# Front_Unit_5_4.net
KiCad netlist of a schematic drawn in EAGLE
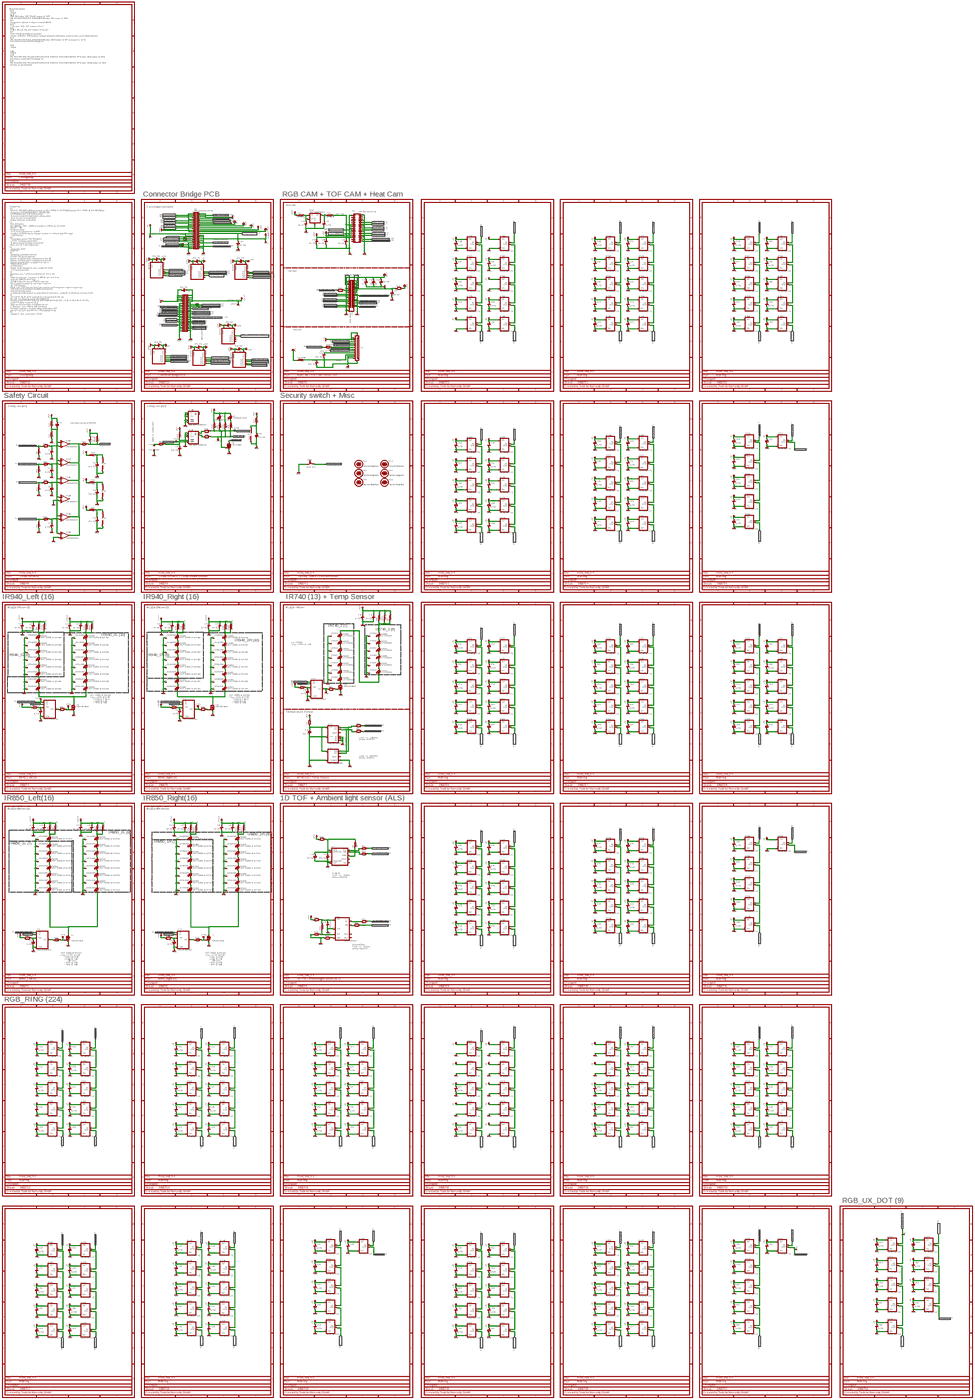
[diagram p0: schematic, sheet 1, overview]
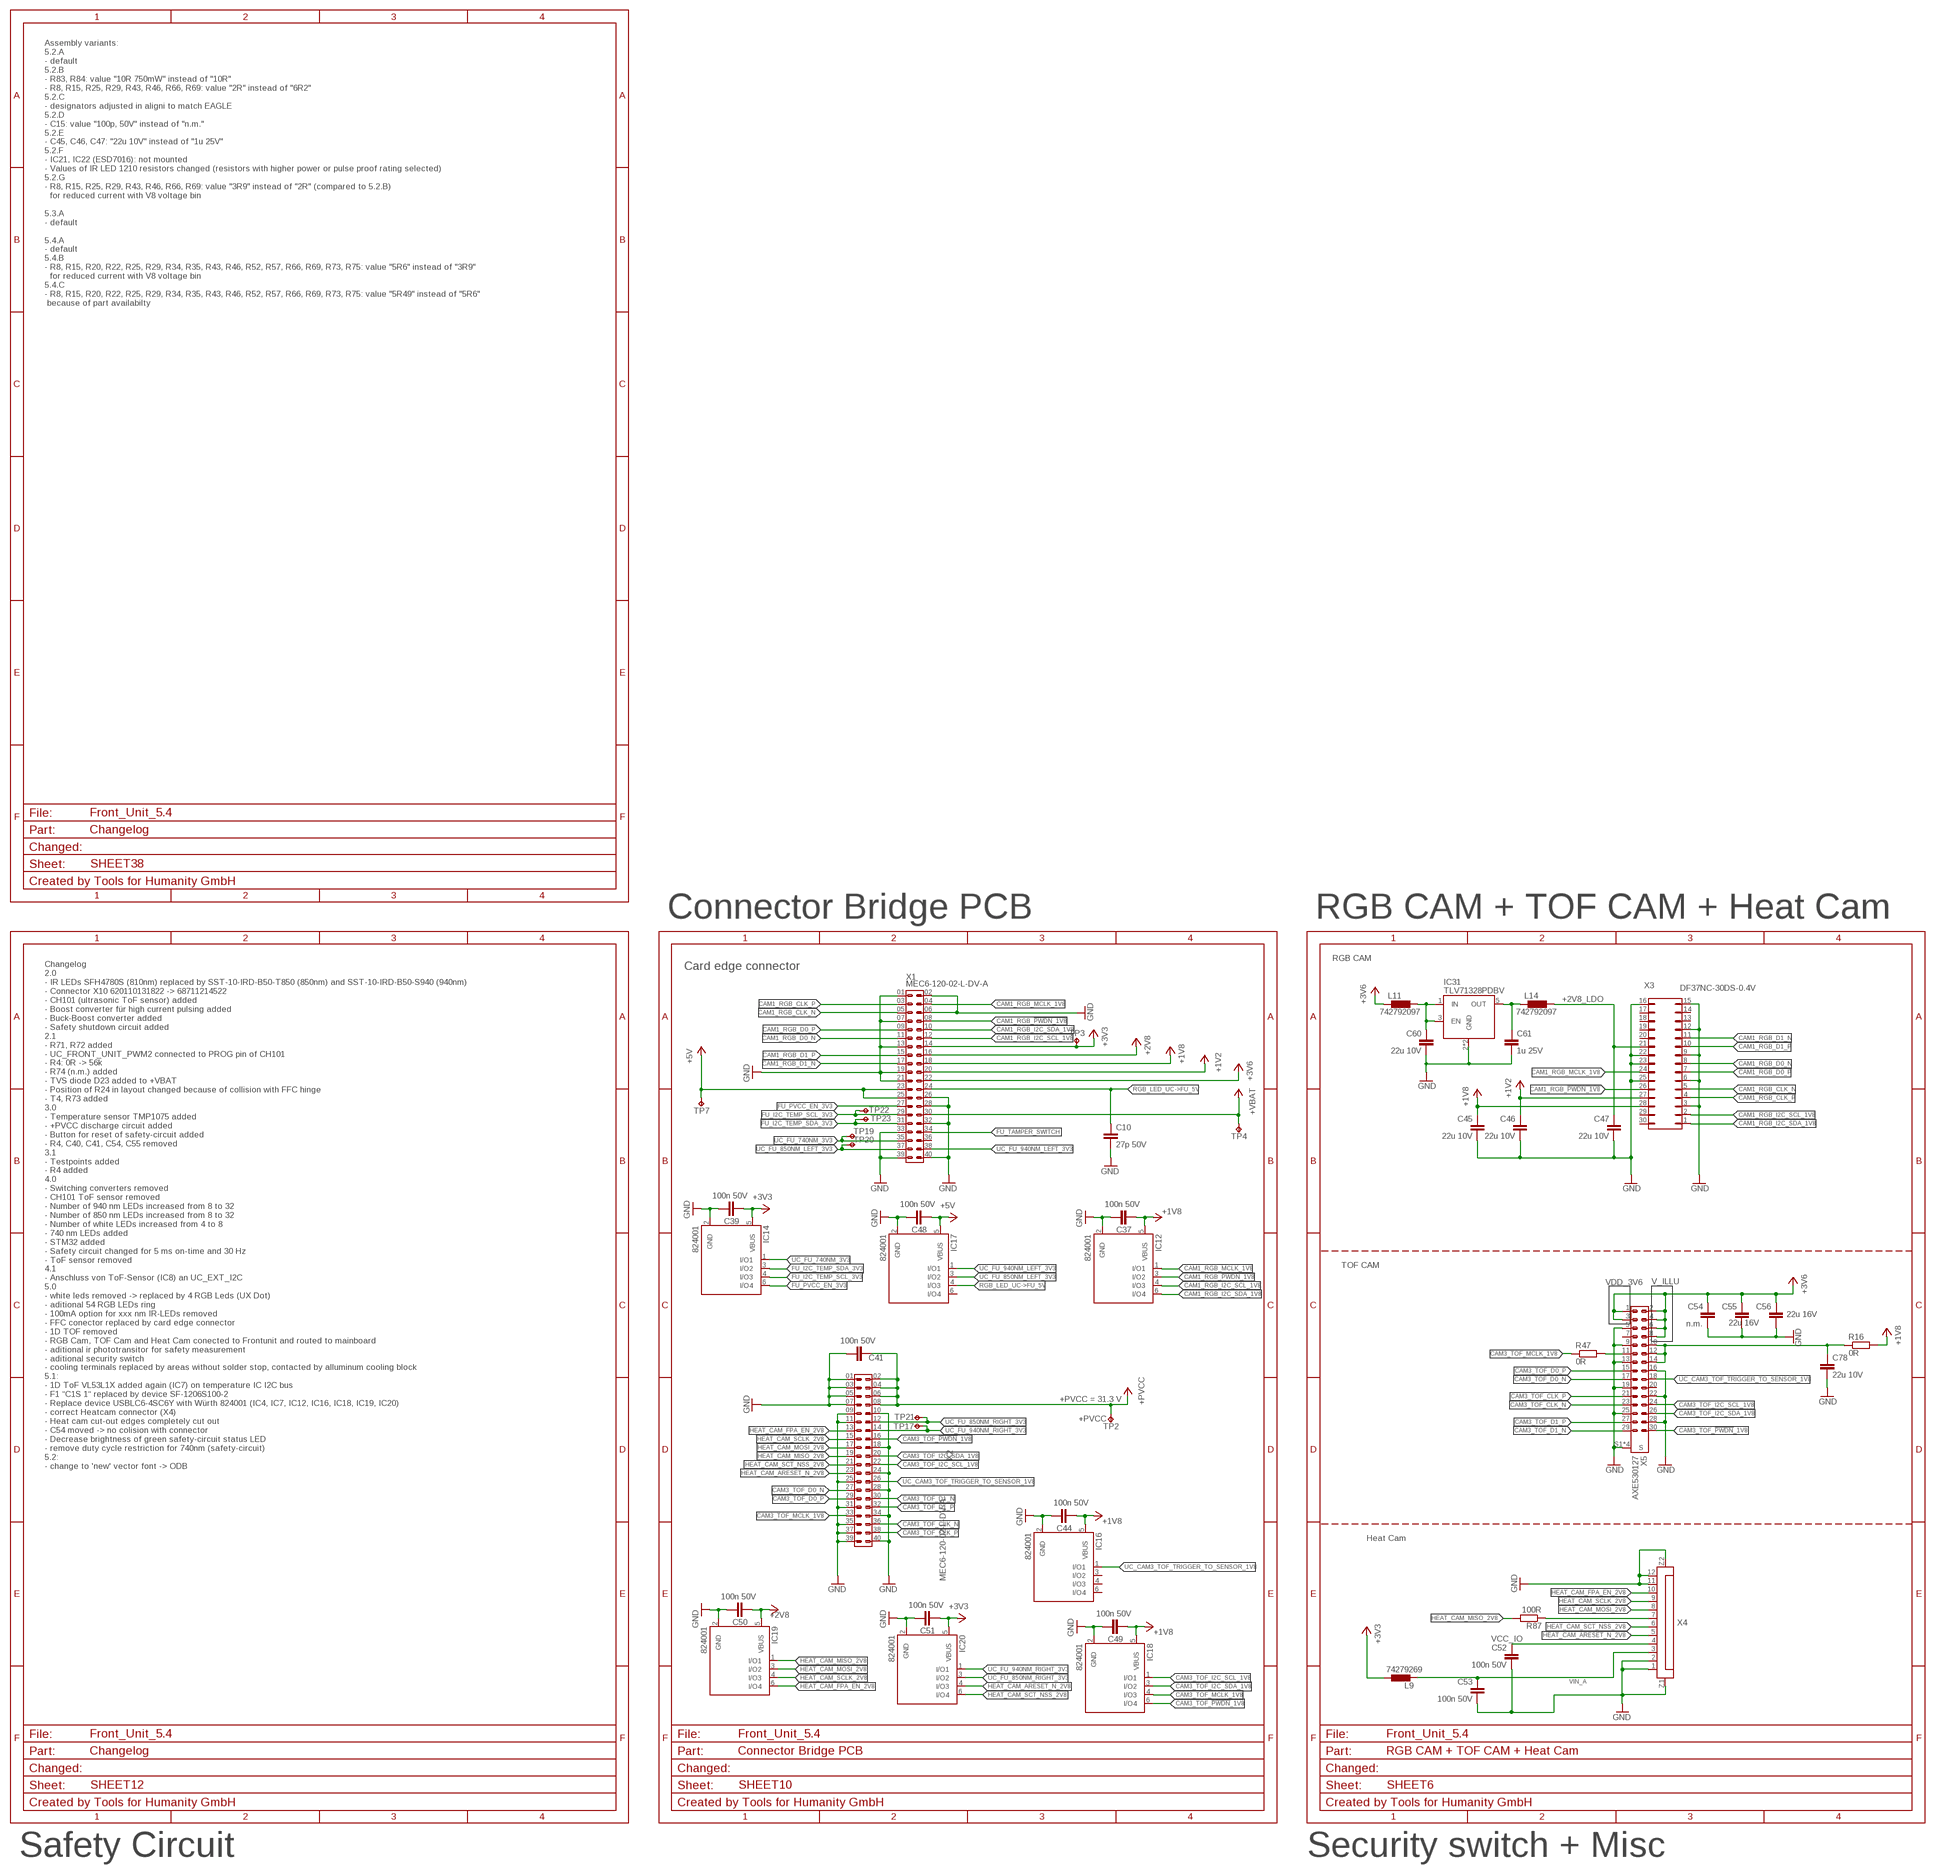
[diagram p1: schematic, sheet 1, part 1 of 8]
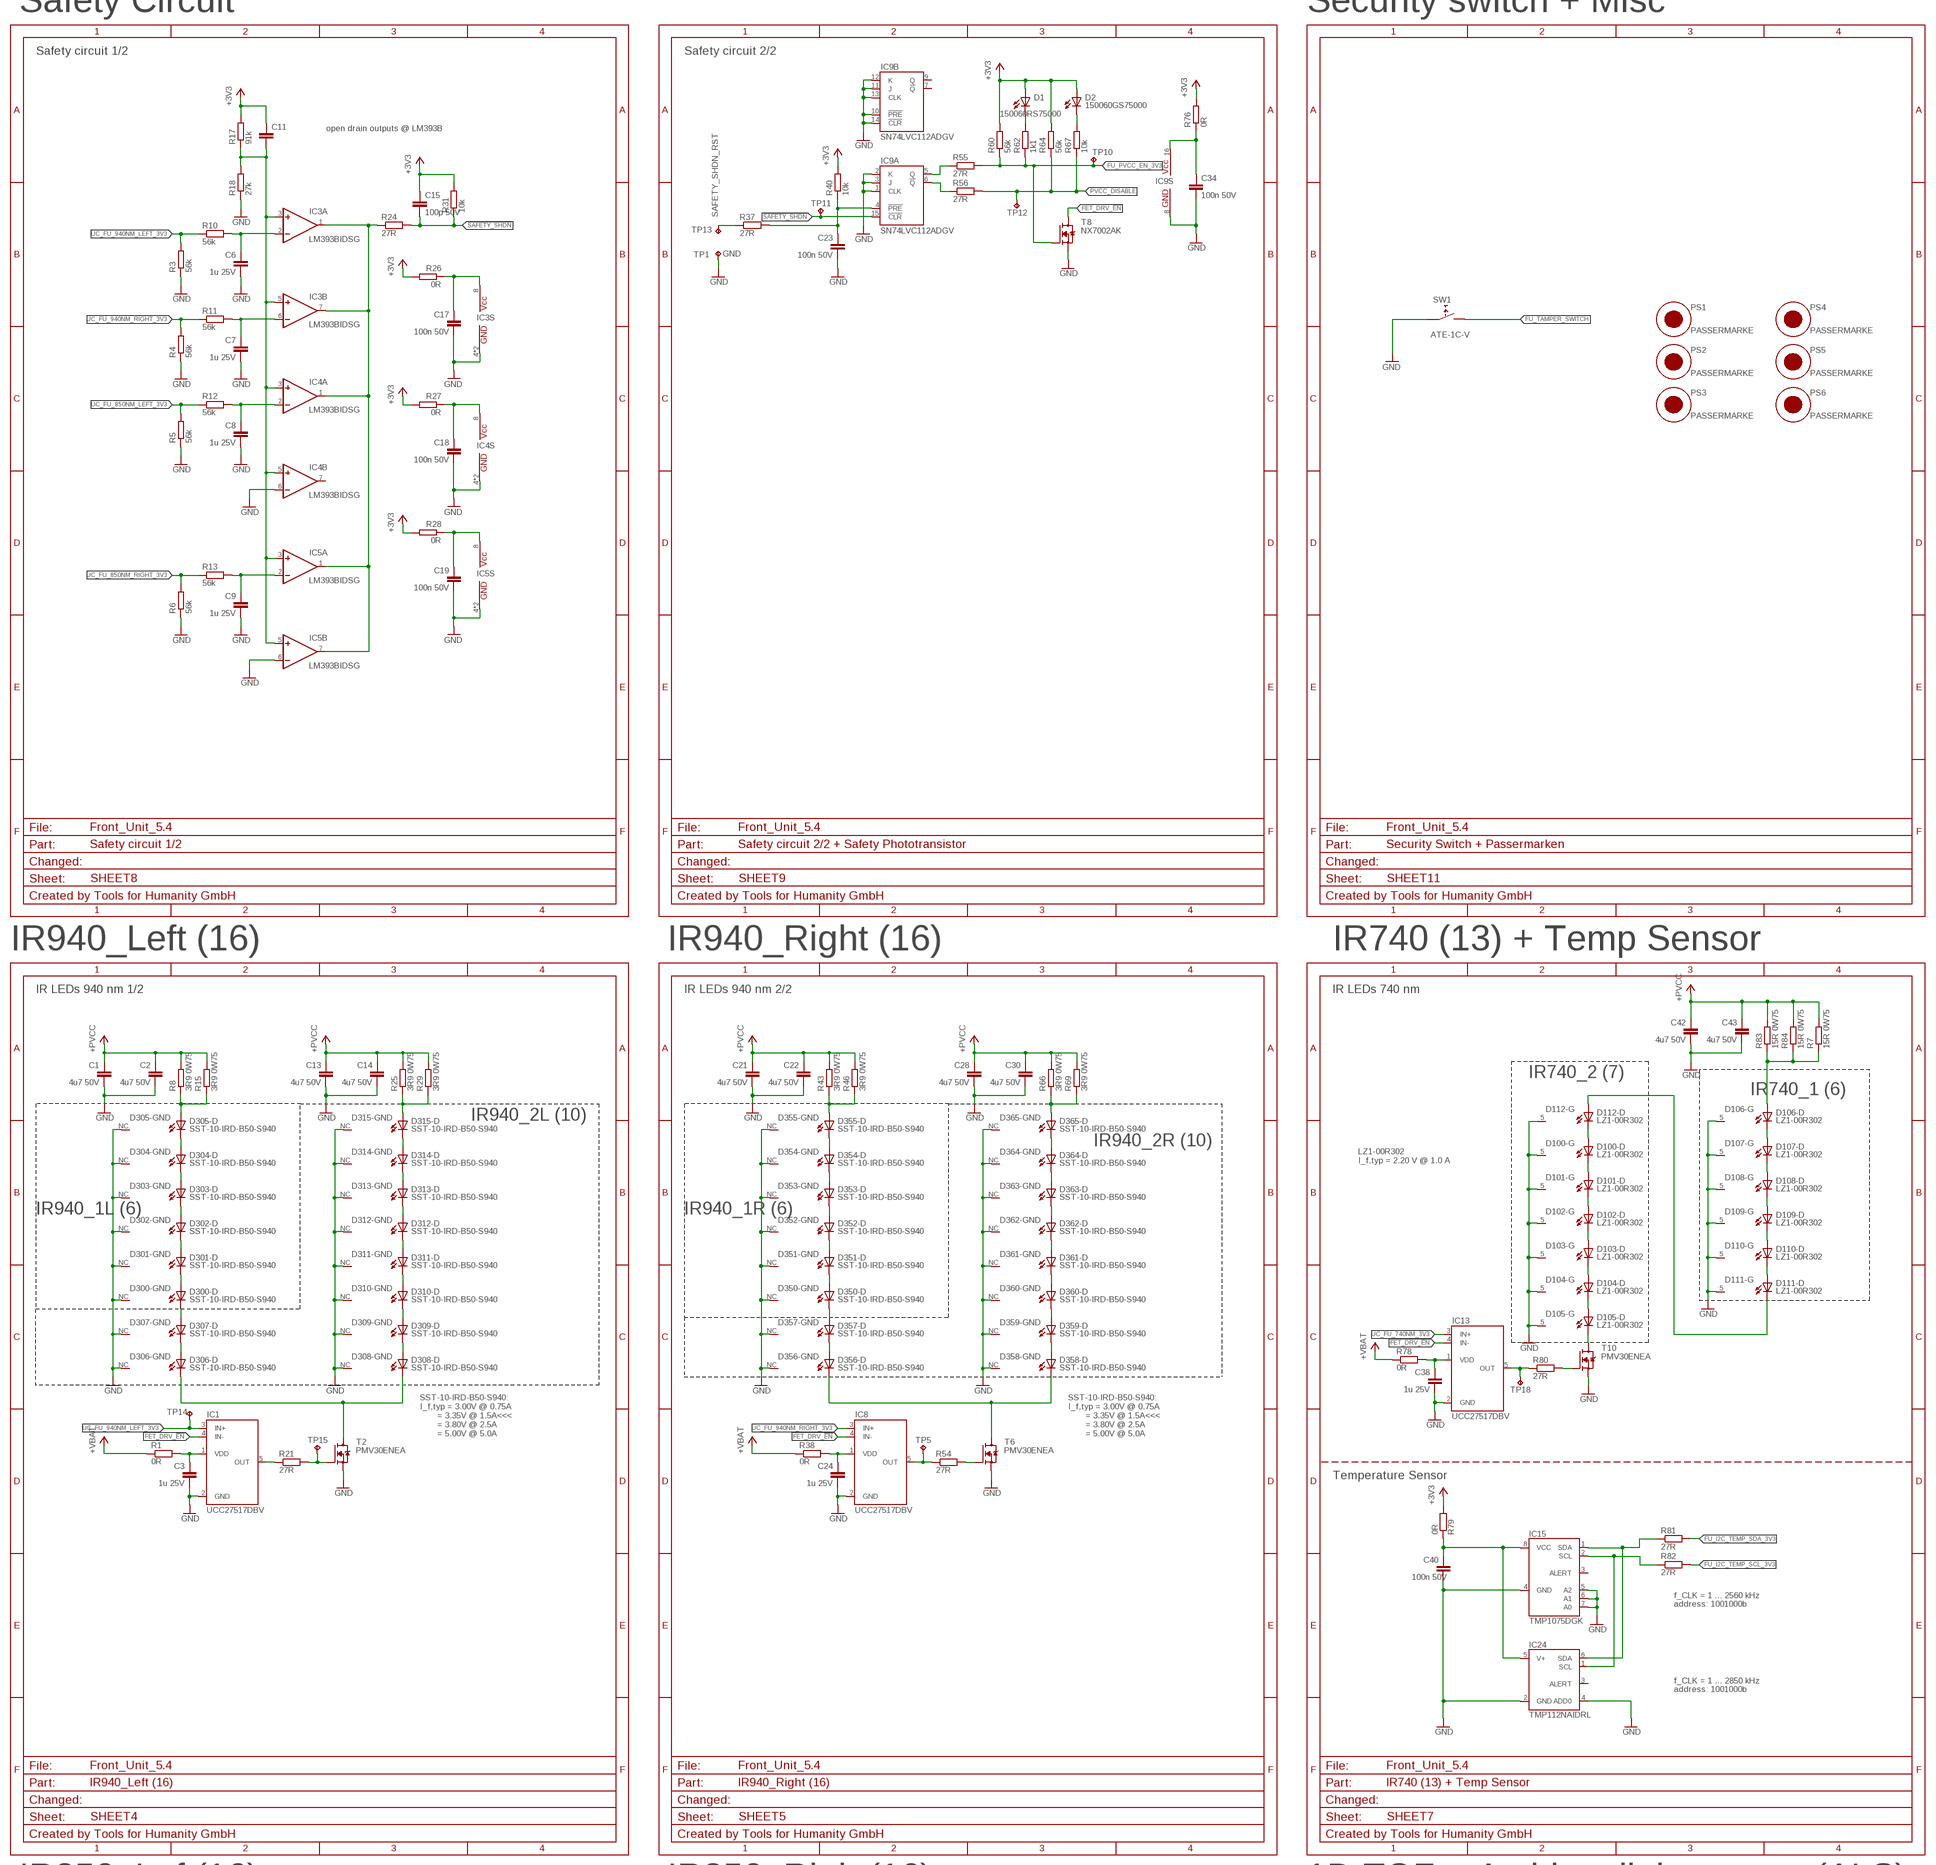
[diagram p2: schematic, sheet 1, part 2 of 8]
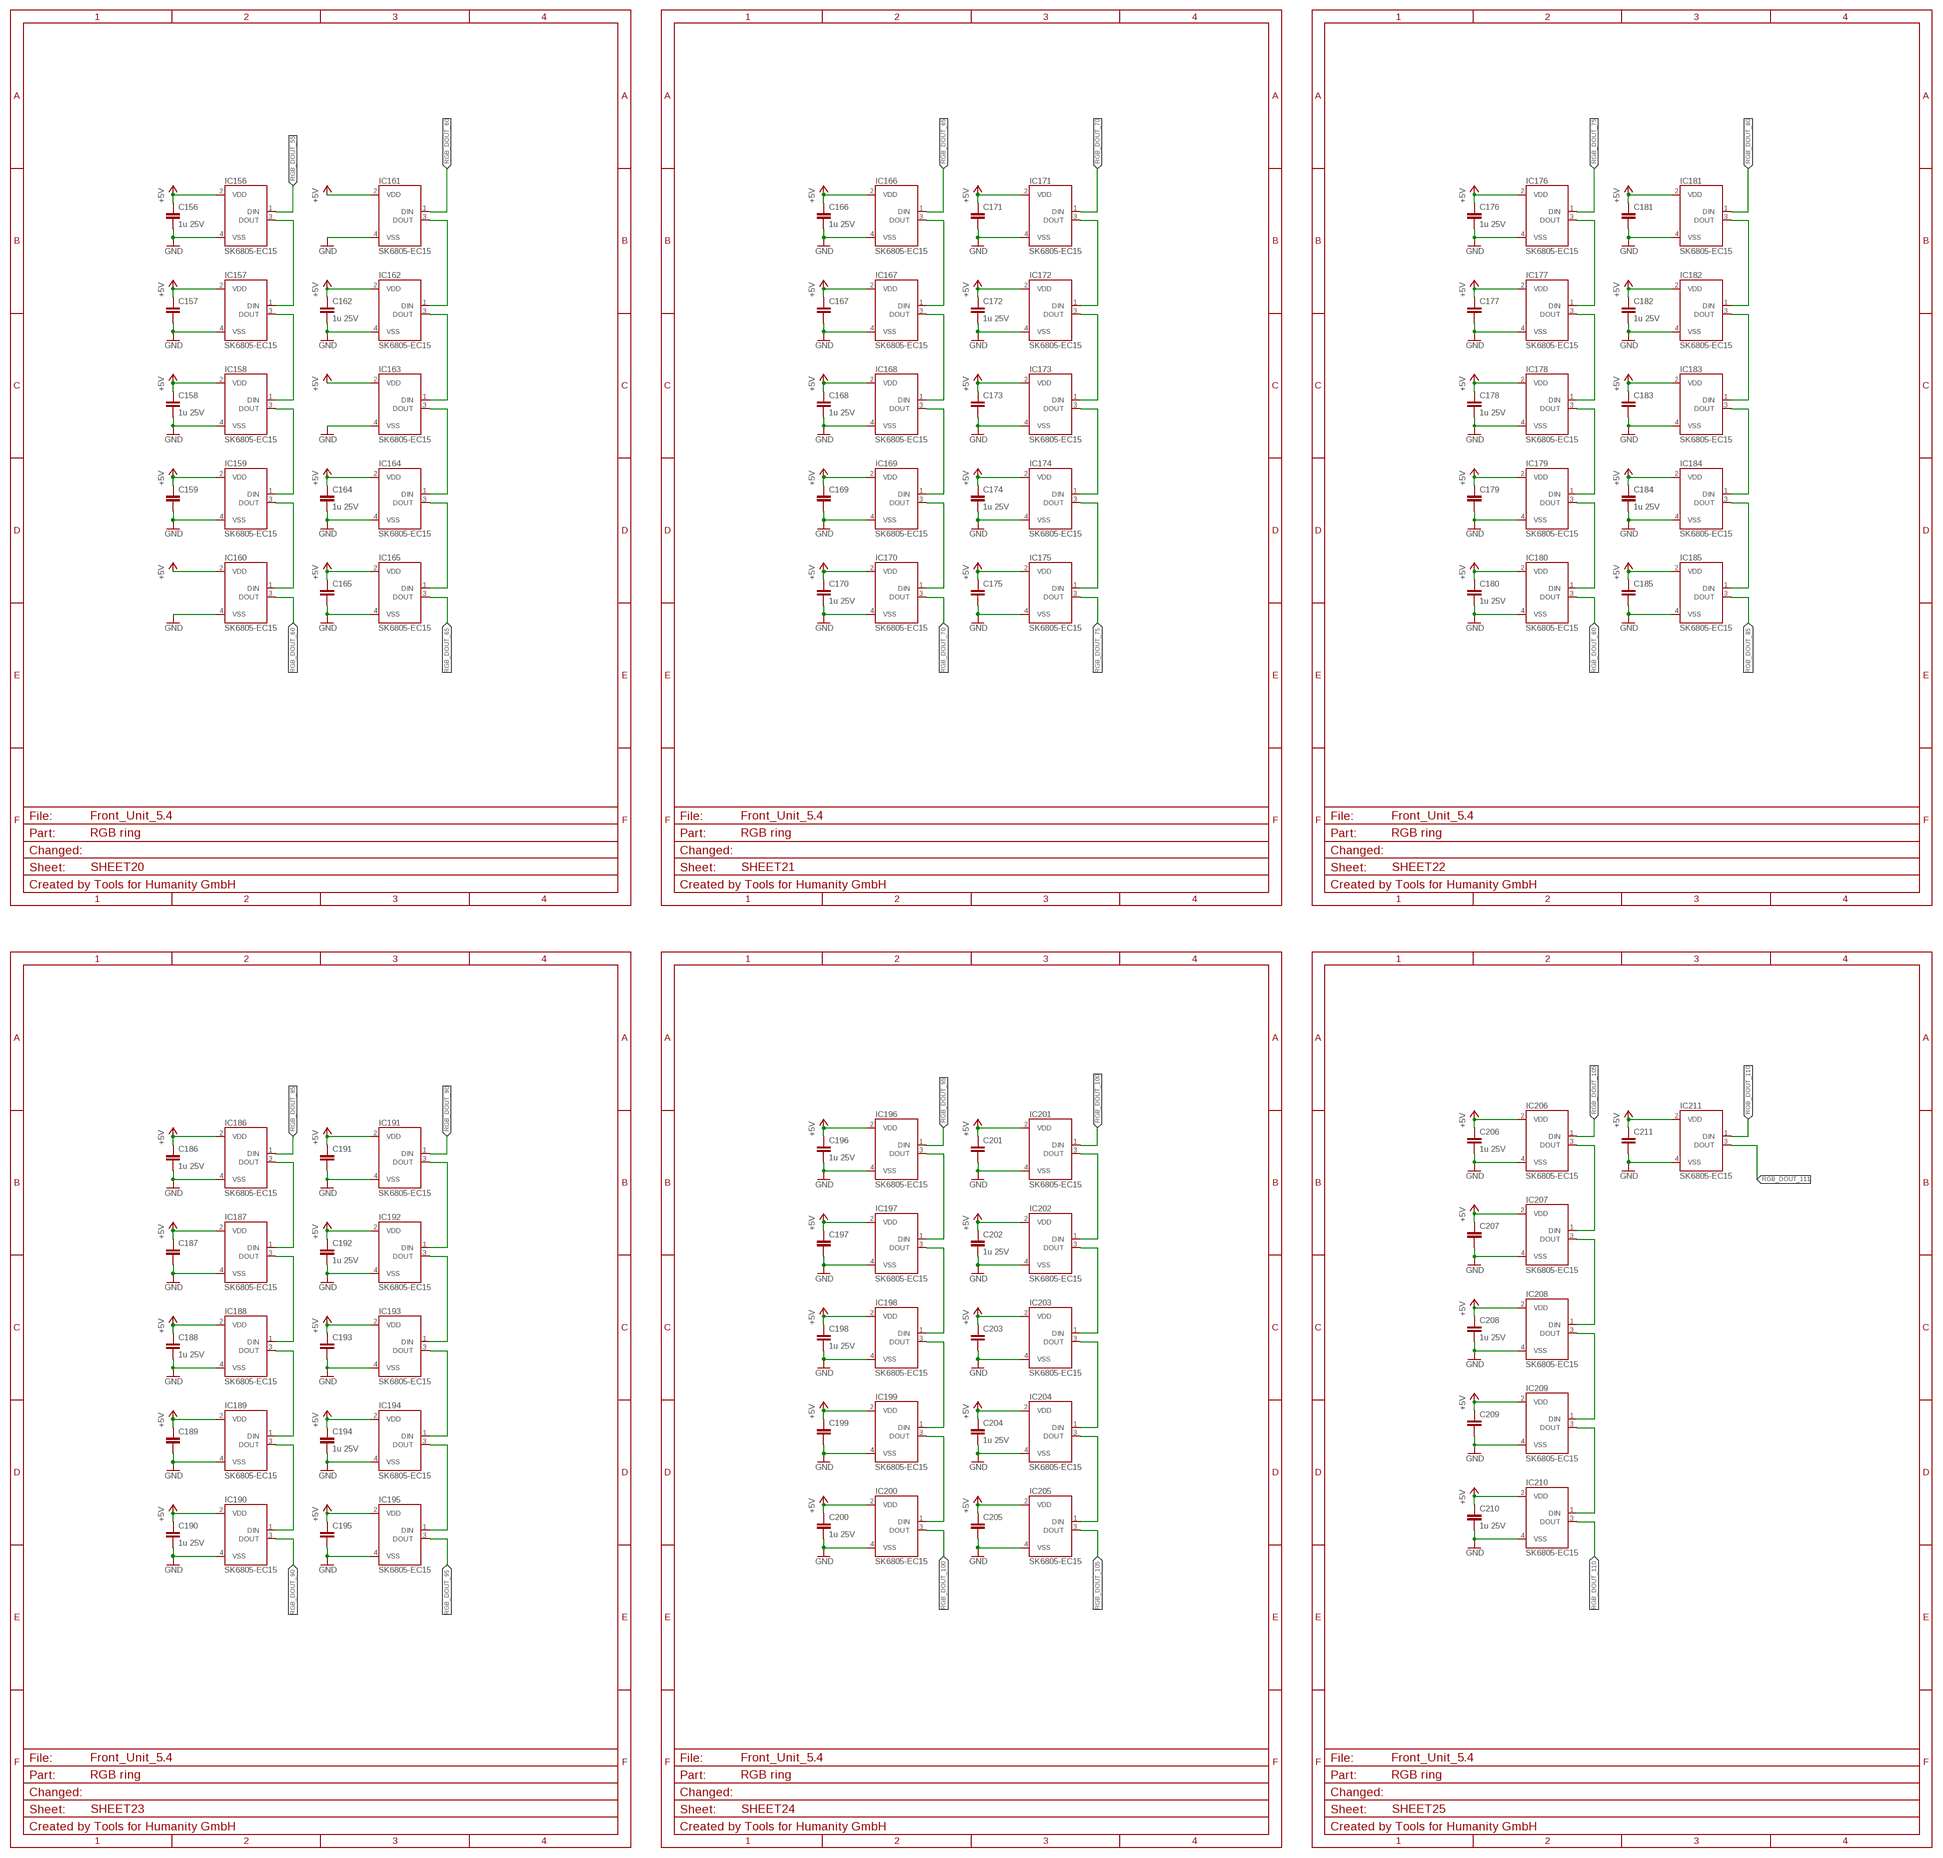
[diagram p3: schematic, sheet 1, part 3 of 8]
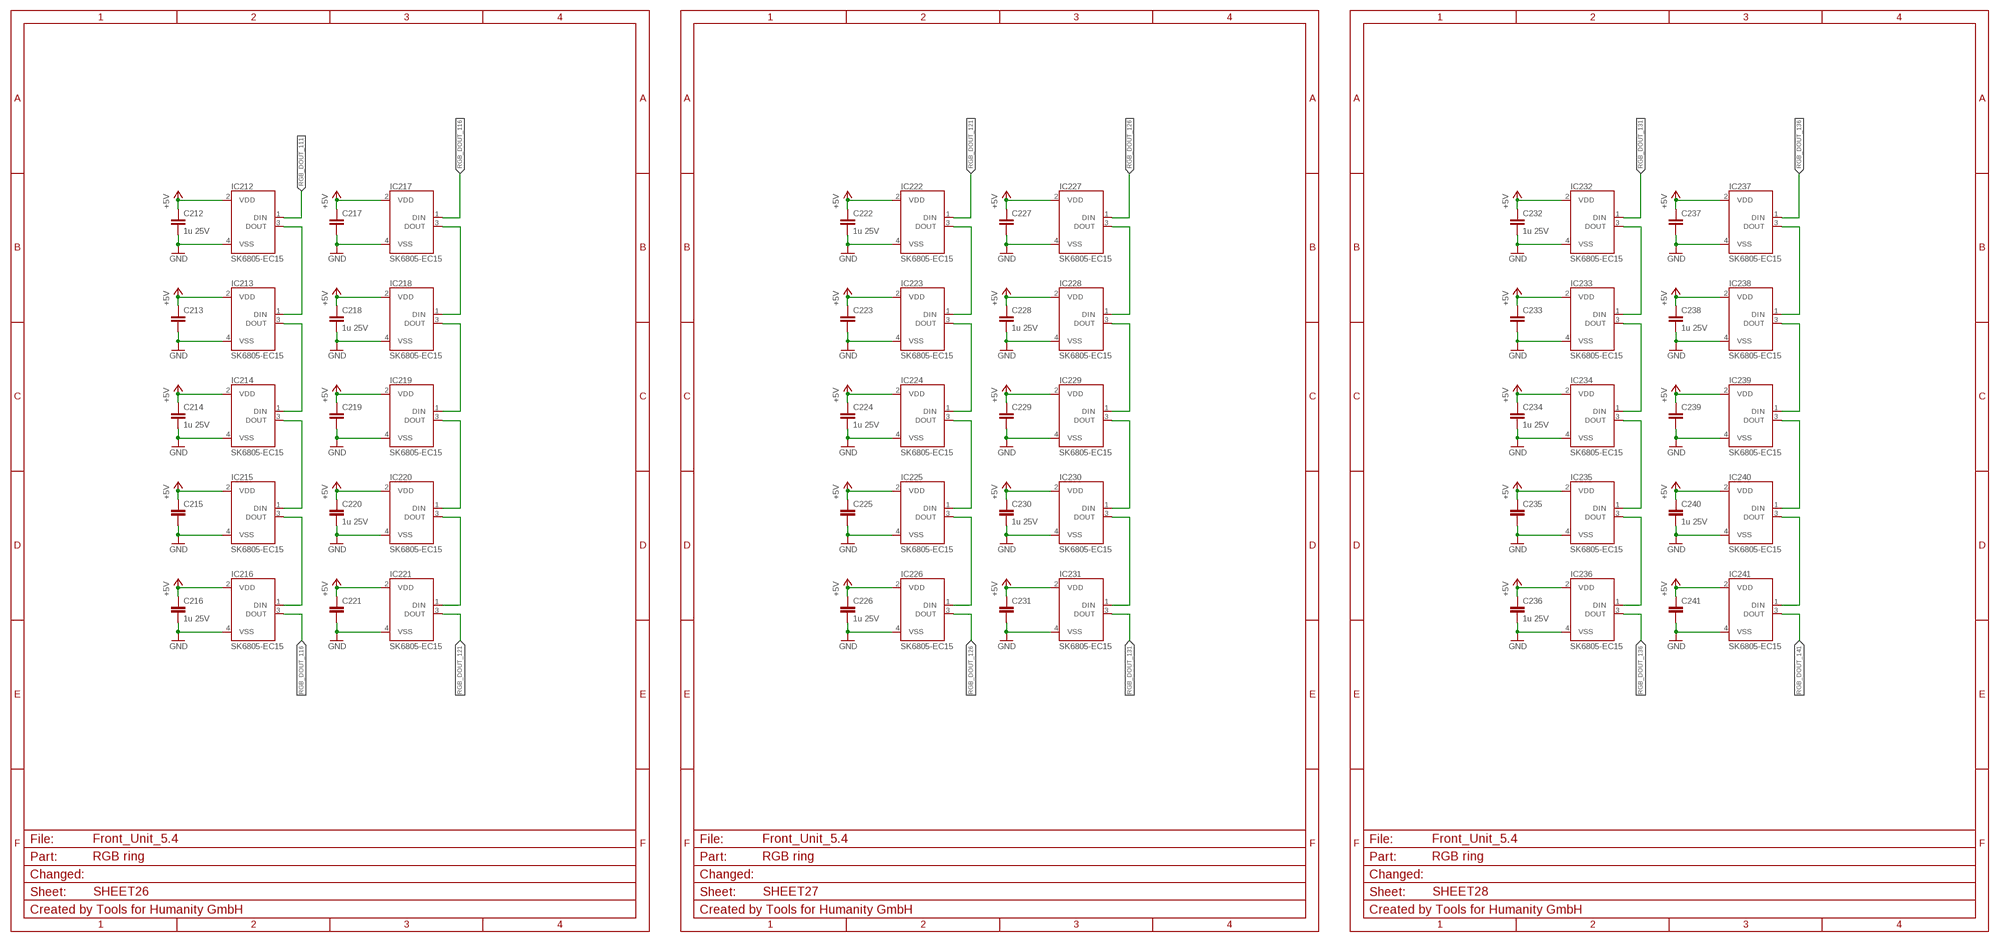
[diagram p4: schematic, sheet 1, part 4 of 8]
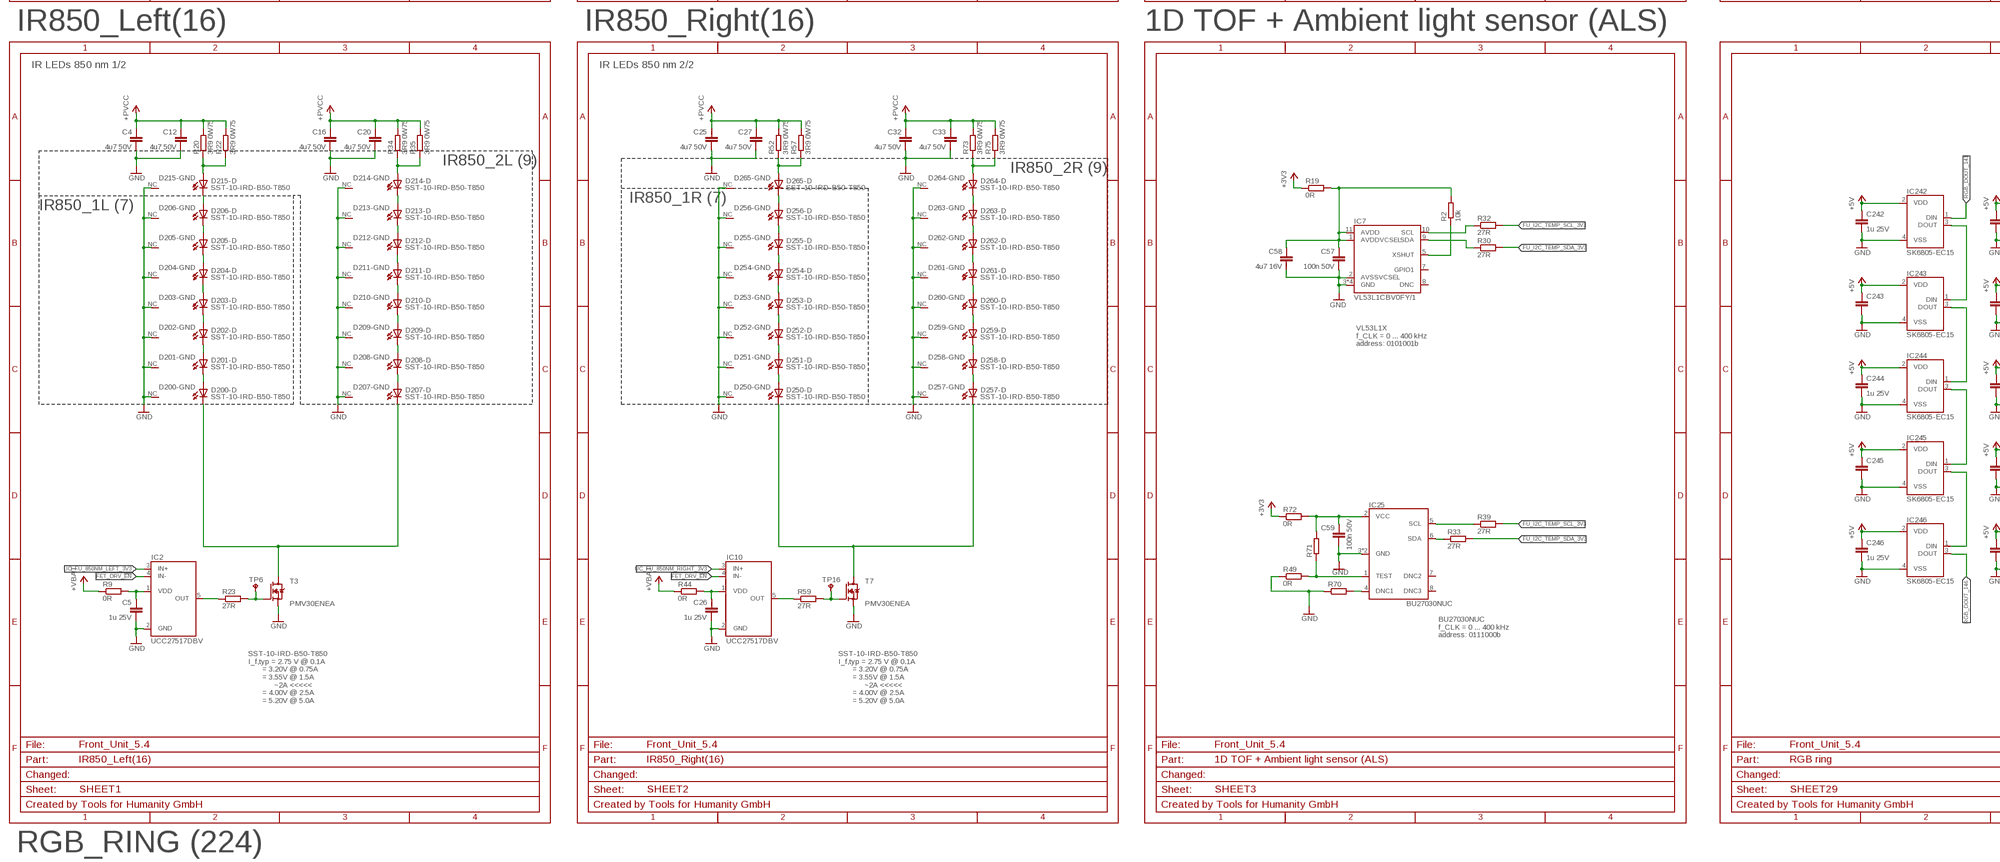
[diagram p5: schematic, sheet 1, part 5 of 8]
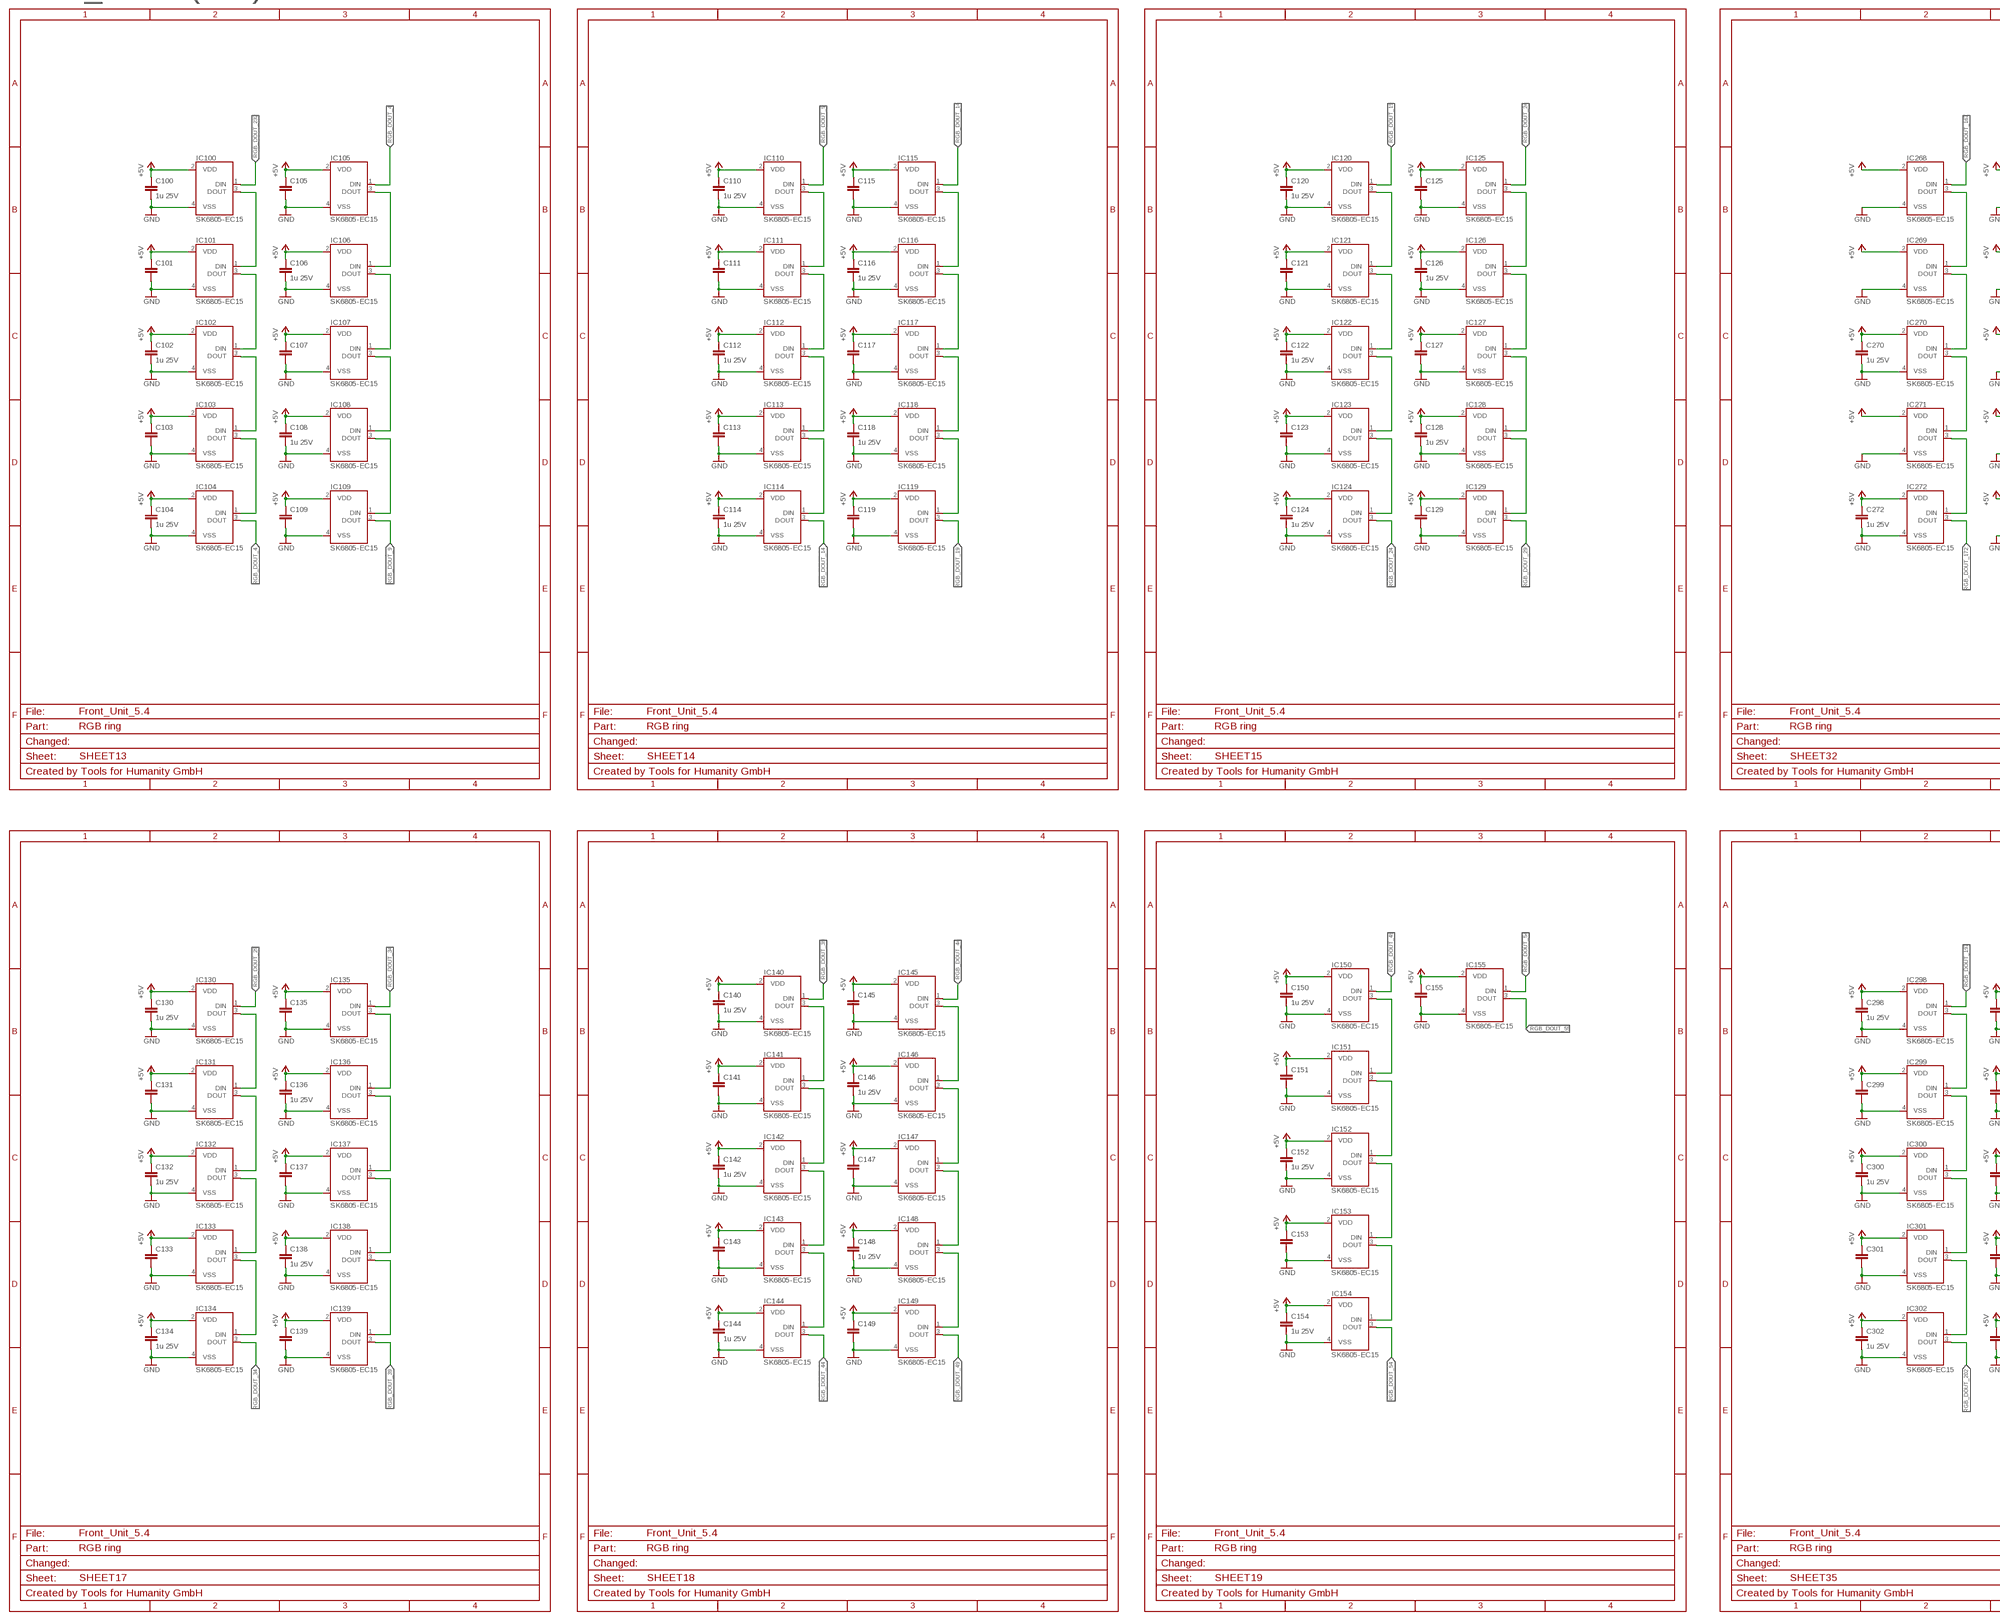
[diagram p6: schematic, sheet 1, part 6 of 8]
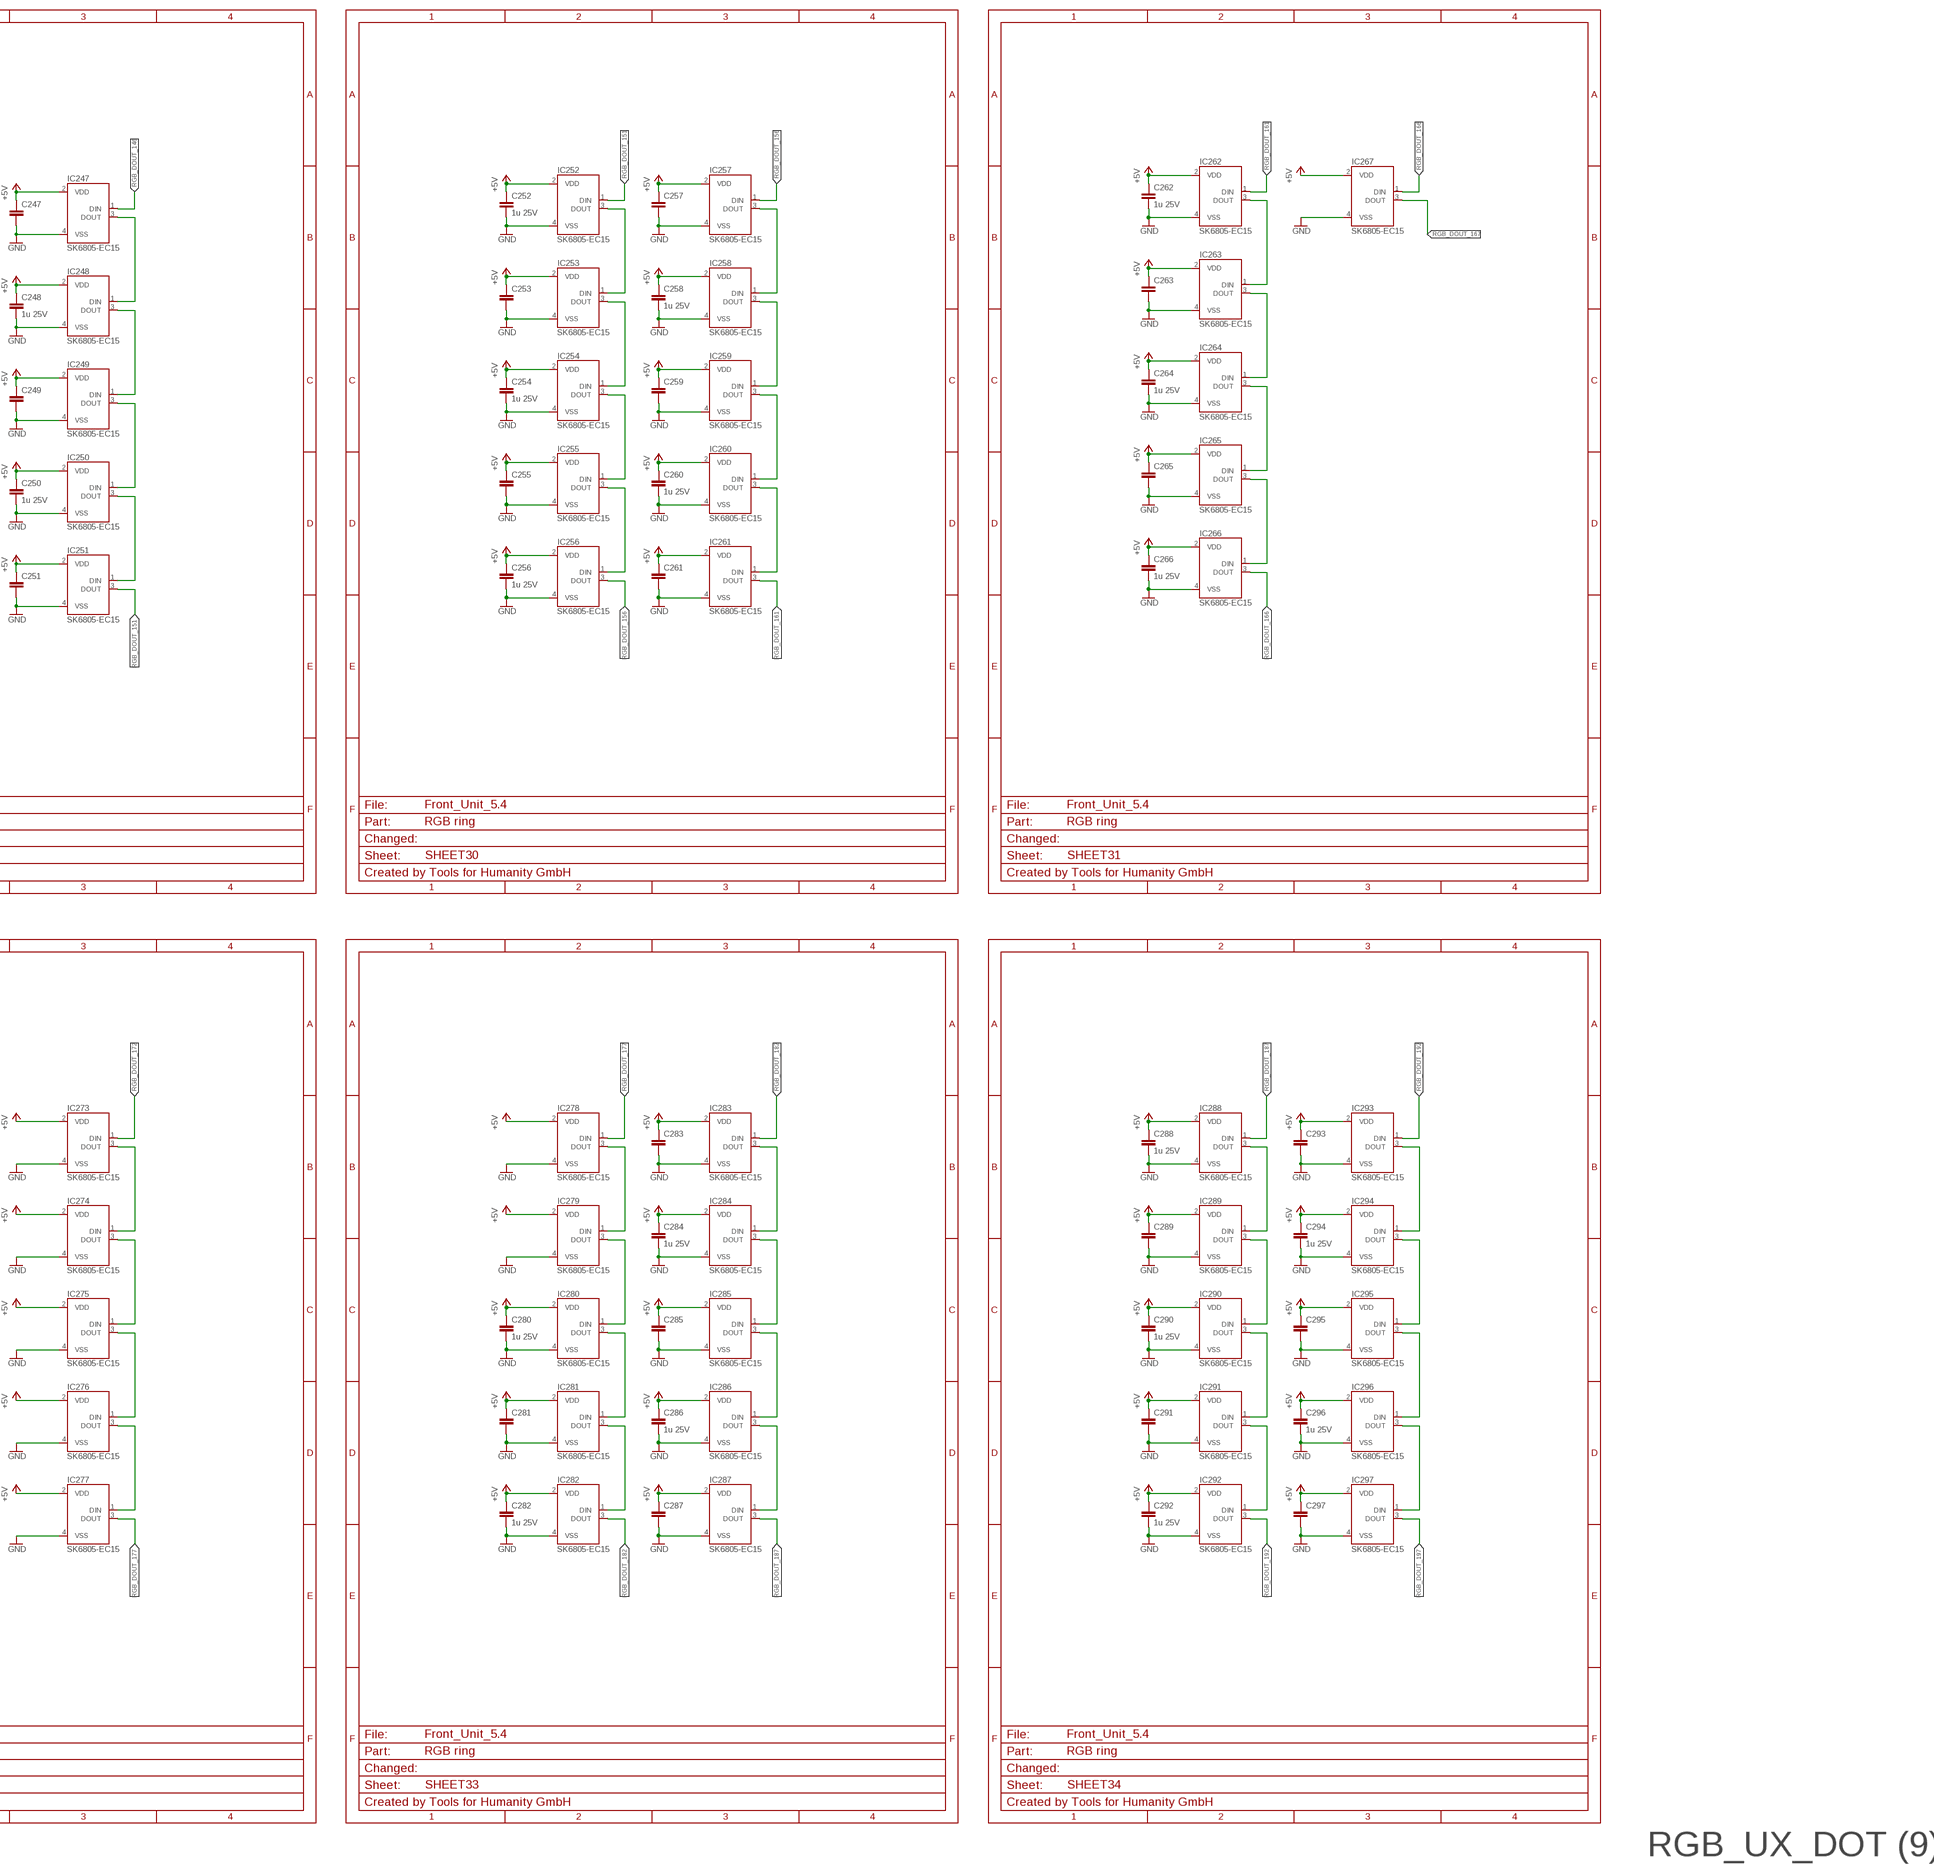
[diagram p7: schematic, sheet 1, part 7 of 8]
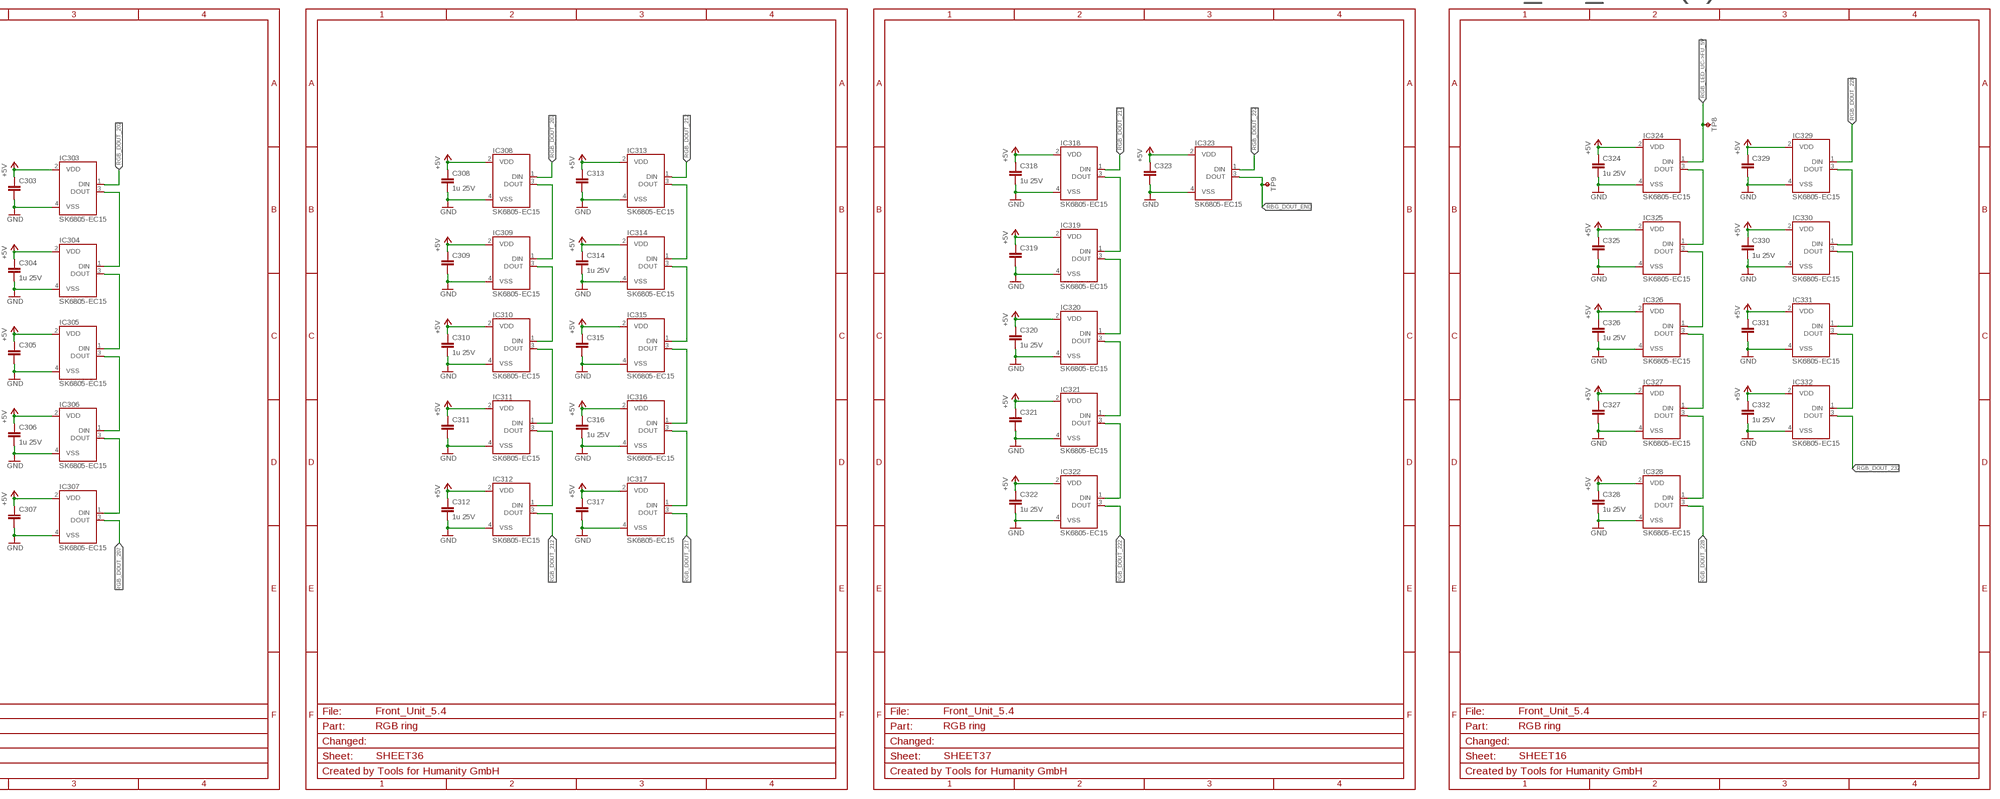
[diagram p8: schematic, sheet 1, part 8 of 8]

(export (version "E")
  (design (tool "Eeschema 10.0.6"))
  (components
    (comp (ref "C1")
      (value "4u7 50V")
      (footprint "eagle-import:C1210")
      (fields
        (field (name "MANUFACTURER") "free choice")
        (field (name "TOLERANCE") "±20 %")
        (field (name "VOLTAGE") "50.0 V")
      )
      (libsource (lib "eagle-import") (part "C-EU-C1210-4U7-50V"))
    )
    (comp (ref "C2")
      (value "4u7 50V")
      (footprint "eagle-import:C1210")
      (fields
        (field (name "MANUFACTURER") "free choice")
        (field (name "TOLERANCE") "±20 %")
        (field (name "VOLTAGE") "50.0 V")
      )
      (libsource (lib "eagle-import") (part "C-EU-C1210-4U7-50V"))
    )
    (comp (ref "C3")
      (value "1u 25V")
      (footprint "eagle-import:C0805")
      (fields
        (field (name "MANUFACTURER") "free choice")
        (field (name "TOLERANCE") "±20 %")
        (field (name "VOLTAGE") "25.0 V")
      )
      (libsource (lib "eagle-import") (part "C-EU-C0805-1U"))
    )
    (comp (ref "C4")
      (value "4u7 50V")
      (footprint "eagle-import:C1210")
      (fields
        (field (name "MANUFACTURER") "free choice")
        (field (name "TOLERANCE") "±20 %")
        (field (name "VOLTAGE") "50.0 V")
      )
      (libsource (lib "eagle-import") (part "C-EU-C1210-4U7-50V"))
    )
    (comp (ref "C5")
      (value "1u 25V")
      (footprint "eagle-import:C0805")
      (fields
        (field (name "MANUFACTURER") "free choice")
        (field (name "TOLERANCE") "±20 %")
        (field (name "VOLTAGE") "25.0 V")
      )
      (libsource (lib "eagle-import") (part "C-EU-C0805-1U"))
    )
    (comp (ref "C6")
      (value "1u 25V")
      (footprint "eagle-import:C0805")
      (fields
        (field (name "MANUFACTURER") "free choice")
        (field (name "TOLERANCE") "±20 %")
        (field (name "VOLTAGE") "25.0 V")
      )
      (libsource (lib "eagle-import") (part "C-EU-C0805-1U"))
    )
    (comp (ref "C7")
      (value "1u 25V")
      (footprint "eagle-import:C0805")
      (fields
        (field (name "MANUFACTURER") "free choice")
        (field (name "TOLERANCE") "±20 %")
        (field (name "VOLTAGE") "25.0 V")
      )
      (libsource (lib "eagle-import") (part "C-EU-C0805-1U"))
    )
    (comp (ref "C8")
      (value "1u 25V")
      (footprint "eagle-import:C0805")
      (fields
        (field (name "MANUFACTURER") "free choice")
        (field (name "TOLERANCE") "±20 %")
        (field (name "VOLTAGE") "25.0 V")
      )
      (libsource (lib "eagle-import") (part "C-EU-C0805-1U"))
    )
    (comp (ref "C9")
      (value "1u 25V")
      (footprint "eagle-import:C0805")
      (fields
        (field (name "MANUFACTURER") "free choice")
        (field (name "TOLERANCE") "±20 %")
        (field (name "VOLTAGE") "25.0 V")
      )
      (libsource (lib "eagle-import") (part "C-EU-C0805-1U"))
    )
    (comp (ref "C10")
      (value "27p 50V")
      (footprint "eagle-import:C0603")
      (fields
        (field (name "MANUFACTURER") "free choice")
        (field (name "TOLERANCE") "±20 %")
        (field (name "VOLTAGE") "50.0 V")
      )
      (libsource (lib "eagle-import") (part "C-EU-C0603-27P"))
    )
    (comp (ref "C11")
      (value "C-EU-C0603")
      (footprint "eagle-import:C0603")
      (fields (field (name "TOLERANCE") "±20 %") (field (name "VOLTAGE") "50.0 V"))
      (libsource (lib "eagle-import") (part "C-EU-C0603"))
    )
    (comp (ref "C12")
      (value "4u7 50V")
      (footprint "eagle-import:C1210")
      (fields
        (field (name "MANUFACTURER") "free choice")
        (field (name "TOLERANCE") "±20 %")
        (field (name "VOLTAGE") "50.0 V")
      )
      (libsource (lib "eagle-import") (part "C-EU-C1210-4U7-50V"))
    )
    (comp (ref "C13")
      (value "4u7 50V")
      (footprint "eagle-import:C1210")
      (fields
        (field (name "MANUFACTURER") "free choice")
        (field (name "TOLERANCE") "±20 %")
        (field (name "VOLTAGE") "50.0 V")
      )
      (libsource (lib "eagle-import") (part "C-EU-C1210-4U7-50V"))
    )
    (comp (ref "C14")
      (value "4u7 50V")
      (footprint "eagle-import:C1210")
      (fields
        (field (name "MANUFACTURER") "free choice")
        (field (name "TOLERANCE") "±20 %")
        (field (name "VOLTAGE") "50.0 V")
      )
      (libsource (lib "eagle-import") (part "C-EU-C1210-4U7-50V"))
    )
    (comp (ref "C15")
      (value "100p 50V")
      (footprint "eagle-import:C0603")
      (fields
        (field (name "MANUFACTURER") "free choice")
        (field (name "TOLERANCE") "±10 %")
        (field (name "VOLTAGE") "50.0 V")
      )
      (libsource (lib "eagle-import") (part "C-EU-C0603-100P"))
    )
    (comp (ref "C16")
      (value "4u7 50V")
      (footprint "eagle-import:C1210")
      (fields
        (field (name "MANUFACTURER") "free choice")
        (field (name "TOLERANCE") "±20 %")
        (field (name "VOLTAGE") "50.0 V")
      )
      (libsource (lib "eagle-import") (part "C-EU-C1210-4U7-50V"))
    )
    (comp (ref "C17")
      (value "100n 50V")
      (footprint "eagle-import:C0603")
      (fields
        (field (name "MANUFACTURER") "free choice")
        (field (name "TOLERANCE") "±20 %")
        (field (name "VOLTAGE") "50.0 V")
      )
      (libsource (lib "eagle-import") (part "C-EU-C0603-100N"))
    )
    (comp (ref "C18")
      (value "100n 50V")
      (footprint "eagle-import:C0603")
      (fields
        (field (name "MANUFACTURER") "free choice")
        (field (name "TOLERANCE") "±20 %")
        (field (name "VOLTAGE") "50.0 V")
      )
      (libsource (lib "eagle-import") (part "C-EU-C0603-100N"))
    )
    (comp (ref "C19")
      (value "100n 50V")
      (footprint "eagle-import:C0603")
      (fields
        (field (name "MANUFACTURER") "free choice")
        (field (name "TOLERANCE") "±20 %")
        (field (name "VOLTAGE") "50.0 V")
      )
      (libsource (lib "eagle-import") (part "C-EU-C0603-100N"))
    )
    (comp (ref "C20")
      (value "4u7 50V")
      (footprint "eagle-import:C1210")
      (fields
        (field (name "MANUFACTURER") "free choice")
        (field (name "TOLERANCE") "±20 %")
        (field (name "VOLTAGE") "50.0 V")
      )
      (libsource (lib "eagle-import") (part "C-EU-C1210-4U7-50V"))
    )
    (comp (ref "C21")
      (value "4u7 50V")
      (footprint "eagle-import:C1210")
      (fields
        (field (name "MANUFACTURER") "free choice")
        (field (name "TOLERANCE") "±20 %")
        (field (name "VOLTAGE") "50.0 V")
      )
      (libsource (lib "eagle-import") (part "C-EU-C1210-4U7-50V"))
    )
    (comp (ref "C22")
      (value "4u7 50V")
      (footprint "eagle-import:C1210")
      (fields
        (field (name "MANUFACTURER") "free choice")
        (field (name "TOLERANCE") "±20 %")
        (field (name "VOLTAGE") "50.0 V")
      )
      (libsource (lib "eagle-import") (part "C-EU-C1210-4U7-50V"))
    )
    (comp (ref "C23")
      (value "100n 50V")
      (footprint "eagle-import:C0603")
      (fields
        (field (name "MANUFACTURER") "free choice")
        (field (name "TOLERANCE") "±20 %")
        (field (name "VOLTAGE") "50.0 V")
      )
      (libsource (lib "eagle-import") (part "C-EU-C0603-100N"))
    )
    (comp (ref "C24")
      (value "1u 25V")
      (footprint "eagle-import:C0805")
      (fields
        (field (name "MANUFACTURER") "free choice")
        (field (name "TOLERANCE") "±20 %")
        (field (name "VOLTAGE") "25.0 V")
      )
      (libsource (lib "eagle-import") (part "C-EU-C0805-1U"))
    )
    (comp (ref "C25")
      (value "4u7 50V")
      (footprint "eagle-import:C1210")
      (fields
        (field (name "MANUFACTURER") "free choice")
        (field (name "TOLERANCE") "±20 %")
        (field (name "VOLTAGE") "50.0 V")
      )
      (libsource (lib "eagle-import") (part "C-EU-C1210-4U7-50V"))
    )
    (comp (ref "C26")
      (value "1u 25V")
      (footprint "eagle-import:C0805")
      (fields
        (field (name "MANUFACTURER") "free choice")
        (field (name "TOLERANCE") "±20 %")
        (field (name "VOLTAGE") "25.0 V")
      )
      (libsource (lib "eagle-import") (part "C-EU-C0805-1U"))
    )
    (comp (ref "C27")
      (value "4u7 50V")
      (footprint "eagle-import:C1210")
      (fields
        (field (name "MANUFACTURER") "free choice")
        (field (name "TOLERANCE") "±20 %")
        (field (name "VOLTAGE") "50.0 V")
      )
      (libsource (lib "eagle-import") (part "C-EU-C1210-4U7-50V"))
    )
    (comp (ref "C28")
      (value "4u7 50V")
      (footprint "eagle-import:C1210")
      (fields
        (field (name "MANUFACTURER") "free choice")
        (field (name "TOLERANCE") "±20 %")
        (field (name "VOLTAGE") "50.0 V")
      )
      (libsource (lib "eagle-import") (part "C-EU-C1210-4U7-50V"))
    )
    (comp (ref "C30")
      (value "4u7 50V")
      (footprint "eagle-import:C1210")
      (fields
        (field (name "MANUFACTURER") "free choice")
        (field (name "TOLERANCE") "±20 %")
        (field (name "VOLTAGE") "50.0 V")
      )
      (libsource (lib "eagle-import") (part "C-EU-C1210-4U7-50V"))
    )
    (comp (ref "C32")
      (value "4u7 50V")
      (footprint "eagle-import:C1210")
      (fields
        (field (name "MANUFACTURER") "free choice")
        (field (name "TOLERANCE") "±20 %")
        (field (name "VOLTAGE") "50.0 V")
      )
      (libsource (lib "eagle-import") (part "C-EU-C1210-4U7-50V"))
    )
    (comp (ref "C33")
      (value "4u7 50V")
      (footprint "eagle-import:C1210")
      (fields
        (field (name "MANUFACTURER") "free choice")
        (field (name "TOLERANCE") "±20 %")
        (field (name "VOLTAGE") "50.0 V")
      )
      (libsource (lib "eagle-import") (part "C-EU-C1210-4U7-50V"))
    )
    (comp (ref "C34")
      (value "100n 50V")
      (footprint "eagle-import:C0603")
      (fields
        (field (name "MANUFACTURER") "free choice")
        (field (name "TOLERANCE") "±20 %")
        (field (name "VOLTAGE") "50.0 V")
      )
      (libsource (lib "eagle-import") (part "C-EU-C0603-100N"))
    )
    (comp (ref "C37")
      (value "100n 50V")
      (footprint "eagle-import:C0603")
      (fields
        (field (name "MANUFACTURER") "free choice")
        (field (name "TOLERANCE") "±20 %")
        (field (name "VOLTAGE") "50.0 V")
      )
      (libsource (lib "eagle-import") (part "C-EU-C0603-100N"))
    )
    (comp (ref "C38")
      (value "1u 25V")
      (footprint "eagle-import:C0805")
      (fields
        (field (name "MANUFACTURER") "free choice")
        (field (name "TOLERANCE") "±20 %")
        (field (name "VOLTAGE") "25.0 V")
      )
      (libsource (lib "eagle-import") (part "C-EU-C0805-1U"))
    )
    (comp (ref "C39")
      (value "100n 50V")
      (footprint "eagle-import:C0603")
      (fields
        (field (name "MANUFACTURER") "free choice")
        (field (name "TOLERANCE") "±20 %")
        (field (name "VOLTAGE") "50.0 V")
      )
      (libsource (lib "eagle-import") (part "C-EU-C0603-100N"))
    )
    (comp (ref "C40")
      (value "100n 50V")
      (footprint "eagle-import:C0603")
      (fields
        (field (name "MANUFACTURER") "free choice")
        (field (name "TOLERANCE") "±20 %")
        (field (name "VOLTAGE") "50.0 V")
      )
      (libsource (lib "eagle-import") (part "C-EU-C0603-100N"))
    )
    (comp (ref "C41")
      (value "100n 50V")
      (footprint "eagle-import:C0603")
      (fields
        (field (name "MANUFACTURER") "free choice")
        (field (name "TOLERANCE") "±20 %")
        (field (name "VOLTAGE") "50.0 V")
      )
      (libsource (lib "eagle-import") (part "C-EU-C0603-100N"))
    )
    (comp (ref "C42")
      (value "4u7 50V")
      (footprint "eagle-import:C1210")
      (fields
        (field (name "MANUFACTURER") "free choice")
        (field (name "TOLERANCE") "±20 %")
        (field (name "VOLTAGE") "50.0 V")
      )
      (libsource (lib "eagle-import") (part "C-EU-C1210-4U7-50V"))
    )
    (comp (ref "C43")
      (value "4u7 50V")
      (footprint "eagle-import:C1210")
      (fields
        (field (name "MANUFACTURER") "free choice")
        (field (name "TOLERANCE") "±20 %")
        (field (name "VOLTAGE") "50.0 V")
      )
      (libsource (lib "eagle-import") (part "C-EU-C1210-4U7-50V"))
    )
    (comp (ref "C44")
      (value "100n 50V")
      (footprint "eagle-import:C0603")
      (fields
        (field (name "MANUFACTURER") "free choice")
        (field (name "TOLERANCE") "±20 %")
        (field (name "VOLTAGE") "50.0 V")
      )
      (libsource (lib "eagle-import") (part "C-EU-C0603-100N"))
    )
    (comp (ref "C45")
      (value "22u 10V")
      (footprint "eagle-import:C0805")
      (fields
        (field (name "MANUFACTURER") "free choice")
        (field (name "TOLERANCE") "±20 %")
        (field (name "VOLTAGE") "10.0 V")
      )
      (libsource (lib "eagle-import") (part "C-EU-C0805-22U"))
    )
    (comp (ref "C46")
      (value "22u 10V")
      (footprint "eagle-import:C0805")
      (fields
        (field (name "MANUFACTURER") "free choice")
        (field (name "TOLERANCE") "±20 %")
        (field (name "VOLTAGE") "10.0 V")
      )
      (libsource (lib "eagle-import") (part "C-EU-C0805-22U"))
    )
    (comp (ref "C47")
      (value "22u 10V")
      (footprint "eagle-import:C0805")
      (fields
        (field (name "MANUFACTURER") "free choice")
        (field (name "TOLERANCE") "±20 %")
        (field (name "VOLTAGE") "10.0 V")
      )
      (libsource (lib "eagle-import") (part "C-EU-C0805-22U"))
    )
    (comp (ref "C48")
      (value "100n 50V")
      (footprint "eagle-import:C0603")
      (fields
        (field (name "MANUFACTURER") "free choice")
        (field (name "TOLERANCE") "±20 %")
        (field (name "VOLTAGE") "50.0 V")
      )
      (libsource (lib "eagle-import") (part "C-EU-C0603-100N"))
    )
    (comp (ref "C49")
      (value "100n 50V")
      (footprint "eagle-import:C0603")
      (fields
        (field (name "MANUFACTURER") "free choice")
        (field (name "TOLERANCE") "±20 %")
        (field (name "VOLTAGE") "50.0 V")
      )
      (libsource (lib "eagle-import") (part "C-EU-C0603-100N"))
    )
    (comp (ref "C50")
      (value "100n 50V")
      (footprint "eagle-import:C0603")
      (fields
        (field (name "MANUFACTURER") "free choice")
        (field (name "TOLERANCE") "±20 %")
        (field (name "VOLTAGE") "50.0 V")
      )
      (libsource (lib "eagle-import") (part "C-EU-C0603-100N"))
    )
    (comp (ref "C51")
      (value "100n 50V")
      (footprint "eagle-import:C0603")
      (fields
        (field (name "MANUFACTURER") "free choice")
        (field (name "TOLERANCE") "±20 %")
        (field (name "VOLTAGE") "50.0 V")
      )
      (libsource (lib "eagle-import") (part "C-EU-C0603-100N"))
    )
    (comp (ref "C52")
      (value "100n 50V")
      (footprint "eagle-import:C0603")
      (fields
        (field (name "MANUFACTURER") "free choice")
        (field (name "TOLERANCE") "±20 %")
        (field (name "VOLTAGE") "50.0 V")
      )
      (libsource (lib "eagle-import") (part "C-EU-C0603-100N"))
    )
    (comp (ref "C53")
      (value "100n 50V")
      (footprint "eagle-import:C0603")
      (fields
        (field (name "MANUFACTURER") "free choice")
        (field (name "TOLERANCE") "±20 %")
        (field (name "VOLTAGE") "50.0 V")
      )
      (libsource (lib "eagle-import") (part "C-EU-C0603-100N"))
    )
    (comp (ref "C54")
      (value "n.m.")
      (footprint "eagle-import:C1206")
      (fields (field (name "TOLERANCE") "±20 %") (field (name "VOLTAGE") "6V3"))
      (libsource (lib "eagle-import") (part "C-EU-C1206"))
    )
    (comp (ref "C55")
      (value "22u 16V")
      (footprint "eagle-import:C1206")
      (fields
        (field (name "MANUFACTURER") "free choice")
        (field (name "TOLERANCE") "±20 %")
        (field (name "VOLTAGE") "16.0 V")
      )
      (libsource (lib "eagle-import") (part "C-EU-C1206-22U"))
    )
    (comp (ref "C56")
      (value "22u 16V")
      (footprint "eagle-import:C1206")
      (fields
        (field (name "MANUFACTURER") "free choice")
        (field (name "TOLERANCE") "±20 %")
        (field (name "VOLTAGE") "16.0 V")
      )
      (libsource (lib "eagle-import") (part "C-EU-C1206-22U"))
    )
    (comp (ref "C57")
      (value "100n 50V")
      (footprint "eagle-import:C0603")
      (fields
        (field (name "MANUFACTURER") "free choice")
        (field (name "TOLERANCE") "±20 %")
        (field (name "VOLTAGE") "50.0 V")
      )
      (libsource (lib "eagle-import") (part "C-EU-C0603-100N"))
    )
    (comp (ref "C58")
      (value "4u7 16V")
      (footprint "eagle-import:C0805")
      (fields
        (field (name "MANUFACTURER") "free choice")
        (field (name "TOLERANCE") "±20 %")
        (field (name "VOLTAGE") "16.0 V")
      )
      (libsource (lib "eagle-import") (part "C-EU-C0805-4U7"))
    )
    (comp (ref "C59")
      (value "100n 50V")
      (footprint "eagle-import:C0603")
      (fields
        (field (name "MANUFACTURER") "free choice")
        (field (name "TOLERANCE") "±20 %")
        (field (name "VOLTAGE") "50.0 V")
      )
      (libsource (lib "eagle-import") (part "C-EU-C0603-100N"))
    )
    (comp (ref "C60")
      (value "22u 10V")
      (footprint "eagle-import:C0805")
      (fields
        (field (name "MANUFACTURER") "free choice")
        (field (name "TOLERANCE") "±20 %")
        (field (name "VOLTAGE") "10.0 V")
      )
      (libsource (lib "eagle-import") (part "C-EU-C0805-22U"))
    )
    (comp (ref "C61")
      (value "1u 25V")
      (footprint "eagle-import:C0603")
      (fields
        (field (name "MANUFACTURER") "free choice")
        (field (name "TOLERANCE") "±20 %")
        (field (name "VOLTAGE") "25.0 V")
      )
      (libsource (lib "eagle-import") (part "C-EU-C0603-1U"))
    )
    (comp (ref "C78")
      (value "22u 10V")
      (footprint "eagle-import:C0805")
      (fields
        (field (name "MANUFACTURER") "free choice")
        (field (name "TOLERANCE") "±20 %")
        (field (name "VOLTAGE") "10.0 V")
      )
      (libsource (lib "eagle-import") (part "C-EU-C0805-22U"))
    )
    (comp (ref "C100")
      (value "1u 25V")
      (footprint "eagle-import:C0603")
      (fields
        (field (name "MANUFACTURER") "free choice")
        (field (name "TOLERANCE") "±20 %")
        (field (name "VOLTAGE") "25.0 V")
      )
      (libsource (lib "eagle-import") (part "C-EU-C0603-1U"))
    )
    (comp (ref "C101")
      (value "C-EU-C0603")
      (footprint "eagle-import:C0603")
      (fields (field (name "TOLERANCE") "±20 %") (field (name "VOLTAGE") "25.0 V"))
      (libsource (lib "eagle-import") (part "C-EU-C0603"))
    )
    (comp (ref "C102")
      (value "1u 25V")
      (footprint "eagle-import:C0603")
      (fields
        (field (name "MANUFACTURER") "free choice")
        (field (name "TOLERANCE") "±20 %")
        (field (name "VOLTAGE") "25.0 V")
      )
      (libsource (lib "eagle-import") (part "C-EU-C0603-1U"))
    )
    (comp (ref "C103")
      (value "C-EU-C0603")
      (footprint "eagle-import:C0603")
      (fields (field (name "TOLERANCE") "±20 %") (field (name "VOLTAGE") "25.0 V"))
      (libsource (lib "eagle-import") (part "C-EU-C0603"))
    )
    (comp (ref "C104")
      (value "1u 25V")
      (footprint "eagle-import:C0603")
      (fields
        (field (name "MANUFACTURER") "free choice")
        (field (name "TOLERANCE") "±20 %")
        (field (name "VOLTAGE") "25.0 V")
      )
      (libsource (lib "eagle-import") (part "C-EU-C0603-1U"))
    )
    (comp (ref "C105")
      (value "C-EU-C0603")
      (footprint "eagle-import:C0603")
      (fields (field (name "TOLERANCE") "±20 %") (field (name "VOLTAGE") "25.0 V"))
      (libsource (lib "eagle-import") (part "C-EU-C0603"))
    )
    (comp (ref "C106")
      (value "1u 25V")
      (footprint "eagle-import:C0603")
      (fields
        (field (name "MANUFACTURER") "free choice")
        (field (name "TOLERANCE") "±20 %")
        (field (name "VOLTAGE") "25.0 V")
      )
      (libsource (lib "eagle-import") (part "C-EU-C0603-1U"))
    )
    (comp (ref "C107")
      (value "C-EU-C0603")
      (footprint "eagle-import:C0603")
      (fields (field (name "TOLERANCE") "±20 %") (field (name "VOLTAGE") "25.0 V"))
      (libsource (lib "eagle-import") (part "C-EU-C0603"))
    )
    (comp (ref "C108")
      (value "1u 25V")
      (footprint "eagle-import:C0603")
      (fields
        (field (name "MANUFACTURER") "free choice")
        (field (name "TOLERANCE") "±20 %")
        (field (name "VOLTAGE") "25.0 V")
      )
      (libsource (lib "eagle-import") (part "C-EU-C0603-1U"))
    )
    (comp (ref "C109")
      (value "C-EU-C0603")
      (footprint "eagle-import:C0603")
      (fields (field (name "TOLERANCE") "±20 %") (field (name "VOLTAGE") "25.0 V"))
      (libsource (lib "eagle-import") (part "C-EU-C0603"))
    )
    (comp (ref "C110")
      (value "1u 25V")
      (footprint "eagle-import:C0603")
      (fields
        (field (name "MANUFACTURER") "free choice")
        (field (name "TOLERANCE") "±20 %")
        (field (name "VOLTAGE") "25.0 V")
      )
      (libsource (lib "eagle-import") (part "C-EU-C0603-1U"))
    )
    (comp (ref "C111")
      (value "C-EU-C0603")
      (footprint "eagle-import:C0603")
      (fields (field (name "TOLERANCE") "±20 %") (field (name "VOLTAGE") "25.0 V"))
      (libsource (lib "eagle-import") (part "C-EU-C0603"))
    )
    (comp (ref "C112")
      (value "1u 25V")
      (footprint "eagle-import:C0603")
      (fields
        (field (name "MANUFACTURER") "free choice")
        (field (name "TOLERANCE") "±20 %")
        (field (name "VOLTAGE") "25.0 V")
      )
      (libsource (lib "eagle-import") (part "C-EU-C0603-1U"))
    )
    (comp (ref "C113")
      (value "C-EU-C0603")
      (footprint "eagle-import:C0603")
      (fields (field (name "TOLERANCE") "±20 %") (field (name "VOLTAGE") "25.0 V"))
      (libsource (lib "eagle-import") (part "C-EU-C0603"))
    )
    (comp (ref "C114")
      (value "1u 25V")
      (footprint "eagle-import:C0603")
      (fields
        (field (name "MANUFACTURER") "free choice")
        (field (name "TOLERANCE") "±20 %")
        (field (name "VOLTAGE") "25.0 V")
      )
      (libsource (lib "eagle-import") (part "C-EU-C0603-1U"))
    )
    (comp (ref "C115")
      (value "C-EU-C0603")
      (footprint "eagle-import:C0603")
      (fields (field (name "TOLERANCE") "±20 %") (field (name "VOLTAGE") "25.0 V"))
      (libsource (lib "eagle-import") (part "C-EU-C0603"))
    )
    (comp (ref "C116")
      (value "1u 25V")
      (footprint "eagle-import:C0603")
      (fields
        (field (name "MANUFACTURER") "free choice")
        (field (name "TOLERANCE") "±20 %")
        (field (name "VOLTAGE") "25.0 V")
      )
      (libsource (lib "eagle-import") (part "C-EU-C0603-1U"))
    )
    (comp (ref "C117")
      (value "C-EU-C0603")
      (footprint "eagle-import:C0603")
      (fields (field (name "TOLERANCE") "±20 %") (field (name "VOLTAGE") "25.0 V"))
      (libsource (lib "eagle-import") (part "C-EU-C0603"))
    )
    (comp (ref "C118")
      (value "1u 25V")
      (footprint "eagle-import:C0603")
      (fields
        (field (name "MANUFACTURER") "free choice")
        (field (name "TOLERANCE") "±20 %")
        (field (name "VOLTAGE") "25.0 V")
      )
      (libsource (lib "eagle-import") (part "C-EU-C0603-1U"))
    )
    (comp (ref "C119")
      (value "C-EU-C0603")
      (footprint "eagle-import:C0603")
      (fields (field (name "TOLERANCE") "±20 %") (field (name "VOLTAGE") "25.0 V"))
      (libsource (lib "eagle-import") (part "C-EU-C0603"))
    )
    (comp (ref "C120")
      (value "1u 25V")
      (footprint "eagle-import:C0603")
      (fields
        (field (name "MANUFACTURER") "free choice")
        (field (name "TOLERANCE") "±20 %")
        (field (name "VOLTAGE") "25.0 V")
      )
      (libsource (lib "eagle-import") (part "C-EU-C0603-1U"))
    )
    (comp (ref "C121")
      (value "C-EU-C0603")
      (footprint "eagle-import:C0603")
      (fields (field (name "TOLERANCE") "±20 %") (field (name "VOLTAGE") "25.0 V"))
      (libsource (lib "eagle-import") (part "C-EU-C0603"))
    )
    (comp (ref "C122")
      (value "1u 25V")
      (footprint "eagle-import:C0603")
      (fields
        (field (name "MANUFACTURER") "free choice")
        (field (name "TOLERANCE") "±20 %")
        (field (name "VOLTAGE") "25.0 V")
      )
      (libsource (lib "eagle-import") (part "C-EU-C0603-1U"))
    )
    (comp (ref "C123")
      (value "C-EU-C0603")
      (footprint "eagle-import:C0603")
      (fields (field (name "TOLERANCE") "±20 %") (field (name "VOLTAGE") "25.0 V"))
      (libsource (lib "eagle-import") (part "C-EU-C0603"))
    )
    (comp (ref "C124")
      (value "1u 25V")
      (footprint "eagle-import:C0603")
      (fields
        (field (name "MANUFACTURER") "free choice")
        (field (name "TOLERANCE") "±20 %")
        (field (name "VOLTAGE") "25.0 V")
      )
      (libsource (lib "eagle-import") (part "C-EU-C0603-1U"))
    )
    (comp (ref "C125")
      (value "C-EU-C0603")
      (footprint "eagle-import:C0603")
      (fields (field (name "TOLERANCE") "±20 %") (field (name "VOLTAGE") "25.0 V"))
      (libsource (lib "eagle-import") (part "C-EU-C0603"))
    )
    (comp (ref "C126")
      (value "1u 25V")
      (footprint "eagle-import:C0603")
      (fields
        (field (name "MANUFACTURER") "free choice")
        (field (name "TOLERANCE") "±20 %")
        (field (name "VOLTAGE") "25.0 V")
      )
      (libsource (lib "eagle-import") (part "C-EU-C0603-1U"))
    )
    (comp (ref "C127")
      (value "C-EU-C0603")
      (footprint "eagle-import:C0603")
      (fields (field (name "TOLERANCE") "±20 %") (field (name "VOLTAGE") "25.0 V"))
      (libsource (lib "eagle-import") (part "C-EU-C0603"))
    )
    (comp (ref "C128")
      (value "1u 25V")
      (footprint "eagle-import:C0603")
      (fields
        (field (name "MANUFACTURER") "free choice")
        (field (name "TOLERANCE") "±20 %")
        (field (name "VOLTAGE") "25.0 V")
      )
      (libsource (lib "eagle-import") (part "C-EU-C0603-1U"))
    )
    (comp (ref "C129")
      (value "C-EU-C0603")
      (footprint "eagle-import:C0603")
      (fields (field (name "TOLERANCE") "±20 %") (field (name "VOLTAGE") "25.0 V"))
      (libsource (lib "eagle-import") (part "C-EU-C0603"))
    )
    (comp (ref "C130")
      (value "1u 25V")
      (footprint "eagle-import:C0603")
      (fields
        (field (name "MANUFACTURER") "free choice")
        (field (name "TOLERANCE") "±20 %")
        (field (name "VOLTAGE") "25.0 V")
      )
      (libsource (lib "eagle-import") (part "C-EU-C0603-1U"))
    )
    (comp (ref "C131")
      (value "C-EU-C0603")
      (footprint "eagle-import:C0603")
      (fields (field (name "TOLERANCE") "±20 %") (field (name "VOLTAGE") "25.0 V"))
      (libsource (lib "eagle-import") (part "C-EU-C0603"))
    )
    (comp (ref "C132")
      (value "1u 25V")
      (footprint "eagle-import:C0603")
      (fields
        (field (name "MANUFACTURER") "free choice")
        (field (name "TOLERANCE") "±20 %")
        (field (name "VOLTAGE") "25.0 V")
      )
      (libsource (lib "eagle-import") (part "C-EU-C0603-1U"))
    )
    (comp (ref "C133")
      (value "C-EU-C0603")
      (footprint "eagle-import:C0603")
      (fields (field (name "TOLERANCE") "±20 %") (field (name "VOLTAGE") "25.0 V"))
      (libsource (lib "eagle-import") (part "C-EU-C0603"))
    )
    (comp (ref "C134")
      (value "1u 25V")
      (footprint "eagle-import:C0603")
      (fields
        (field (name "MANUFACTURER") "free choice")
        (field (name "TOLERANCE") "±20 %")
        (field (name "VOLTAGE") "25.0 V")
      )
      (libsource (lib "eagle-import") (part "C-EU-C0603-1U"))
    )
    (comp (ref "C135")
      (value "C-EU-C0603")
      (footprint "eagle-import:C0603")
      (fields (field (name "TOLERANCE") "±20 %") (field (name "VOLTAGE") "25.0 V"))
      (libsource (lib "eagle-import") (part "C-EU-C0603"))
    )
    (comp (ref "C136")
      (value "1u 25V")
      (footprint "eagle-import:C0603")
      (fields
        (field (name "MANUFACTURER") "free choice")
        (field (name "TOLERANCE") "±20 %")
        (field (name "VOLTAGE") "25.0 V")
      )
      (libsource (lib "eagle-import") (part "C-EU-C0603-1U"))
    )
    (comp (ref "C137")
      (value "C-EU-C0603")
      (footprint "eagle-import:C0603")
      (fields (field (name "TOLERANCE") "±20 %") (field (name "VOLTAGE") "25.0 V"))
      (libsource (lib "eagle-import") (part "C-EU-C0603"))
    )
    (comp (ref "C138")
      (value "1u 25V")
      (footprint "eagle-import:C0603")
      (fields
        (field (name "MANUFACTURER") "free choice")
        (field (name "TOLERANCE") "±20 %")
        (field (name "VOLTAGE") "25.0 V")
      )
      (libsource (lib "eagle-import") (part "C-EU-C0603-1U"))
    )
    (comp (ref "C139")
      (value "C-EU-C0603")
      (footprint "eagle-import:C0603")
      (fields (field (name "TOLERANCE") "±20 %") (field (name "VOLTAGE") "25.0 V"))
      (libsource (lib "eagle-import") (part "C-EU-C0603"))
    )
    (comp (ref "C140")
      (value "1u 25V")
      (footprint "eagle-import:C0603")
      (fields
        (field (name "MANUFACTURER") "free choice")
        (field (name "TOLERANCE") "±20 %")
        (field (name "VOLTAGE") "25.0 V")
      )
      (libsource (lib "eagle-import") (part "C-EU-C0603-1U"))
    )
    (comp (ref "C141")
      (value "C-EU-C0603")
      (footprint "eagle-import:C0603")
      (fields (field (name "TOLERANCE") "±20 %") (field (name "VOLTAGE") "25.0 V"))
      (libsource (lib "eagle-import") (part "C-EU-C0603"))
    )
    (comp (ref "C142")
      (value "1u 25V")
      (footprint "eagle-import:C0603")
      (fields
        (field (name "MANUFACTURER") "free choice")
        (field (name "TOLERANCE") "±20 %")
        (field (name "VOLTAGE") "25.0 V")
      )
      (libsource (lib "eagle-import") (part "C-EU-C0603-1U"))
    )
    (comp (ref "C143")
      (value "C-EU-C0603")
      (footprint "eagle-import:C0603")
      (fields (field (name "TOLERANCE") "±20 %") (field (name "VOLTAGE") "25.0 V"))
      (libsource (lib "eagle-import") (part "C-EU-C0603"))
    )
    (comp (ref "C144")
      (value "1u 25V")
      (footprint "eagle-import:C0603")
      (fields
        (field (name "MANUFACTURER") "free choice")
        (field (name "TOLERANCE") "±20 %")
        (field (name "VOLTAGE") "25.0 V")
      )
      (libsource (lib "eagle-import") (part "C-EU-C0603-1U"))
    )
    (comp (ref "C145")
      (value "C-EU-C0603")
      (footprint "eagle-import:C0603")
      (fields (field (name "TOLERANCE") "±20 %") (field (name "VOLTAGE") "25.0 V"))
      (libsource (lib "eagle-import") (part "C-EU-C0603"))
    )
    (comp (ref "C146")
      (value "1u 25V")
      (footprint "eagle-import:C0603")
      (fields
        (field (name "MANUFACTURER") "free choice")
        (field (name "TOLERANCE") "±20 %")
        (field (name "VOLTAGE") "25.0 V")
      )
      (libsource (lib "eagle-import") (part "C-EU-C0603-1U"))
    )
    (comp (ref "C147")
      (value "C-EU-C0603")
      (footprint "eagle-import:C0603")
      (fields (field (name "TOLERANCE") "±20 %") (field (name "VOLTAGE") "25.0 V"))
      (libsource (lib "eagle-import") (part "C-EU-C0603"))
    )
    (comp (ref "C148")
      (value "1u 25V")
      (footprint "eagle-import:C0603")
      (fields
        (field (name "MANUFACTURER") "free choice")
        (field (name "TOLERANCE") "±20 %")
        (field (name "VOLTAGE") "25.0 V")
      )
      (libsource (lib "eagle-import") (part "C-EU-C0603-1U"))
    )
    (comp (ref "C149")
      (value "C-EU-C0603")
      (footprint "eagle-import:C0603")
      (fields (field (name "TOLERANCE") "±20 %") (field (name "VOLTAGE") "25.0 V"))
      (libsource (lib "eagle-import") (part "C-EU-C0603"))
    )
    (comp (ref "C150")
      (value "1u 25V")
      (footprint "eagle-import:C0603")
      (fields
        (field (name "MANUFACTURER") "free choice")
        (field (name "TOLERANCE") "±20 %")
        (field (name "VOLTAGE") "25.0 V")
      )
      (libsource (lib "eagle-import") (part "C-EU-C0603-1U"))
    )
    (comp (ref "C151")
      (value "C-EU-C0603")
      (footprint "eagle-import:C0603")
      (fields (field (name "TOLERANCE") "±20 %") (field (name "VOLTAGE") "25.0 V"))
      (libsource (lib "eagle-import") (part "C-EU-C0603"))
    )
    (comp (ref "C152")
      (value "1u 25V")
      (footprint "eagle-import:C0603")
      (fields
        (field (name "MANUFACTURER") "free choice")
        (field (name "TOLERANCE") "±20 %")
        (field (name "VOLTAGE") "25.0 V")
      )
      (libsource (lib "eagle-import") (part "C-EU-C0603-1U"))
    )
    (comp (ref "C153")
      (value "C-EU-C0603")
      (footprint "eagle-import:C0603")
      (fields (field (name "TOLERANCE") "±20 %") (field (name "VOLTAGE") "25.0 V"))
      (libsource (lib "eagle-import") (part "C-EU-C0603"))
    )
    (comp (ref "C154")
      (value "1u 25V")
      (footprint "eagle-import:C0603")
      (fields
        (field (name "MANUFACTURER") "free choice")
        (field (name "TOLERANCE") "±20 %")
        (field (name "VOLTAGE") "25.0 V")
      )
      (libsource (lib "eagle-import") (part "C-EU-C0603-1U"))
    )
    (comp (ref "C155")
      (value "C-EU-C0603")
      (footprint "eagle-import:C0603")
      (fields (field (name "TOLERANCE") "±20 %") (field (name "VOLTAGE") "25.0 V"))
      (libsource (lib "eagle-import") (part "C-EU-C0603"))
    )
    (comp (ref "C156")
      (value "1u 25V")
      (footprint "eagle-import:C0603")
      (fields
        (field (name "MANUFACTURER") "free choice")
        (field (name "TOLERANCE") "±20 %")
        (field (name "VOLTAGE") "25.0 V")
      )
      (libsource (lib "eagle-import") (part "C-EU-C0603-1U"))
    )
    (comp (ref "C157")
      (value "C-EU-C0603")
      (footprint "eagle-import:C0603")
      (fields (field (name "TOLERANCE") "±20 %") (field (name "VOLTAGE") "25.0 V"))
      (libsource (lib "eagle-import") (part "C-EU-C0603"))
    )
    (comp (ref "C158")
      (value "1u 25V")
      (footprint "eagle-import:C0603")
      (fields
        (field (name "MANUFACTURER") "free choice")
        (field (name "TOLERANCE") "±20 %")
        (field (name "VOLTAGE") "25.0 V")
      )
      (libsource (lib "eagle-import") (part "C-EU-C0603-1U"))
    )
    (comp (ref "C159")
      (value "C-EU-C0603")
      (footprint "eagle-import:C0603")
      (fields (field (name "TOLERANCE") "±20 %") (field (name "VOLTAGE") "25.0 V"))
      (libsource (lib "eagle-import") (part "C-EU-C0603"))
    )
    (comp (ref "C162")
      (value "1u 25V")
      (footprint "eagle-import:C0603")
      (fields
        (field (name "MANUFACTURER") "free choice")
        (field (name "TOLERANCE") "±20 %")
        (field (name "VOLTAGE") "25.0 V")
      )
      (libsource (lib "eagle-import") (part "C-EU-C0603-1U"))
    )
    (comp (ref "C164")
      (value "1u 25V")
      (footprint "eagle-import:C0603")
      (fields
        (field (name "MANUFACTURER") "free choice")
        (field (name "TOLERANCE") "±20 %")
        (field (name "VOLTAGE") "25.0 V")
      )
      (libsource (lib "eagle-import") (part "C-EU-C0603-1U"))
    )
    (comp (ref "C165")
      (value "C-EU-C0603")
      (footprint "eagle-import:C0603")
      (fields (field (name "TOLERANCE") "±20 %") (field (name "VOLTAGE") "25.0 V"))
      (libsource (lib "eagle-import") (part "C-EU-C0603"))
    )
    (comp (ref "C166")
      (value "1u 25V")
      (footprint "eagle-import:C0603")
      (fields
        (field (name "MANUFACTURER") "free choice")
        (field (name "TOLERANCE") "±20 %")
        (field (name "VOLTAGE") "25.0 V")
      )
      (libsource (lib "eagle-import") (part "C-EU-C0603-1U"))
    )
    (comp (ref "C167")
      (value "C-EU-C0603")
      (footprint "eagle-import:C0603")
      (fields (field (name "TOLERANCE") "±20 %") (field (name "VOLTAGE") "25.0 V"))
      (libsource (lib "eagle-import") (part "C-EU-C0603"))
    )
    (comp (ref "C168")
      (value "1u 25V")
      (footprint "eagle-import:C0603")
      (fields
        (field (name "MANUFACTURER") "free choice")
        (field (name "TOLERANCE") "±20 %")
        (field (name "VOLTAGE") "25.0 V")
      )
      (libsource (lib "eagle-import") (part "C-EU-C0603-1U"))
    )
    (comp (ref "C169")
      (value "C-EU-C0603")
      (footprint "eagle-import:C0603")
      (fields (field (name "TOLERANCE") "±20 %") (field (name "VOLTAGE") "25.0 V"))
      (libsource (lib "eagle-import") (part "C-EU-C0603"))
    )
    (comp (ref "C170")
      (value "1u 25V")
      (footprint "eagle-import:C0603")
      (fields
        (field (name "MANUFACTURER") "free choice")
        (field (name "TOLERANCE") "±20 %")
        (field (name "VOLTAGE") "25.0 V")
      )
      (libsource (lib "eagle-import") (part "C-EU-C0603-1U"))
    )
    (comp (ref "C171")
      (value "C-EU-C0603")
      (footprint "eagle-import:C0603")
      (fields (field (name "TOLERANCE") "±20 %") (field (name "VOLTAGE") "25.0 V"))
      (libsource (lib "eagle-import") (part "C-EU-C0603"))
    )
    (comp (ref "C172")
      (value "1u 25V")
      (footprint "eagle-import:C0603")
      (fields
        (field (name "MANUFACTURER") "free choice")
        (field (name "TOLERANCE") "±20 %")
        (field (name "VOLTAGE") "25.0 V")
      )
      (libsource (lib "eagle-import") (part "C-EU-C0603-1U"))
    )
    (comp (ref "C173")
      (value "C-EU-C0603")
      (footprint "eagle-import:C0603")
      (fields (field (name "TOLERANCE") "±20 %") (field (name "VOLTAGE") "25.0 V"))
      (libsource (lib "eagle-import") (part "C-EU-C0603"))
    )
    (comp (ref "C174")
      (value "1u 25V")
      (footprint "eagle-import:C0603")
      (fields
        (field (name "MANUFACTURER") "free choice")
        (field (name "TOLERANCE") "±20 %")
        (field (name "VOLTAGE") "25.0 V")
      )
      (libsource (lib "eagle-import") (part "C-EU-C0603-1U"))
    )
    (comp (ref "C175")
      (value "C-EU-C0603")
      (footprint "eagle-import:C0603")
      (fields (field (name "TOLERANCE") "±20 %") (field (name "VOLTAGE") "25.0 V"))
      (libsource (lib "eagle-import") (part "C-EU-C0603"))
    )
    (comp (ref "C176")
      (value "1u 25V")
      (footprint "eagle-import:C0603")
      (fields
        (field (name "MANUFACTURER") "free choice")
        (field (name "TOLERANCE") "±20 %")
        (field (name "VOLTAGE") "25.0 V")
      )
      (libsource (lib "eagle-import") (part "C-EU-C0603-1U"))
    )
    (comp (ref "C177")
      (value "C-EU-C0603")
      (footprint "eagle-import:C0603")
      (fields (field (name "TOLERANCE") "±20 %") (field (name "VOLTAGE") "25.0 V"))
      (libsource (lib "eagle-import") (part "C-EU-C0603"))
    )
    (comp (ref "C178")
      (value "1u 25V")
      (footprint "eagle-import:C0603")
      (fields
        (field (name "MANUFACTURER") "free choice")
        (field (name "TOLERANCE") "±20 %")
        (field (name "VOLTAGE") "25.0 V")
      )
      (libsource (lib "eagle-import") (part "C-EU-C0603-1U"))
    )
    (comp (ref "C179")
      (value "C-EU-C0603")
      (footprint "eagle-import:C0603")
      (fields (field (name "TOLERANCE") "±20 %") (field (name "VOLTAGE") "25.0 V"))
      (libsource (lib "eagle-import") (part "C-EU-C0603"))
    )
    (comp (ref "C180")
      (value "1u 25V")
      (footprint "eagle-import:C0603")
      (fields
        (field (name "MANUFACTURER") "free choice")
        (field (name "TOLERANCE") "±20 %")
        (field (name "VOLTAGE") "25.0 V")
      )
      (libsource (lib "eagle-import") (part "C-EU-C0603-1U"))
    )
    (comp (ref "C181")
      (value "C-EU-C0603")
      (footprint "eagle-import:C0603")
      (fields (field (name "TOLERANCE") "±20 %") (field (name "VOLTAGE") "25.0 V"))
      (libsource (lib "eagle-import") (part "C-EU-C0603"))
    )
    (comp (ref "C182")
      (value "1u 25V")
      (footprint "eagle-import:C0603")
      (fields
        (field (name "MANUFACTURER") "free choice")
        (field (name "TOLERANCE") "±20 %")
        (field (name "VOLTAGE") "25.0 V")
      )
      (libsource (lib "eagle-import") (part "C-EU-C0603-1U"))
    )
    (comp (ref "C183")
      (value "C-EU-C0603")
      (footprint "eagle-import:C0603")
      (fields (field (name "TOLERANCE") "±20 %") (field (name "VOLTAGE") "25.0 V"))
      (libsource (lib "eagle-import") (part "C-EU-C0603"))
    )
    (comp (ref "C184")
      (value "1u 25V")
      (footprint "eagle-import:C0603")
      (fields
        (field (name "MANUFACTURER") "free choice")
        (field (name "TOLERANCE") "±20 %")
        (field (name "VOLTAGE") "25.0 V")
      )
      (libsource (lib "eagle-import") (part "C-EU-C0603-1U"))
    )
    (comp (ref "C185")
      (value "C-EU-C0603")
      (footprint "eagle-import:C0603")
      (fields (field (name "TOLERANCE") "±20 %") (field (name "VOLTAGE") "25.0 V"))
      (libsource (lib "eagle-import") (part "C-EU-C0603"))
    )
    (comp (ref "C186")
      (value "1u 25V")
      (footprint "eagle-import:C0603")
      (fields
        (field (name "MANUFACTURER") "free choice")
        (field (name "TOLERANCE") "±20 %")
        (field (name "VOLTAGE") "25.0 V")
      )
      (libsource (lib "eagle-import") (part "C-EU-C0603-1U"))
    )
    (comp (ref "C187")
      (value "C-EU-C0603")
      (footprint "eagle-import:C0603")
      (fields (field (name "TOLERANCE") "±20 %") (field (name "VOLTAGE") "25.0 V"))
      (libsource (lib "eagle-import") (part "C-EU-C0603"))
    )
    (comp (ref "C188")
      (value "1u 25V")
      (footprint "eagle-import:C0603")
      (fields
        (field (name "MANUFACTURER") "free choice")
        (field (name "TOLERANCE") "±20 %")
        (field (name "VOLTAGE") "25.0 V")
      )
      (libsource (lib "eagle-import") (part "C-EU-C0603-1U"))
    )
    (comp (ref "C189")
      (value "C-EU-C0603")
      (footprint "eagle-import:C0603")
      (fields (field (name "TOLERANCE") "±20 %") (field (name "VOLTAGE") "25.0 V"))
      (libsource (lib "eagle-import") (part "C-EU-C0603"))
    )
    (comp (ref "C190")
      (value "1u 25V")
      (footprint "eagle-import:C0603")
      (fields
        (field (name "MANUFACTURER") "free choice")
        (field (name "TOLERANCE") "±20 %")
        (field (name "VOLTAGE") "25.0 V")
      )
      (libsource (lib "eagle-import") (part "C-EU-C0603-1U"))
    )
    (comp (ref "C191")
      (value "C-EU-C0603")
      (footprint "eagle-import:C0603")
      (fields (field (name "TOLERANCE") "±20 %") (field (name "VOLTAGE") "25.0 V"))
      (libsource (lib "eagle-import") (part "C-EU-C0603"))
    )
    (comp (ref "C192")
      (value "1u 25V")
      (footprint "eagle-import:C0603")
      (fields
        (field (name "MANUFACTURER") "free choice")
        (field (name "TOLERANCE") "±20 %")
        (field (name "VOLTAGE") "25.0 V")
      )
      (libsource (lib "eagle-import") (part "C-EU-C0603-1U"))
    )
    (comp (ref "C193")
      (value "C-EU-C0603")
      (footprint "eagle-import:C0603")
      (fields (field (name "TOLERANCE") "±20 %") (field (name "VOLTAGE") "25.0 V"))
      (libsource (lib "eagle-import") (part "C-EU-C0603"))
    )
    (comp (ref "C194")
      (value "1u 25V")
      (footprint "eagle-import:C0603")
      (fields
        (field (name "MANUFACTURER") "free choice")
        (field (name "TOLERANCE") "±20 %")
        (field (name "VOLTAGE") "25.0 V")
      )
      (libsource (lib "eagle-import") (part "C-EU-C0603-1U"))
    )
    (comp (ref "C195")
      (value "C-EU-C0603")
      (footprint "eagle-import:C0603")
      (fields (field (name "TOLERANCE") "±20 %") (field (name "VOLTAGE") "25.0 V"))
      (libsource (lib "eagle-import") (part "C-EU-C0603"))
    )
    (comp (ref "C196")
      (value "1u 25V")
      (footprint "eagle-import:C0603")
      (fields
        (field (name "MANUFACTURER") "free choice")
        (field (name "TOLERANCE") "±20 %")
        (field (name "VOLTAGE") "25.0 V")
      )
      (libsource (lib "eagle-import") (part "C-EU-C0603-1U"))
    )
    (comp (ref "C197")
      (value "C-EU-C0603")
      (footprint "eagle-import:C0603")
      (fields (field (name "TOLERANCE") "±20 %") (field (name "VOLTAGE") "25.0 V"))
      (libsource (lib "eagle-import") (part "C-EU-C0603"))
    )
    (comp (ref "C198")
      (value "1u 25V")
      (footprint "eagle-import:C0603")
      (fields
        (field (name "MANUFACTURER") "free choice")
        (field (name "TOLERANCE") "±20 %")
        (field (name "VOLTAGE") "25.0 V")
      )
      (libsource (lib "eagle-import") (part "C-EU-C0603-1U"))
    )
    (comp (ref "C199")
      (value "C-EU-C0603")
      (footprint "eagle-import:C0603")
      (fields (field (name "TOLERANCE") "±20 %") (field (name "VOLTAGE") "25.0 V"))
      (libsource (lib "eagle-import") (part "C-EU-C0603"))
    )
    (comp (ref "C200")
      (value "1u 25V")
      (footprint "eagle-import:C0603")
      (fields
        (field (name "MANUFACTURER") "free choice")
        (field (name "TOLERANCE") "±20 %")
        (field (name "VOLTAGE") "25.0 V")
      )
      (libsource (lib "eagle-import") (part "C-EU-C0603-1U"))
    )
    (comp (ref "C201")
      (value "C-EU-C0603")
      (footprint "eagle-import:C0603")
      (fields (field (name "TOLERANCE") "±20 %") (field (name "VOLTAGE") "25.0 V"))
      (libsource (lib "eagle-import") (part "C-EU-C0603"))
    )
    (comp (ref "C202")
      (value "1u 25V")
      (footprint "eagle-import:C0603")
      (fields
        (field (name "MANUFACTURER") "free choice")
        (field (name "TOLERANCE") "±20 %")
        (field (name "VOLTAGE") "25.0 V")
      )
      (libsource (lib "eagle-import") (part "C-EU-C0603-1U"))
    )
    (comp (ref "C203")
      (value "C-EU-C0603")
      (footprint "eagle-import:C0603")
      (fields (field (name "TOLERANCE") "±20 %") (field (name "VOLTAGE") "25.0 V"))
      (libsource (lib "eagle-import") (part "C-EU-C0603"))
    )
    (comp (ref "C204")
      (value "1u 25V")
      (footprint "eagle-import:C0603")
      (fields
        (field (name "MANUFACTURER") "free choice")
        (field (name "TOLERANCE") "±20 %")
        (field (name "VOLTAGE") "25.0 V")
      )
      (libsource (lib "eagle-import") (part "C-EU-C0603-1U"))
    )
    (comp (ref "C205")
      (value "C-EU-C0603")
      (footprint "eagle-import:C0603")
      (fields (field (name "TOLERANCE") "±20 %") (field (name "VOLTAGE") "25.0 V"))
      (libsource (lib "eagle-import") (part "C-EU-C0603"))
    )
    (comp (ref "C206")
      (value "1u 25V")
      (footprint "eagle-import:C0603")
      (fields
        (field (name "MANUFACTURER") "free choice")
        (field (name "TOLERANCE") "±20 %")
        (field (name "VOLTAGE") "25.0 V")
      )
      (libsource (lib "eagle-import") (part "C-EU-C0603-1U"))
    )
    (comp (ref "C207")
      (value "C-EU-C0603")
      (footprint "eagle-import:C0603")
      (fields (field (name "TOLERANCE") "±20 %") (field (name "VOLTAGE") "25.0 V"))
      (libsource (lib "eagle-import") (part "C-EU-C0603"))
    )
    (comp (ref "C208")
      (value "1u 25V")
      (footprint "eagle-import:C0603")
      (fields
        (field (name "MANUFACTURER") "free choice")
        (field (name "TOLERANCE") "±20 %")
        (field (name "VOLTAGE") "25.0 V")
      )
      (libsource (lib "eagle-import") (part "C-EU-C0603-1U"))
    )
    (comp (ref "C209")
      (value "C-EU-C0603")
      (footprint "eagle-import:C0603")
      (fields (field (name "TOLERANCE") "±20 %") (field (name "VOLTAGE") "25.0 V"))
      (libsource (lib "eagle-import") (part "C-EU-C0603"))
    )
    (comp (ref "C210")
      (value "1u 25V")
      (footprint "eagle-import:C0603")
      (fields
        (field (name "MANUFACTURER") "free choice")
        (field (name "TOLERANCE") "±20 %")
        (field (name "VOLTAGE") "25.0 V")
      )
      (libsource (lib "eagle-import") (part "C-EU-C0603-1U"))
    )
    (comp (ref "C211")
      (value "C-EU-C0603")
      (footprint "eagle-import:C0603")
      (fields (field (name "TOLERANCE") "±20 %") (field (name "VOLTAGE") "25.0 V"))
      (libsource (lib "eagle-import") (part "C-EU-C0603"))
    )
    (comp (ref "C212")
      (value "1u 25V")
      (footprint "eagle-import:C0603")
      (fields
        (field (name "MANUFACTURER") "free choice")
        (field (name "TOLERANCE") "±20 %")
        (field (name "VOLTAGE") "25.0 V")
      )
      (libsource (lib "eagle-import") (part "C-EU-C0603-1U"))
    )
    (comp (ref "C213")
      (value "C-EU-C0603")
      (footprint "eagle-import:C0603")
      (fields (field (name "TOLERANCE") "±20 %") (field (name "VOLTAGE") "25.0 V"))
      (libsource (lib "eagle-import") (part "C-EU-C0603"))
    )
    (comp (ref "C214")
      (value "1u 25V")
      (footprint "eagle-import:C0603")
      (fields
        (field (name "MANUFACTURER") "free choice")
        (field (name "TOLERANCE") "±20 %")
        (field (name "VOLTAGE") "25.0 V")
      )
      (libsource (lib "eagle-import") (part "C-EU-C0603-1U"))
    )
    (comp (ref "C215")
      (value "C-EU-C0603")
      (footprint "eagle-import:C0603")
      (fields (field (name "TOLERANCE") "±20 %") (field (name "VOLTAGE") "25.0 V"))
      (libsource (lib "eagle-import") (part "C-EU-C0603"))
    )
    (comp (ref "C216")
      (value "1u 25V")
      (footprint "eagle-import:C0603")
      (fields
        (field (name "MANUFACTURER") "free choice")
        (field (name "TOLERANCE") "±20 %")
        (field (name "VOLTAGE") "25.0 V")
      )
      (libsource (lib "eagle-import") (part "C-EU-C0603-1U"))
    )
    (comp (ref "C217")
      (value "C-EU-C0603")
      (footprint "eagle-import:C0603")
      (fields (field (name "TOLERANCE") "±20 %") (field (name "VOLTAGE") "25.0 V"))
      (libsource (lib "eagle-import") (part "C-EU-C0603"))
    )
    (comp (ref "C218")
      (value "1u 25V")
      (footprint "eagle-import:C0603")
      (fields
        (field (name "MANUFACTURER") "free choice")
        (field (name "TOLERANCE") "±20 %")
        (field (name "VOLTAGE") "25.0 V")
      )
      (libsource (lib "eagle-import") (part "C-EU-C0603-1U"))
    )
    (comp (ref "C219")
      (value "C-EU-C0603")
      (footprint "eagle-import:C0603")
      (fields (field (name "TOLERANCE") "±20 %") (field (name "VOLTAGE") "25.0 V"))
      (libsource (lib "eagle-import") (part "C-EU-C0603"))
    )
    (comp (ref "C220")
      (value "1u 25V")
      (footprint "eagle-import:C0603")
      (fields
        (field (name "MANUFACTURER") "free choice")
        (field (name "TOLERANCE") "±20 %")
        (field (name "VOLTAGE") "25.0 V")
      )
      (libsource (lib "eagle-import") (part "C-EU-C0603-1U"))
    )
    (comp (ref "C221")
      (value "C-EU-C0603")
      (footprint "eagle-import:C0603")
      (fields (field (name "TOLERANCE") "±20 %") (field (name "VOLTAGE") "25.0 V"))
      (libsource (lib "eagle-import") (part "C-EU-C0603"))
    )
    (comp (ref "C222")
      (value "1u 25V")
      (footprint "eagle-import:C0603")
      (fields
        (field (name "MANUFACTURER") "free choice")
        (field (name "TOLERANCE") "±20 %")
        (field (name "VOLTAGE") "25.0 V")
      )
      (libsource (lib "eagle-import") (part "C-EU-C0603-1U"))
    )
    (comp (ref "C223")
      (value "C-EU-C0603")
      (footprint "eagle-import:C0603")
      (fields (field (name "TOLERANCE") "±20 %") (field (name "VOLTAGE") "25.0 V"))
      (libsource (lib "eagle-import") (part "C-EU-C0603"))
    )
    (comp (ref "C224")
      (value "1u 25V")
      (footprint "eagle-import:C0603")
      (fields
        (field (name "MANUFACTURER") "free choice")
        (field (name "TOLERANCE") "±20 %")
        (field (name "VOLTAGE") "25.0 V")
      )
      (libsource (lib "eagle-import") (part "C-EU-C0603-1U"))
    )
    (comp (ref "C225")
      (value "C-EU-C0603")
      (footprint "eagle-import:C0603")
      (fields (field (name "TOLERANCE") "±20 %") (field (name "VOLTAGE") "25.0 V"))
      (libsource (lib "eagle-import") (part "C-EU-C0603"))
    )
    (comp (ref "C226")
      (value "1u 25V")
      (footprint "eagle-import:C0603")
      (fields
        (field (name "MANUFACTURER") "free choice")
        (field (name "TOLERANCE") "±20 %")
        (field (name "VOLTAGE") "25.0 V")
      )
      (libsource (lib "eagle-import") (part "C-EU-C0603-1U"))
    )
    (comp (ref "C227")
      (value "C-EU-C0603")
      (footprint "eagle-import:C0603")
      (fields (field (name "TOLERANCE") "±20 %") (field (name "VOLTAGE") "25.0 V"))
      (libsource (lib "eagle-import") (part "C-EU-C0603"))
    )
    (comp (ref "C228")
      (value "1u 25V")
      (footprint "eagle-import:C0603")
      (fields
        (field (name "MANUFACTURER") "free choice")
        (field (name "TOLERANCE") "±20 %")
        (field (name "VOLTAGE") "25.0 V")
      )
      (libsource (lib "eagle-import") (part "C-EU-C0603-1U"))
    )
    (comp (ref "C229")
      (value "C-EU-C0603")
      (footprint "eagle-import:C0603")
      (fields (field (name "TOLERANCE") "±20 %") (field (name "VOLTAGE") "25.0 V"))
      (libsource (lib "eagle-import") (part "C-EU-C0603"))
    )
    (comp (ref "C230")
      (value "1u 25V")
      (footprint "eagle-import:C0603")
      (fields
        (field (name "MANUFACTURER") "free choice")
        (field (name "TOLERANCE") "±20 %")
        (field (name "VOLTAGE") "25.0 V")
      )
      (libsource (lib "eagle-import") (part "C-EU-C0603-1U"))
    )
    (comp (ref "C231")
      (value "C-EU-C0603")
      (footprint "eagle-import:C0603")
      (fields (field (name "TOLERANCE") "±20 %") (field (name "VOLTAGE") "25.0 V"))
      (libsource (lib "eagle-import") (part "C-EU-C0603"))
    )
    (comp (ref "C232")
      (value "1u 25V")
      (footprint "eagle-import:C0603")
      (fields
        (field (name "MANUFACTURER") "free choice")
        (field (name "TOLERANCE") "±20 %")
        (field (name "VOLTAGE") "25.0 V")
      )
      (libsource (lib "eagle-import") (part "C-EU-C0603-1U"))
    )
    (comp (ref "C233")
      (value "C-EU-C0603")
      (footprint "eagle-import:C0603")
      (fields (field (name "TOLERANCE") "±20 %") (field (name "VOLTAGE") "25.0 V"))
      (libsource (lib "eagle-import") (part "C-EU-C0603"))
    )
    (comp (ref "C234")
      (value "1u 25V")
      (footprint "eagle-import:C0603")
      (fields
        (field (name "MANUFACTURER") "free choice")
        (field (name "TOLERANCE") "±20 %")
        (field (name "VOLTAGE") "25.0 V")
      )
      (libsource (lib "eagle-import") (part "C-EU-C0603-1U"))
    )
    (comp (ref "C235")
      (value "C-EU-C0603")
      (footprint "eagle-import:C0603")
      (fields (field (name "TOLERANCE") "±20 %") (field (name "VOLTAGE") "25.0 V"))
      (libsource (lib "eagle-import") (part "C-EU-C0603"))
    )
    (comp (ref "C236")
      (value "1u 25V")
      (footprint "eagle-import:C0603")
      (fields
        (field (name "MANUFACTURER") "free choice")
        (field (name "TOLERANCE") "±20 %")
        (field (name "VOLTAGE") "25.0 V")
      )
      (libsource (lib "eagle-import") (part "C-EU-C0603-1U"))
    )
    (comp (ref "C237")
      (value "C-EU-C0603")
      (footprint "eagle-import:C0603")
      (fields (field (name "TOLERANCE") "±20 %") (field (name "VOLTAGE") "25.0 V"))
      (libsource (lib "eagle-import") (part "C-EU-C0603"))
    )
    (comp (ref "C238")
      (value "1u 25V")
      (footprint "eagle-import:C0603")
      (fields
        (field (name "MANUFACTURER") "free choice")
        (field (name "TOLERANCE") "±20 %")
        (field (name "VOLTAGE") "25.0 V")
      )
      (libsource (lib "eagle-import") (part "C-EU-C0603-1U"))
    )
    (comp (ref "C239")
      (value "C-EU-C0603")
      (footprint "eagle-import:C0603")
      (fields (field (name "TOLERANCE") "±20 %") (field (name "VOLTAGE") "25.0 V"))
      (libsource (lib "eagle-import") (part "C-EU-C0603"))
    )
    (comp (ref "C240")
      (value "1u 25V")
      (footprint "eagle-import:C0603")
      (fields
        (field (name "MANUFACTURER") "free choice")
        (field (name "TOLERANCE") "±20 %")
        (field (name "VOLTAGE") "25.0 V")
      )
      (libsource (lib "eagle-import") (part "C-EU-C0603-1U"))
    )
    (comp (ref "C241")
      (value "C-EU-C0603")
      (footprint "eagle-import:C0603")
      (fields (field (name "TOLERANCE") "±20 %") (field (name "VOLTAGE") "25.0 V"))
      (libsource (lib "eagle-import") (part "C-EU-C0603"))
    )
    (comp (ref "C242")
      (value "1u 25V")
      (footprint "eagle-import:C0603")
      (fields
        (field (name "MANUFACTURER") "free choice")
        (field (name "TOLERANCE") "±20 %")
        (field (name "VOLTAGE") "25.0 V")
      )
      (libsource (lib "eagle-import") (part "C-EU-C0603-1U"))
    )
    (comp (ref "C243")
      (value "C-EU-C0603")
      (footprint "eagle-import:C0603")
      (fields (field (name "TOLERANCE") "±20 %") (field (name "VOLTAGE") "25.0 V"))
      (libsource (lib "eagle-import") (part "C-EU-C0603"))
    )
    (comp (ref "C244")
      (value "1u 25V")
      (footprint "eagle-import:C0603")
      (fields
        (field (name "MANUFACTURER") "free choice")
        (field (name "TOLERANCE") "±20 %")
        (field (name "VOLTAGE") "25.0 V")
      )
      (libsource (lib "eagle-import") (part "C-EU-C0603-1U"))
    )
    (comp (ref "C245")
      (value "C-EU-C0603")
      (footprint "eagle-import:C0603")
      (fields (field (name "TOLERANCE") "±20 %") (field (name "VOLTAGE") "25.0 V"))
      (libsource (lib "eagle-import") (part "C-EU-C0603"))
    )
    (comp (ref "C246")
      (value "1u 25V")
      (footprint "eagle-import:C0603")
      (fields
        (field (name "MANUFACTURER") "free choice")
        (field (name "TOLERANCE") "±20 %")
        (field (name "VOLTAGE") "25.0 V")
      )
      (libsource (lib "eagle-import") (part "C-EU-C0603-1U"))
    )
    (comp (ref "C247")
      (value "C-EU-C0603")
      (footprint "eagle-import:C0603")
      (fields (field (name "TOLERANCE") "±20 %") (field (name "VOLTAGE") "25.0 V"))
      (libsource (lib "eagle-import") (part "C-EU-C0603"))
    )
    (comp (ref "C248")
      (value "1u 25V")
      (footprint "eagle-import:C0603")
      (fields
        (field (name "MANUFACTURER") "free choice")
        (field (name "TOLERANCE") "±20 %")
        (field (name "VOLTAGE") "25.0 V")
      )
      (libsource (lib "eagle-import") (part "C-EU-C0603-1U"))
    )
    (comp (ref "C249")
      (value "C-EU-C0603")
      (footprint "eagle-import:C0603")
      (fields (field (name "TOLERANCE") "±20 %") (field (name "VOLTAGE") "25.0 V"))
      (libsource (lib "eagle-import") (part "C-EU-C0603"))
    )
    (comp (ref "C250")
      (value "1u 25V")
      (footprint "eagle-import:C0603")
      (fields
        (field (name "MANUFACTURER") "free choice")
        (field (name "TOLERANCE") "±20 %")
        (field (name "VOLTAGE") "25.0 V")
      )
      (libsource (lib "eagle-import") (part "C-EU-C0603-1U"))
    )
    (comp (ref "C251")
      (value "C-EU-C0603")
      (footprint "eagle-import:C0603")
      (fields (field (name "TOLERANCE") "±20 %") (field (name "VOLTAGE") "25.0 V"))
      (libsource (lib "eagle-import") (part "C-EU-C0603"))
    )
    (comp (ref "C252")
      (value "1u 25V")
      (footprint "eagle-import:C0603")
      (fields
        (field (name "MANUFACTURER") "free choice")
        (field (name "TOLERANCE") "±20 %")
        (field (name "VOLTAGE") "25.0 V")
      )
      (libsource (lib "eagle-import") (part "C-EU-C0603-1U"))
    )
    (comp (ref "C253")
      (value "C-EU-C0603")
      (footprint "eagle-import:C0603")
      (fields (field (name "TOLERANCE") "±20 %") (field (name "VOLTAGE") "25.0 V"))
      (libsource (lib "eagle-import") (part "C-EU-C0603"))
    )
    (comp (ref "C254")
      (value "1u 25V")
      (footprint "eagle-import:C0603")
      (fields
        (field (name "MANUFACTURER") "free choice")
        (field (name "TOLERANCE") "±20 %")
        (field (name "VOLTAGE") "25.0 V")
      )
      (libsource (lib "eagle-import") (part "C-EU-C0603-1U"))
    )
    (comp (ref "C255")
      (value "C-EU-C0603")
      (footprint "eagle-import:C0603")
      (fields (field (name "TOLERANCE") "±20 %") (field (name "VOLTAGE") "25.0 V"))
      (libsource (lib "eagle-import") (part "C-EU-C0603"))
    )
    (comp (ref "C256")
      (value "1u 25V")
      (footprint "eagle-import:C0603")
      (fields
        (field (name "MANUFACTURER") "free choice")
        (field (name "TOLERANCE") "±20 %")
        (field (name "VOLTAGE") "25.0 V")
      )
      (libsource (lib "eagle-import") (part "C-EU-C0603-1U"))
    )
    (comp (ref "C257")
      (value "C-EU-C0603")
      (footprint "eagle-import:C0603")
      (fields (field (name "TOLERANCE") "±20 %") (field (name "VOLTAGE") "25.0 V"))
      (libsource (lib "eagle-import") (part "C-EU-C0603"))
    )
    (comp (ref "C258")
      (value "1u 25V")
      (footprint "eagle-import:C0603")
      (fields
        (field (name "MANUFACTURER") "free choice")
        (field (name "TOLERANCE") "±20 %")
        (field (name "VOLTAGE") "25.0 V")
      )
      (libsource (lib "eagle-import") (part "C-EU-C0603-1U"))
    )
    (comp (ref "C259")
      (value "C-EU-C0603")
      (footprint "eagle-import:C0603")
      (fields (field (name "TOLERANCE") "±20 %") (field (name "VOLTAGE") "25.0 V"))
      (libsource (lib "eagle-import") (part "C-EU-C0603"))
    )
    (comp (ref "C260")
      (value "1u 25V")
      (footprint "eagle-import:C0603")
      (fields
        (field (name "MANUFACTURER") "free choice")
        (field (name "TOLERANCE") "±20 %")
        (field (name "VOLTAGE") "25.0 V")
      )
      (libsource (lib "eagle-import") (part "C-EU-C0603-1U"))
    )
    (comp (ref "C261")
      (value "C-EU-C0603")
      (footprint "eagle-import:C0603")
      (fields (field (name "TOLERANCE") "±20 %") (field (name "VOLTAGE") "25.0 V"))
      (libsource (lib "eagle-import") (part "C-EU-C0603"))
    )
    (comp (ref "C262")
      (value "1u 25V")
      (footprint "eagle-import:C0603")
      (fields
        (field (name "MANUFACTURER") "free choice")
        (field (name "TOLERANCE") "±20 %")
        (field (name "VOLTAGE") "25.0 V")
      )
      (libsource (lib "eagle-import") (part "C-EU-C0603-1U"))
    )
    (comp (ref "C263")
      (value "C-EU-C0603")
      (footprint "eagle-import:C0603")
      (fields (field (name "TOLERANCE") "±20 %") (field (name "VOLTAGE") "25.0 V"))
      (libsource (lib "eagle-import") (part "C-EU-C0603"))
    )
    (comp (ref "C264")
      (value "1u 25V")
      (footprint "eagle-import:C0603")
      (fields
        (field (name "MANUFACTURER") "free choice")
        (field (name "TOLERANCE") "±20 %")
        (field (name "VOLTAGE") "25.0 V")
      )
      (libsource (lib "eagle-import") (part "C-EU-C0603-1U"))
    )
    (comp (ref "C265")
      (value "C-EU-C0603")
      (footprint "eagle-import:C0603")
      (fields (field (name "TOLERANCE") "±20 %") (field (name "VOLTAGE") "25.0 V"))
      (libsource (lib "eagle-import") (part "C-EU-C0603"))
    )
    (comp (ref "C266")
      (value "1u 25V")
      (footprint "eagle-import:C0603")
      (fields
        (field (name "MANUFACTURER") "free choice")
        (field (name "TOLERANCE") "±20 %")
        (field (name "VOLTAGE") "25.0 V")
      )
      (libsource (lib "eagle-import") (part "C-EU-C0603-1U"))
    )
    (comp (ref "C270")
      (value "1u 25V")
      (footprint "eagle-import:C0603")
      (fields
        (field (name "MANUFACTURER") "free choice")
        (field (name "TOLERANCE") "±20 %")
        (field (name "VOLTAGE") "25.0 V")
      )
      (libsource (lib "eagle-import") (part "C-EU-C0603-1U"))
    )
    (comp (ref "C272")
      (value "1u 25V")
      (footprint "eagle-import:C0603")
      (fields
        (field (name "MANUFACTURER") "free choice")
        (field (name "TOLERANCE") "±20 %")
        (field (name "VOLTAGE") "25.0 V")
      )
      (libsource (lib "eagle-import") (part "C-EU-C0603-1U"))
    )
    (comp (ref "C280")
      (value "1u 25V")
      (footprint "eagle-import:C0603")
      (fields
        (field (name "MANUFACTURER") "free choice")
        (field (name "TOLERANCE") "±20 %")
        (field (name "VOLTAGE") "25.0 V")
      )
      (libsource (lib "eagle-import") (part "C-EU-C0603-1U"))
    )
    (comp (ref "C281")
      (value "C-EU-C0603")
      (footprint "eagle-import:C0603")
      (fields (field (name "TOLERANCE") "±20 %") (field (name "VOLTAGE") "25.0 V"))
      (libsource (lib "eagle-import") (part "C-EU-C0603"))
    )
    (comp (ref "C282")
      (value "1u 25V")
      (footprint "eagle-import:C0603")
      (fields
        (field (name "MANUFACTURER") "free choice")
        (field (name "TOLERANCE") "±20 %")
        (field (name "VOLTAGE") "25.0 V")
      )
      (libsource (lib "eagle-import") (part "C-EU-C0603-1U"))
    )
    (comp (ref "C283")
      (value "C-EU-C0603")
      (footprint "eagle-import:C0603")
      (fields (field (name "TOLERANCE") "±20 %") (field (name "VOLTAGE") "25.0 V"))
      (libsource (lib "eagle-import") (part "C-EU-C0603"))
    )
    (comp (ref "C284")
      (value "1u 25V")
      (footprint "eagle-import:C0603")
      (fields
        (field (name "MANUFACTURER") "free choice")
        (field (name "TOLERANCE") "±20 %")
        (field (name "VOLTAGE") "25.0 V")
      )
      (libsource (lib "eagle-import") (part "C-EU-C0603-1U"))
    )
    (comp (ref "C285")
      (value "C-EU-C0603")
      (footprint "eagle-import:C0603")
      (fields (field (name "TOLERANCE") "±20 %") (field (name "VOLTAGE") "25.0 V"))
      (libsource (lib "eagle-import") (part "C-EU-C0603"))
    )
    (comp (ref "C286")
      (value "1u 25V")
      (footprint "eagle-import:C0603")
      (fields
        (field (name "MANUFACTURER") "free choice")
        (field (name "TOLERANCE") "±20 %")
        (field (name "VOLTAGE") "25.0 V")
      )
      (libsource (lib "eagle-import") (part "C-EU-C0603-1U"))
    )
    (comp (ref "C287")
      (value "C-EU-C0603")
      (footprint "eagle-import:C0603")
      (fields (field (name "TOLERANCE") "±20 %") (field (name "VOLTAGE") "25.0 V"))
      (libsource (lib "eagle-import") (part "C-EU-C0603"))
    )
    (comp (ref "C288")
      (value "1u 25V")
      (footprint "eagle-import:C0603")
      (fields
        (field (name "MANUFACTURER") "free choice")
        (field (name "TOLERANCE") "±20 %")
        (field (name "VOLTAGE") "25.0 V")
      )
      (libsource (lib "eagle-import") (part "C-EU-C0603-1U"))
    )
    (comp (ref "C289")
      (value "C-EU-C0603")
      (footprint "eagle-import:C0603")
      (fields (field (name "TOLERANCE") "±20 %") (field (name "VOLTAGE") "25.0 V"))
      (libsource (lib "eagle-import") (part "C-EU-C0603"))
    )
    (comp (ref "C290")
      (value "1u 25V")
      (footprint "eagle-import:C0603")
      (fields
        (field (name "MANUFACTURER") "free choice")
        (field (name "TOLERANCE") "±20 %")
        (field (name "VOLTAGE") "25.0 V")
      )
      (libsource (lib "eagle-import") (part "C-EU-C0603-1U"))
    )
    (comp (ref "C291")
      (value "C-EU-C0603")
      (footprint "eagle-import:C0603")
      (fields (field (name "TOLERANCE") "±20 %") (field (name "VOLTAGE") "25.0 V"))
      (libsource (lib "eagle-import") (part "C-EU-C0603"))
    )
    (comp (ref "C292")
      (value "1u 25V")
      (footprint "eagle-import:C0603")
      (fields
        (field (name "MANUFACTURER") "free choice")
        (field (name "TOLERANCE") "±20 %")
        (field (name "VOLTAGE") "25.0 V")
      )
      (libsource (lib "eagle-import") (part "C-EU-C0603-1U"))
    )
    (comp (ref "C293")
      (value "C-EU-C0603")
      (footprint "eagle-import:C0603")
      (fields (field (name "TOLERANCE") "±20 %") (field (name "VOLTAGE") "25.0 V"))
      (libsource (lib "eagle-import") (part "C-EU-C0603"))
    )
    (comp (ref "C294")
      (value "1u 25V")
      (footprint "eagle-import:C0603")
      (fields
        (field (name "MANUFACTURER") "free choice")
        (field (name "TOLERANCE") "±20 %")
        (field (name "VOLTAGE") "25.0 V")
      )
      (libsource (lib "eagle-import") (part "C-EU-C0603-1U"))
    )
    (comp (ref "C295")
      (value "C-EU-C0603")
      (footprint "eagle-import:C0603")
      (fields (field (name "TOLERANCE") "±20 %") (field (name "VOLTAGE") "25.0 V"))
      (libsource (lib "eagle-import") (part "C-EU-C0603"))
    )
    (comp (ref "C296")
      (value "1u 25V")
      (footprint "eagle-import:C0603")
      (fields
        (field (name "MANUFACTURER") "free choice")
        (field (name "TOLERANCE") "±20 %")
        (field (name "VOLTAGE") "25.0 V")
      )
      (libsource (lib "eagle-import") (part "C-EU-C0603-1U"))
    )
    (comp (ref "C297")
      (value "C-EU-C0603")
      (footprint "eagle-import:C0603")
      (fields (field (name "TOLERANCE") "±20 %") (field (name "VOLTAGE") "25.0 V"))
      (libsource (lib "eagle-import") (part "C-EU-C0603"))
    )
    (comp (ref "C298")
      (value "1u 25V")
      (footprint "eagle-import:C0603")
      (fields
        (field (name "MANUFACTURER") "free choice")
        (field (name "TOLERANCE") "±20 %")
        (field (name "VOLTAGE") "25.0 V")
      )
      (libsource (lib "eagle-import") (part "C-EU-C0603-1U"))
    )
    (comp (ref "C299")
      (value "C-EU-C0603")
      (footprint "eagle-import:C0603")
      (fields (field (name "TOLERANCE") "±20 %") (field (name "VOLTAGE") "25.0 V"))
      (libsource (lib "eagle-import") (part "C-EU-C0603"))
    )
    (comp (ref "C300")
      (value "1u 25V")
      (footprint "eagle-import:C0603")
      (fields
        (field (name "MANUFACTURER") "free choice")
        (field (name "TOLERANCE") "±20 %")
        (field (name "VOLTAGE") "25.0 V")
      )
      (libsource (lib "eagle-import") (part "C-EU-C0603-1U"))
    )
    (comp (ref "C301")
      (value "C-EU-C0603")
      (footprint "eagle-import:C0603")
      (fields (field (name "TOLERANCE") "±20 %") (field (name "VOLTAGE") "25.0 V"))
      (libsource (lib "eagle-import") (part "C-EU-C0603"))
    )
    (comp (ref "C302")
      (value "1u 25V")
      (footprint "eagle-import:C0603")
      (fields
        (field (name "MANUFACTURER") "free choice")
        (field (name "TOLERANCE") "±20 %")
        (field (name "VOLTAGE") "25.0 V")
      )
      (libsource (lib "eagle-import") (part "C-EU-C0603-1U"))
    )
    (comp (ref "C303")
      (value "C-EU-C0603")
      (footprint "eagle-import:C0603")
      (fields (field (name "TOLERANCE") "±20 %") (field (name "VOLTAGE") "25.0 V"))
      (libsource (lib "eagle-import") (part "C-EU-C0603"))
    )
    (comp (ref "C304")
      (value "1u 25V")
      (footprint "eagle-import:C0603")
      (fields
        (field (name "MANUFACTURER") "free choice")
        (field (name "TOLERANCE") "±20 %")
        (field (name "VOLTAGE") "25.0 V")
      )
      (libsource (lib "eagle-import") (part "C-EU-C0603-1U"))
    )
    (comp (ref "C305")
      (value "C-EU-C0603")
      (footprint "eagle-import:C0603")
      (fields (field (name "TOLERANCE") "±20 %") (field (name "VOLTAGE") "25.0 V"))
      (libsource (lib "eagle-import") (part "C-EU-C0603"))
    )
    (comp (ref "C306")
      (value "1u 25V")
      (footprint "eagle-import:C0603")
      (fields
        (field (name "MANUFACTURER") "free choice")
        (field (name "TOLERANCE") "±20 %")
        (field (name "VOLTAGE") "25.0 V")
      )
      (libsource (lib "eagle-import") (part "C-EU-C0603-1U"))
    )
    (comp (ref "C307")
      (value "C-EU-C0603")
      (footprint "eagle-import:C0603")
      (fields (field (name "TOLERANCE") "±20 %") (field (name "VOLTAGE") "25.0 V"))
      (libsource (lib "eagle-import") (part "C-EU-C0603"))
    )
    (comp (ref "C308")
      (value "1u 25V")
      (footprint "eagle-import:C0603")
      (fields
        (field (name "MANUFACTURER") "free choice")
        (field (name "TOLERANCE") "±20 %")
        (field (name "VOLTAGE") "25.0 V")
      )
      (libsource (lib "eagle-import") (part "C-EU-C0603-1U"))
    )
    (comp (ref "C309")
      (value "C-EU-C0603")
      (footprint "eagle-import:C0603")
      (fields (field (name "TOLERANCE") "±20 %") (field (name "VOLTAGE") "25.0 V"))
      (libsource (lib "eagle-import") (part "C-EU-C0603"))
    )
    (comp (ref "C310")
      (value "1u 25V")
      (footprint "eagle-import:C0603")
      (fields
        (field (name "MANUFACTURER") "free choice")
        (field (name "TOLERANCE") "±20 %")
        (field (name "VOLTAGE") "25.0 V")
      )
      (libsource (lib "eagle-import") (part "C-EU-C0603-1U"))
    )
    (comp (ref "C311")
      (value "C-EU-C0603")
      (footprint "eagle-import:C0603")
      (fields (field (name "TOLERANCE") "±20 %") (field (name "VOLTAGE") "25.0 V"))
      (libsource (lib "eagle-import") (part "C-EU-C0603"))
    )
    (comp (ref "C312")
      (value "1u 25V")
      (footprint "eagle-import:C0603")
      (fields
        (field (name "MANUFACTURER") "free choice")
        (field (name "TOLERANCE") "±20 %")
        (field (name "VOLTAGE") "25.0 V")
      )
      (libsource (lib "eagle-import") (part "C-EU-C0603-1U"))
    )
    (comp (ref "C313")
      (value "C-EU-C0603")
      (footprint "eagle-import:C0603")
      (fields (field (name "TOLERANCE") "±20 %") (field (name "VOLTAGE") "25.0 V"))
      (libsource (lib "eagle-import") (part "C-EU-C0603"))
    )
    (comp (ref "C314")
      (value "1u 25V")
      (footprint "eagle-import:C0603")
      (fields
        (field (name "MANUFACTURER") "free choice")
        (field (name "TOLERANCE") "±20 %")
        (field (name "VOLTAGE") "25.0 V")
      )
      (libsource (lib "eagle-import") (part "C-EU-C0603-1U"))
    )
    (comp (ref "C315")
      (value "C-EU-C0603")
      (footprint "eagle-import:C0603")
      (fields (field (name "TOLERANCE") "±20 %") (field (name "VOLTAGE") "25.0 V"))
      (libsource (lib "eagle-import") (part "C-EU-C0603"))
    )
    (comp (ref "C316")
      (value "1u 25V")
      (footprint "eagle-import:C0603")
      (fields
        (field (name "MANUFACTURER") "free choice")
        (field (name "TOLERANCE") "±20 %")
        (field (name "VOLTAGE") "25.0 V")
      )
      (libsource (lib "eagle-import") (part "C-EU-C0603-1U"))
    )
    (comp (ref "C317")
      (value "C-EU-C0603")
      (footprint "eagle-import:C0603")
      (fields (field (name "TOLERANCE") "±20 %") (field (name "VOLTAGE") "25.0 V"))
      (libsource (lib "eagle-import") (part "C-EU-C0603"))
    )
    (comp (ref "C318")
      (value "1u 25V")
      (footprint "eagle-import:C0603")
      (fields
        (field (name "MANUFACTURER") "free choice")
        (field (name "TOLERANCE") "±20 %")
        (field (name "VOLTAGE") "25.0 V")
      )
      (libsource (lib "eagle-import") (part "C-EU-C0603-1U"))
    )
    (comp (ref "C319")
      (value "C-EU-C0603")
      (footprint "eagle-import:C0603")
      (fields (field (name "TOLERANCE") "±20 %") (field (name "VOLTAGE") "25.0 V"))
      (libsource (lib "eagle-import") (part "C-EU-C0603"))
    )
    (comp (ref "C320")
      (value "1u 25V")
      (footprint "eagle-import:C0603")
      (fields
        (field (name "MANUFACTURER") "free choice")
        (field (name "TOLERANCE") "±20 %")
        (field (name "VOLTAGE") "25.0 V")
      )
      (libsource (lib "eagle-import") (part "C-EU-C0603-1U"))
    )
    (comp (ref "C321")
      (value "C-EU-C0603")
      (footprint "eagle-import:C0603")
      (fields (field (name "TOLERANCE") "±20 %") (field (name "VOLTAGE") "25.0 V"))
      (libsource (lib "eagle-import") (part "C-EU-C0603"))
    )
    (comp (ref "C322")
      (value "1u 25V")
      (footprint "eagle-import:C0603")
      (fields
        (field (name "MANUFACTURER") "free choice")
        (field (name "TOLERANCE") "±20 %")
        (field (name "VOLTAGE") "25.0 V")
      )
      (libsource (lib "eagle-import") (part "C-EU-C0603-1U"))
    )
    (comp (ref "C323")
      (value "C-EU-C0603")
      (footprint "eagle-import:C0603")
      (fields (field (name "TOLERANCE") "±20 %") (field (name "VOLTAGE") "25.0 V"))
      (libsource (lib "eagle-import") (part "C-EU-C0603"))
    )
    (comp (ref "C324")
      (value "1u 25V")
      (footprint "eagle-import:C0603")
      (fields
        (field (name "MANUFACTURER") "free choice")
        (field (name "TOLERANCE") "±20 %")
        (field (name "VOLTAGE") "25.0 V")
      )
      (libsource (lib "eagle-import") (part "C-EU-C0603-1U"))
    )
    (comp (ref "C325")
      (value "C-EU-C0603")
      (footprint "eagle-import:C0603")
      (fields (field (name "TOLERANCE") "±20 %") (field (name "VOLTAGE") "25.0 V"))
      (libsource (lib "eagle-import") (part "C-EU-C0603"))
    )
    (comp (ref "C326")
      (value "1u 25V")
      (footprint "eagle-import:C0603")
      (fields
        (field (name "MANUFACTURER") "free choice")
        (field (name "TOLERANCE") "±20 %")
        (field (name "VOLTAGE") "25.0 V")
      )
      (libsource (lib "eagle-import") (part "C-EU-C0603-1U"))
    )
    (comp (ref "C327")
      (value "C-EU-C0603")
      (footprint "eagle-import:C0603")
      (fields (field (name "TOLERANCE") "±20 %") (field (name "VOLTAGE") "25.0 V"))
      (libsource (lib "eagle-import") (part "C-EU-C0603"))
    )
    (comp (ref "C328")
      (value "1u 25V")
      (footprint "eagle-import:C0603")
      (fields
        (field (name "MANUFACTURER") "free choice")
        (field (name "TOLERANCE") "±20 %")
        (field (name "VOLTAGE") "25.0 V")
      )
      (libsource (lib "eagle-import") (part "C-EU-C0603-1U"))
    )
    (comp (ref "C329")
      (value "C-EU-C0603")
      (footprint "eagle-import:C0603")
      (fields (field (name "TOLERANCE") "±20 %") (field (name "VOLTAGE") "25.0 V"))
      (libsource (lib "eagle-import") (part "C-EU-C0603"))
    )
    (comp (ref "C330")
      (value "1u 25V")
      (footprint "eagle-import:C0603")
      (fields
        (field (name "MANUFACTURER") "free choice")
        (field (name "TOLERANCE") "±20 %")
        (field (name "VOLTAGE") "25.0 V")
      )
      (libsource (lib "eagle-import") (part "C-EU-C0603-1U"))
    )
    (comp (ref "C331")
      (value "C-EU-C0603")
      (footprint "eagle-import:C0603")
      (fields (field (name "TOLERANCE") "±20 %") (field (name "VOLTAGE") "25.0 V"))
      (libsource (lib "eagle-import") (part "C-EU-C0603"))
    )
    (comp (ref "C332")
      (value "1u 25V")
      (footprint "eagle-import:C0603")
      (fields
        (field (name "MANUFACTURER") "free choice")
        (field (name "TOLERANCE") "±20 %")
        (field (name "VOLTAGE") "25.0 V")
      )
      (libsource (lib "eagle-import") (part "C-EU-C0603-1U"))
    )
    (comp (ref "D1")
      (value "150060RS75000")
      (footprint "eagle-import:WL-SMCW_0603_WE")
      (fields (field (name "MANUFACTURER") "Wuerth") (field (name "VOLTAGE") "5.0 V"))
      (libsource (lib "eagle-import") (part "150060RS75000"))
    )
    (comp (ref "D2")
      (value "150060GS75000")
      (footprint "eagle-import:WL-SMCW_0603_WE")
      (fields (field (name "MANUFACTURER") "Wuerth") (field (name "VOLTAGE") "5.0 V"))
      (libsource (lib "eagle-import") (part "150060GS75000"))
    )
    (comp (ref "D100")
      (value "LZ1-00R302")
      (footprint "eagle-import:LZ1_SMALL_LEDENGIN")
      (fields (field (name "MANUFACTURER") "Osram"))
      (libsource (lib "eagle-import") (part "LZ1-00R302-SMALL"))
    )
    (comp (ref "D101")
      (value "LZ1-00R302")
      (footprint "eagle-import:LZ1_SMALL_LEDENGIN")
      (fields (field (name "MANUFACTURER") "Osram"))
      (libsource (lib "eagle-import") (part "LZ1-00R302-SMALL"))
    )
    (comp (ref "D102")
      (value "LZ1-00R302")
      (footprint "eagle-import:LZ1_SMALL_LEDENGIN")
      (fields (field (name "MANUFACTURER") "Osram"))
      (libsource (lib "eagle-import") (part "LZ1-00R302-SMALL"))
    )
    (comp (ref "D103")
      (value "LZ1-00R302")
      (footprint "eagle-import:LZ1_SMALL_LEDENGIN")
      (fields (field (name "MANUFACTURER") "Osram"))
      (libsource (lib "eagle-import") (part "LZ1-00R302-SMALL"))
    )
    (comp (ref "D104")
      (value "LZ1-00R302")
      (footprint "eagle-import:LZ1_SMALL_LEDENGIN")
      (fields (field (name "MANUFACTURER") "Osram"))
      (libsource (lib "eagle-import") (part "LZ1-00R302-SMALL"))
    )
    (comp (ref "D105")
      (value "LZ1-00R302")
      (footprint "eagle-import:LZ1_SMALL_LEDENGIN")
      (fields (field (name "MANUFACTURER") "Osram"))
      (libsource (lib "eagle-import") (part "LZ1-00R302-SMALL"))
    )
    (comp (ref "D106")
      (value "LZ1-00R302")
      (footprint "eagle-import:LZ1_SMALL_LEDENGIN")
      (fields (field (name "MANUFACTURER") "Osram"))
      (libsource (lib "eagle-import") (part "LZ1-00R302-SMALL"))
    )
    (comp (ref "D107")
      (value "LZ1-00R302")
      (footprint "eagle-import:LZ1_SMALL_LEDENGIN")
      (fields (field (name "MANUFACTURER") "Osram"))
      (libsource (lib "eagle-import") (part "LZ1-00R302-SMALL"))
    )
    (comp (ref "D108")
      (value "LZ1-00R302")
      (footprint "eagle-import:LZ1_SMALL_LEDENGIN")
      (fields (field (name "MANUFACTURER") "Osram"))
      (libsource (lib "eagle-import") (part "LZ1-00R302-SMALL"))
    )
    (comp (ref "D109")
      (value "LZ1-00R302")
      (footprint "eagle-import:LZ1_SMALL_LEDENGIN")
      (fields (field (name "MANUFACTURER") "Osram"))
      (libsource (lib "eagle-import") (part "LZ1-00R302-SMALL"))
    )
    (comp (ref "D110")
      (value "LZ1-00R302")
      (footprint "eagle-import:LZ1_SMALL_LEDENGIN")
      (fields (field (name "MANUFACTURER") "Osram"))
      (libsource (lib "eagle-import") (part "LZ1-00R302-SMALL"))
    )
    (comp (ref "D111")
      (value "LZ1-00R302")
      (footprint "eagle-import:LZ1_SMALL_LEDENGIN")
      (fields (field (name "MANUFACTURER") "Osram"))
      (libsource (lib "eagle-import") (part "LZ1-00R302-SMALL"))
    )
    (comp (ref "D112")
      (value "LZ1-00R302")
      (footprint "eagle-import:LZ1_SMALL_LEDENGIN")
      (fields (field (name "MANUFACTURER") "Osram"))
      (libsource (lib "eagle-import") (part "LZ1-00R302-SMALL"))
    )
    (comp (ref "D200")
      (value "SST-10-IRD-B50-T850")
      (footprint "eagle-import:B50_LUMINUS")
      (fields (field (name "MANUFACTURER") "Luminus") (field (name "VOLTAGE") "5.0 V"))
      (libsource (lib "eagle-import") (part "SST-10-IRD-B50-T850"))
    )
    (comp (ref "D201")
      (value "SST-10-IRD-B50-T850")
      (footprint "eagle-import:B50_LUMINUS")
      (fields (field (name "MANUFACTURER") "Luminus") (field (name "VOLTAGE") "5.0 V"))
      (libsource (lib "eagle-import") (part "SST-10-IRD-B50-T850"))
    )
    (comp (ref "D202")
      (value "SST-10-IRD-B50-T850")
      (footprint "eagle-import:B50_LUMINUS")
      (fields (field (name "MANUFACTURER") "Luminus") (field (name "VOLTAGE") "5.0 V"))
      (libsource (lib "eagle-import") (part "SST-10-IRD-B50-T850"))
    )
    (comp (ref "D203")
      (value "SST-10-IRD-B50-T850")
      (footprint "eagle-import:B50_LUMINUS")
      (fields (field (name "MANUFACTURER") "Luminus") (field (name "VOLTAGE") "5.0 V"))
      (libsource (lib "eagle-import") (part "SST-10-IRD-B50-T850"))
    )
    (comp (ref "D204")
      (value "SST-10-IRD-B50-T850")
      (footprint "eagle-import:B50_LUMINUS")
      (fields (field (name "MANUFACTURER") "Luminus") (field (name "VOLTAGE") "5.0 V"))
      (libsource (lib "eagle-import") (part "SST-10-IRD-B50-T850"))
    )
    (comp (ref "D205")
      (value "SST-10-IRD-B50-T850")
      (footprint "eagle-import:B50_LUMINUS")
      (fields (field (name "MANUFACTURER") "Luminus") (field (name "VOLTAGE") "5.0 V"))
      (libsource (lib "eagle-import") (part "SST-10-IRD-B50-T850"))
    )
    (comp (ref "D206")
      (value "SST-10-IRD-B50-T850")
      (footprint "eagle-import:B50_LUMINUS")
      (fields (field (name "MANUFACTURER") "Luminus") (field (name "VOLTAGE") "5.0 V"))
      (libsource (lib "eagle-import") (part "SST-10-IRD-B50-T850"))
    )
    (comp (ref "D207")
      (value "SST-10-IRD-B50-T850")
      (footprint "eagle-import:B50_LUMINUS")
      (fields (field (name "MANUFACTURER") "Luminus") (field (name "VOLTAGE") "5.0 V"))
      (libsource (lib "eagle-import") (part "SST-10-IRD-B50-T850"))
    )
    (comp (ref "D208")
      (value "SST-10-IRD-B50-T850")
      (footprint "eagle-import:B50_LUMINUS")
      (fields (field (name "MANUFACTURER") "Luminus") (field (name "VOLTAGE") "5.0 V"))
      (libsource (lib "eagle-import") (part "SST-10-IRD-B50-T850"))
    )
    (comp (ref "D209")
      (value "SST-10-IRD-B50-T850")
      (footprint "eagle-import:B50_LUMINUS")
      (fields (field (name "MANUFACTURER") "Luminus") (field (name "VOLTAGE") "5.0 V"))
      (libsource (lib "eagle-import") (part "SST-10-IRD-B50-T850"))
    )
    (comp (ref "D210")
      (value "SST-10-IRD-B50-T850")
      (footprint "eagle-import:B50_LUMINUS")
      (fields (field (name "MANUFACTURER") "Luminus") (field (name "VOLTAGE") "5.0 V"))
      (libsource (lib "eagle-import") (part "SST-10-IRD-B50-T850"))
    )
    (comp (ref "D211")
      (value "SST-10-IRD-B50-T850")
      (footprint "eagle-import:B50_LUMINUS")
      (fields (field (name "MANUFACTURER") "Luminus") (field (name "VOLTAGE") "5.0 V"))
      (libsource (lib "eagle-import") (part "SST-10-IRD-B50-T850"))
    )
    (comp (ref "D212")
      (value "SST-10-IRD-B50-T850")
      (footprint "eagle-import:B50_LUMINUS")
      (fields (field (name "MANUFACTURER") "Luminus") (field (name "VOLTAGE") "5.0 V"))
      (libsource (lib "eagle-import") (part "SST-10-IRD-B50-T850"))
    )
    (comp (ref "D213")
      (value "SST-10-IRD-B50-T850")
      (footprint "eagle-import:B50_LUMINUS")
      (fields (field (name "MANUFACTURER") "Luminus") (field (name "VOLTAGE") "5.0 V"))
      (libsource (lib "eagle-import") (part "SST-10-IRD-B50-T850"))
    )
    (comp (ref "D214")
      (value "SST-10-IRD-B50-T850")
      (footprint "eagle-import:B50_LUMINUS")
      (fields (field (name "MANUFACTURER") "Luminus") (field (name "VOLTAGE") "5.0 V"))
      (libsource (lib "eagle-import") (part "SST-10-IRD-B50-T850"))
    )
    (comp (ref "D215")
      (value "SST-10-IRD-B50-T850")
      (footprint "eagle-import:B50_LUMINUS")
      (fields (field (name "MANUFACTURER") "Luminus") (field (name "VOLTAGE") "5.0 V"))
      (libsource (lib "eagle-import") (part "SST-10-IRD-B50-T850"))
    )
    (comp (ref "D250")
      (value "SST-10-IRD-B50-T850")
      (footprint "eagle-import:B50_LUMINUS")
      (fields (field (name "MANUFACTURER") "Luminus") (field (name "VOLTAGE") "5.0 V"))
      (libsource (lib "eagle-import") (part "SST-10-IRD-B50-T850"))
    )
    (comp (ref "D251")
      (value "SST-10-IRD-B50-T850")
      (footprint "eagle-import:B50_LUMINUS")
      (fields (field (name "MANUFACTURER") "Luminus") (field (name "VOLTAGE") "5.0 V"))
      (libsource (lib "eagle-import") (part "SST-10-IRD-B50-T850"))
    )
    (comp (ref "D252")
      (value "SST-10-IRD-B50-T850")
      (footprint "eagle-import:B50_LUMINUS")
      (fields (field (name "MANUFACTURER") "Luminus") (field (name "VOLTAGE") "5.0 V"))
      (libsource (lib "eagle-import") (part "SST-10-IRD-B50-T850"))
    )
    (comp (ref "D253")
      (value "SST-10-IRD-B50-T850")
      (footprint "eagle-import:B50_LUMINUS")
      (fields (field (name "MANUFACTURER") "Luminus") (field (name "VOLTAGE") "5.0 V"))
      (libsource (lib "eagle-import") (part "SST-10-IRD-B50-T850"))
    )
    (comp (ref "D254")
      (value "SST-10-IRD-B50-T850")
      (footprint "eagle-import:B50_LUMINUS")
      (fields (field (name "MANUFACTURER") "Luminus") (field (name "VOLTAGE") "5.0 V"))
      (libsource (lib "eagle-import") (part "SST-10-IRD-B50-T850"))
    )
    (comp (ref "D255")
      (value "SST-10-IRD-B50-T850")
      (footprint "eagle-import:B50_LUMINUS")
      (fields (field (name "MANUFACTURER") "Luminus") (field (name "VOLTAGE") "5.0 V"))
      (libsource (lib "eagle-import") (part "SST-10-IRD-B50-T850"))
    )
    (comp (ref "D256")
      (value "SST-10-IRD-B50-T850")
      (footprint "eagle-import:B50_LUMINUS")
      (fields (field (name "MANUFACTURER") "Luminus") (field (name "VOLTAGE") "5.0 V"))
      (libsource (lib "eagle-import") (part "SST-10-IRD-B50-T850"))
    )
    (comp (ref "D257")
      (value "SST-10-IRD-B50-T850")
      (footprint "eagle-import:B50_LUMINUS")
      (fields (field (name "MANUFACTURER") "Luminus") (field (name "VOLTAGE") "5.0 V"))
      (libsource (lib "eagle-import") (part "SST-10-IRD-B50-T850"))
    )
    (comp (ref "D258")
      (value "SST-10-IRD-B50-T850")
      (footprint "eagle-import:B50_LUMINUS")
      (fields (field (name "MANUFACTURER") "Luminus") (field (name "VOLTAGE") "5.0 V"))
      (libsource (lib "eagle-import") (part "SST-10-IRD-B50-T850"))
    )
    (comp (ref "D259")
      (value "SST-10-IRD-B50-T850")
      (footprint "eagle-import:B50_LUMINUS")
      (fields (field (name "MANUFACTURER") "Luminus") (field (name "VOLTAGE") "5.0 V"))
      (libsource (lib "eagle-import") (part "SST-10-IRD-B50-T850"))
    )
    (comp (ref "D260")
      (value "SST-10-IRD-B50-T850")
      (footprint "eagle-import:B50_LUMINUS")
      (fields (field (name "MANUFACTURER") "Luminus") (field (name "VOLTAGE") "5.0 V"))
      (libsource (lib "eagle-import") (part "SST-10-IRD-B50-T850"))
    )
    (comp (ref "D261")
      (value "SST-10-IRD-B50-T850")
      (footprint "eagle-import:B50_LUMINUS")
      (fields (field (name "MANUFACTURER") "Luminus") (field (name "VOLTAGE") "5.0 V"))
      (libsource (lib "eagle-import") (part "SST-10-IRD-B50-T850"))
    )
    (comp (ref "D262")
      (value "SST-10-IRD-B50-T850")
      (footprint "eagle-import:B50_LUMINUS")
      (fields (field (name "MANUFACTURER") "Luminus") (field (name "VOLTAGE") "5.0 V"))
      (libsource (lib "eagle-import") (part "SST-10-IRD-B50-T850"))
    )
    (comp (ref "D263")
      (value "SST-10-IRD-B50-T850")
      (footprint "eagle-import:B50_LUMINUS")
      (fields (field (name "MANUFACTURER") "Luminus") (field (name "VOLTAGE") "5.0 V"))
      (libsource (lib "eagle-import") (part "SST-10-IRD-B50-T850"))
    )
    (comp (ref "D264")
      (value "SST-10-IRD-B50-T850")
      (footprint "eagle-import:B50_LUMINUS")
      (fields (field (name "MANUFACTURER") "Luminus") (field (name "VOLTAGE") "5.0 V"))
      (libsource (lib "eagle-import") (part "SST-10-IRD-B50-T850"))
    )
    (comp (ref "D265")
      (value "SST-10-IRD-B50-T850")
      (footprint "eagle-import:B50_LUMINUS")
      (fields (field (name "MANUFACTURER") "Luminus") (field (name "VOLTAGE") "5.0 V"))
      (libsource (lib "eagle-import") (part "SST-10-IRD-B50-T850"))
    )
    (comp (ref "D300")
      (value "SST-10-IRD-B50-S940")
      (footprint "eagle-import:B50_LUMINUS")
      (fields (field (name "MANUFACTURER") "Luminus") (field (name "VOLTAGE") "5.0 V"))
      (libsource (lib "eagle-import") (part "SST-10-IRD-B50-S940"))
    )
    (comp (ref "D301")
      (value "SST-10-IRD-B50-S940")
      (footprint "eagle-import:B50_LUMINUS")
      (fields (field (name "MANUFACTURER") "Luminus") (field (name "VOLTAGE") "5.0 V"))
      (libsource (lib "eagle-import") (part "SST-10-IRD-B50-S940"))
    )
    (comp (ref "D302")
      (value "SST-10-IRD-B50-S940")
      (footprint "eagle-import:B50_LUMINUS")
      (fields (field (name "MANUFACTURER") "Luminus") (field (name "VOLTAGE") "5.0 V"))
      (libsource (lib "eagle-import") (part "SST-10-IRD-B50-S940"))
    )
    (comp (ref "D303")
      (value "SST-10-IRD-B50-S940")
      (footprint "eagle-import:B50_LUMINUS")
      (fields (field (name "MANUFACTURER") "Luminus") (field (name "VOLTAGE") "5.0 V"))
      (libsource (lib "eagle-import") (part "SST-10-IRD-B50-S940"))
    )
    (comp (ref "D304")
      (value "SST-10-IRD-B50-S940")
      (footprint "eagle-import:B50_LUMINUS")
      (fields (field (name "MANUFACTURER") "Luminus") (field (name "VOLTAGE") "5.0 V"))
      (libsource (lib "eagle-import") (part "SST-10-IRD-B50-S940"))
    )
    (comp (ref "D305")
      (value "SST-10-IRD-B50-S940")
      (footprint "eagle-import:B50_LUMINUS")
      (fields (field (name "MANUFACTURER") "Luminus") (field (name "VOLTAGE") "5.0 V"))
      (libsource (lib "eagle-import") (part "SST-10-IRD-B50-S940"))
    )
    (comp (ref "D306")
      (value "SST-10-IRD-B50-S940")
      (footprint "eagle-import:B50_LUMINUS")
      (fields (field (name "MANUFACTURER") "Luminus") (field (name "VOLTAGE") "5.0 V"))
      (libsource (lib "eagle-import") (part "SST-10-IRD-B50-S940"))
    )
    (comp (ref "D307")
      (value "SST-10-IRD-B50-S940")
      (footprint "eagle-import:B50_LUMINUS")
      (fields (field (name "MANUFACTURER") "Luminus") (field (name "VOLTAGE") "5.0 V"))
      (libsource (lib "eagle-import") (part "SST-10-IRD-B50-S940"))
    )
    (comp (ref "D308")
      (value "SST-10-IRD-B50-S940")
      (footprint "eagle-import:B50_LUMINUS")
      (fields (field (name "MANUFACTURER") "Luminus") (field (name "VOLTAGE") "5.0 V"))
      (libsource (lib "eagle-import") (part "SST-10-IRD-B50-S940"))
    )
    (comp (ref "D309")
      (value "SST-10-IRD-B50-S940")
      (footprint "eagle-import:B50_LUMINUS")
      (fields (field (name "MANUFACTURER") "Luminus") (field (name "VOLTAGE") "5.0 V"))
      (libsource (lib "eagle-import") (part "SST-10-IRD-B50-S940"))
    )
    (comp (ref "D310")
      (value "SST-10-IRD-B50-S940")
      (footprint "eagle-import:B50_LUMINUS")
      (fields (field (name "MANUFACTURER") "Luminus") (field (name "VOLTAGE") "5.0 V"))
      (libsource (lib "eagle-import") (part "SST-10-IRD-B50-S940"))
    )
    (comp (ref "D311")
      (value "SST-10-IRD-B50-S940")
      (footprint "eagle-import:B50_LUMINUS")
      (fields (field (name "MANUFACTURER") "Luminus") (field (name "VOLTAGE") "5.0 V"))
      (libsource (lib "eagle-import") (part "SST-10-IRD-B50-S940"))
    )
    (comp (ref "D312")
      (value "SST-10-IRD-B50-S940")
      (footprint "eagle-import:B50_LUMINUS")
      (fields (field (name "MANUFACTURER") "Luminus") (field (name "VOLTAGE") "5.0 V"))
      (libsource (lib "eagle-import") (part "SST-10-IRD-B50-S940"))
    )
    (comp (ref "D313")
      (value "SST-10-IRD-B50-S940")
      (footprint "eagle-import:B50_LUMINUS")
      (fields (field (name "MANUFACTURER") "Luminus") (field (name "VOLTAGE") "5.0 V"))
      (libsource (lib "eagle-import") (part "SST-10-IRD-B50-S940"))
    )
    (comp (ref "D314")
      (value "SST-10-IRD-B50-S940")
      (footprint "eagle-import:B50_LUMINUS")
      (fields (field (name "MANUFACTURER") "Luminus") (field (name "VOLTAGE") "5.0 V"))
      (libsource (lib "eagle-import") (part "SST-10-IRD-B50-S940"))
    )
    (comp (ref "D315")
      (value "SST-10-IRD-B50-S940")
      (footprint "eagle-import:B50_LUMINUS")
      (fields (field (name "MANUFACTURER") "Luminus") (field (name "VOLTAGE") "5.0 V"))
      (libsource (lib "eagle-import") (part "SST-10-IRD-B50-S940"))
    )
    (comp (ref "D350")
      (value "SST-10-IRD-B50-S940")
      (footprint "eagle-import:B50_LUMINUS")
      (fields (field (name "MANUFACTURER") "Luminus") (field (name "VOLTAGE") "5.0 V"))
      (libsource (lib "eagle-import") (part "SST-10-IRD-B50-S940"))
    )
    (comp (ref "D351")
      (value "SST-10-IRD-B50-S940")
      (footprint "eagle-import:B50_LUMINUS")
      (fields (field (name "MANUFACTURER") "Luminus") (field (name "VOLTAGE") "5.0 V"))
      (libsource (lib "eagle-import") (part "SST-10-IRD-B50-S940"))
    )
    (comp (ref "D352")
      (value "SST-10-IRD-B50-S940")
      (footprint "eagle-import:B50_LUMINUS")
      (fields (field (name "MANUFACTURER") "Luminus") (field (name "VOLTAGE") "5.0 V"))
      (libsource (lib "eagle-import") (part "SST-10-IRD-B50-S940"))
    )
    (comp (ref "D353")
      (value "SST-10-IRD-B50-S940")
      (footprint "eagle-import:B50_LUMINUS")
      (fields (field (name "MANUFACTURER") "Luminus") (field (name "VOLTAGE") "5.0 V"))
      (libsource (lib "eagle-import") (part "SST-10-IRD-B50-S940"))
    )
    (comp (ref "D354")
      (value "SST-10-IRD-B50-S940")
      (footprint "eagle-import:B50_LUMINUS")
      (fields (field (name "MANUFACTURER") "Luminus") (field (name "VOLTAGE") "5.0 V"))
      (libsource (lib "eagle-import") (part "SST-10-IRD-B50-S940"))
    )
    (comp (ref "D355")
      (value "SST-10-IRD-B50-S940")
      (footprint "eagle-import:B50_LUMINUS")
      (fields (field (name "MANUFACTURER") "Luminus") (field (name "VOLTAGE") "5.0 V"))
      (libsource (lib "eagle-import") (part "SST-10-IRD-B50-S940"))
    )
    (comp (ref "D356")
      (value "SST-10-IRD-B50-S940")
      (footprint "eagle-import:B50_LUMINUS")
      (fields (field (name "MANUFACTURER") "Luminus") (field (name "VOLTAGE") "5.0 V"))
      (libsource (lib "eagle-import") (part "SST-10-IRD-B50-S940"))
    )
    (comp (ref "D357")
      (value "SST-10-IRD-B50-S940")
      (footprint "eagle-import:B50_LUMINUS")
      (fields (field (name "MANUFACTURER") "Luminus") (field (name "VOLTAGE") "5.0 V"))
      (libsource (lib "eagle-import") (part "SST-10-IRD-B50-S940"))
    )
    (comp (ref "D358")
      (value "SST-10-IRD-B50-S940")
      (footprint "eagle-import:B50_LUMINUS")
      (fields (field (name "MANUFACTURER") "Luminus") (field (name "VOLTAGE") "5.0 V"))
      (libsource (lib "eagle-import") (part "SST-10-IRD-B50-S940"))
    )
    (comp (ref "D359")
      (value "SST-10-IRD-B50-S940")
      (footprint "eagle-import:B50_LUMINUS")
      (fields (field (name "MANUFACTURER") "Luminus") (field (name "VOLTAGE") "5.0 V"))
      (libsource (lib "eagle-import") (part "SST-10-IRD-B50-S940"))
    )
    (comp (ref "D360")
      (value "SST-10-IRD-B50-S940")
      (footprint "eagle-import:B50_LUMINUS")
      (fields (field (name "MANUFACTURER") "Luminus") (field (name "VOLTAGE") "5.0 V"))
      (libsource (lib "eagle-import") (part "SST-10-IRD-B50-S940"))
    )
    (comp (ref "D361")
      (value "SST-10-IRD-B50-S940")
      (footprint "eagle-import:B50_LUMINUS")
      (fields (field (name "MANUFACTURER") "Luminus") (field (name "VOLTAGE") "5.0 V"))
      (libsource (lib "eagle-import") (part "SST-10-IRD-B50-S940"))
    )
    (comp (ref "D362")
      (value "SST-10-IRD-B50-S940")
      (footprint "eagle-import:B50_LUMINUS")
      (fields (field (name "MANUFACTURER") "Luminus") (field (name "VOLTAGE") "5.0 V"))
      (libsource (lib "eagle-import") (part "SST-10-IRD-B50-S940"))
    )
    (comp (ref "D363")
      (value "SST-10-IRD-B50-S940")
      (footprint "eagle-import:B50_LUMINUS")
      (fields (field (name "MANUFACTURER") "Luminus") (field (name "VOLTAGE") "5.0 V"))
      (libsource (lib "eagle-import") (part "SST-10-IRD-B50-S940"))
    )
    (comp (ref "D364")
      (value "SST-10-IRD-B50-S940")
      (footprint "eagle-import:B50_LUMINUS")
      (fields (field (name "MANUFACTURER") "Luminus") (field (name "VOLTAGE") "5.0 V"))
      (libsource (lib "eagle-import") (part "SST-10-IRD-B50-S940"))
    )
    (comp (ref "D365")
      (value "SST-10-IRD-B50-S940")
      (footprint "eagle-import:B50_LUMINUS")
      (fields (field (name "MANUFACTURER") "Luminus") (field (name "VOLTAGE") "5.0 V"))
      (libsource (lib "eagle-import") (part "SST-10-IRD-B50-S940"))
    )
    (comp (ref "IC1")
      (value "UCC27517DBV")
      (footprint "eagle-import:DBV0005A_TI")
      (fields (field (name "MANUFACTURER") "TI") (field (name "VOLTAGE") "18.0 V"))
      (libsource (lib "eagle-import") (part "UCC27517DBV"))
    )
    (comp (ref "IC2")
      (value "UCC27517DBV")
      (footprint "eagle-import:DBV0005A_TI")
      (fields (field (name "MANUFACTURER") "TI") (field (name "VOLTAGE") "18.0 V"))
      (libsource (lib "eagle-import") (part "UCC27517DBV"))
    )
    (comp (ref "IC3")
      (value "LM393BIDSG")
      (footprint "eagle-import:DSG0008A_WSON_TI_NO_VIA")
      (fields (field (name "MANUFACTURER") "TI") (field (name "VOLTAGE") "36.0 V"))
      (libsource (lib "eagle-import") (part "LM393BIDSG_NO_VIA"))
    )
    (comp (ref "IC4")
      (value "LM393BIDSG")
      (footprint "eagle-import:DSG0008A_WSON_TI_NO_VIA")
      (fields (field (name "MANUFACTURER") "TI") (field (name "VOLTAGE") "36.0 V"))
      (libsource (lib "eagle-import") (part "LM393BIDSG_NO_VIA"))
    )
    (comp (ref "IC5")
      (value "LM393BIDSG")
      (footprint "eagle-import:DSG0008A_WSON_TI_NO_VIA")
      (fields (field (name "MANUFACTURER") "TI") (field (name "VOLTAGE") "36.0 V"))
      (libsource (lib "eagle-import") (part "LM393BIDSG_NO_VIA"))
    )
    (comp (ref "IC7")
      (value "VL53L1CBV0FY/1")
      (footprint "eagle-import:VL53L1X_STM")
      (fields (field (name "MANUFACTURER") "STM") (field (name "VOLTAGE") "3.5 V"))
      (libsource (lib "eagle-import") (part "VL53L1CBV0FY/1"))
    )
    (comp (ref "IC8")
      (value "UCC27517DBV")
      (footprint "eagle-import:DBV0005A_TI")
      (fields (field (name "MANUFACTURER") "TI") (field (name "VOLTAGE") "18.0 V"))
      (libsource (lib "eagle-import") (part "UCC27517DBV"))
    )
    (comp (ref "IC9")
      (value "SN74LVC112ADGV")
      (footprint "eagle-import:TVSOP-16_TI")
      (fields (field (name "MANUFACTURER") "TI") (field (name "VOLTAGE") "3.6 V"))
      (libsource (lib "eagle-import") (part "SN74LVC112ADGV"))
    )
    (comp (ref "IC10")
      (value "UCC27517DBV")
      (footprint "eagle-import:DBV0005A_TI")
      (fields (field (name "MANUFACTURER") "TI") (field (name "VOLTAGE") "18.0 V"))
      (libsource (lib "eagle-import") (part "UCC27517DBV"))
    )
    (comp (ref "IC12")
      (value "824001")
      (footprint "eagle-import:SOT23-6L_WE")
      (fields (field (name "MANUFACTURER") "Wuerth") (field (name "VOLTAGE") "5.0 V"))
      (libsource (lib "eagle-import") (part "824001"))
    )
    (comp (ref "IC13")
      (value "UCC27517DBV")
      (footprint "eagle-import:DBV0005A_TI")
      (fields (field (name "MANUFACTURER") "TI") (field (name "VOLTAGE") "18.0 V"))
      (libsource (lib "eagle-import") (part "UCC27517DBV"))
    )
    (comp (ref "IC14")
      (value "824001")
      (footprint "eagle-import:SOT23-6L_WE")
      (fields (field (name "MANUFACTURER") "Wuerth") (field (name "VOLTAGE") "5.0 V"))
      (libsource (lib "eagle-import") (part "824001"))
    )
    (comp (ref "IC15")
      (value "TMP1075DGK")
      (footprint "eagle-import:S-PDSO-G8_DGK_VSSOP_TI")
      (fields (field (name "MANUFACTURER") "TI") (field (name "VOLTAGE") "5.5 V"))
      (libsource (lib "eagle-import") (part "TMP1075DGK"))
    )
    (comp (ref "IC16")
      (value "824001")
      (footprint "eagle-import:SOT23-6L_WE")
      (fields (field (name "MANUFACTURER") "Wuerth") (field (name "VOLTAGE") "5.0 V"))
      (libsource (lib "eagle-import") (part "824001"))
    )
    (comp (ref "IC17")
      (value "824001")
      (footprint "eagle-import:SOT23-6L_WE")
      (fields (field (name "MANUFACTURER") "Wuerth") (field (name "VOLTAGE") "5.0 V"))
      (libsource (lib "eagle-import") (part "824001"))
    )
    (comp (ref "IC18")
      (value "824001")
      (footprint "eagle-import:SOT23-6L_WE")
      (fields (field (name "MANUFACTURER") "Wuerth") (field (name "VOLTAGE") "5.0 V"))
      (libsource (lib "eagle-import") (part "824001"))
    )
    (comp (ref "IC19")
      (value "824001")
      (footprint "eagle-import:SOT23-6L_WE")
      (fields (field (name "MANUFACTURER") "Wuerth") (field (name "VOLTAGE") "5.0 V"))
      (libsource (lib "eagle-import") (part "824001"))
    )
    (comp (ref "IC20")
      (value "824001")
      (footprint "eagle-import:SOT23-6L_WE")
      (fields (field (name "MANUFACTURER") "Wuerth") (field (name "VOLTAGE") "5.0 V"))
      (libsource (lib "eagle-import") (part "824001"))
    )
    (comp (ref "IC24")
      (value "TMP112NAIDRL")
      (footprint "eagle-import:DRL0006A_TI")
      (fields (field (name "MANUFACTURER") "TI") (field (name "VOLTAGE") "3.6 V"))
      (libsource (lib "eagle-import") (part "TMP112DRLNAI"))
    )
    (comp (ref "IC25")
      (value "BU27030NUC")
      (footprint "eagle-import:WSON008X2120_ROHM")
      (fields (field (name "MANUFACTURER") "Rohm") (field (name "VOLTAGE") "3.6 V"))
      (libsource (lib "eagle-import") (part "BU27030NUC"))
    )
    (comp (ref "IC31")
      (value "TLV71328PDBV")
      (footprint "eagle-import:R-PDSO-G5_DBV_TI")
      (fields (field (name "MANUFACTURER") "TI") (field (name "VOLTAGE") "5.5 V"))
      (libsource (lib "eagle-import") (part "TLV71328PDBV"))
    )
    (comp (ref "IC100")
      (value "SK6805-EC15")
      (footprint "eagle-import:SK6805-EC_IPIXEL")
      (fields (field (name "MANUFACTURER") "iPixel") (field (name "VOLTAGE") "5.5 V"))
      (libsource (lib "eagle-import") (part "SK6805-EC15"))
    )
    (comp (ref "IC101")
      (value "SK6805-EC15")
      (footprint "eagle-import:SK6805-EC_IPIXEL")
      (fields (field (name "MANUFACTURER") "iPixel") (field (name "VOLTAGE") "5.5 V"))
      (libsource (lib "eagle-import") (part "SK6805-EC15"))
    )
    (comp (ref "IC102")
      (value "SK6805-EC15")
      (footprint "eagle-import:SK6805-EC_IPIXEL")
      (fields (field (name "MANUFACTURER") "iPixel") (field (name "VOLTAGE") "5.5 V"))
      (libsource (lib "eagle-import") (part "SK6805-EC15"))
    )
    (comp (ref "IC103")
      (value "SK6805-EC15")
      (footprint "eagle-import:SK6805-EC_IPIXEL")
      (fields (field (name "MANUFACTURER") "iPixel") (field (name "VOLTAGE") "5.5 V"))
      (libsource (lib "eagle-import") (part "SK6805-EC15"))
    )
    (comp (ref "IC104")
      (value "SK6805-EC15")
      (footprint "eagle-import:SK6805-EC_IPIXEL")
      (fields (field (name "MANUFACTURER") "iPixel") (field (name "VOLTAGE") "5.5 V"))
      (libsource (lib "eagle-import") (part "SK6805-EC15"))
    )
    (comp (ref "IC105")
      (value "SK6805-EC15")
      (footprint "eagle-import:SK6805-EC_IPIXEL")
      (fields (field (name "MANUFACTURER") "iPixel") (field (name "VOLTAGE") "5.5 V"))
      (libsource (lib "eagle-import") (part "SK6805-EC15"))
    )
    (comp (ref "IC106")
      (value "SK6805-EC15")
      (footprint "eagle-import:SK6805-EC_IPIXEL")
      (fields (field (name "MANUFACTURER") "iPixel") (field (name "VOLTAGE") "5.5 V"))
      (libsource (lib "eagle-import") (part "SK6805-EC15"))
    )
    (comp (ref "IC107")
      (value "SK6805-EC15")
      (footprint "eagle-import:SK6805-EC_IPIXEL")
      (fields (field (name "MANUFACTURER") "iPixel") (field (name "VOLTAGE") "5.5 V"))
      (libsource (lib "eagle-import") (part "SK6805-EC15"))
    )
    (comp (ref "IC108")
      (value "SK6805-EC15")
      (footprint "eagle-import:SK6805-EC_IPIXEL")
      (fields (field (name "MANUFACTURER") "iPixel") (field (name "VOLTAGE") "5.5 V"))
      (libsource (lib "eagle-import") (part "SK6805-EC15"))
    )
    (comp (ref "IC109")
      (value "SK6805-EC15")
      (footprint "eagle-import:SK6805-EC_IPIXEL")
      (fields (field (name "MANUFACTURER") "iPixel") (field (name "VOLTAGE") "5.5 V"))
      (libsource (lib "eagle-import") (part "SK6805-EC15"))
    )
    (comp (ref "IC110")
      (value "SK6805-EC15")
      (footprint "eagle-import:SK6805-EC_IPIXEL")
      (fields (field (name "MANUFACTURER") "iPixel") (field (name "VOLTAGE") "5.5 V"))
      (libsource (lib "eagle-import") (part "SK6805-EC15"))
    )
    (comp (ref "IC111")
      (value "SK6805-EC15")
      (footprint "eagle-import:SK6805-EC_IPIXEL")
      (fields (field (name "MANUFACTURER") "iPixel") (field (name "VOLTAGE") "5.5 V"))
      (libsource (lib "eagle-import") (part "SK6805-EC15"))
    )
    (comp (ref "IC112")
      (value "SK6805-EC15")
      (footprint "eagle-import:SK6805-EC_IPIXEL")
      (fields (field (name "MANUFACTURER") "iPixel") (field (name "VOLTAGE") "5.5 V"))
      (libsource (lib "eagle-import") (part "SK6805-EC15"))
    )
    (comp (ref "IC113")
      (value "SK6805-EC15")
      (footprint "eagle-import:SK6805-EC_IPIXEL")
      (fields (field (name "MANUFACTURER") "iPixel") (field (name "VOLTAGE") "5.5 V"))
      (libsource (lib "eagle-import") (part "SK6805-EC15"))
    )
    (comp (ref "IC114")
      (value "SK6805-EC15")
      (footprint "eagle-import:SK6805-EC_IPIXEL")
      (fields (field (name "MANUFACTURER") "iPixel") (field (name "VOLTAGE") "5.5 V"))
      (libsource (lib "eagle-import") (part "SK6805-EC15"))
    )
    (comp (ref "IC115")
      (value "SK6805-EC15")
      (footprint "eagle-import:SK6805-EC_IPIXEL")
      (fields (field (name "MANUFACTURER") "iPixel") (field (name "VOLTAGE") "5.5 V"))
      (libsource (lib "eagle-import") (part "SK6805-EC15"))
    )
    (comp (ref "IC116")
      (value "SK6805-EC15")
      (footprint "eagle-import:SK6805-EC_IPIXEL")
      (fields (field (name "MANUFACTURER") "iPixel") (field (name "VOLTAGE") "5.5 V"))
      (libsource (lib "eagle-import") (part "SK6805-EC15"))
    )
    (comp (ref "IC117")
      (value "SK6805-EC15")
      (footprint "eagle-import:SK6805-EC_IPIXEL")
      (fields (field (name "MANUFACTURER") "iPixel") (field (name "VOLTAGE") "5.5 V"))
      (libsource (lib "eagle-import") (part "SK6805-EC15"))
    )
    (comp (ref "IC118")
      (value "SK6805-EC15")
      (footprint "eagle-import:SK6805-EC_IPIXEL")
      (fields (field (name "MANUFACTURER") "iPixel") (field (name "VOLTAGE") "5.5 V"))
      (libsource (lib "eagle-import") (part "SK6805-EC15"))
    )
    (comp (ref "IC119")
      (value "SK6805-EC15")
      (footprint "eagle-import:SK6805-EC_IPIXEL")
      (fields (field (name "MANUFACTURER") "iPixel") (field (name "VOLTAGE") "5.5 V"))
      (libsource (lib "eagle-import") (part "SK6805-EC15"))
    )
    (comp (ref "IC120")
      (value "SK6805-EC15")
      (footprint "eagle-import:SK6805-EC_IPIXEL")
      (fields (field (name "MANUFACTURER") "iPixel") (field (name "VOLTAGE") "5.5 V"))
      (libsource (lib "eagle-import") (part "SK6805-EC15"))
    )
    (comp (ref "IC121")
      (value "SK6805-EC15")
      (footprint "eagle-import:SK6805-EC_IPIXEL")
      (fields (field (name "MANUFACTURER") "iPixel") (field (name "VOLTAGE") "5.5 V"))
      (libsource (lib "eagle-import") (part "SK6805-EC15"))
    )
    (comp (ref "IC122")
      (value "SK6805-EC15")
      (footprint "eagle-import:SK6805-EC_IPIXEL")
      (fields (field (name "MANUFACTURER") "iPixel") (field (name "VOLTAGE") "5.5 V"))
      (libsource (lib "eagle-import") (part "SK6805-EC15"))
    )
    (comp (ref "IC123")
      (value "SK6805-EC15")
      (footprint "eagle-import:SK6805-EC_IPIXEL")
      (fields (field (name "MANUFACTURER") "iPixel") (field (name "VOLTAGE") "5.5 V"))
      (libsource (lib "eagle-import") (part "SK6805-EC15"))
    )
    (comp (ref "IC124")
      (value "SK6805-EC15")
      (footprint "eagle-import:SK6805-EC_IPIXEL")
      (fields (field (name "MANUFACTURER") "iPixel") (field (name "VOLTAGE") "5.5 V"))
      (libsource (lib "eagle-import") (part "SK6805-EC15"))
    )
    (comp (ref "IC125")
      (value "SK6805-EC15")
      (footprint "eagle-import:SK6805-EC_IPIXEL")
      (fields (field (name "MANUFACTURER") "iPixel") (field (name "VOLTAGE") "5.5 V"))
      (libsource (lib "eagle-import") (part "SK6805-EC15"))
    )
    (comp (ref "IC126")
      (value "SK6805-EC15")
      (footprint "eagle-import:SK6805-EC_IPIXEL")
      (fields (field (name "MANUFACTURER") "iPixel") (field (name "VOLTAGE") "5.5 V"))
      (libsource (lib "eagle-import") (part "SK6805-EC15"))
    )
    (comp (ref "IC127")
      (value "SK6805-EC15")
      (footprint "eagle-import:SK6805-EC_IPIXEL")
      (fields (field (name "MANUFACTURER") "iPixel") (field (name "VOLTAGE") "5.5 V"))
      (libsource (lib "eagle-import") (part "SK6805-EC15"))
    )
    (comp (ref "IC128")
      (value "SK6805-EC15")
      (footprint "eagle-import:SK6805-EC_IPIXEL")
      (fields (field (name "MANUFACTURER") "iPixel") (field (name "VOLTAGE") "5.5 V"))
      (libsource (lib "eagle-import") (part "SK6805-EC15"))
    )
    (comp (ref "IC129")
      (value "SK6805-EC15")
      (footprint "eagle-import:SK6805-EC_IPIXEL")
      (fields (field (name "MANUFACTURER") "iPixel") (field (name "VOLTAGE") "5.5 V"))
      (libsource (lib "eagle-import") (part "SK6805-EC15"))
    )
    (comp (ref "IC130")
      (value "SK6805-EC15")
      (footprint "eagle-import:SK6805-EC_IPIXEL")
      (fields (field (name "MANUFACTURER") "iPixel") (field (name "VOLTAGE") "5.5 V"))
      (libsource (lib "eagle-import") (part "SK6805-EC15"))
    )
    (comp (ref "IC131")
      (value "SK6805-EC15")
      (footprint "eagle-import:SK6805-EC_IPIXEL")
      (fields (field (name "MANUFACTURER") "iPixel") (field (name "VOLTAGE") "5.5 V"))
      (libsource (lib "eagle-import") (part "SK6805-EC15"))
    )
    (comp (ref "IC132")
      (value "SK6805-EC15")
      (footprint "eagle-import:SK6805-EC_IPIXEL")
      (fields (field (name "MANUFACTURER") "iPixel") (field (name "VOLTAGE") "5.5 V"))
      (libsource (lib "eagle-import") (part "SK6805-EC15"))
    )
    (comp (ref "IC133")
      (value "SK6805-EC15")
      (footprint "eagle-import:SK6805-EC_IPIXEL")
      (fields (field (name "MANUFACTURER") "iPixel") (field (name "VOLTAGE") "5.5 V"))
      (libsource (lib "eagle-import") (part "SK6805-EC15"))
    )
    (comp (ref "IC134")
      (value "SK6805-EC15")
      (footprint "eagle-import:SK6805-EC_IPIXEL")
      (fields (field (name "MANUFACTURER") "iPixel") (field (name "VOLTAGE") "5.5 V"))
      (libsource (lib "eagle-import") (part "SK6805-EC15"))
    )
    (comp (ref "IC135")
      (value "SK6805-EC15")
      (footprint "eagle-import:SK6805-EC_IPIXEL")
      (fields (field (name "MANUFACTURER") "iPixel") (field (name "VOLTAGE") "5.5 V"))
      (libsource (lib "eagle-import") (part "SK6805-EC15"))
    )
    (comp (ref "IC136")
      (value "SK6805-EC15")
      (footprint "eagle-import:SK6805-EC_IPIXEL")
      (fields (field (name "MANUFACTURER") "iPixel") (field (name "VOLTAGE") "5.5 V"))
      (libsource (lib "eagle-import") (part "SK6805-EC15"))
    )
    (comp (ref "IC137")
      (value "SK6805-EC15")
      (footprint "eagle-import:SK6805-EC_IPIXEL")
      (fields (field (name "MANUFACTURER") "iPixel") (field (name "VOLTAGE") "5.5 V"))
      (libsource (lib "eagle-import") (part "SK6805-EC15"))
    )
    (comp (ref "IC138")
      (value "SK6805-EC15")
      (footprint "eagle-import:SK6805-EC_IPIXEL")
      (fields (field (name "MANUFACTURER") "iPixel") (field (name "VOLTAGE") "5.5 V"))
      (libsource (lib "eagle-import") (part "SK6805-EC15"))
    )
    (comp (ref "IC139")
      (value "SK6805-EC15")
      (footprint "eagle-import:SK6805-EC_IPIXEL")
      (fields (field (name "MANUFACTURER") "iPixel") (field (name "VOLTAGE") "5.5 V"))
      (libsource (lib "eagle-import") (part "SK6805-EC15"))
    )
    (comp (ref "IC140")
      (value "SK6805-EC15")
      (footprint "eagle-import:SK6805-EC_IPIXEL")
      (fields (field (name "MANUFACTURER") "iPixel") (field (name "VOLTAGE") "5.5 V"))
      (libsource (lib "eagle-import") (part "SK6805-EC15"))
    )
    (comp (ref "IC141")
      (value "SK6805-EC15")
      (footprint "eagle-import:SK6805-EC_IPIXEL")
      (fields (field (name "MANUFACTURER") "iPixel") (field (name "VOLTAGE") "5.5 V"))
      (libsource (lib "eagle-import") (part "SK6805-EC15"))
    )
    (comp (ref "IC142")
      (value "SK6805-EC15")
      (footprint "eagle-import:SK6805-EC_IPIXEL")
      (fields (field (name "MANUFACTURER") "iPixel") (field (name "VOLTAGE") "5.5 V"))
      (libsource (lib "eagle-import") (part "SK6805-EC15"))
    )
    (comp (ref "IC143")
      (value "SK6805-EC15")
      (footprint "eagle-import:SK6805-EC_IPIXEL")
      (fields (field (name "MANUFACTURER") "iPixel") (field (name "VOLTAGE") "5.5 V"))
      (libsource (lib "eagle-import") (part "SK6805-EC15"))
    )
    (comp (ref "IC144")
      (value "SK6805-EC15")
      (footprint "eagle-import:SK6805-EC_IPIXEL")
      (fields (field (name "MANUFACTURER") "iPixel") (field (name "VOLTAGE") "5.5 V"))
      (libsource (lib "eagle-import") (part "SK6805-EC15"))
    )
    (comp (ref "IC145")
      (value "SK6805-EC15")
      (footprint "eagle-import:SK6805-EC_IPIXEL")
      (fields (field (name "MANUFACTURER") "iPixel") (field (name "VOLTAGE") "5.5 V"))
      (libsource (lib "eagle-import") (part "SK6805-EC15"))
    )
    (comp (ref "IC146")
      (value "SK6805-EC15")
      (footprint "eagle-import:SK6805-EC_IPIXEL")
      (fields (field (name "MANUFACTURER") "iPixel") (field (name "VOLTAGE") "5.5 V"))
      (libsource (lib "eagle-import") (part "SK6805-EC15"))
    )
    (comp (ref "IC147")
      (value "SK6805-EC15")
      (footprint "eagle-import:SK6805-EC_IPIXEL")
      (fields (field (name "MANUFACTURER") "iPixel") (field (name "VOLTAGE") "5.5 V"))
      (libsource (lib "eagle-import") (part "SK6805-EC15"))
    )
    (comp (ref "IC148")
      (value "SK6805-EC15")
      (footprint "eagle-import:SK6805-EC_IPIXEL")
      (fields (field (name "MANUFACTURER") "iPixel") (field (name "VOLTAGE") "5.5 V"))
      (libsource (lib "eagle-import") (part "SK6805-EC15"))
    )
    (comp (ref "IC149")
      (value "SK6805-EC15")
      (footprint "eagle-import:SK6805-EC_IPIXEL")
      (fields (field (name "MANUFACTURER") "iPixel") (field (name "VOLTAGE") "5.5 V"))
      (libsource (lib "eagle-import") (part "SK6805-EC15"))
    )
    (comp (ref "IC150")
      (value "SK6805-EC15")
      (footprint "eagle-import:SK6805-EC_IPIXEL")
      (fields (field (name "MANUFACTURER") "iPixel") (field (name "VOLTAGE") "5.5 V"))
      (libsource (lib "eagle-import") (part "SK6805-EC15"))
    )
    (comp (ref "IC151")
      (value "SK6805-EC15")
      (footprint "eagle-import:SK6805-EC_IPIXEL")
      (fields (field (name "MANUFACTURER") "iPixel") (field (name "VOLTAGE") "5.5 V"))
      (libsource (lib "eagle-import") (part "SK6805-EC15"))
    )
    (comp (ref "IC152")
      (value "SK6805-EC15")
      (footprint "eagle-import:SK6805-EC_IPIXEL")
      (fields (field (name "MANUFACTURER") "iPixel") (field (name "VOLTAGE") "5.5 V"))
      (libsource (lib "eagle-import") (part "SK6805-EC15"))
    )
    (comp (ref "IC153")
      (value "SK6805-EC15")
      (footprint "eagle-import:SK6805-EC_IPIXEL")
      (fields (field (name "MANUFACTURER") "iPixel") (field (name "VOLTAGE") "5.5 V"))
      (libsource (lib "eagle-import") (part "SK6805-EC15"))
    )
    (comp (ref "IC154")
      (value "SK6805-EC15")
      (footprint "eagle-import:SK6805-EC_IPIXEL")
      (fields (field (name "MANUFACTURER") "iPixel") (field (name "VOLTAGE") "5.5 V"))
      (libsource (lib "eagle-import") (part "SK6805-EC15"))
    )
    (comp (ref "IC155")
      (value "SK6805-EC15")
      (footprint "eagle-import:SK6805-EC_IPIXEL")
      (fields (field (name "MANUFACTURER") "iPixel") (field (name "VOLTAGE") "5.5 V"))
      (libsource (lib "eagle-import") (part "SK6805-EC15"))
    )
    (comp (ref "IC156")
      (value "SK6805-EC15")
      (footprint "eagle-import:SK6805-EC_IPIXEL")
      (fields (field (name "MANUFACTURER") "iPixel") (field (name "VOLTAGE") "5.5 V"))
      (libsource (lib "eagle-import") (part "SK6805-EC15"))
    )
    (comp (ref "IC157")
      (value "SK6805-EC15")
      (footprint "eagle-import:SK6805-EC_IPIXEL")
      (fields (field (name "MANUFACTURER") "iPixel") (field (name "VOLTAGE") "5.5 V"))
      (libsource (lib "eagle-import") (part "SK6805-EC15"))
    )
    (comp (ref "IC158")
      (value "SK6805-EC15")
      (footprint "eagle-import:SK6805-EC_IPIXEL")
      (fields (field (name "MANUFACTURER") "iPixel") (field (name "VOLTAGE") "5.5 V"))
      (libsource (lib "eagle-import") (part "SK6805-EC15"))
    )
    (comp (ref "IC159")
      (value "SK6805-EC15")
      (footprint "eagle-import:SK6805-EC_IPIXEL")
      (fields (field (name "MANUFACTURER") "iPixel") (field (name "VOLTAGE") "5.5 V"))
      (libsource (lib "eagle-import") (part "SK6805-EC15"))
    )
    (comp (ref "IC160")
      (value "SK6805-EC15")
      (footprint "eagle-import:SK6805-EC_IPIXEL")
      (fields (field (name "MANUFACTURER") "iPixel") (field (name "VOLTAGE") "5.5 V"))
      (libsource (lib "eagle-import") (part "SK6805-EC15"))
    )
    (comp (ref "IC161")
      (value "SK6805-EC15")
      (footprint "eagle-import:SK6805-EC_IPIXEL")
      (fields (field (name "MANUFACTURER") "iPixel") (field (name "VOLTAGE") "5.5 V"))
      (libsource (lib "eagle-import") (part "SK6805-EC15"))
    )
    (comp (ref "IC162")
      (value "SK6805-EC15")
      (footprint "eagle-import:SK6805-EC_IPIXEL")
      (fields (field (name "MANUFACTURER") "iPixel") (field (name "VOLTAGE") "5.5 V"))
      (libsource (lib "eagle-import") (part "SK6805-EC15"))
    )
    (comp (ref "IC163")
      (value "SK6805-EC15")
      (footprint "eagle-import:SK6805-EC_IPIXEL")
      (fields (field (name "MANUFACTURER") "iPixel") (field (name "VOLTAGE") "5.5 V"))
      (libsource (lib "eagle-import") (part "SK6805-EC15"))
    )
    (comp (ref "IC164")
      (value "SK6805-EC15")
      (footprint "eagle-import:SK6805-EC_IPIXEL")
      (fields (field (name "MANUFACTURER") "iPixel") (field (name "VOLTAGE") "5.5 V"))
      (libsource (lib "eagle-import") (part "SK6805-EC15"))
    )
    (comp (ref "IC165")
      (value "SK6805-EC15")
      (footprint "eagle-import:SK6805-EC_IPIXEL")
      (fields (field (name "MANUFACTURER") "iPixel") (field (name "VOLTAGE") "5.5 V"))
      (libsource (lib "eagle-import") (part "SK6805-EC15"))
    )
    (comp (ref "IC166")
      (value "SK6805-EC15")
      (footprint "eagle-import:SK6805-EC_IPIXEL")
      (fields (field (name "MANUFACTURER") "iPixel") (field (name "VOLTAGE") "5.5 V"))
      (libsource (lib "eagle-import") (part "SK6805-EC15"))
    )
    (comp (ref "IC167")
      (value "SK6805-EC15")
      (footprint "eagle-import:SK6805-EC_IPIXEL")
      (fields (field (name "MANUFACTURER") "iPixel") (field (name "VOLTAGE") "5.5 V"))
      (libsource (lib "eagle-import") (part "SK6805-EC15"))
    )
    (comp (ref "IC168")
      (value "SK6805-EC15")
      (footprint "eagle-import:SK6805-EC_IPIXEL")
      (fields (field (name "MANUFACTURER") "iPixel") (field (name "VOLTAGE") "5.5 V"))
      (libsource (lib "eagle-import") (part "SK6805-EC15"))
    )
    (comp (ref "IC169")
      (value "SK6805-EC15")
      (footprint "eagle-import:SK6805-EC_IPIXEL")
      (fields (field (name "MANUFACTURER") "iPixel") (field (name "VOLTAGE") "5.5 V"))
      (libsource (lib "eagle-import") (part "SK6805-EC15"))
    )
    (comp (ref "IC170")
      (value "SK6805-EC15")
      (footprint "eagle-import:SK6805-EC_IPIXEL")
      (fields (field (name "MANUFACTURER") "iPixel") (field (name "VOLTAGE") "5.5 V"))
      (libsource (lib "eagle-import") (part "SK6805-EC15"))
    )
    (comp (ref "IC171")
      (value "SK6805-EC15")
      (footprint "eagle-import:SK6805-EC_IPIXEL")
      (fields (field (name "MANUFACTURER") "iPixel") (field (name "VOLTAGE") "5.5 V"))
      (libsource (lib "eagle-import") (part "SK6805-EC15"))
    )
    (comp (ref "IC172")
      (value "SK6805-EC15")
      (footprint "eagle-import:SK6805-EC_IPIXEL")
      (fields (field (name "MANUFACTURER") "iPixel") (field (name "VOLTAGE") "5.5 V"))
      (libsource (lib "eagle-import") (part "SK6805-EC15"))
    )
    (comp (ref "IC173")
      (value "SK6805-EC15")
      (footprint "eagle-import:SK6805-EC_IPIXEL")
      (fields (field (name "MANUFACTURER") "iPixel") (field (name "VOLTAGE") "5.5 V"))
      (libsource (lib "eagle-import") (part "SK6805-EC15"))
    )
    (comp (ref "IC174")
      (value "SK6805-EC15")
      (footprint "eagle-import:SK6805-EC_IPIXEL")
      (fields (field (name "MANUFACTURER") "iPixel") (field (name "VOLTAGE") "5.5 V"))
      (libsource (lib "eagle-import") (part "SK6805-EC15"))
    )
    (comp (ref "IC175")
      (value "SK6805-EC15")
      (footprint "eagle-import:SK6805-EC_IPIXEL")
      (fields (field (name "MANUFACTURER") "iPixel") (field (name "VOLTAGE") "5.5 V"))
      (libsource (lib "eagle-import") (part "SK6805-EC15"))
    )
    (comp (ref "IC176")
      (value "SK6805-EC15")
      (footprint "eagle-import:SK6805-EC_IPIXEL")
      (fields (field (name "MANUFACTURER") "iPixel") (field (name "VOLTAGE") "5.5 V"))
      (libsource (lib "eagle-import") (part "SK6805-EC15"))
    )
    (comp (ref "IC177")
      (value "SK6805-EC15")
      (footprint "eagle-import:SK6805-EC_IPIXEL")
      (fields (field (name "MANUFACTURER") "iPixel") (field (name "VOLTAGE") "5.5 V"))
      (libsource (lib "eagle-import") (part "SK6805-EC15"))
    )
    (comp (ref "IC178")
      (value "SK6805-EC15")
      (footprint "eagle-import:SK6805-EC_IPIXEL")
      (fields (field (name "MANUFACTURER") "iPixel") (field (name "VOLTAGE") "5.5 V"))
      (libsource (lib "eagle-import") (part "SK6805-EC15"))
    )
    (comp (ref "IC179")
      (value "SK6805-EC15")
      (footprint "eagle-import:SK6805-EC_IPIXEL")
      (fields (field (name "MANUFACTURER") "iPixel") (field (name "VOLTAGE") "5.5 V"))
      (libsource (lib "eagle-import") (part "SK6805-EC15"))
    )
    (comp (ref "IC180")
      (value "SK6805-EC15")
      (footprint "eagle-import:SK6805-EC_IPIXEL")
      (fields (field (name "MANUFACTURER") "iPixel") (field (name "VOLTAGE") "5.5 V"))
      (libsource (lib "eagle-import") (part "SK6805-EC15"))
    )
    (comp (ref "IC181")
      (value "SK6805-EC15")
      (footprint "eagle-import:SK6805-EC_IPIXEL")
      (fields (field (name "MANUFACTURER") "iPixel") (field (name "VOLTAGE") "5.5 V"))
      (libsource (lib "eagle-import") (part "SK6805-EC15"))
    )
    (comp (ref "IC182")
      (value "SK6805-EC15")
      (footprint "eagle-import:SK6805-EC_IPIXEL")
      (fields (field (name "MANUFACTURER") "iPixel") (field (name "VOLTAGE") "5.5 V"))
      (libsource (lib "eagle-import") (part "SK6805-EC15"))
    )
    (comp (ref "IC183")
      (value "SK6805-EC15")
      (footprint "eagle-import:SK6805-EC_IPIXEL")
      (fields (field (name "MANUFACTURER") "iPixel") (field (name "VOLTAGE") "5.5 V"))
      (libsource (lib "eagle-import") (part "SK6805-EC15"))
    )
    (comp (ref "IC184")
      (value "SK6805-EC15")
      (footprint "eagle-import:SK6805-EC_IPIXEL")
      (fields (field (name "MANUFACTURER") "iPixel") (field (name "VOLTAGE") "5.5 V"))
      (libsource (lib "eagle-import") (part "SK6805-EC15"))
    )
    (comp (ref "IC185")
      (value "SK6805-EC15")
      (footprint "eagle-import:SK6805-EC_IPIXEL")
      (fields (field (name "MANUFACTURER") "iPixel") (field (name "VOLTAGE") "5.5 V"))
      (libsource (lib "eagle-import") (part "SK6805-EC15"))
    )
    (comp (ref "IC186")
      (value "SK6805-EC15")
      (footprint "eagle-import:SK6805-EC_IPIXEL")
      (fields (field (name "MANUFACTURER") "iPixel") (field (name "VOLTAGE") "5.5 V"))
      (libsource (lib "eagle-import") (part "SK6805-EC15"))
    )
    (comp (ref "IC187")
      (value "SK6805-EC15")
      (footprint "eagle-import:SK6805-EC_IPIXEL")
      (fields (field (name "MANUFACTURER") "iPixel") (field (name "VOLTAGE") "5.5 V"))
      (libsource (lib "eagle-import") (part "SK6805-EC15"))
    )
    (comp (ref "IC188")
      (value "SK6805-EC15")
      (footprint "eagle-import:SK6805-EC_IPIXEL")
      (fields (field (name "MANUFACTURER") "iPixel") (field (name "VOLTAGE") "5.5 V"))
      (libsource (lib "eagle-import") (part "SK6805-EC15"))
    )
    (comp (ref "IC189")
      (value "SK6805-EC15")
      (footprint "eagle-import:SK6805-EC_IPIXEL")
      (fields (field (name "MANUFACTURER") "iPixel") (field (name "VOLTAGE") "5.5 V"))
      (libsource (lib "eagle-import") (part "SK6805-EC15"))
    )
    (comp (ref "IC190")
      (value "SK6805-EC15")
      (footprint "eagle-import:SK6805-EC_IPIXEL")
      (fields (field (name "MANUFACTURER") "iPixel") (field (name "VOLTAGE") "5.5 V"))
      (libsource (lib "eagle-import") (part "SK6805-EC15"))
    )
    (comp (ref "IC191")
      (value "SK6805-EC15")
      (footprint "eagle-import:SK6805-EC_IPIXEL")
      (fields (field (name "MANUFACTURER") "iPixel") (field (name "VOLTAGE") "5.5 V"))
      (libsource (lib "eagle-import") (part "SK6805-EC15"))
    )
    (comp (ref "IC192")
      (value "SK6805-EC15")
      (footprint "eagle-import:SK6805-EC_IPIXEL")
      (fields (field (name "MANUFACTURER") "iPixel") (field (name "VOLTAGE") "5.5 V"))
      (libsource (lib "eagle-import") (part "SK6805-EC15"))
    )
    (comp (ref "IC193")
      (value "SK6805-EC15")
      (footprint "eagle-import:SK6805-EC_IPIXEL")
      (fields (field (name "MANUFACTURER") "iPixel") (field (name "VOLTAGE") "5.5 V"))
      (libsource (lib "eagle-import") (part "SK6805-EC15"))
    )
    (comp (ref "IC194")
      (value "SK6805-EC15")
      (footprint "eagle-import:SK6805-EC_IPIXEL")
      (fields (field (name "MANUFACTURER") "iPixel") (field (name "VOLTAGE") "5.5 V"))
      (libsource (lib "eagle-import") (part "SK6805-EC15"))
    )
    (comp (ref "IC195")
      (value "SK6805-EC15")
      (footprint "eagle-import:SK6805-EC_IPIXEL")
      (fields (field (name "MANUFACTURER") "iPixel") (field (name "VOLTAGE") "5.5 V"))
      (libsource (lib "eagle-import") (part "SK6805-EC15"))
    )
    (comp (ref "IC196")
      (value "SK6805-EC15")
      (footprint "eagle-import:SK6805-EC_IPIXEL")
      (fields (field (name "MANUFACTURER") "iPixel") (field (name "VOLTAGE") "5.5 V"))
      (libsource (lib "eagle-import") (part "SK6805-EC15"))
    )
    (comp (ref "IC197")
      (value "SK6805-EC15")
      (footprint "eagle-import:SK6805-EC_IPIXEL")
      (fields (field (name "MANUFACTURER") "iPixel") (field (name "VOLTAGE") "5.5 V"))
      (libsource (lib "eagle-import") (part "SK6805-EC15"))
    )
    (comp (ref "IC198")
      (value "SK6805-EC15")
      (footprint "eagle-import:SK6805-EC_IPIXEL")
      (fields (field (name "MANUFACTURER") "iPixel") (field (name "VOLTAGE") "5.5 V"))
      (libsource (lib "eagle-import") (part "SK6805-EC15"))
    )
    (comp (ref "IC199")
      (value "SK6805-EC15")
      (footprint "eagle-import:SK6805-EC_IPIXEL")
      (fields (field (name "MANUFACTURER") "iPixel") (field (name "VOLTAGE") "5.5 V"))
      (libsource (lib "eagle-import") (part "SK6805-EC15"))
    )
    (comp (ref "IC200")
      (value "SK6805-EC15")
      (footprint "eagle-import:SK6805-EC_IPIXEL")
      (fields (field (name "MANUFACTURER") "iPixel") (field (name "VOLTAGE") "5.5 V"))
      (libsource (lib "eagle-import") (part "SK6805-EC15"))
    )
    (comp (ref "IC201")
      (value "SK6805-EC15")
      (footprint "eagle-import:SK6805-EC_IPIXEL")
      (fields (field (name "MANUFACTURER") "iPixel") (field (name "VOLTAGE") "5.5 V"))
      (libsource (lib "eagle-import") (part "SK6805-EC15"))
    )
    (comp (ref "IC202")
      (value "SK6805-EC15")
      (footprint "eagle-import:SK6805-EC_IPIXEL")
      (fields (field (name "MANUFACTURER") "iPixel") (field (name "VOLTAGE") "5.5 V"))
      (libsource (lib "eagle-import") (part "SK6805-EC15"))
    )
    (comp (ref "IC203")
      (value "SK6805-EC15")
      (footprint "eagle-import:SK6805-EC_IPIXEL")
      (fields (field (name "MANUFACTURER") "iPixel") (field (name "VOLTAGE") "5.5 V"))
      (libsource (lib "eagle-import") (part "SK6805-EC15"))
    )
    (comp (ref "IC204")
      (value "SK6805-EC15")
      (footprint "eagle-import:SK6805-EC_IPIXEL")
      (fields (field (name "MANUFACTURER") "iPixel") (field (name "VOLTAGE") "5.5 V"))
      (libsource (lib "eagle-import") (part "SK6805-EC15"))
    )
    (comp (ref "IC205")
      (value "SK6805-EC15")
      (footprint "eagle-import:SK6805-EC_IPIXEL")
      (fields (field (name "MANUFACTURER") "iPixel") (field (name "VOLTAGE") "5.5 V"))
      (libsource (lib "eagle-import") (part "SK6805-EC15"))
    )
    (comp (ref "IC206")
      (value "SK6805-EC15")
      (footprint "eagle-import:SK6805-EC_IPIXEL")
      (fields (field (name "MANUFACTURER") "iPixel") (field (name "VOLTAGE") "5.5 V"))
      (libsource (lib "eagle-import") (part "SK6805-EC15"))
    )
    (comp (ref "IC207")
      (value "SK6805-EC15")
      (footprint "eagle-import:SK6805-EC_IPIXEL")
      (fields (field (name "MANUFACTURER") "iPixel") (field (name "VOLTAGE") "5.5 V"))
      (libsource (lib "eagle-import") (part "SK6805-EC15"))
    )
    (comp (ref "IC208")
      (value "SK6805-EC15")
      (footprint "eagle-import:SK6805-EC_IPIXEL")
      (fields (field (name "MANUFACTURER") "iPixel") (field (name "VOLTAGE") "5.5 V"))
      (libsource (lib "eagle-import") (part "SK6805-EC15"))
    )
    (comp (ref "IC209")
      (value "SK6805-EC15")
      (footprint "eagle-import:SK6805-EC_IPIXEL")
      (fields (field (name "MANUFACTURER") "iPixel") (field (name "VOLTAGE") "5.5 V"))
      (libsource (lib "eagle-import") (part "SK6805-EC15"))
    )
    (comp (ref "IC210")
      (value "SK6805-EC15")
      (footprint "eagle-import:SK6805-EC_IPIXEL")
      (fields (field (name "MANUFACTURER") "iPixel") (field (name "VOLTAGE") "5.5 V"))
      (libsource (lib "eagle-import") (part "SK6805-EC15"))
    )
    (comp (ref "IC211")
      (value "SK6805-EC15")
      (footprint "eagle-import:SK6805-EC_IPIXEL")
      (fields (field (name "MANUFACTURER") "iPixel") (field (name "VOLTAGE") "5.5 V"))
      (libsource (lib "eagle-import") (part "SK6805-EC15"))
    )
    (comp (ref "IC212")
      (value "SK6805-EC15")
      (footprint "eagle-import:SK6805-EC_IPIXEL")
      (fields (field (name "MANUFACTURER") "iPixel") (field (name "VOLTAGE") "5.5 V"))
      (libsource (lib "eagle-import") (part "SK6805-EC15"))
    )
    (comp (ref "IC213")
      (value "SK6805-EC15")
      (footprint "eagle-import:SK6805-EC_IPIXEL")
      (fields (field (name "MANUFACTURER") "iPixel") (field (name "VOLTAGE") "5.5 V"))
      (libsource (lib "eagle-import") (part "SK6805-EC15"))
    )
    (comp (ref "IC214")
      (value "SK6805-EC15")
      (footprint "eagle-import:SK6805-EC_IPIXEL")
      (fields (field (name "MANUFACTURER") "iPixel") (field (name "VOLTAGE") "5.5 V"))
      (libsource (lib "eagle-import") (part "SK6805-EC15"))
    )
    (comp (ref "IC215")
      (value "SK6805-EC15")
      (footprint "eagle-import:SK6805-EC_IPIXEL")
      (fields (field (name "MANUFACTURER") "iPixel") (field (name "VOLTAGE") "5.5 V"))
      (libsource (lib "eagle-import") (part "SK6805-EC15"))
    )
    (comp (ref "IC216")
      (value "SK6805-EC15")
      (footprint "eagle-import:SK6805-EC_IPIXEL")
      (fields (field (name "MANUFACTURER") "iPixel") (field (name "VOLTAGE") "5.5 V"))
      (libsource (lib "eagle-import") (part "SK6805-EC15"))
    )
    (comp (ref "IC217")
      (value "SK6805-EC15")
      (footprint "eagle-import:SK6805-EC_IPIXEL")
      (fields (field (name "MANUFACTURER") "iPixel") (field (name "VOLTAGE") "5.5 V"))
      (libsource (lib "eagle-import") (part "SK6805-EC15"))
    )
    (comp (ref "IC218")
      (value "SK6805-EC15")
      (footprint "eagle-import:SK6805-EC_IPIXEL")
      (fields (field (name "MANUFACTURER") "iPixel") (field (name "VOLTAGE") "5.5 V"))
      (libsource (lib "eagle-import") (part "SK6805-EC15"))
    )
    (comp (ref "IC219")
      (value "SK6805-EC15")
      (footprint "eagle-import:SK6805-EC_IPIXEL")
      (fields (field (name "MANUFACTURER") "iPixel") (field (name "VOLTAGE") "5.5 V"))
      (libsource (lib "eagle-import") (part "SK6805-EC15"))
    )
    (comp (ref "IC220")
      (value "SK6805-EC15")
      (footprint "eagle-import:SK6805-EC_IPIXEL")
      (fields (field (name "MANUFACTURER") "iPixel") (field (name "VOLTAGE") "5.5 V"))
      (libsource (lib "eagle-import") (part "SK6805-EC15"))
    )
    (comp (ref "IC221")
      (value "SK6805-EC15")
      (footprint "eagle-import:SK6805-EC_IPIXEL")
      (fields (field (name "MANUFACTURER") "iPixel") (field (name "VOLTAGE") "5.5 V"))
      (libsource (lib "eagle-import") (part "SK6805-EC15"))
    )
    (comp (ref "IC222")
      (value "SK6805-EC15")
      (footprint "eagle-import:SK6805-EC_IPIXEL")
      (fields (field (name "MANUFACTURER") "iPixel") (field (name "VOLTAGE") "5.5 V"))
      (libsource (lib "eagle-import") (part "SK6805-EC15"))
    )
    (comp (ref "IC223")
      (value "SK6805-EC15")
      (footprint "eagle-import:SK6805-EC_IPIXEL")
      (fields (field (name "MANUFACTURER") "iPixel") (field (name "VOLTAGE") "5.5 V"))
      (libsource (lib "eagle-import") (part "SK6805-EC15"))
    )
    (comp (ref "IC224")
      (value "SK6805-EC15")
      (footprint "eagle-import:SK6805-EC_IPIXEL")
      (fields (field (name "MANUFACTURER") "iPixel") (field (name "VOLTAGE") "5.5 V"))
      (libsource (lib "eagle-import") (part "SK6805-EC15"))
    )
    (comp (ref "IC225")
      (value "SK6805-EC15")
      (footprint "eagle-import:SK6805-EC_IPIXEL")
      (fields (field (name "MANUFACTURER") "iPixel") (field (name "VOLTAGE") "5.5 V"))
      (libsource (lib "eagle-import") (part "SK6805-EC15"))
    )
    (comp (ref "IC226")
      (value "SK6805-EC15")
      (footprint "eagle-import:SK6805-EC_IPIXEL")
      (fields (field (name "MANUFACTURER") "iPixel") (field (name "VOLTAGE") "5.5 V"))
      (libsource (lib "eagle-import") (part "SK6805-EC15"))
    )
    (comp (ref "IC227")
      (value "SK6805-EC15")
      (footprint "eagle-import:SK6805-EC_IPIXEL")
      (fields (field (name "MANUFACTURER") "iPixel") (field (name "VOLTAGE") "5.5 V"))
      (libsource (lib "eagle-import") (part "SK6805-EC15"))
    )
    (comp (ref "IC228")
      (value "SK6805-EC15")
      (footprint "eagle-import:SK6805-EC_IPIXEL")
      (fields (field (name "MANUFACTURER") "iPixel") (field (name "VOLTAGE") "5.5 V"))
      (libsource (lib "eagle-import") (part "SK6805-EC15"))
    )
    (comp (ref "IC229")
      (value "SK6805-EC15")
      (footprint "eagle-import:SK6805-EC_IPIXEL")
      (fields (field (name "MANUFACTURER") "iPixel") (field (name "VOLTAGE") "5.5 V"))
      (libsource (lib "eagle-import") (part "SK6805-EC15"))
    )
    (comp (ref "IC230")
      (value "SK6805-EC15")
      (footprint "eagle-import:SK6805-EC_IPIXEL")
      (fields (field (name "MANUFACTURER") "iPixel") (field (name "VOLTAGE") "5.5 V"))
      (libsource (lib "eagle-import") (part "SK6805-EC15"))
    )
    (comp (ref "IC231")
      (value "SK6805-EC15")
      (footprint "eagle-import:SK6805-EC_IPIXEL")
      (fields (field (name "MANUFACTURER") "iPixel") (field (name "VOLTAGE") "5.5 V"))
      (libsource (lib "eagle-import") (part "SK6805-EC15"))
    )
    (comp (ref "IC232")
      (value "SK6805-EC15")
      (footprint "eagle-import:SK6805-EC_IPIXEL")
      (fields (field (name "MANUFACTURER") "iPixel") (field (name "VOLTAGE") "5.5 V"))
      (libsource (lib "eagle-import") (part "SK6805-EC15"))
    )
    (comp (ref "IC233")
      (value "SK6805-EC15")
      (footprint "eagle-import:SK6805-EC_IPIXEL")
      (fields (field (name "MANUFACTURER") "iPixel") (field (name "VOLTAGE") "5.5 V"))
      (libsource (lib "eagle-import") (part "SK6805-EC15"))
    )
    (comp (ref "IC234")
      (value "SK6805-EC15")
      (footprint "eagle-import:SK6805-EC_IPIXEL")
      (fields (field (name "MANUFACTURER") "iPixel") (field (name "VOLTAGE") "5.5 V"))
      (libsource (lib "eagle-import") (part "SK6805-EC15"))
    )
    (comp (ref "IC235")
      (value "SK6805-EC15")
      (footprint "eagle-import:SK6805-EC_IPIXEL")
      (fields (field (name "MANUFACTURER") "iPixel") (field (name "VOLTAGE") "5.5 V"))
      (libsource (lib "eagle-import") (part "SK6805-EC15"))
    )
    (comp (ref "IC236")
      (value "SK6805-EC15")
      (footprint "eagle-import:SK6805-EC_IPIXEL")
      (fields (field (name "MANUFACTURER") "iPixel") (field (name "VOLTAGE") "5.5 V"))
      (libsource (lib "eagle-import") (part "SK6805-EC15"))
    )
    (comp (ref "IC237")
      (value "SK6805-EC15")
      (footprint "eagle-import:SK6805-EC_IPIXEL")
      (fields (field (name "MANUFACTURER") "iPixel") (field (name "VOLTAGE") "5.5 V"))
      (libsource (lib "eagle-import") (part "SK6805-EC15"))
    )
    (comp (ref "IC238")
      (value "SK6805-EC15")
      (footprint "eagle-import:SK6805-EC_IPIXEL")
      (fields (field (name "MANUFACTURER") "iPixel") (field (name "VOLTAGE") "5.5 V"))
      (libsource (lib "eagle-import") (part "SK6805-EC15"))
    )
    (comp (ref "IC239")
      (value "SK6805-EC15")
      (footprint "eagle-import:SK6805-EC_IPIXEL")
      (fields (field (name "MANUFACTURER") "iPixel") (field (name "VOLTAGE") "5.5 V"))
      (libsource (lib "eagle-import") (part "SK6805-EC15"))
    )
    (comp (ref "IC240")
      (value "SK6805-EC15")
      (footprint "eagle-import:SK6805-EC_IPIXEL")
      (fields (field (name "MANUFACTURER") "iPixel") (field (name "VOLTAGE") "5.5 V"))
      (libsource (lib "eagle-import") (part "SK6805-EC15"))
    )
    (comp (ref "IC241")
      (value "SK6805-EC15")
      (footprint "eagle-import:SK6805-EC_IPIXEL")
      (fields (field (name "MANUFACTURER") "iPixel") (field (name "VOLTAGE") "5.5 V"))
      (libsource (lib "eagle-import") (part "SK6805-EC15"))
    )
    (comp (ref "IC242")
      (value "SK6805-EC15")
      (footprint "eagle-import:SK6805-EC_IPIXEL")
      (fields (field (name "MANUFACTURER") "iPixel") (field (name "VOLTAGE") "5.5 V"))
      (libsource (lib "eagle-import") (part "SK6805-EC15"))
    )
    (comp (ref "IC243")
      (value "SK6805-EC15")
      (footprint "eagle-import:SK6805-EC_IPIXEL")
      (fields (field (name "MANUFACTURER") "iPixel") (field (name "VOLTAGE") "5.5 V"))
      (libsource (lib "eagle-import") (part "SK6805-EC15"))
    )
    (comp (ref "IC244")
      (value "SK6805-EC15")
      (footprint "eagle-import:SK6805-EC_IPIXEL")
      (fields (field (name "MANUFACTURER") "iPixel") (field (name "VOLTAGE") "5.5 V"))
      (libsource (lib "eagle-import") (part "SK6805-EC15"))
    )
    (comp (ref "IC245")
      (value "SK6805-EC15")
      (footprint "eagle-import:SK6805-EC_IPIXEL")
      (fields (field (name "MANUFACTURER") "iPixel") (field (name "VOLTAGE") "5.5 V"))
      (libsource (lib "eagle-import") (part "SK6805-EC15"))
    )
    (comp (ref "IC246")
      (value "SK6805-EC15")
      (footprint "eagle-import:SK6805-EC_IPIXEL")
      (fields (field (name "MANUFACTURER") "iPixel") (field (name "VOLTAGE") "5.5 V"))
      (libsource (lib "eagle-import") (part "SK6805-EC15"))
    )
    (comp (ref "IC247")
      (value "SK6805-EC15")
      (footprint "eagle-import:SK6805-EC_IPIXEL")
      (fields (field (name "MANUFACTURER") "iPixel") (field (name "VOLTAGE") "5.5 V"))
      (libsource (lib "eagle-import") (part "SK6805-EC15"))
    )
    (comp (ref "IC248")
      (value "SK6805-EC15")
      (footprint "eagle-import:SK6805-EC_IPIXEL")
      (fields (field (name "MANUFACTURER") "iPixel") (field (name "VOLTAGE") "5.5 V"))
      (libsource (lib "eagle-import") (part "SK6805-EC15"))
    )
    (comp (ref "IC249")
      (value "SK6805-EC15")
      (footprint "eagle-import:SK6805-EC_IPIXEL")
      (fields (field (name "MANUFACTURER") "iPixel") (field (name "VOLTAGE") "5.5 V"))
      (libsource (lib "eagle-import") (part "SK6805-EC15"))
    )
    (comp (ref "IC250")
      (value "SK6805-EC15")
      (footprint "eagle-import:SK6805-EC_IPIXEL")
      (fields (field (name "MANUFACTURER") "iPixel") (field (name "VOLTAGE") "5.5 V"))
      (libsource (lib "eagle-import") (part "SK6805-EC15"))
    )
    (comp (ref "IC251")
      (value "SK6805-EC15")
      (footprint "eagle-import:SK6805-EC_IPIXEL")
      (fields (field (name "MANUFACTURER") "iPixel") (field (name "VOLTAGE") "5.5 V"))
      (libsource (lib "eagle-import") (part "SK6805-EC15"))
    )
    (comp (ref "IC252")
      (value "SK6805-EC15")
      (footprint "eagle-import:SK6805-EC_IPIXEL")
      (fields (field (name "MANUFACTURER") "iPixel") (field (name "VOLTAGE") "5.5 V"))
      (libsource (lib "eagle-import") (part "SK6805-EC15"))
    )
    (comp (ref "IC253")
      (value "SK6805-EC15")
      (footprint "eagle-import:SK6805-EC_IPIXEL")
      (fields (field (name "MANUFACTURER") "iPixel") (field (name "VOLTAGE") "5.5 V"))
      (libsource (lib "eagle-import") (part "SK6805-EC15"))
    )
    (comp (ref "IC254")
      (value "SK6805-EC15")
      (footprint "eagle-import:SK6805-EC_IPIXEL")
      (fields (field (name "MANUFACTURER") "iPixel") (field (name "VOLTAGE") "5.5 V"))
      (libsource (lib "eagle-import") (part "SK6805-EC15"))
    )
    (comp (ref "IC255")
      (value "SK6805-EC15")
      (footprint "eagle-import:SK6805-EC_IPIXEL")
      (fields (field (name "MANUFACTURER") "iPixel") (field (name "VOLTAGE") "5.5 V"))
      (libsource (lib "eagle-import") (part "SK6805-EC15"))
    )
    (comp (ref "IC256")
      (value "SK6805-EC15")
      (footprint "eagle-import:SK6805-EC_IPIXEL")
      (fields (field (name "MANUFACTURER") "iPixel") (field (name "VOLTAGE") "5.5 V"))
      (libsource (lib "eagle-import") (part "SK6805-EC15"))
    )
    (comp (ref "IC257")
      (value "SK6805-EC15")
      (footprint "eagle-import:SK6805-EC_IPIXEL")
      (fields (field (name "MANUFACTURER") "iPixel") (field (name "VOLTAGE") "5.5 V"))
      (libsource (lib "eagle-import") (part "SK6805-EC15"))
    )
    (comp (ref "IC258")
      (value "SK6805-EC15")
      (footprint "eagle-import:SK6805-EC_IPIXEL")
      (fields (field (name "MANUFACTURER") "iPixel") (field (name "VOLTAGE") "5.5 V"))
      (libsource (lib "eagle-import") (part "SK6805-EC15"))
    )
    (comp (ref "IC259")
      (value "SK6805-EC15")
      (footprint "eagle-import:SK6805-EC_IPIXEL")
      (fields (field (name "MANUFACTURER") "iPixel") (field (name "VOLTAGE") "5.5 V"))
      (libsource (lib "eagle-import") (part "SK6805-EC15"))
    )
    (comp (ref "IC260")
      (value "SK6805-EC15")
      (footprint "eagle-import:SK6805-EC_IPIXEL")
      (fields (field (name "MANUFACTURER") "iPixel") (field (name "VOLTAGE") "5.5 V"))
      (libsource (lib "eagle-import") (part "SK6805-EC15"))
    )
    (comp (ref "IC261")
      (value "SK6805-EC15")
      (footprint "eagle-import:SK6805-EC_IPIXEL")
      (fields (field (name "MANUFACTURER") "iPixel") (field (name "VOLTAGE") "5.5 V"))
      (libsource (lib "eagle-import") (part "SK6805-EC15"))
    )
    (comp (ref "IC262")
      (value "SK6805-EC15")
      (footprint "eagle-import:SK6805-EC_IPIXEL")
      (fields (field (name "MANUFACTURER") "iPixel") (field (name "VOLTAGE") "5.5 V"))
      (libsource (lib "eagle-import") (part "SK6805-EC15"))
    )
    (comp (ref "IC263")
      (value "SK6805-EC15")
      (footprint "eagle-import:SK6805-EC_IPIXEL")
      (fields (field (name "MANUFACTURER") "iPixel") (field (name "VOLTAGE") "5.5 V"))
      (libsource (lib "eagle-import") (part "SK6805-EC15"))
    )
    (comp (ref "IC264")
      (value "SK6805-EC15")
      (footprint "eagle-import:SK6805-EC_IPIXEL")
      (fields (field (name "MANUFACTURER") "iPixel") (field (name "VOLTAGE") "5.5 V"))
      (libsource (lib "eagle-import") (part "SK6805-EC15"))
    )
    (comp (ref "IC265")
      (value "SK6805-EC15")
      (footprint "eagle-import:SK6805-EC_IPIXEL")
      (fields (field (name "MANUFACTURER") "iPixel") (field (name "VOLTAGE") "5.5 V"))
      (libsource (lib "eagle-import") (part "SK6805-EC15"))
    )
    (comp (ref "IC266")
      (value "SK6805-EC15")
      (footprint "eagle-import:SK6805-EC_IPIXEL")
      (fields (field (name "MANUFACTURER") "iPixel") (field (name "VOLTAGE") "5.5 V"))
      (libsource (lib "eagle-import") (part "SK6805-EC15"))
    )
    (comp (ref "IC267")
      (value "SK6805-EC15")
      (footprint "eagle-import:SK6805-EC_IPIXEL")
      (fields (field (name "MANUFACTURER") "iPixel") (field (name "VOLTAGE") "5.5 V"))
      (libsource (lib "eagle-import") (part "SK6805-EC15"))
    )
    (comp (ref "IC268")
      (value "SK6805-EC15")
      (footprint "eagle-import:SK6805-EC_IPIXEL")
      (fields (field (name "MANUFACTURER") "iPixel") (field (name "VOLTAGE") "5.5 V"))
      (libsource (lib "eagle-import") (part "SK6805-EC15"))
    )
    (comp (ref "IC269")
      (value "SK6805-EC15")
      (footprint "eagle-import:SK6805-EC_IPIXEL")
      (fields (field (name "MANUFACTURER") "iPixel") (field (name "VOLTAGE") "5.5 V"))
      (libsource (lib "eagle-import") (part "SK6805-EC15"))
    )
    (comp (ref "IC270")
      (value "SK6805-EC15")
      (footprint "eagle-import:SK6805-EC_IPIXEL")
      (fields (field (name "MANUFACTURER") "iPixel") (field (name "VOLTAGE") "5.5 V"))
      (libsource (lib "eagle-import") (part "SK6805-EC15"))
    )
    (comp (ref "IC271")
      (value "SK6805-EC15")
      (footprint "eagle-import:SK6805-EC_IPIXEL")
      (fields (field (name "MANUFACTURER") "iPixel") (field (name "VOLTAGE") "5.5 V"))
      (libsource (lib "eagle-import") (part "SK6805-EC15"))
    )
    (comp (ref "IC272")
      (value "SK6805-EC15")
      (footprint "eagle-import:SK6805-EC_IPIXEL")
      (fields (field (name "MANUFACTURER") "iPixel") (field (name "VOLTAGE") "5.5 V"))
      (libsource (lib "eagle-import") (part "SK6805-EC15"))
    )
    (comp (ref "IC273")
      (value "SK6805-EC15")
      (footprint "eagle-import:SK6805-EC_IPIXEL")
      (fields (field (name "MANUFACTURER") "iPixel") (field (name "VOLTAGE") "5.5 V"))
      (libsource (lib "eagle-import") (part "SK6805-EC15"))
    )
    (comp (ref "IC274")
      (value "SK6805-EC15")
      (footprint "eagle-import:SK6805-EC_IPIXEL")
      (fields (field (name "MANUFACTURER") "iPixel") (field (name "VOLTAGE") "5.5 V"))
      (libsource (lib "eagle-import") (part "SK6805-EC15"))
    )
    (comp (ref "IC275")
      (value "SK6805-EC15")
      (footprint "eagle-import:SK6805-EC_IPIXEL")
      (fields (field (name "MANUFACTURER") "iPixel") (field (name "VOLTAGE") "5.5 V"))
      (libsource (lib "eagle-import") (part "SK6805-EC15"))
    )
    (comp (ref "IC276")
      (value "SK6805-EC15")
      (footprint "eagle-import:SK6805-EC_IPIXEL")
      (fields (field (name "MANUFACTURER") "iPixel") (field (name "VOLTAGE") "5.5 V"))
      (libsource (lib "eagle-import") (part "SK6805-EC15"))
    )
    (comp (ref "IC277")
      (value "SK6805-EC15")
      (footprint "eagle-import:SK6805-EC_IPIXEL")
      (fields (field (name "MANUFACTURER") "iPixel") (field (name "VOLTAGE") "5.5 V"))
      (libsource (lib "eagle-import") (part "SK6805-EC15"))
    )
    (comp (ref "IC278")
      (value "SK6805-EC15")
      (footprint "eagle-import:SK6805-EC_IPIXEL")
      (fields (field (name "MANUFACTURER") "iPixel") (field (name "VOLTAGE") "5.5 V"))
      (libsource (lib "eagle-import") (part "SK6805-EC15"))
    )
    (comp (ref "IC279")
      (value "SK6805-EC15")
      (footprint "eagle-import:SK6805-EC_IPIXEL")
      (fields (field (name "MANUFACTURER") "iPixel") (field (name "VOLTAGE") "5.5 V"))
      (libsource (lib "eagle-import") (part "SK6805-EC15"))
    )
    (comp (ref "IC280")
      (value "SK6805-EC15")
      (footprint "eagle-import:SK6805-EC_IPIXEL")
      (fields (field (name "MANUFACTURER") "iPixel") (field (name "VOLTAGE") "5.5 V"))
      (libsource (lib "eagle-import") (part "SK6805-EC15"))
    )
    (comp (ref "IC281")
      (value "SK6805-EC15")
      (footprint "eagle-import:SK6805-EC_IPIXEL")
      (fields (field (name "MANUFACTURER") "iPixel") (field (name "VOLTAGE") "5.5 V"))
      (libsource (lib "eagle-import") (part "SK6805-EC15"))
    )
    (comp (ref "IC282")
      (value "SK6805-EC15")
      (footprint "eagle-import:SK6805-EC_IPIXEL")
      (fields (field (name "MANUFACTURER") "iPixel") (field (name "VOLTAGE") "5.5 V"))
      (libsource (lib "eagle-import") (part "SK6805-EC15"))
    )
    (comp (ref "IC283")
      (value "SK6805-EC15")
      (footprint "eagle-import:SK6805-EC_IPIXEL")
      (fields (field (name "MANUFACTURER") "iPixel") (field (name "VOLTAGE") "5.5 V"))
      (libsource (lib "eagle-import") (part "SK6805-EC15"))
    )
    (comp (ref "IC284")
      (value "SK6805-EC15")
      (footprint "eagle-import:SK6805-EC_IPIXEL")
      (fields (field (name "MANUFACTURER") "iPixel") (field (name "VOLTAGE") "5.5 V"))
      (libsource (lib "eagle-import") (part "SK6805-EC15"))
    )
    (comp (ref "IC285")
      (value "SK6805-EC15")
      (footprint "eagle-import:SK6805-EC_IPIXEL")
      (fields (field (name "MANUFACTURER") "iPixel") (field (name "VOLTAGE") "5.5 V"))
      (libsource (lib "eagle-import") (part "SK6805-EC15"))
    )
    (comp (ref "IC286")
      (value "SK6805-EC15")
      (footprint "eagle-import:SK6805-EC_IPIXEL")
      (fields (field (name "MANUFACTURER") "iPixel") (field (name "VOLTAGE") "5.5 V"))
      (libsource (lib "eagle-import") (part "SK6805-EC15"))
    )
    (comp (ref "IC287")
      (value "SK6805-EC15")
      (footprint "eagle-import:SK6805-EC_IPIXEL")
      (fields (field (name "MANUFACTURER") "iPixel") (field (name "VOLTAGE") "5.5 V"))
      (libsource (lib "eagle-import") (part "SK6805-EC15"))
    )
    (comp (ref "IC288")
      (value "SK6805-EC15")
      (footprint "eagle-import:SK6805-EC_IPIXEL")
      (fields (field (name "MANUFACTURER") "iPixel") (field (name "VOLTAGE") "5.5 V"))
      (libsource (lib "eagle-import") (part "SK6805-EC15"))
    )
    (comp (ref "IC289")
      (value "SK6805-EC15")
      (footprint "eagle-import:SK6805-EC_IPIXEL")
      (fields (field (name "MANUFACTURER") "iPixel") (field (name "VOLTAGE") "5.5 V"))
      (libsource (lib "eagle-import") (part "SK6805-EC15"))
    )
    (comp (ref "IC290")
      (value "SK6805-EC15")
      (footprint "eagle-import:SK6805-EC_IPIXEL")
      (fields (field (name "MANUFACTURER") "iPixel") (field (name "VOLTAGE") "5.5 V"))
      (libsource (lib "eagle-import") (part "SK6805-EC15"))
    )
    (comp (ref "IC291")
      (value "SK6805-EC15")
      (footprint "eagle-import:SK6805-EC_IPIXEL")
      (fields (field (name "MANUFACTURER") "iPixel") (field (name "VOLTAGE") "5.5 V"))
      (libsource (lib "eagle-import") (part "SK6805-EC15"))
    )
    (comp (ref "IC292")
      (value "SK6805-EC15")
      (footprint "eagle-import:SK6805-EC_IPIXEL")
      (fields (field (name "MANUFACTURER") "iPixel") (field (name "VOLTAGE") "5.5 V"))
      (libsource (lib "eagle-import") (part "SK6805-EC15"))
    )
    (comp (ref "IC293")
      (value "SK6805-EC15")
      (footprint "eagle-import:SK6805-EC_IPIXEL")
      (fields (field (name "MANUFACTURER") "iPixel") (field (name "VOLTAGE") "5.5 V"))
      (libsource (lib "eagle-import") (part "SK6805-EC15"))
    )
    (comp (ref "IC294")
      (value "SK6805-EC15")
      (footprint "eagle-import:SK6805-EC_IPIXEL")
      (fields (field (name "MANUFACTURER") "iPixel") (field (name "VOLTAGE") "5.5 V"))
      (libsource (lib "eagle-import") (part "SK6805-EC15"))
    )
    (comp (ref "IC295")
      (value "SK6805-EC15")
      (footprint "eagle-import:SK6805-EC_IPIXEL")
      (fields (field (name "MANUFACTURER") "iPixel") (field (name "VOLTAGE") "5.5 V"))
      (libsource (lib "eagle-import") (part "SK6805-EC15"))
    )
    (comp (ref "IC296")
      (value "SK6805-EC15")
      (footprint "eagle-import:SK6805-EC_IPIXEL")
      (fields (field (name "MANUFACTURER") "iPixel") (field (name "VOLTAGE") "5.5 V"))
      (libsource (lib "eagle-import") (part "SK6805-EC15"))
    )
    (comp (ref "IC297")
      (value "SK6805-EC15")
      (footprint "eagle-import:SK6805-EC_IPIXEL")
      (fields (field (name "MANUFACTURER") "iPixel") (field (name "VOLTAGE") "5.5 V"))
      (libsource (lib "eagle-import") (part "SK6805-EC15"))
    )
    (comp (ref "IC298")
      (value "SK6805-EC15")
      (footprint "eagle-import:SK6805-EC_IPIXEL")
      (fields (field (name "MANUFACTURER") "iPixel") (field (name "VOLTAGE") "5.5 V"))
      (libsource (lib "eagle-import") (part "SK6805-EC15"))
    )
    (comp (ref "IC299")
      (value "SK6805-EC15")
      (footprint "eagle-import:SK6805-EC_IPIXEL")
      (fields (field (name "MANUFACTURER") "iPixel") (field (name "VOLTAGE") "5.5 V"))
      (libsource (lib "eagle-import") (part "SK6805-EC15"))
    )
    (comp (ref "IC300")
      (value "SK6805-EC15")
      (footprint "eagle-import:SK6805-EC_IPIXEL")
      (fields (field (name "MANUFACTURER") "iPixel") (field (name "VOLTAGE") "5.5 V"))
      (libsource (lib "eagle-import") (part "SK6805-EC15"))
    )
    (comp (ref "IC301")
      (value "SK6805-EC15")
      (footprint "eagle-import:SK6805-EC_IPIXEL")
      (fields (field (name "MANUFACTURER") "iPixel") (field (name "VOLTAGE") "5.5 V"))
      (libsource (lib "eagle-import") (part "SK6805-EC15"))
    )
    (comp (ref "IC302")
      (value "SK6805-EC15")
      (footprint "eagle-import:SK6805-EC_IPIXEL")
      (fields (field (name "MANUFACTURER") "iPixel") (field (name "VOLTAGE") "5.5 V"))
      (libsource (lib "eagle-import") (part "SK6805-EC15"))
    )
    (comp (ref "IC303")
      (value "SK6805-EC15")
      (footprint "eagle-import:SK6805-EC_IPIXEL")
      (fields (field (name "MANUFACTURER") "iPixel") (field (name "VOLTAGE") "5.5 V"))
      (libsource (lib "eagle-import") (part "SK6805-EC15"))
    )
    (comp (ref "IC304")
      (value "SK6805-EC15")
      (footprint "eagle-import:SK6805-EC_IPIXEL")
      (fields (field (name "MANUFACTURER") "iPixel") (field (name "VOLTAGE") "5.5 V"))
      (libsource (lib "eagle-import") (part "SK6805-EC15"))
    )
    (comp (ref "IC305")
      (value "SK6805-EC15")
      (footprint "eagle-import:SK6805-EC_IPIXEL")
      (fields (field (name "MANUFACTURER") "iPixel") (field (name "VOLTAGE") "5.5 V"))
      (libsource (lib "eagle-import") (part "SK6805-EC15"))
    )
    (comp (ref "IC306")
      (value "SK6805-EC15")
      (footprint "eagle-import:SK6805-EC_IPIXEL")
      (fields (field (name "MANUFACTURER") "iPixel") (field (name "VOLTAGE") "5.5 V"))
      (libsource (lib "eagle-import") (part "SK6805-EC15"))
    )
    (comp (ref "IC307")
      (value "SK6805-EC15")
      (footprint "eagle-import:SK6805-EC_IPIXEL")
      (fields (field (name "MANUFACTURER") "iPixel") (field (name "VOLTAGE") "5.5 V"))
      (libsource (lib "eagle-import") (part "SK6805-EC15"))
    )
    (comp (ref "IC308")
      (value "SK6805-EC15")
      (footprint "eagle-import:SK6805-EC_IPIXEL")
      (fields (field (name "MANUFACTURER") "iPixel") (field (name "VOLTAGE") "5.5 V"))
      (libsource (lib "eagle-import") (part "SK6805-EC15"))
    )
    (comp (ref "IC309")
      (value "SK6805-EC15")
      (footprint "eagle-import:SK6805-EC_IPIXEL")
      (fields (field (name "MANUFACTURER") "iPixel") (field (name "VOLTAGE") "5.5 V"))
      (libsource (lib "eagle-import") (part "SK6805-EC15"))
    )
    (comp (ref "IC310")
      (value "SK6805-EC15")
      (footprint "eagle-import:SK6805-EC_IPIXEL")
      (fields (field (name "MANUFACTURER") "iPixel") (field (name "VOLTAGE") "5.5 V"))
      (libsource (lib "eagle-import") (part "SK6805-EC15"))
    )
    (comp (ref "IC311")
      (value "SK6805-EC15")
      (footprint "eagle-import:SK6805-EC_IPIXEL")
      (fields (field (name "MANUFACTURER") "iPixel") (field (name "VOLTAGE") "5.5 V"))
      (libsource (lib "eagle-import") (part "SK6805-EC15"))
    )
    (comp (ref "IC312")
      (value "SK6805-EC15")
      (footprint "eagle-import:SK6805-EC_IPIXEL")
      (fields (field (name "MANUFACTURER") "iPixel") (field (name "VOLTAGE") "5.5 V"))
      (libsource (lib "eagle-import") (part "SK6805-EC15"))
    )
    (comp (ref "IC313")
      (value "SK6805-EC15")
      (footprint "eagle-import:SK6805-EC_IPIXEL")
      (fields (field (name "MANUFACTURER") "iPixel") (field (name "VOLTAGE") "5.5 V"))
      (libsource (lib "eagle-import") (part "SK6805-EC15"))
    )
    (comp (ref "IC314")
      (value "SK6805-EC15")
      (footprint "eagle-import:SK6805-EC_IPIXEL")
      (fields (field (name "MANUFACTURER") "iPixel") (field (name "VOLTAGE") "5.5 V"))
      (libsource (lib "eagle-import") (part "SK6805-EC15"))
    )
    (comp (ref "IC315")
      (value "SK6805-EC15")
      (footprint "eagle-import:SK6805-EC_IPIXEL")
      (fields (field (name "MANUFACTURER") "iPixel") (field (name "VOLTAGE") "5.5 V"))
      (libsource (lib "eagle-import") (part "SK6805-EC15"))
    )
    (comp (ref "IC316")
      (value "SK6805-EC15")
      (footprint "eagle-import:SK6805-EC_IPIXEL")
      (fields (field (name "MANUFACTURER") "iPixel") (field (name "VOLTAGE") "5.5 V"))
      (libsource (lib "eagle-import") (part "SK6805-EC15"))
    )
    (comp (ref "IC317")
      (value "SK6805-EC15")
      (footprint "eagle-import:SK6805-EC_IPIXEL")
      (fields (field (name "MANUFACTURER") "iPixel") (field (name "VOLTAGE") "5.5 V"))
      (libsource (lib "eagle-import") (part "SK6805-EC15"))
    )
    (comp (ref "IC318")
      (value "SK6805-EC15")
      (footprint "eagle-import:SK6805-EC_IPIXEL")
      (fields (field (name "MANUFACTURER") "iPixel") (field (name "VOLTAGE") "5.5 V"))
      (libsource (lib "eagle-import") (part "SK6805-EC15"))
    )
    (comp (ref "IC319")
      (value "SK6805-EC15")
      (footprint "eagle-import:SK6805-EC_IPIXEL")
      (fields (field (name "MANUFACTURER") "iPixel") (field (name "VOLTAGE") "5.5 V"))
      (libsource (lib "eagle-import") (part "SK6805-EC15"))
    )
    (comp (ref "IC320")
      (value "SK6805-EC15")
      (footprint "eagle-import:SK6805-EC_IPIXEL")
      (fields (field (name "MANUFACTURER") "iPixel") (field (name "VOLTAGE") "5.5 V"))
      (libsource (lib "eagle-import") (part "SK6805-EC15"))
    )
    (comp (ref "IC321")
      (value "SK6805-EC15")
      (footprint "eagle-import:SK6805-EC_IPIXEL")
      (fields (field (name "MANUFACTURER") "iPixel") (field (name "VOLTAGE") "5.5 V"))
      (libsource (lib "eagle-import") (part "SK6805-EC15"))
    )
    (comp (ref "IC322")
      (value "SK6805-EC15")
      (footprint "eagle-import:SK6805-EC_IPIXEL")
      (fields (field (name "MANUFACTURER") "iPixel") (field (name "VOLTAGE") "5.5 V"))
      (libsource (lib "eagle-import") (part "SK6805-EC15"))
    )
    (comp (ref "IC323")
      (value "SK6805-EC15")
      (footprint "eagle-import:SK6805-EC_IPIXEL")
      (fields (field (name "MANUFACTURER") "iPixel") (field (name "VOLTAGE") "5.5 V"))
      (libsource (lib "eagle-import") (part "SK6805-EC15"))
    )
    (comp (ref "IC324")
      (value "SK6805-EC15")
      (footprint "eagle-import:SK6805-EC_IPIXEL")
      (fields (field (name "MANUFACTURER") "iPixel") (field (name "VOLTAGE") "5.5 V"))
      (libsource (lib "eagle-import") (part "SK6805-EC15"))
    )
    (comp (ref "IC325")
      (value "SK6805-EC15")
      (footprint "eagle-import:SK6805-EC_IPIXEL")
      (fields (field (name "MANUFACTURER") "iPixel") (field (name "VOLTAGE") "5.5 V"))
      (libsource (lib "eagle-import") (part "SK6805-EC15"))
    )
    (comp (ref "IC326")
      (value "SK6805-EC15")
      (footprint "eagle-import:SK6805-EC_IPIXEL")
      (fields (field (name "MANUFACTURER") "iPixel") (field (name "VOLTAGE") "5.5 V"))
      (libsource (lib "eagle-import") (part "SK6805-EC15"))
    )
    (comp (ref "IC327")
      (value "SK6805-EC15")
      (footprint "eagle-import:SK6805-EC_IPIXEL")
      (fields (field (name "MANUFACTURER") "iPixel") (field (name "VOLTAGE") "5.5 V"))
      (libsource (lib "eagle-import") (part "SK6805-EC15"))
    )
    (comp (ref "IC328")
      (value "SK6805-EC15")
      (footprint "eagle-import:SK6805-EC_IPIXEL")
      (fields (field (name "MANUFACTURER") "iPixel") (field (name "VOLTAGE") "5.5 V"))
      (libsource (lib "eagle-import") (part "SK6805-EC15"))
    )
    (comp (ref "IC329")
      (value "SK6805-EC15")
      (footprint "eagle-import:SK6805-EC_IPIXEL")
      (fields (field (name "MANUFACTURER") "iPixel") (field (name "VOLTAGE") "5.5 V"))
      (libsource (lib "eagle-import") (part "SK6805-EC15"))
    )
    (comp (ref "IC330")
      (value "SK6805-EC15")
      (footprint "eagle-import:SK6805-EC_IPIXEL")
      (fields (field (name "MANUFACTURER") "iPixel") (field (name "VOLTAGE") "5.5 V"))
      (libsource (lib "eagle-import") (part "SK6805-EC15"))
    )
    (comp (ref "IC331")
      (value "SK6805-EC15")
      (footprint "eagle-import:SK6805-EC_IPIXEL")
      (fields (field (name "MANUFACTURER") "iPixel") (field (name "VOLTAGE") "5.5 V"))
      (libsource (lib "eagle-import") (part "SK6805-EC15"))
    )
    (comp (ref "IC332")
      (value "SK6805-EC15")
      (footprint "eagle-import:SK6805-EC_IPIXEL")
      (fields (field (name "MANUFACTURER") "iPixel") (field (name "VOLTAGE") "5.5 V"))
      (libsource (lib "eagle-import") (part "SK6805-EC15"))
    )
    (comp (ref "L9")
      (value "74279269")
      (footprint "eagle-import:FERRIT_0603_WIDE_BAND_WUERTH")
      (fields (field (name "MANUFACTURER") "Wuerth"))
      (libsource (lib "eagle-import") (part "74279269"))
    )
    (comp (ref "L11")
      (value "742792097")
      (footprint "eagle-import:FERRIT_0805_WUERTH")
      (fields (field (name "MANUFACTURER") "Wuerth"))
      (libsource (lib "eagle-import") (part "742792097"))
    )
    (comp (ref "L14")
      (value "742792097")
      (footprint "eagle-import:FERRIT_0805_WUERTH")
      (fields (field (name "MANUFACTURER") "Wuerth"))
      (libsource (lib "eagle-import") (part "742792097"))
    )
    (comp (ref "PS1")
      (value "PASSERMARKE")
      (footprint "eagle-import:PASSERMARKE")
      (libsource (lib "eagle-import") (part "PASSERMARKE"))
    )
    (comp (ref "PS2")
      (value "PASSERMARKE")
      (footprint "eagle-import:PASSERMARKE")
      (libsource (lib "eagle-import") (part "PASSERMARKE"))
    )
    (comp (ref "PS3")
      (value "PASSERMARKE")
      (footprint "eagle-import:PASSERMARKE")
      (libsource (lib "eagle-import") (part "PASSERMARKE"))
    )
    (comp (ref "PS4")
      (value "PASSERMARKE")
      (footprint "eagle-import:PASSERMARKE")
      (libsource (lib "eagle-import") (part "PASSERMARKE"))
    )
    (comp (ref "PS5")
      (value "PASSERMARKE")
      (footprint "eagle-import:PASSERMARKE")
      (libsource (lib "eagle-import") (part "PASSERMARKE"))
    )
    (comp (ref "PS6")
      (value "PASSERMARKE")
      (footprint "eagle-import:PASSERMARKE")
      (libsource (lib "eagle-import") (part "PASSERMARKE"))
    )
    (comp (ref "R1")
      (value "0R")
      (footprint "eagle-import:R0603")
      (fields
        (field (name "MANUFACTURER") "free choice")
        (field (name "POWER") "63 mW")
        (field (name "VOLTAGE") "50.0 V")
      )
      (libsource (lib "eagle-import") (part "R-EU-R0603-0R"))
    )
    (comp (ref "R2")
      (value "10k")
      (footprint "eagle-import:R0603")
      (fields
        (field (name "MANUFACTURER") "free choice")
        (field (name "POWER") "63 mW")
        (field (name "TOLERANCE") "±1 %")
      )
      (libsource (lib "eagle-import") (part "R-EU-R0603-10K"))
    )
    (comp (ref "R3")
      (value "56k")
      (footprint "eagle-import:R0603")
      (fields
        (field (name "MANUFACTURER") "free choice")
        (field (name "POWER") "63 mW")
        (field (name "TOLERANCE") "±1 %")
      )
      (libsource (lib "eagle-import") (part "R-EU-R0603-56K"))
    )
    (comp (ref "R4")
      (value "56k")
      (footprint "eagle-import:R0603")
      (fields
        (field (name "MANUFACTURER") "free choice")
        (field (name "POWER") "63 mW")
        (field (name "TOLERANCE") "±1 %")
      )
      (libsource (lib "eagle-import") (part "R-EU-R0603-56K"))
    )
    (comp (ref "R5")
      (value "56k")
      (footprint "eagle-import:R0603")
      (fields
        (field (name "MANUFACTURER") "free choice")
        (field (name "POWER") "63 mW")
        (field (name "TOLERANCE") "±1 %")
      )
      (libsource (lib "eagle-import") (part "R-EU-R0603-56K"))
    )
    (comp (ref "R6")
      (value "56k")
      (footprint "eagle-import:R0603")
      (fields
        (field (name "MANUFACTURER") "free choice")
        (field (name "POWER") "63 mW")
        (field (name "TOLERANCE") "±1 %")
      )
      (libsource (lib "eagle-import") (part "R-EU-R0603-56K"))
    )
    (comp (ref "R7")
      (value "15R 0W75")
      (footprint "eagle-import:R1210")
      (fields
        (field (name "MANUFACTURER") "Vishay")
        (field (name "POWER") "750 mW")
        (field (name "TOLERANCE") "±1 %")
      )
      (libsource (lib "eagle-import") (part "R-EU-R1210-CRCW121015R0FKEAHP"))
    )
    (comp (ref "R8")
      (value "3R9 0W75")
      (footprint "eagle-import:R1210")
      (fields
        (field (name "MANUFACTURER") "Vishay")
        (field (name "POWER") "750 mW")
        (field (name "TOLERANCE") "±1 %")
      )
      (libsource (lib "eagle-import") (part "R-EU-R1210-CRCW12103R90FKEAHP"))
    )
    (comp (ref "R9")
      (value "0R")
      (footprint "eagle-import:R0603")
      (fields
        (field (name "MANUFACTURER") "free choice")
        (field (name "POWER") "63 mW")
        (field (name "VOLTAGE") "50.0 V")
      )
      (libsource (lib "eagle-import") (part "R-EU-R0603-0R"))
    )
    (comp (ref "R10")
      (value "56k")
      (footprint "eagle-import:R0603")
      (fields
        (field (name "MANUFACTURER") "free choice")
        (field (name "POWER") "63 mW")
        (field (name "TOLERANCE") "±1 %")
      )
      (libsource (lib "eagle-import") (part "R-EU-R0603-56K"))
    )
    (comp (ref "R11")
      (value "56k")
      (footprint "eagle-import:R0603")
      (fields
        (field (name "MANUFACTURER") "free choice")
        (field (name "POWER") "63 mW")
        (field (name "TOLERANCE") "±1 %")
      )
      (libsource (lib "eagle-import") (part "R-EU-R0603-56K"))
    )
    (comp (ref "R12")
      (value "56k")
      (footprint "eagle-import:R0603")
      (fields
        (field (name "MANUFACTURER") "free choice")
        (field (name "POWER") "63 mW")
        (field (name "TOLERANCE") "±1 %")
      )
      (libsource (lib "eagle-import") (part "R-EU-R0603-56K"))
    )
    (comp (ref "R13")
      (value "56k")
      (footprint "eagle-import:R0603")
      (fields
        (field (name "MANUFACTURER") "free choice")
        (field (name "POWER") "63 mW")
        (field (name "TOLERANCE") "±1 %")
      )
      (libsource (lib "eagle-import") (part "R-EU-R0603-56K"))
    )
    (comp (ref "R15")
      (value "3R9 0W75")
      (footprint "eagle-import:R1210")
      (fields
        (field (name "MANUFACTURER") "Vishay")
        (field (name "POWER") "750 mW")
        (field (name "TOLERANCE") "±1 %")
      )
      (libsource (lib "eagle-import") (part "R-EU-R1210-CRCW12103R90FKEAHP"))
    )
    (comp (ref "R16")
      (value "0R")
      (footprint "eagle-import:R0603")
      (fields
        (field (name "MANUFACTURER") "free choice")
        (field (name "POWER") "63 mW")
        (field (name "VOLTAGE") "50.0 V")
      )
      (libsource (lib "eagle-import") (part "R-EU-R0603-0R"))
    )
    (comp (ref "R17")
      (value "91k")
      (footprint "eagle-import:R0603")
      (fields
        (field (name "MANUFACTURER") "free choice")
        (field (name "POWER") "63 mW")
        (field (name "TOLERANCE") "±1 %")
      )
      (libsource (lib "eagle-import") (part "R-EU-R0603-91K"))
    )
    (comp (ref "R18")
      (value "27k")
      (footprint "eagle-import:R0603")
      (fields
        (field (name "MANUFACTURER") "free choice")
        (field (name "POWER") "63 mW")
        (field (name "TOLERANCE") "±1 %")
      )
      (libsource (lib "eagle-import") (part "R-EU-R0603-27K"))
    )
    (comp (ref "R19")
      (value "0R")
      (footprint "eagle-import:R0603")
      (fields
        (field (name "MANUFACTURER") "free choice")
        (field (name "POWER") "63 mW")
        (field (name "VOLTAGE") "50.0 V")
      )
      (libsource (lib "eagle-import") (part "R-EU-R0603-0R"))
    )
    (comp (ref "R20")
      (value "3R9 0W75")
      (footprint "eagle-import:R1210")
      (fields
        (field (name "MANUFACTURER") "Vishay")
        (field (name "POWER") "750 mW")
        (field (name "TOLERANCE") "±1 %")
      )
      (libsource (lib "eagle-import") (part "R-EU-R1210-CRCW12103R90FKEAHP"))
    )
    (comp (ref "R21")
      (value "27R")
      (footprint "eagle-import:R0603")
      (fields
        (field (name "MANUFACTURER") "free choice")
        (field (name "POWER") "63 mW")
        (field (name "TOLERANCE") "±1 %")
      )
      (libsource (lib "eagle-import") (part "R-EU-R0603-27R"))
    )
    (comp (ref "R22")
      (value "3R9 0W75")
      (footprint "eagle-import:R1210")
      (fields
        (field (name "MANUFACTURER") "Vishay")
        (field (name "POWER") "750 mW")
        (field (name "TOLERANCE") "±1 %")
      )
      (libsource (lib "eagle-import") (part "R-EU-R1210-CRCW12103R90FKEAHP"))
    )
    (comp (ref "R23")
      (value "27R")
      (footprint "eagle-import:R0603")
      (fields
        (field (name "MANUFACTURER") "free choice")
        (field (name "POWER") "63 mW")
        (field (name "TOLERANCE") "±1 %")
      )
      (libsource (lib "eagle-import") (part "R-EU-R0603-27R"))
    )
    (comp (ref "R24")
      (value "27R")
      (footprint "eagle-import:R0603")
      (fields
        (field (name "MANUFACTURER") "free choice")
        (field (name "POWER") "63 mW")
        (field (name "TOLERANCE") "±1 %")
      )
      (libsource (lib "eagle-import") (part "R-EU-R0603-27R"))
    )
    (comp (ref "R25")
      (value "3R9 0W75")
      (footprint "eagle-import:R1210")
      (fields
        (field (name "MANUFACTURER") "Vishay")
        (field (name "POWER") "750 mW")
        (field (name "TOLERANCE") "±1 %")
      )
      (libsource (lib "eagle-import") (part "R-EU-R1210-CRCW12103R90FKEAHP"))
    )
    (comp (ref "R26")
      (value "0R")
      (footprint "eagle-import:R0603")
      (fields
        (field (name "MANUFACTURER") "free choice")
        (field (name "POWER") "63 mW")
        (field (name "VOLTAGE") "50.0 V")
      )
      (libsource (lib "eagle-import") (part "R-EU-R0603-0R"))
    )
    (comp (ref "R27")
      (value "0R")
      (footprint "eagle-import:R0603")
      (fields
        (field (name "MANUFACTURER") "free choice")
        (field (name "POWER") "63 mW")
        (field (name "VOLTAGE") "50.0 V")
      )
      (libsource (lib "eagle-import") (part "R-EU-R0603-0R"))
    )
    (comp (ref "R28")
      (value "0R")
      (footprint "eagle-import:R0603")
      (fields
        (field (name "MANUFACTURER") "free choice")
        (field (name "POWER") "63 mW")
        (field (name "VOLTAGE") "50.0 V")
      )
      (libsource (lib "eagle-import") (part "R-EU-R0603-0R"))
    )
    (comp (ref "R29")
      (value "3R9 0W75")
      (footprint "eagle-import:R1210")
      (fields
        (field (name "MANUFACTURER") "Vishay")
        (field (name "POWER") "750 mW")
        (field (name "TOLERANCE") "±1 %")
      )
      (libsource (lib "eagle-import") (part "R-EU-R1210-CRCW12103R90FKEAHP"))
    )
    (comp (ref "R30")
      (value "27R")
      (footprint "eagle-import:R0603")
      (fields
        (field (name "MANUFACTURER") "free choice")
        (field (name "POWER") "63 mW")
        (field (name "TOLERANCE") "±1 %")
      )
      (libsource (lib "eagle-import") (part "R-EU-R0603-27R"))
    )
    (comp (ref "R31")
      (value "10k")
      (footprint "eagle-import:R0603")
      (fields
        (field (name "MANUFACTURER") "free choice")
        (field (name "POWER") "63 mW")
        (field (name "TOLERANCE") "±1 %")
      )
      (libsource (lib "eagle-import") (part "R-EU-R0603-10K"))
    )
    (comp (ref "R32")
      (value "27R")
      (footprint "eagle-import:R0603")
      (fields
        (field (name "MANUFACTURER") "free choice")
        (field (name "POWER") "63 mW")
        (field (name "TOLERANCE") "±1 %")
      )
      (libsource (lib "eagle-import") (part "R-EU-R0603-27R"))
    )
    (comp (ref "R33")
      (value "27R")
      (footprint "eagle-import:R0603")
      (fields
        (field (name "MANUFACTURER") "free choice")
        (field (name "POWER") "63 mW")
        (field (name "TOLERANCE") "±1 %")
      )
      (libsource (lib "eagle-import") (part "R-EU-R0603-27R"))
    )
    (comp (ref "R34")
      (value "3R9 0W75")
      (footprint "eagle-import:R1210")
      (fields
        (field (name "MANUFACTURER") "Vishay")
        (field (name "POWER") "750 mW")
        (field (name "TOLERANCE") "±1 %")
      )
      (libsource (lib "eagle-import") (part "R-EU-R1210-CRCW12103R90FKEAHP"))
    )
    (comp (ref "R35")
      (value "3R9 0W75")
      (footprint "eagle-import:R1210")
      (fields
        (field (name "MANUFACTURER") "Vishay")
        (field (name "POWER") "750 mW")
        (field (name "TOLERANCE") "±1 %")
      )
      (libsource (lib "eagle-import") (part "R-EU-R1210-CRCW12103R90FKEAHP"))
    )
    (comp (ref "R37")
      (value "27R")
      (footprint "eagle-import:R0603")
      (fields
        (field (name "MANUFACTURER") "free choice")
        (field (name "POWER") "63 mW")
        (field (name "TOLERANCE") "±1 %")
      )
      (libsource (lib "eagle-import") (part "R-EU-R0603-27R"))
    )
    (comp (ref "R38")
      (value "0R")
      (footprint "eagle-import:R0603")
      (fields
        (field (name "MANUFACTURER") "free choice")
        (field (name "POWER") "63 mW")
        (field (name "VOLTAGE") "50.0 V")
      )
      (libsource (lib "eagle-import") (part "R-EU-R0603-0R"))
    )
    (comp (ref "R39")
      (value "27R")
      (footprint "eagle-import:R0603")
      (fields
        (field (name "MANUFACTURER") "free choice")
        (field (name "POWER") "63 mW")
        (field (name "TOLERANCE") "±1 %")
      )
      (libsource (lib "eagle-import") (part "R-EU-R0603-27R"))
    )
    (comp (ref "R40")
      (value "10k")
      (footprint "eagle-import:R0603")
      (fields
        (field (name "MANUFACTURER") "free choice")
        (field (name "POWER") "63 mW")
        (field (name "TOLERANCE") "±1 %")
      )
      (libsource (lib "eagle-import") (part "R-EU-R0603-10K"))
    )
    (comp (ref "R43")
      (value "3R9 0W75")
      (footprint "eagle-import:R1210")
      (fields
        (field (name "MANUFACTURER") "Vishay")
        (field (name "POWER") "750 mW")
        (field (name "TOLERANCE") "±1 %")
      )
      (libsource (lib "eagle-import") (part "R-EU-R1210-CRCW12103R90FKEAHP"))
    )
    (comp (ref "R44")
      (value "0R")
      (footprint "eagle-import:R0603")
      (fields
        (field (name "MANUFACTURER") "free choice")
        (field (name "POWER") "63 mW")
        (field (name "VOLTAGE") "50.0 V")
      )
      (libsource (lib "eagle-import") (part "R-EU-R0603-0R"))
    )
    (comp (ref "R46")
      (value "3R9 0W75")
      (footprint "eagle-import:R1210")
      (fields
        (field (name "MANUFACTURER") "Vishay")
        (field (name "POWER") "750 mW")
        (field (name "TOLERANCE") "±1 %")
      )
      (libsource (lib "eagle-import") (part "R-EU-R1210-CRCW12103R90FKEAHP"))
    )
    (comp (ref "R47")
      (value "0R")
      (footprint "eagle-import:R0603")
      (fields
        (field (name "MANUFACTURER") "free choice")
        (field (name "POWER") "63 mW")
        (field (name "VOLTAGE") "50.0 V")
      )
      (libsource (lib "eagle-import") (part "R-EU-R0603-0R"))
    )
    (comp (ref "R49")
      (value "0R")
      (footprint "eagle-import:R0603")
      (fields
        (field (name "MANUFACTURER") "free choice")
        (field (name "POWER") "63 mW")
        (field (name "VOLTAGE") "50.0 V")
      )
      (libsource (lib "eagle-import") (part "R-EU-R0603-0R"))
    )
    (comp (ref "R52")
      (value "3R9 0W75")
      (footprint "eagle-import:R1210")
      (fields
        (field (name "MANUFACTURER") "Vishay")
        (field (name "POWER") "750 mW")
        (field (name "TOLERANCE") "±1 %")
      )
      (libsource (lib "eagle-import") (part "R-EU-R1210-CRCW12103R90FKEAHP"))
    )
    (comp (ref "R54")
      (value "27R")
      (footprint "eagle-import:R0603")
      (fields
        (field (name "MANUFACTURER") "free choice")
        (field (name "POWER") "63 mW")
        (field (name "TOLERANCE") "±1 %")
      )
      (libsource (lib "eagle-import") (part "R-EU-R0603-27R"))
    )
    (comp (ref "R55")
      (value "27R")
      (footprint "eagle-import:R0603")
      (fields
        (field (name "MANUFACTURER") "free choice")
        (field (name "POWER") "63 mW")
        (field (name "TOLERANCE") "±1 %")
      )
      (libsource (lib "eagle-import") (part "R-EU-R0603-27R"))
    )
    (comp (ref "R56")
      (value "27R")
      (footprint "eagle-import:R0603")
      (fields
        (field (name "MANUFACTURER") "free choice")
        (field (name "POWER") "63 mW")
        (field (name "TOLERANCE") "±1 %")
      )
      (libsource (lib "eagle-import") (part "R-EU-R0603-27R"))
    )
    (comp (ref "R57")
      (value "3R9 0W75")
      (footprint "eagle-import:R1210")
      (fields
        (field (name "MANUFACTURER") "Vishay")
        (field (name "POWER") "750 mW")
        (field (name "TOLERANCE") "±1 %")
      )
      (libsource (lib "eagle-import") (part "R-EU-R1210-CRCW12103R90FKEAHP"))
    )
    (comp (ref "R59")
      (value "27R")
      (footprint "eagle-import:R0603")
      (fields
        (field (name "MANUFACTURER") "free choice")
        (field (name "POWER") "63 mW")
        (field (name "TOLERANCE") "±1 %")
      )
      (libsource (lib "eagle-import") (part "R-EU-R0603-27R"))
    )
    (comp (ref "R60")
      (value "56k")
      (footprint "eagle-import:R0603")
      (fields
        (field (name "MANUFACTURER") "free choice")
        (field (name "POWER") "63 mW")
        (field (name "TOLERANCE") "±1 %")
      )
      (libsource (lib "eagle-import") (part "R-EU-R0603-56K"))
    )
    (comp (ref "R62")
      (value "1k1")
      (footprint "eagle-import:R0603")
      (fields
        (field (name "MANUFACTURER") "free choice")
        (field (name "POWER") "63 mW")
        (field (name "TOLERANCE") "±1 %")
      )
      (libsource (lib "eagle-import") (part "R-EU-R0603-1K1"))
    )
    (comp (ref "R64")
      (value "56k")
      (footprint "eagle-import:R0603")
      (fields
        (field (name "MANUFACTURER") "free choice")
        (field (name "POWER") "63 mW")
        (field (name "TOLERANCE") "±1 %")
      )
      (libsource (lib "eagle-import") (part "R-EU-R0603-56K"))
    )
    (comp (ref "R66")
      (value "3R9 0W75")
      (footprint "eagle-import:R1210")
      (fields
        (field (name "MANUFACTURER") "Vishay")
        (field (name "POWER") "750 mW")
        (field (name "TOLERANCE") "±1 %")
      )
      (libsource (lib "eagle-import") (part "R-EU-R1210-CRCW12103R90FKEAHP"))
    )
    (comp (ref "R67")
      (value "10k")
      (footprint "eagle-import:R0603")
      (fields
        (field (name "MANUFACTURER") "free choice")
        (field (name "POWER") "63 mW")
        (field (name "TOLERANCE") "±1 %")
      )
      (libsource (lib "eagle-import") (part "R-EU-R0603-10K"))
    )
    (comp (ref "R69")
      (value "3R9 0W75")
      (footprint "eagle-import:R1210")
      (fields
        (field (name "MANUFACTURER") "Vishay")
        (field (name "POWER") "750 mW")
        (field (name "TOLERANCE") "±1 %")
      )
      (libsource (lib "eagle-import") (part "R-EU-R1210-CRCW12103R90FKEAHP"))
    )
    (comp (ref "R70")
      (value "R-EU-R0603")
      (footprint "eagle-import:R0603")
      (fields
        (field (name "POWER") "63 mW")
        (field (name "TOLERANCE") "±1 %")
        (field (name "VOLTAGE") "50 V")
      )
      (libsource (lib "eagle-import") (part "R-EU-R0603"))
    )
    (comp (ref "R71")
      (value "R-EU-R0603")
      (footprint "eagle-import:R0603")
      (fields
        (field (name "POWER") "63 mW")
        (field (name "TOLERANCE") "±1 %")
        (field (name "VOLTAGE") "50 V")
      )
      (libsource (lib "eagle-import") (part "R-EU-R0603"))
    )
    (comp (ref "R72")
      (value "0R")
      (footprint "eagle-import:R0603")
      (fields
        (field (name "MANUFACTURER") "free choice")
        (field (name "POWER") "63 mW")
        (field (name "VOLTAGE") "50.0 V")
      )
      (libsource (lib "eagle-import") (part "R-EU-R0603-0R"))
    )
    (comp (ref "R73")
      (value "3R9 0W75")
      (footprint "eagle-import:R1210")
      (fields
        (field (name "MANUFACTURER") "Vishay")
        (field (name "POWER") "750 mW")
        (field (name "TOLERANCE") "±1 %")
      )
      (libsource (lib "eagle-import") (part "R-EU-R1210-CRCW12103R90FKEAHP"))
    )
    (comp (ref "R75")
      (value "3R9 0W75")
      (footprint "eagle-import:R1210")
      (fields
        (field (name "MANUFACTURER") "Vishay")
        (field (name "POWER") "750 mW")
        (field (name "TOLERANCE") "±1 %")
      )
      (libsource (lib "eagle-import") (part "R-EU-R1210-CRCW12103R90FKEAHP"))
    )
    (comp (ref "R76")
      (value "0R")
      (footprint "eagle-import:R0603")
      (fields
        (field (name "MANUFACTURER") "free choice")
        (field (name "POWER") "63 mW")
        (field (name "VOLTAGE") "50.0 V")
      )
      (libsource (lib "eagle-import") (part "R-EU-R0603-0R"))
    )
    (comp (ref "R78")
      (value "0R")
      (footprint "eagle-import:R0603")
      (fields
        (field (name "MANUFACTURER") "free choice")
        (field (name "POWER") "63 mW")
        (field (name "VOLTAGE") "50.0 V")
      )
      (libsource (lib "eagle-import") (part "R-EU-R0603-0R"))
    )
    (comp (ref "R79")
      (value "0R")
      (footprint "eagle-import:R0603")
      (fields
        (field (name "MANUFACTURER") "free choice")
        (field (name "POWER") "63 mW")
        (field (name "VOLTAGE") "50.0 V")
      )
      (libsource (lib "eagle-import") (part "R-EU-R0603-0R"))
    )
    (comp (ref "R80")
      (value "27R")
      (footprint "eagle-import:R0603")
      (fields
        (field (name "MANUFACTURER") "free choice")
        (field (name "POWER") "63 mW")
        (field (name "TOLERANCE") "±1 %")
      )
      (libsource (lib "eagle-import") (part "R-EU-R0603-27R"))
    )
    (comp (ref "R81")
      (value "27R")
      (footprint "eagle-import:R0603")
      (fields
        (field (name "MANUFACTURER") "free choice")
        (field (name "POWER") "63 mW")
        (field (name "TOLERANCE") "±1 %")
      )
      (libsource (lib "eagle-import") (part "R-EU-R0603-27R"))
    )
    (comp (ref "R82")
      (value "27R")
      (footprint "eagle-import:R0603")
      (fields
        (field (name "MANUFACTURER") "free choice")
        (field (name "POWER") "63 mW")
        (field (name "TOLERANCE") "±1 %")
      )
      (libsource (lib "eagle-import") (part "R-EU-R0603-27R"))
    )
    (comp (ref "R83")
      (value "15R 0W75")
      (footprint "eagle-import:R1210")
      (fields
        (field (name "MANUFACTURER") "Vishay")
        (field (name "POWER") "750 mW")
        (field (name "TOLERANCE") "±1 %")
      )
      (libsource (lib "eagle-import") (part "R-EU-R1210-CRCW121015R0FKEAHP"))
    )
    (comp (ref "R84")
      (value "15R 0W75")
      (footprint "eagle-import:R1210")
      (fields
        (field (name "MANUFACTURER") "Vishay")
        (field (name "POWER") "750 mW")
        (field (name "TOLERANCE") "±1 %")
      )
      (libsource (lib "eagle-import") (part "R-EU-R1210-CRCW121015R0FKEAHP"))
    )
    (comp (ref "R87")
      (value "100R")
      (footprint "eagle-import:R0603")
      (fields
        (field (name "MANUFACTURER") "free choice")
        (field (name "POWER") "63 mW")
        (field (name "TOLERANCE") "±1 %")
      )
      (libsource (lib "eagle-import") (part "R-EU-R0603-100R"))
    )
    (comp (ref "SW1")
      (value "ATE-1C-V")
      (footprint "eagle-import:ATE-1C_DIPTRONICS")
      (fields (field (name "MANUFACTURER") "Diptronics"))
      (libsource (lib "eagle-import") (part "ATE-1C-V"))
    )
    (comp (ref "T2")
      (value "PMV30ENEA")
      (footprint "eagle-import:SOT-23_NXP")
      (fields (field (name "MANUFACTURER") "Nexperia"))
      (libsource (lib "eagle-import") (part "PMV30ENEA"))
    )
    (comp (ref "T3")
      (value "PMV30ENEA")
      (footprint "eagle-import:SOT-23_NXP")
      (fields (field (name "MANUFACTURER") "Nexperia"))
      (libsource (lib "eagle-import") (part "PMV30ENEA"))
    )
    (comp (ref "T6")
      (value "PMV30ENEA")
      (footprint "eagle-import:SOT-23_NXP")
      (fields (field (name "MANUFACTURER") "Nexperia"))
      (libsource (lib "eagle-import") (part "PMV30ENEA"))
    )
    (comp (ref "T7")
      (value "PMV30ENEA")
      (footprint "eagle-import:SOT-23_NXP")
      (fields (field (name "MANUFACTURER") "Nexperia"))
      (libsource (lib "eagle-import") (part "PMV30ENEA"))
    )
    (comp (ref "T8")
      (value "NX7002AK")
      (footprint "eagle-import:SOT-23_NXP")
      (fields (field (name "MANUFACTURER") "Nexperia"))
      (libsource (lib "eagle-import") (part "NX7002AK"))
    )
    (comp (ref "T10")
      (value "PMV30ENEA")
      (footprint "eagle-import:SOT-23_NXP")
      (fields (field (name "MANUFACTURER") "Nexperia"))
      (libsource (lib "eagle-import") (part "PMV30ENEA"))
    )
    (comp (ref "TP1")
      (value "GND")
      (footprint "eagle-import:TESTPAD_ROUND_1.5MM")
      (libsource (lib "eagle-import") (part "TESTPOINT_ROUND_1.5MM"))
    )
    (comp (ref "TP2")
      (value "+PVCC")
      (footprint "eagle-import:TESTPAD_ROUND_1.5MM")
      (libsource (lib "eagle-import") (part "TESTPOINT_ROUND_1.5MM"))
    )
    (comp (ref "TP3")
      (value "TESTPOINT_ROUND_1.5MM")
      (footprint "eagle-import:TESTPAD_ROUND_1.5MM")
      (libsource (lib "eagle-import") (part "TESTPOINT_ROUND_1.5MM"))
    )
    (comp (ref "TP4")
      (value "TESTPOINT_ROUND_1.5MM")
      (footprint "eagle-import:TESTPAD_ROUND_1.5MM")
      (libsource (lib "eagle-import") (part "TESTPOINT_ROUND_1.5MM"))
    )
    (comp (ref "TP5")
      (value "TESTPOINT_ROUND_1.5MM")
      (footprint "eagle-import:TESTPAD_ROUND_1.5MM")
      (libsource (lib "eagle-import") (part "TESTPOINT_ROUND_1.5MM"))
    )
    (comp (ref "TP6")
      (value "TESTPOINT_ROUND_1.5MM")
      (footprint "eagle-import:TESTPAD_ROUND_1.5MM")
      (libsource (lib "eagle-import") (part "TESTPOINT_ROUND_1.5MM"))
    )
    (comp (ref "TP7")
      (value "TESTPOINT_ROUND_1.5MM")
      (footprint "eagle-import:TESTPAD_ROUND_1.5MM")
      (libsource (lib "eagle-import") (part "TESTPOINT_ROUND_1.5MM"))
    )
    (comp (ref "TP8")
      (value "TESTPOINT_ROUND_1.5MM")
      (footprint "eagle-import:TESTPAD_ROUND_1.5MM")
      (libsource (lib "eagle-import") (part "TESTPOINT_ROUND_1.5MM"))
    )
    (comp (ref "TP9")
      (value "TESTPOINT_ROUND_1.5MM")
      (footprint "eagle-import:TESTPAD_ROUND_1.5MM")
      (libsource (lib "eagle-import") (part "TESTPOINT_ROUND_1.5MM"))
    )
    (comp (ref "TP10")
      (value "TESTPOINT_ROUND_1.5MM")
      (footprint "eagle-import:TESTPAD_ROUND_1.5MM")
      (libsource (lib "eagle-import") (part "TESTPOINT_ROUND_1.5MM"))
    )
    (comp (ref "TP11")
      (value "TESTPOINT_ROUND_1.5MM")
      (footprint "eagle-import:TESTPAD_ROUND_1.5MM")
      (libsource (lib "eagle-import") (part "TESTPOINT_ROUND_1.5MM"))
    )
    (comp (ref "TP12")
      (value "TESTPOINT_ROUND_1.5MM")
      (footprint "eagle-import:TESTPAD_ROUND_1.5MM")
      (libsource (lib "eagle-import") (part "TESTPOINT_ROUND_1.5MM"))
    )
    (comp (ref "TP13")
      (value "SAFETY_SHDN_RST")
      (footprint "eagle-import:TESTPAD_ROUND_1.5MM")
      (libsource (lib "eagle-import") (part "TESTPOINT_ROUND_1.5MM"))
    )
    (comp (ref "TP14")
      (value "TESTPOINT_ROUND_1.5MM")
      (footprint "eagle-import:TESTPAD_ROUND_1.5MM")
      (libsource (lib "eagle-import") (part "TESTPOINT_ROUND_1.5MM"))
    )
    (comp (ref "TP15")
      (value "TESTPOINT_ROUND_1.5MM")
      (footprint "eagle-import:TESTPAD_ROUND_1.5MM")
      (libsource (lib "eagle-import") (part "TESTPOINT_ROUND_1.5MM"))
    )
    (comp (ref "TP16")
      (value "TESTPOINT_ROUND_1.5MM")
      (footprint "eagle-import:TESTPAD_ROUND_1.5MM")
      (libsource (lib "eagle-import") (part "TESTPOINT_ROUND_1.5MM"))
    )
    (comp (ref "TP17")
      (value "TESTPOINT_ROUND_1.5MM")
      (footprint "eagle-import:TESTPAD_ROUND_1.5MM")
      (libsource (lib "eagle-import") (part "TESTPOINT_ROUND_1.5MM"))
    )
    (comp (ref "TP18")
      (value "TESTPOINT_ROUND_1.5MM")
      (footprint "eagle-import:TESTPAD_ROUND_1.5MM")
      (libsource (lib "eagle-import") (part "TESTPOINT_ROUND_1.5MM"))
    )
    (comp (ref "TP19")
      (value "TESTPOINT_ROUND_1.5MM")
      (footprint "eagle-import:TESTPAD_ROUND_1.5MM")
      (libsource (lib "eagle-import") (part "TESTPOINT_ROUND_1.5MM"))
    )
    (comp (ref "TP20")
      (value "TESTPOINT_ROUND_1.5MM")
      (footprint "eagle-import:TESTPAD_ROUND_1.5MM")
      (libsource (lib "eagle-import") (part "TESTPOINT_ROUND_1.5MM"))
    )
    (comp (ref "TP21")
      (value "TESTPOINT_ROUND_1.5MM")
      (footprint "eagle-import:TESTPAD_ROUND_1.5MM")
      (libsource (lib "eagle-import") (part "TESTPOINT_ROUND_1.5MM"))
    )
    (comp (ref "TP22")
      (value "TESTPOINT_ROUND_1.5MM")
      (footprint "eagle-import:TESTPAD_ROUND_1.5MM")
      (libsource (lib "eagle-import") (part "TESTPOINT_ROUND_1.5MM"))
    )
    (comp (ref "TP23")
      (value "TESTPOINT_ROUND_1.5MM")
      (footprint "eagle-import:TESTPAD_ROUND_1.5MM")
      (libsource (lib "eagle-import") (part "TESTPOINT_ROUND_1.5MM"))
    )
    (comp (ref "X1")
      (value "MEC6-120-02-L-DV-A")
      (footprint "eagle-import:MEC6-120-02")
      (fields (field (name "MANUFACTURER") "Samtec"))
      (libsource (lib "eagle-import") (part "MEC6-120-02-L-DV-A"))
    )
    (comp (ref "X2")
      (value "MEC6-120-02-L-DV-A")
      (footprint "eagle-import:MEC6-120-02")
      (fields (field (name "MANUFACTURER") "Samtec"))
      (libsource (lib "eagle-import") (part "MEC6-120-02-L-DV-A"))
    )
    (comp (ref "X3")
      (value "DF37NC-30DS-0.4V")
      (footprint "eagle-import:DF37NC-30DS-0.4V")
      (fields (field (name "MANUFACTURER") "Hirose"))
      (libsource (lib "eagle-import") (part "DF37NC-30DS-0.4V"))
    )
    (comp (ref "X4")
      (value "687112182122")
      (footprint "eagle-import:687112182122_WUERTH")
      (fields (field (name "MANUFACTURER") "Wuerth"))
      (libsource (lib "eagle-import") (part "687112182122"))
    )
    (comp (ref "X5")
      (value "AXE530127")
      (footprint "eagle-import:AXE530127_PANASONIC")
      (fields (field (name "MANUFACTURER") "Panasonic") (field (name "VOLTAGE") "60.0 V"))
      (libsource (lib "eagle-import") (part "AXE530127"))
    )
  )
  (nets
    (net (code "1") (name "+1V2") (class "Default")
      (node (ref "C46") (pin "1") (pinfunction "1_1") (pintype "passive"))
      (node (ref "X1") (pin "20") (pinfunction "20_20") (pintype "passive"))
      (node (ref "X3") (pin "27") (pinfunction "27_27") (pintype "bidirectional"))
    )
    (net (code "2") (name "+1V8") (class "Default")
      (node (ref "C37") (pin "1") (pinfunction "1_1") (pintype "passive"))
      (node (ref "C44") (pin "1") (pinfunction "1_1") (pintype "passive"))
      (node (ref "C45") (pin "1") (pinfunction "1_1") (pintype "passive"))
      (node (ref "C49") (pin "1") (pinfunction "1_1") (pintype "passive"))
      (node (ref "IC12") (pin "5") (pinfunction "VBUS_5") (pintype "input"))
      (node (ref "IC16") (pin "5") (pinfunction "VBUS_5") (pintype "input"))
      (node (ref "IC18") (pin "5") (pinfunction "VBUS_5") (pintype "input"))
      (node (ref "R16") (pin "2") (pinfunction "2_2") (pintype "passive"))
      (node (ref "X1") (pin "18") (pinfunction "18_18") (pintype "passive"))
      (node (ref "X3") (pin "28") (pinfunction "28_28") (pintype "bidirectional"))
    )
    (net (code "3") (name "+2V8") (class "Default")
      (node (ref "C50") (pin "1") (pinfunction "1_1") (pintype "passive"))
      (node (ref "IC19") (pin "5") (pinfunction "VBUS_5") (pintype "input"))
      (node (ref "X1") (pin "16") (pinfunction "16_16") (pintype "passive"))
    )
    (net (code "4") (name "+3V3") (class "Default")
      (node (ref "C11") (pin "1") (pinfunction "1_1") (pintype "passive"))
      (node (ref "C15") (pin "1") (pinfunction "1_1") (pintype "passive"))
      (node (ref "C39") (pin "1") (pinfunction "1_1") (pintype "passive"))
      (node (ref "C51") (pin "1") (pinfunction "1_1") (pintype "passive"))
      (node (ref "D1") (pin "A") (pinfunction "A_A") (pintype "passive"))
      (node (ref "D2") (pin "A") (pinfunction "A_A") (pintype "passive"))
      (node (ref "IC14") (pin "5") (pinfunction "VBUS_5") (pintype "input"))
      (node (ref "IC20") (pin "5") (pinfunction "VBUS_5") (pintype "input"))
      (node (ref "L9") (pin "1") (pinfunction "1_1") (pintype "passive"))
      (node (ref "R17") (pin "2") (pinfunction "2_2") (pintype "passive"))
      (node (ref "R19") (pin "1") (pinfunction "1_1") (pintype "passive"))
      (node (ref "R26") (pin "2") (pinfunction "2_2") (pintype "passive"))
      (node (ref "R27") (pin "2") (pinfunction "2_2") (pintype "passive"))
      (node (ref "R28") (pin "2") (pinfunction "2_2") (pintype "passive"))
      (node (ref "R31") (pin "2") (pinfunction "2_2") (pintype "passive"))
      (node (ref "R40") (pin "2") (pinfunction "2_2") (pintype "passive"))
      (node (ref "R60") (pin "2") (pinfunction "2_2") (pintype "passive"))
      (node (ref "R64") (pin "2") (pinfunction "2_2") (pintype "passive"))
      (node (ref "R72") (pin "1") (pinfunction "1_1") (pintype "passive"))
      (node (ref "R76") (pin "2") (pinfunction "2_2") (pintype "passive"))
      (node (ref "R79") (pin "2") (pinfunction "2_2") (pintype "passive"))
      (node (ref "TP3") (pin "TP") (pinfunction "TP_TP") (pintype "input"))
      (node (ref "X1") (pin "14") (pinfunction "14_14") (pintype "passive"))
    )
    (net (code "5") (name "+3V6") (class "Default")
      (node (ref "C54") (pin "1") (pinfunction "1_1") (pintype "passive"))
      (node (ref "C55") (pin "1") (pinfunction "1_1") (pintype "passive"))
      (node (ref "C56") (pin "1") (pinfunction "1_1") (pintype "passive"))
      (node (ref "L11") (pin "2") (pinfunction "2_2") (pintype "passive"))
      (node (ref "X1") (pin "22") (pinfunction "22_22") (pintype "passive"))
      (node (ref "X5") (pin "1") (pinfunction "1_1") (pintype "passive"))
      (node (ref "X5") (pin "2") (pinfunction "2_2") (pintype "passive"))
      (node (ref "X5") (pin "3") (pinfunction "3_3") (pintype "passive"))
      (node (ref "X5") (pin "4") (pinfunction "4_4") (pintype "passive"))
      (node (ref "X5") (pin "6") (pinfunction "6_6") (pintype "passive"))
      (node (ref "X5") (pin "8") (pinfunction "8_8") (pintype "passive"))
    )
    (net (code "6") (name "+5V") (class "Default")
      (node (ref "C100") (pin "1") (pinfunction "1_1") (pintype "passive"))
      (node (ref "C101") (pin "1") (pinfunction "1_1") (pintype "passive"))
      (node (ref "C102") (pin "1") (pinfunction "1_1") (pintype "passive"))
      (node (ref "C103") (pin "1") (pinfunction "1_1") (pintype "passive"))
      (node (ref "C104") (pin "1") (pinfunction "1_1") (pintype "passive"))
      (node (ref "C105") (pin "1") (pinfunction "1_1") (pintype "passive"))
      (node (ref "C106") (pin "1") (pinfunction "1_1") (pintype "passive"))
      (node (ref "C107") (pin "1") (pinfunction "1_1") (pintype "passive"))
      (node (ref "C108") (pin "1") (pinfunction "1_1") (pintype "passive"))
      (node (ref "C109") (pin "1") (pinfunction "1_1") (pintype "passive"))
      (node (ref "C110") (pin "1") (pinfunction "1_1") (pintype "passive"))
      (node (ref "C111") (pin "1") (pinfunction "1_1") (pintype "passive"))
      (node (ref "C112") (pin "1") (pinfunction "1_1") (pintype "passive"))
      (node (ref "C113") (pin "1") (pinfunction "1_1") (pintype "passive"))
      (node (ref "C114") (pin "1") (pinfunction "1_1") (pintype "passive"))
      (node (ref "C115") (pin "1") (pinfunction "1_1") (pintype "passive"))
      (node (ref "C116") (pin "1") (pinfunction "1_1") (pintype "passive"))
      (node (ref "C117") (pin "1") (pinfunction "1_1") (pintype "passive"))
      (node (ref "C118") (pin "1") (pinfunction "1_1") (pintype "passive"))
      (node (ref "C119") (pin "1") (pinfunction "1_1") (pintype "passive"))
      (node (ref "C120") (pin "1") (pinfunction "1_1") (pintype "passive"))
      (node (ref "C121") (pin "1") (pinfunction "1_1") (pintype "passive"))
      (node (ref "C122") (pin "1") (pinfunction "1_1") (pintype "passive"))
      (node (ref "C123") (pin "1") (pinfunction "1_1") (pintype "passive"))
      (node (ref "C124") (pin "1") (pinfunction "1_1") (pintype "passive"))
      (node (ref "C125") (pin "1") (pinfunction "1_1") (pintype "passive"))
      (node (ref "C126") (pin "1") (pinfunction "1_1") (pintype "passive"))
      (node (ref "C127") (pin "1") (pinfunction "1_1") (pintype "passive"))
      (node (ref "C128") (pin "1") (pinfunction "1_1") (pintype "passive"))
      (node (ref "C129") (pin "1") (pinfunction "1_1") (pintype "passive"))
      (node (ref "C130") (pin "1") (pinfunction "1_1") (pintype "passive"))
      (node (ref "C131") (pin "1") (pinfunction "1_1") (pintype "passive"))
      (node (ref "C132") (pin "1") (pinfunction "1_1") (pintype "passive"))
      (node (ref "C133") (pin "1") (pinfunction "1_1") (pintype "passive"))
      (node (ref "C134") (pin "1") (pinfunction "1_1") (pintype "passive"))
      (node (ref "C135") (pin "1") (pinfunction "1_1") (pintype "passive"))
      (node (ref "C136") (pin "1") (pinfunction "1_1") (pintype "passive"))
      (node (ref "C137") (pin "1") (pinfunction "1_1") (pintype "passive"))
      (node (ref "C138") (pin "1") (pinfunction "1_1") (pintype "passive"))
      (node (ref "C139") (pin "1") (pinfunction "1_1") (pintype "passive"))
      (node (ref "C140") (pin "1") (pinfunction "1_1") (pintype "passive"))
      (node (ref "C141") (pin "1") (pinfunction "1_1") (pintype "passive"))
      (node (ref "C142") (pin "1") (pinfunction "1_1") (pintype "passive"))
      (node (ref "C143") (pin "1") (pinfunction "1_1") (pintype "passive"))
      (node (ref "C144") (pin "1") (pinfunction "1_1") (pintype "passive"))
      (node (ref "C145") (pin "1") (pinfunction "1_1") (pintype "passive"))
      (node (ref "C146") (pin "1") (pinfunction "1_1") (pintype "passive"))
      (node (ref "C147") (pin "1") (pinfunction "1_1") (pintype "passive"))
      (node (ref "C148") (pin "1") (pinfunction "1_1") (pintype "passive"))
      (node (ref "C149") (pin "1") (pinfunction "1_1") (pintype "passive"))
      (node (ref "C150") (pin "1") (pinfunction "1_1") (pintype "passive"))
      (node (ref "C151") (pin "1") (pinfunction "1_1") (pintype "passive"))
      (node (ref "C152") (pin "1") (pinfunction "1_1") (pintype "passive"))
      (node (ref "C153") (pin "1") (pinfunction "1_1") (pintype "passive"))
      (node (ref "C154") (pin "1") (pinfunction "1_1") (pintype "passive"))
      (node (ref "C155") (pin "1") (pinfunction "1_1") (pintype "passive"))
      (node (ref "C156") (pin "1") (pinfunction "1_1") (pintype "passive"))
      (node (ref "C157") (pin "1") (pinfunction "1_1") (pintype "passive"))
      (node (ref "C158") (pin "1") (pinfunction "1_1") (pintype "passive"))
      (node (ref "C159") (pin "1") (pinfunction "1_1") (pintype "passive"))
      (node (ref "C162") (pin "1") (pinfunction "1_1") (pintype "passive"))
      (node (ref "C164") (pin "1") (pinfunction "1_1") (pintype "passive"))
      (node (ref "C165") (pin "1") (pinfunction "1_1") (pintype "passive"))
      (node (ref "C166") (pin "1") (pinfunction "1_1") (pintype "passive"))
      (node (ref "C167") (pin "1") (pinfunction "1_1") (pintype "passive"))
      (node (ref "C168") (pin "1") (pinfunction "1_1") (pintype "passive"))
      (node (ref "C169") (pin "1") (pinfunction "1_1") (pintype "passive"))
      (node (ref "C170") (pin "1") (pinfunction "1_1") (pintype "passive"))
      (node (ref "C171") (pin "1") (pinfunction "1_1") (pintype "passive"))
      (node (ref "C172") (pin "1") (pinfunction "1_1") (pintype "passive"))
      (node (ref "C173") (pin "1") (pinfunction "1_1") (pintype "passive"))
      (node (ref "C174") (pin "1") (pinfunction "1_1") (pintype "passive"))
      (node (ref "C175") (pin "1") (pinfunction "1_1") (pintype "passive"))
      (node (ref "C176") (pin "1") (pinfunction "1_1") (pintype "passive"))
      (node (ref "C177") (pin "1") (pinfunction "1_1") (pintype "passive"))
      (node (ref "C178") (pin "1") (pinfunction "1_1") (pintype "passive"))
      (node (ref "C179") (pin "1") (pinfunction "1_1") (pintype "passive"))
      (node (ref "C180") (pin "1") (pinfunction "1_1") (pintype "passive"))
      (node (ref "C181") (pin "1") (pinfunction "1_1") (pintype "passive"))
      (node (ref "C182") (pin "1") (pinfunction "1_1") (pintype "passive"))
      (node (ref "C183") (pin "1") (pinfunction "1_1") (pintype "passive"))
      (node (ref "C184") (pin "1") (pinfunction "1_1") (pintype "passive"))
      (node (ref "C185") (pin "1") (pinfunction "1_1") (pintype "passive"))
      (node (ref "C186") (pin "1") (pinfunction "1_1") (pintype "passive"))
      (node (ref "C187") (pin "1") (pinfunction "1_1") (pintype "passive"))
      (node (ref "C188") (pin "1") (pinfunction "1_1") (pintype "passive"))
      (node (ref "C189") (pin "1") (pinfunction "1_1") (pintype "passive"))
      (node (ref "C190") (pin "1") (pinfunction "1_1") (pintype "passive"))
      (node (ref "C191") (pin "1") (pinfunction "1_1") (pintype "passive"))
      (node (ref "C192") (pin "1") (pinfunction "1_1") (pintype "passive"))
      (node (ref "C193") (pin "1") (pinfunction "1_1") (pintype "passive"))
      (node (ref "C194") (pin "1") (pinfunction "1_1") (pintype "passive"))
      (node (ref "C195") (pin "1") (pinfunction "1_1") (pintype "passive"))
      (node (ref "C196") (pin "1") (pinfunction "1_1") (pintype "passive"))
      (node (ref "C197") (pin "1") (pinfunction "1_1") (pintype "passive"))
      (node (ref "C198") (pin "1") (pinfunction "1_1") (pintype "passive"))
      (node (ref "C199") (pin "1") (pinfunction "1_1") (pintype "passive"))
      (node (ref "C200") (pin "1") (pinfunction "1_1") (pintype "passive"))
      (node (ref "C201") (pin "1") (pinfunction "1_1") (pintype "passive"))
      (node (ref "C202") (pin "1") (pinfunction "1_1") (pintype "passive"))
      (node (ref "C203") (pin "1") (pinfunction "1_1") (pintype "passive"))
      (node (ref "C204") (pin "1") (pinfunction "1_1") (pintype "passive"))
      (node (ref "C205") (pin "1") (pinfunction "1_1") (pintype "passive"))
      (node (ref "C206") (pin "1") (pinfunction "1_1") (pintype "passive"))
      (node (ref "C207") (pin "1") (pinfunction "1_1") (pintype "passive"))
      (node (ref "C208") (pin "1") (pinfunction "1_1") (pintype "passive"))
      (node (ref "C209") (pin "1") (pinfunction "1_1") (pintype "passive"))
      (node (ref "C210") (pin "1") (pinfunction "1_1") (pintype "passive"))
      (node (ref "C211") (pin "1") (pinfunction "1_1") (pintype "passive"))
      (node (ref "C212") (pin "1") (pinfunction "1_1") (pintype "passive"))
      (node (ref "C213") (pin "1") (pinfunction "1_1") (pintype "passive"))
      (node (ref "C214") (pin "1") (pinfunction "1_1") (pintype "passive"))
      (node (ref "C215") (pin "1") (pinfunction "1_1") (pintype "passive"))
      (node (ref "C216") (pin "1") (pinfunction "1_1") (pintype "passive"))
      (node (ref "C217") (pin "1") (pinfunction "1_1") (pintype "passive"))
      (node (ref "C218") (pin "1") (pinfunction "1_1") (pintype "passive"))
      (node (ref "C219") (pin "1") (pinfunction "1_1") (pintype "passive"))
      (node (ref "C220") (pin "1") (pinfunction "1_1") (pintype "passive"))
      (node (ref "C221") (pin "1") (pinfunction "1_1") (pintype "passive"))
      (node (ref "C222") (pin "1") (pinfunction "1_1") (pintype "passive"))
      (node (ref "C223") (pin "1") (pinfunction "1_1") (pintype "passive"))
      (node (ref "C224") (pin "1") (pinfunction "1_1") (pintype "passive"))
      (node (ref "C225") (pin "1") (pinfunction "1_1") (pintype "passive"))
      (node (ref "C226") (pin "1") (pinfunction "1_1") (pintype "passive"))
      (node (ref "C227") (pin "1") (pinfunction "1_1") (pintype "passive"))
      (node (ref "C228") (pin "1") (pinfunction "1_1") (pintype "passive"))
      (node (ref "C229") (pin "1") (pinfunction "1_1") (pintype "passive"))
      (node (ref "C230") (pin "1") (pinfunction "1_1") (pintype "passive"))
      (node (ref "C231") (pin "1") (pinfunction "1_1") (pintype "passive"))
      (node (ref "C232") (pin "1") (pinfunction "1_1") (pintype "passive"))
      (node (ref "C233") (pin "1") (pinfunction "1_1") (pintype "passive"))
      (node (ref "C234") (pin "1") (pinfunction "1_1") (pintype "passive"))
      (node (ref "C235") (pin "1") (pinfunction "1_1") (pintype "passive"))
      (node (ref "C236") (pin "1") (pinfunction "1_1") (pintype "passive"))
      (node (ref "C237") (pin "1") (pinfunction "1_1") (pintype "passive"))
      (node (ref "C238") (pin "1") (pinfunction "1_1") (pintype "passive"))
      (node (ref "C239") (pin "1") (pinfunction "1_1") (pintype "passive"))
      (node (ref "C240") (pin "1") (pinfunction "1_1") (pintype "passive"))
      (node (ref "C241") (pin "1") (pinfunction "1_1") (pintype "passive"))
      (node (ref "C242") (pin "1") (pinfunction "1_1") (pintype "passive"))
      (node (ref "C243") (pin "1") (pinfunction "1_1") (pintype "passive"))
      (node (ref "C244") (pin "1") (pinfunction "1_1") (pintype "passive"))
      (node (ref "C245") (pin "1") (pinfunction "1_1") (pintype "passive"))
      (node (ref "C246") (pin "1") (pinfunction "1_1") (pintype "passive"))
      (node (ref "C247") (pin "1") (pinfunction "1_1") (pintype "passive"))
      (node (ref "C248") (pin "1") (pinfunction "1_1") (pintype "passive"))
      (node (ref "C249") (pin "1") (pinfunction "1_1") (pintype "passive"))
      (node (ref "C250") (pin "1") (pinfunction "1_1") (pintype "passive"))
      (node (ref "C251") (pin "1") (pinfunction "1_1") (pintype "passive"))
      (node (ref "C252") (pin "1") (pinfunction "1_1") (pintype "passive"))
      (node (ref "C253") (pin "1") (pinfunction "1_1") (pintype "passive"))
      (node (ref "C254") (pin "1") (pinfunction "1_1") (pintype "passive"))
      (node (ref "C255") (pin "1") (pinfunction "1_1") (pintype "passive"))
      (node (ref "C256") (pin "1") (pinfunction "1_1") (pintype "passive"))
      (node (ref "C257") (pin "1") (pinfunction "1_1") (pintype "passive"))
      (node (ref "C258") (pin "1") (pinfunction "1_1") (pintype "passive"))
      (node (ref "C259") (pin "1") (pinfunction "1_1") (pintype "passive"))
      (node (ref "C260") (pin "1") (pinfunction "1_1") (pintype "passive"))
      (node (ref "C261") (pin "1") (pinfunction "1_1") (pintype "passive"))
      (node (ref "C262") (pin "1") (pinfunction "1_1") (pintype "passive"))
      (node (ref "C263") (pin "1") (pinfunction "1_1") (pintype "passive"))
      (node (ref "C264") (pin "1") (pinfunction "1_1") (pintype "passive"))
      (node (ref "C265") (pin "1") (pinfunction "1_1") (pintype "passive"))
      (node (ref "C266") (pin "1") (pinfunction "1_1") (pintype "passive"))
      (node (ref "C270") (pin "1") (pinfunction "1_1") (pintype "passive"))
      (node (ref "C272") (pin "1") (pinfunction "1_1") (pintype "passive"))
      (node (ref "C280") (pin "1") (pinfunction "1_1") (pintype "passive"))
      (node (ref "C281") (pin "1") (pinfunction "1_1") (pintype "passive"))
      (node (ref "C282") (pin "1") (pinfunction "1_1") (pintype "passive"))
      (node (ref "C283") (pin "1") (pinfunction "1_1") (pintype "passive"))
      (node (ref "C284") (pin "1") (pinfunction "1_1") (pintype "passive"))
      (node (ref "C285") (pin "1") (pinfunction "1_1") (pintype "passive"))
      (node (ref "C286") (pin "1") (pinfunction "1_1") (pintype "passive"))
      (node (ref "C287") (pin "1") (pinfunction "1_1") (pintype "passive"))
      (node (ref "C288") (pin "1") (pinfunction "1_1") (pintype "passive"))
      (node (ref "C289") (pin "1") (pinfunction "1_1") (pintype "passive"))
      (node (ref "C290") (pin "1") (pinfunction "1_1") (pintype "passive"))
      (node (ref "C291") (pin "1") (pinfunction "1_1") (pintype "passive"))
      (node (ref "C292") (pin "1") (pinfunction "1_1") (pintype "passive"))
      (node (ref "C293") (pin "1") (pinfunction "1_1") (pintype "passive"))
      (node (ref "C294") (pin "1") (pinfunction "1_1") (pintype "passive"))
      (node (ref "C295") (pin "1") (pinfunction "1_1") (pintype "passive"))
      (node (ref "C296") (pin "1") (pinfunction "1_1") (pintype "passive"))
      (node (ref "C297") (pin "1") (pinfunction "1_1") (pintype "passive"))
      (node (ref "C298") (pin "1") (pinfunction "1_1") (pintype "passive"))
      (node (ref "C299") (pin "1") (pinfunction "1_1") (pintype "passive"))
      (node (ref "C300") (pin "1") (pinfunction "1_1") (pintype "passive"))
      (node (ref "C301") (pin "1") (pinfunction "1_1") (pintype "passive"))
      (node (ref "C302") (pin "1") (pinfunction "1_1") (pintype "passive"))
      (node (ref "C303") (pin "1") (pinfunction "1_1") (pintype "passive"))
      (node (ref "C304") (pin "1") (pinfunction "1_1") (pintype "passive"))
      (node (ref "C305") (pin "1") (pinfunction "1_1") (pintype "passive"))
      (node (ref "C306") (pin "1") (pinfunction "1_1") (pintype "passive"))
      (node (ref "C307") (pin "1") (pinfunction "1_1") (pintype "passive"))
      (node (ref "C308") (pin "1") (pinfunction "1_1") (pintype "passive"))
      (node (ref "C309") (pin "1") (pinfunction "1_1") (pintype "passive"))
      (node (ref "C310") (pin "1") (pinfunction "1_1") (pintype "passive"))
      (node (ref "C311") (pin "1") (pinfunction "1_1") (pintype "passive"))
      (node (ref "C312") (pin "1") (pinfunction "1_1") (pintype "passive"))
      (node (ref "C313") (pin "1") (pinfunction "1_1") (pintype "passive"))
      (node (ref "C314") (pin "1") (pinfunction "1_1") (pintype "passive"))
      (node (ref "C315") (pin "1") (pinfunction "1_1") (pintype "passive"))
      (node (ref "C316") (pin "1") (pinfunction "1_1") (pintype "passive"))
      (node (ref "C317") (pin "1") (pinfunction "1_1") (pintype "passive"))
      (node (ref "C318") (pin "1") (pinfunction "1_1") (pintype "passive"))
      (node (ref "C319") (pin "1") (pinfunction "1_1") (pintype "passive"))
      (node (ref "C320") (pin "1") (pinfunction "1_1") (pintype "passive"))
      (node (ref "C321") (pin "1") (pinfunction "1_1") (pintype "passive"))
      (node (ref "C322") (pin "1") (pinfunction "1_1") (pintype "passive"))
      (node (ref "C323") (pin "1") (pinfunction "1_1") (pintype "passive"))
      (node (ref "C324") (pin "1") (pinfunction "1_1") (pintype "passive"))
      (node (ref "C325") (pin "1") (pinfunction "1_1") (pintype "passive"))
      (node (ref "C326") (pin "1") (pinfunction "1_1") (pintype "passive"))
      (node (ref "C327") (pin "1") (pinfunction "1_1") (pintype "passive"))
      (node (ref "C328") (pin "1") (pinfunction "1_1") (pintype "passive"))
      (node (ref "C329") (pin "1") (pinfunction "1_1") (pintype "passive"))
      (node (ref "C330") (pin "1") (pinfunction "1_1") (pintype "passive"))
      (node (ref "C331") (pin "1") (pinfunction "1_1") (pintype "passive"))
      (node (ref "C332") (pin "1") (pinfunction "1_1") (pintype "passive"))
      (node (ref "C48") (pin "1") (pinfunction "1_1") (pintype "passive"))
      (node (ref "IC100") (pin "2") (pinfunction "VDD_2") (pintype "input"))
      (node (ref "IC101") (pin "2") (pinfunction "VDD_2") (pintype "input"))
      (node (ref "IC102") (pin "2") (pinfunction "VDD_2") (pintype "input"))
      (node (ref "IC103") (pin "2") (pinfunction "VDD_2") (pintype "input"))
      (node (ref "IC104") (pin "2") (pinfunction "VDD_2") (pintype "input"))
      (node (ref "IC105") (pin "2") (pinfunction "VDD_2") (pintype "input"))
      (node (ref "IC106") (pin "2") (pinfunction "VDD_2") (pintype "input"))
      (node (ref "IC107") (pin "2") (pinfunction "VDD_2") (pintype "input"))
      (node (ref "IC108") (pin "2") (pinfunction "VDD_2") (pintype "input"))
      (node (ref "IC109") (pin "2") (pinfunction "VDD_2") (pintype "input"))
      (node (ref "IC110") (pin "2") (pinfunction "VDD_2") (pintype "input"))
      (node (ref "IC111") (pin "2") (pinfunction "VDD_2") (pintype "input"))
      (node (ref "IC112") (pin "2") (pinfunction "VDD_2") (pintype "input"))
      (node (ref "IC113") (pin "2") (pinfunction "VDD_2") (pintype "input"))
      (node (ref "IC114") (pin "2") (pinfunction "VDD_2") (pintype "input"))
      (node (ref "IC115") (pin "2") (pinfunction "VDD_2") (pintype "input"))
      (node (ref "IC116") (pin "2") (pinfunction "VDD_2") (pintype "input"))
      (node (ref "IC117") (pin "2") (pinfunction "VDD_2") (pintype "input"))
      (node (ref "IC118") (pin "2") (pinfunction "VDD_2") (pintype "input"))
      (node (ref "IC119") (pin "2") (pinfunction "VDD_2") (pintype "input"))
      (node (ref "IC120") (pin "2") (pinfunction "VDD_2") (pintype "input"))
      (node (ref "IC121") (pin "2") (pinfunction "VDD_2") (pintype "input"))
      (node (ref "IC122") (pin "2") (pinfunction "VDD_2") (pintype "input"))
      (node (ref "IC123") (pin "2") (pinfunction "VDD_2") (pintype "input"))
      (node (ref "IC124") (pin "2") (pinfunction "VDD_2") (pintype "input"))
      (node (ref "IC125") (pin "2") (pinfunction "VDD_2") (pintype "input"))
      (node (ref "IC126") (pin "2") (pinfunction "VDD_2") (pintype "input"))
      (node (ref "IC127") (pin "2") (pinfunction "VDD_2") (pintype "input"))
      (node (ref "IC128") (pin "2") (pinfunction "VDD_2") (pintype "input"))
      (node (ref "IC129") (pin "2") (pinfunction "VDD_2") (pintype "input"))
      (node (ref "IC130") (pin "2") (pinfunction "VDD_2") (pintype "input"))
      (node (ref "IC131") (pin "2") (pinfunction "VDD_2") (pintype "input"))
      (node (ref "IC132") (pin "2") (pinfunction "VDD_2") (pintype "input"))
      (node (ref "IC133") (pin "2") (pinfunction "VDD_2") (pintype "input"))
      (node (ref "IC134") (pin "2") (pinfunction "VDD_2") (pintype "input"))
      (node (ref "IC135") (pin "2") (pinfunction "VDD_2") (pintype "input"))
      (node (ref "IC136") (pin "2") (pinfunction "VDD_2") (pintype "input"))
      (node (ref "IC137") (pin "2") (pinfunction "VDD_2") (pintype "input"))
      (node (ref "IC138") (pin "2") (pinfunction "VDD_2") (pintype "input"))
      (node (ref "IC139") (pin "2") (pinfunction "VDD_2") (pintype "input"))
      (node (ref "IC140") (pin "2") (pinfunction "VDD_2") (pintype "input"))
      (node (ref "IC141") (pin "2") (pinfunction "VDD_2") (pintype "input"))
      (node (ref "IC142") (pin "2") (pinfunction "VDD_2") (pintype "input"))
      (node (ref "IC143") (pin "2") (pinfunction "VDD_2") (pintype "input"))
      (node (ref "IC144") (pin "2") (pinfunction "VDD_2") (pintype "input"))
      (node (ref "IC145") (pin "2") (pinfunction "VDD_2") (pintype "input"))
      (node (ref "IC146") (pin "2") (pinfunction "VDD_2") (pintype "input"))
      (node (ref "IC147") (pin "2") (pinfunction "VDD_2") (pintype "input"))
      (node (ref "IC148") (pin "2") (pinfunction "VDD_2") (pintype "input"))
      (node (ref "IC149") (pin "2") (pinfunction "VDD_2") (pintype "input"))
      (node (ref "IC150") (pin "2") (pinfunction "VDD_2") (pintype "input"))
      (node (ref "IC151") (pin "2") (pinfunction "VDD_2") (pintype "input"))
      (node (ref "IC152") (pin "2") (pinfunction "VDD_2") (pintype "input"))
      (node (ref "IC153") (pin "2") (pinfunction "VDD_2") (pintype "input"))
      (node (ref "IC154") (pin "2") (pinfunction "VDD_2") (pintype "input"))
      (node (ref "IC155") (pin "2") (pinfunction "VDD_2") (pintype "input"))
      (node (ref "IC156") (pin "2") (pinfunction "VDD_2") (pintype "input"))
      (node (ref "IC157") (pin "2") (pinfunction "VDD_2") (pintype "input"))
      (node (ref "IC158") (pin "2") (pinfunction "VDD_2") (pintype "input"))
      (node (ref "IC159") (pin "2") (pinfunction "VDD_2") (pintype "input"))
      (node (ref "IC160") (pin "2") (pinfunction "VDD_2") (pintype "input"))
      (node (ref "IC161") (pin "2") (pinfunction "VDD_2") (pintype "input"))
      (node (ref "IC162") (pin "2") (pinfunction "VDD_2") (pintype "input"))
      (node (ref "IC163") (pin "2") (pinfunction "VDD_2") (pintype "input"))
      (node (ref "IC164") (pin "2") (pinfunction "VDD_2") (pintype "input"))
      (node (ref "IC165") (pin "2") (pinfunction "VDD_2") (pintype "input"))
      (node (ref "IC166") (pin "2") (pinfunction "VDD_2") (pintype "input"))
      (node (ref "IC167") (pin "2") (pinfunction "VDD_2") (pintype "input"))
      (node (ref "IC168") (pin "2") (pinfunction "VDD_2") (pintype "input"))
      (node (ref "IC169") (pin "2") (pinfunction "VDD_2") (pintype "input"))
      (node (ref "IC17") (pin "5") (pinfunction "VBUS_5") (pintype "input"))
      (node (ref "IC170") (pin "2") (pinfunction "VDD_2") (pintype "input"))
      (node (ref "IC171") (pin "2") (pinfunction "VDD_2") (pintype "input"))
      (node (ref "IC172") (pin "2") (pinfunction "VDD_2") (pintype "input"))
      (node (ref "IC173") (pin "2") (pinfunction "VDD_2") (pintype "input"))
      (node (ref "IC174") (pin "2") (pinfunction "VDD_2") (pintype "input"))
      (node (ref "IC175") (pin "2") (pinfunction "VDD_2") (pintype "input"))
      (node (ref "IC176") (pin "2") (pinfunction "VDD_2") (pintype "input"))
      (node (ref "IC177") (pin "2") (pinfunction "VDD_2") (pintype "input"))
      (node (ref "IC178") (pin "2") (pinfunction "VDD_2") (pintype "input"))
      (node (ref "IC179") (pin "2") (pinfunction "VDD_2") (pintype "input"))
      (node (ref "IC180") (pin "2") (pinfunction "VDD_2") (pintype "input"))
      (node (ref "IC181") (pin "2") (pinfunction "VDD_2") (pintype "input"))
      (node (ref "IC182") (pin "2") (pinfunction "VDD_2") (pintype "input"))
      (node (ref "IC183") (pin "2") (pinfunction "VDD_2") (pintype "input"))
      (node (ref "IC184") (pin "2") (pinfunction "VDD_2") (pintype "input"))
      (node (ref "IC185") (pin "2") (pinfunction "VDD_2") (pintype "input"))
      (node (ref "IC186") (pin "2") (pinfunction "VDD_2") (pintype "input"))
      (node (ref "IC187") (pin "2") (pinfunction "VDD_2") (pintype "input"))
      (node (ref "IC188") (pin "2") (pinfunction "VDD_2") (pintype "input"))
      (node (ref "IC189") (pin "2") (pinfunction "VDD_2") (pintype "input"))
      (node (ref "IC190") (pin "2") (pinfunction "VDD_2") (pintype "input"))
      (node (ref "IC191") (pin "2") (pinfunction "VDD_2") (pintype "input"))
      (node (ref "IC192") (pin "2") (pinfunction "VDD_2") (pintype "input"))
      (node (ref "IC193") (pin "2") (pinfunction "VDD_2") (pintype "input"))
      (node (ref "IC194") (pin "2") (pinfunction "VDD_2") (pintype "input"))
      (node (ref "IC195") (pin "2") (pinfunction "VDD_2") (pintype "input"))
      (node (ref "IC196") (pin "2") (pinfunction "VDD_2") (pintype "input"))
      (node (ref "IC197") (pin "2") (pinfunction "VDD_2") (pintype "input"))
      (node (ref "IC198") (pin "2") (pinfunction "VDD_2") (pintype "input"))
      (node (ref "IC199") (pin "2") (pinfunction "VDD_2") (pintype "input"))
      (node (ref "IC200") (pin "2") (pinfunction "VDD_2") (pintype "input"))
      (node (ref "IC201") (pin "2") (pinfunction "VDD_2") (pintype "input"))
      (node (ref "IC202") (pin "2") (pinfunction "VDD_2") (pintype "input"))
      (node (ref "IC203") (pin "2") (pinfunction "VDD_2") (pintype "input"))
      (node (ref "IC204") (pin "2") (pinfunction "VDD_2") (pintype "input"))
      (node (ref "IC205") (pin "2") (pinfunction "VDD_2") (pintype "input"))
      (node (ref "IC206") (pin "2") (pinfunction "VDD_2") (pintype "input"))
      (node (ref "IC207") (pin "2") (pinfunction "VDD_2") (pintype "input"))
      (node (ref "IC208") (pin "2") (pinfunction "VDD_2") (pintype "input"))
      (node (ref "IC209") (pin "2") (pinfunction "VDD_2") (pintype "input"))
      (node (ref "IC210") (pin "2") (pinfunction "VDD_2") (pintype "input"))
      (node (ref "IC211") (pin "2") (pinfunction "VDD_2") (pintype "input"))
      (node (ref "IC212") (pin "2") (pinfunction "VDD_2") (pintype "input"))
      (node (ref "IC213") (pin "2") (pinfunction "VDD_2") (pintype "input"))
      (node (ref "IC214") (pin "2") (pinfunction "VDD_2") (pintype "input"))
      (node (ref "IC215") (pin "2") (pinfunction "VDD_2") (pintype "input"))
      (node (ref "IC216") (pin "2") (pinfunction "VDD_2") (pintype "input"))
      (node (ref "IC217") (pin "2") (pinfunction "VDD_2") (pintype "input"))
      (node (ref "IC218") (pin "2") (pinfunction "VDD_2") (pintype "input"))
      (node (ref "IC219") (pin "2") (pinfunction "VDD_2") (pintype "input"))
      (node (ref "IC220") (pin "2") (pinfunction "VDD_2") (pintype "input"))
      (node (ref "IC221") (pin "2") (pinfunction "VDD_2") (pintype "input"))
      (node (ref "IC222") (pin "2") (pinfunction "VDD_2") (pintype "input"))
      (node (ref "IC223") (pin "2") (pinfunction "VDD_2") (pintype "input"))
      (node (ref "IC224") (pin "2") (pinfunction "VDD_2") (pintype "input"))
      (node (ref "IC225") (pin "2") (pinfunction "VDD_2") (pintype "input"))
      (node (ref "IC226") (pin "2") (pinfunction "VDD_2") (pintype "input"))
      (node (ref "IC227") (pin "2") (pinfunction "VDD_2") (pintype "input"))
      (node (ref "IC228") (pin "2") (pinfunction "VDD_2") (pintype "input"))
      (node (ref "IC229") (pin "2") (pinfunction "VDD_2") (pintype "input"))
      (node (ref "IC230") (pin "2") (pinfunction "VDD_2") (pintype "input"))
      (node (ref "IC231") (pin "2") (pinfunction "VDD_2") (pintype "input"))
      (node (ref "IC232") (pin "2") (pinfunction "VDD_2") (pintype "input"))
      (node (ref "IC233") (pin "2") (pinfunction "VDD_2") (pintype "input"))
      (node (ref "IC234") (pin "2") (pinfunction "VDD_2") (pintype "input"))
      (node (ref "IC235") (pin "2") (pinfunction "VDD_2") (pintype "input"))
      (node (ref "IC236") (pin "2") (pinfunction "VDD_2") (pintype "input"))
      (node (ref "IC237") (pin "2") (pinfunction "VDD_2") (pintype "input"))
      (node (ref "IC238") (pin "2") (pinfunction "VDD_2") (pintype "input"))
      (node (ref "IC239") (pin "2") (pinfunction "VDD_2") (pintype "input"))
      (node (ref "IC240") (pin "2") (pinfunction "VDD_2") (pintype "input"))
      (node (ref "IC241") (pin "2") (pinfunction "VDD_2") (pintype "input"))
      (node (ref "IC242") (pin "2") (pinfunction "VDD_2") (pintype "input"))
      (node (ref "IC243") (pin "2") (pinfunction "VDD_2") (pintype "input"))
      (node (ref "IC244") (pin "2") (pinfunction "VDD_2") (pintype "input"))
      (node (ref "IC245") (pin "2") (pinfunction "VDD_2") (pintype "input"))
      (node (ref "IC246") (pin "2") (pinfunction "VDD_2") (pintype "input"))
      (node (ref "IC247") (pin "2") (pinfunction "VDD_2") (pintype "input"))
      (node (ref "IC248") (pin "2") (pinfunction "VDD_2") (pintype "input"))
      (node (ref "IC249") (pin "2") (pinfunction "VDD_2") (pintype "input"))
      (node (ref "IC250") (pin "2") (pinfunction "VDD_2") (pintype "input"))
      (node (ref "IC251") (pin "2") (pinfunction "VDD_2") (pintype "input"))
      (node (ref "IC252") (pin "2") (pinfunction "VDD_2") (pintype "input"))
      (node (ref "IC253") (pin "2") (pinfunction "VDD_2") (pintype "input"))
      (node (ref "IC254") (pin "2") (pinfunction "VDD_2") (pintype "input"))
      (node (ref "IC255") (pin "2") (pinfunction "VDD_2") (pintype "input"))
      (node (ref "IC256") (pin "2") (pinfunction "VDD_2") (pintype "input"))
      (node (ref "IC257") (pin "2") (pinfunction "VDD_2") (pintype "input"))
      (node (ref "IC258") (pin "2") (pinfunction "VDD_2") (pintype "input"))
      (node (ref "IC259") (pin "2") (pinfunction "VDD_2") (pintype "input"))
      (node (ref "IC260") (pin "2") (pinfunction "VDD_2") (pintype "input"))
      (node (ref "IC261") (pin "2") (pinfunction "VDD_2") (pintype "input"))
      (node (ref "IC262") (pin "2") (pinfunction "VDD_2") (pintype "input"))
      (node (ref "IC263") (pin "2") (pinfunction "VDD_2") (pintype "input"))
      (node (ref "IC264") (pin "2") (pinfunction "VDD_2") (pintype "input"))
      (node (ref "IC265") (pin "2") (pinfunction "VDD_2") (pintype "input"))
      (node (ref "IC266") (pin "2") (pinfunction "VDD_2") (pintype "input"))
      (node (ref "IC267") (pin "2") (pinfunction "VDD_2") (pintype "input"))
      (node (ref "IC268") (pin "2") (pinfunction "VDD_2") (pintype "input"))
      (node (ref "IC269") (pin "2") (pinfunction "VDD_2") (pintype "input"))
      (node (ref "IC270") (pin "2") (pinfunction "VDD_2") (pintype "input"))
      (node (ref "IC271") (pin "2") (pinfunction "VDD_2") (pintype "input"))
      (node (ref "IC272") (pin "2") (pinfunction "VDD_2") (pintype "input"))
      (node (ref "IC273") (pin "2") (pinfunction "VDD_2") (pintype "input"))
      (node (ref "IC274") (pin "2") (pinfunction "VDD_2") (pintype "input"))
      (node (ref "IC275") (pin "2") (pinfunction "VDD_2") (pintype "input"))
      (node (ref "IC276") (pin "2") (pinfunction "VDD_2") (pintype "input"))
      (node (ref "IC277") (pin "2") (pinfunction "VDD_2") (pintype "input"))
      (node (ref "IC278") (pin "2") (pinfunction "VDD_2") (pintype "input"))
      (node (ref "IC279") (pin "2") (pinfunction "VDD_2") (pintype "input"))
      (node (ref "IC280") (pin "2") (pinfunction "VDD_2") (pintype "input"))
      (node (ref "IC281") (pin "2") (pinfunction "VDD_2") (pintype "input"))
      (node (ref "IC282") (pin "2") (pinfunction "VDD_2") (pintype "input"))
      (node (ref "IC283") (pin "2") (pinfunction "VDD_2") (pintype "input"))
      (node (ref "IC284") (pin "2") (pinfunction "VDD_2") (pintype "input"))
      (node (ref "IC285") (pin "2") (pinfunction "VDD_2") (pintype "input"))
      (node (ref "IC286") (pin "2") (pinfunction "VDD_2") (pintype "input"))
      (node (ref "IC287") (pin "2") (pinfunction "VDD_2") (pintype "input"))
      (node (ref "IC288") (pin "2") (pinfunction "VDD_2") (pintype "input"))
      (node (ref "IC289") (pin "2") (pinfunction "VDD_2") (pintype "input"))
      (node (ref "IC290") (pin "2") (pinfunction "VDD_2") (pintype "input"))
      (node (ref "IC291") (pin "2") (pinfunction "VDD_2") (pintype "input"))
      (node (ref "IC292") (pin "2") (pinfunction "VDD_2") (pintype "input"))
      (node (ref "IC293") (pin "2") (pinfunction "VDD_2") (pintype "input"))
      (node (ref "IC294") (pin "2") (pinfunction "VDD_2") (pintype "input"))
      (node (ref "IC295") (pin "2") (pinfunction "VDD_2") (pintype "input"))
      (node (ref "IC296") (pin "2") (pinfunction "VDD_2") (pintype "input"))
      (node (ref "IC297") (pin "2") (pinfunction "VDD_2") (pintype "input"))
      (node (ref "IC298") (pin "2") (pinfunction "VDD_2") (pintype "input"))
      (node (ref "IC299") (pin "2") (pinfunction "VDD_2") (pintype "input"))
      (node (ref "IC300") (pin "2") (pinfunction "VDD_2") (pintype "input"))
      (node (ref "IC301") (pin "2") (pinfunction "VDD_2") (pintype "input"))
      (node (ref "IC302") (pin "2") (pinfunction "VDD_2") (pintype "input"))
      (node (ref "IC303") (pin "2") (pinfunction "VDD_2") (pintype "input"))
      (node (ref "IC304") (pin "2") (pinfunction "VDD_2") (pintype "input"))
      (node (ref "IC305") (pin "2") (pinfunction "VDD_2") (pintype "input"))
      (node (ref "IC306") (pin "2") (pinfunction "VDD_2") (pintype "input"))
      (node (ref "IC307") (pin "2") (pinfunction "VDD_2") (pintype "input"))
      (node (ref "IC308") (pin "2") (pinfunction "VDD_2") (pintype "input"))
      (node (ref "IC309") (pin "2") (pinfunction "VDD_2") (pintype "input"))
      (node (ref "IC310") (pin "2") (pinfunction "VDD_2") (pintype "input"))
      (node (ref "IC311") (pin "2") (pinfunction "VDD_2") (pintype "input"))
      (node (ref "IC312") (pin "2") (pinfunction "VDD_2") (pintype "input"))
      (node (ref "IC313") (pin "2") (pinfunction "VDD_2") (pintype "input"))
      (node (ref "IC314") (pin "2") (pinfunction "VDD_2") (pintype "input"))
      (node (ref "IC315") (pin "2") (pinfunction "VDD_2") (pintype "input"))
      (node (ref "IC316") (pin "2") (pinfunction "VDD_2") (pintype "input"))
      (node (ref "IC317") (pin "2") (pinfunction "VDD_2") (pintype "input"))
      (node (ref "IC318") (pin "2") (pinfunction "VDD_2") (pintype "input"))
      (node (ref "IC319") (pin "2") (pinfunction "VDD_2") (pintype "input"))
      (node (ref "IC320") (pin "2") (pinfunction "VDD_2") (pintype "input"))
      (node (ref "IC321") (pin "2") (pinfunction "VDD_2") (pintype "input"))
      (node (ref "IC322") (pin "2") (pinfunction "VDD_2") (pintype "input"))
      (node (ref "IC323") (pin "2") (pinfunction "VDD_2") (pintype "input"))
      (node (ref "IC324") (pin "2") (pinfunction "VDD_2") (pintype "input"))
      (node (ref "IC325") (pin "2") (pinfunction "VDD_2") (pintype "input"))
      (node (ref "IC326") (pin "2") (pinfunction "VDD_2") (pintype "input"))
      (node (ref "IC327") (pin "2") (pinfunction "VDD_2") (pintype "input"))
      (node (ref "IC328") (pin "2") (pinfunction "VDD_2") (pintype "input"))
      (node (ref "IC329") (pin "2") (pinfunction "VDD_2") (pintype "input"))
      (node (ref "IC330") (pin "2") (pinfunction "VDD_2") (pintype "input"))
      (node (ref "IC331") (pin "2") (pinfunction "VDD_2") (pintype "input"))
      (node (ref "IC332") (pin "2") (pinfunction "VDD_2") (pintype "input"))
      (node (ref "TP7") (pin "TP") (pinfunction "TP_TP") (pintype "input"))
      (node (ref "X1") (pin "23") (pinfunction "23_23") (pintype "passive"))
      (node (ref "X1") (pin "25") (pinfunction "25_25") (pintype "passive"))
    )
    (net (code "7") (name "+PVCC") (class "Default")
      (node (ref "C1") (pin "1") (pinfunction "1_1") (pintype "passive"))
      (node (ref "C12") (pin "1") (pinfunction "1_1") (pintype "passive"))
      (node (ref "C13") (pin "1") (pinfunction "1_1") (pintype "passive"))
      (node (ref "C14") (pin "1") (pinfunction "1_1") (pintype "passive"))
      (node (ref "C16") (pin "1") (pinfunction "1_1") (pintype "passive"))
      (node (ref "C2") (pin "1") (pinfunction "1_1") (pintype "passive"))
      (node (ref "C20") (pin "1") (pinfunction "1_1") (pintype "passive"))
      (node (ref "C21") (pin "1") (pinfunction "1_1") (pintype "passive"))
      (node (ref "C22") (pin "1") (pinfunction "1_1") (pintype "passive"))
      (node (ref "C25") (pin "1") (pinfunction "1_1") (pintype "passive"))
      (node (ref "C27") (pin "1") (pinfunction "1_1") (pintype "passive"))
      (node (ref "C28") (pin "1") (pinfunction "1_1") (pintype "passive"))
      (node (ref "C30") (pin "1") (pinfunction "1_1") (pintype "passive"))
      (node (ref "C32") (pin "1") (pinfunction "1_1") (pintype "passive"))
      (node (ref "C33") (pin "1") (pinfunction "1_1") (pintype "passive"))
      (node (ref "C4") (pin "1") (pinfunction "1_1") (pintype "passive"))
      (node (ref "C41") (pin "1") (pinfunction "1_1") (pintype "passive"))
      (node (ref "C42") (pin "1") (pinfunction "1_1") (pintype "passive"))
      (node (ref "C43") (pin "1") (pinfunction "1_1") (pintype "passive"))
      (node (ref "R15") (pin "2") (pinfunction "2_2") (pintype "passive"))
      (node (ref "R20") (pin "2") (pinfunction "2_2") (pintype "passive"))
      (node (ref "R22") (pin "2") (pinfunction "2_2") (pintype "passive"))
      (node (ref "R25") (pin "2") (pinfunction "2_2") (pintype "passive"))
      (node (ref "R29") (pin "2") (pinfunction "2_2") (pintype "passive"))
      (node (ref "R34") (pin "2") (pinfunction "2_2") (pintype "passive"))
      (node (ref "R35") (pin "2") (pinfunction "2_2") (pintype "passive"))
      (node (ref "R43") (pin "2") (pinfunction "2_2") (pintype "passive"))
      (node (ref "R46") (pin "2") (pinfunction "2_2") (pintype "passive"))
      (node (ref "R52") (pin "2") (pinfunction "2_2") (pintype "passive"))
      (node (ref "R57") (pin "2") (pinfunction "2_2") (pintype "passive"))
      (node (ref "R66") (pin "2") (pinfunction "2_2") (pintype "passive"))
      (node (ref "R69") (pin "2") (pinfunction "2_2") (pintype "passive"))
      (node (ref "R7") (pin "2") (pinfunction "2_2") (pintype "passive"))
      (node (ref "R73") (pin "2") (pinfunction "2_2") (pintype "passive"))
      (node (ref "R75") (pin "2") (pinfunction "2_2") (pintype "passive"))
      (node (ref "R8") (pin "2") (pinfunction "2_2") (pintype "passive"))
      (node (ref "R83") (pin "2") (pinfunction "2_2") (pintype "passive"))
      (node (ref "R84") (pin "2") (pinfunction "2_2") (pintype "passive"))
      (node (ref "TP2") (pin "TP") (pinfunction "TP_TP") (pintype "input"))
      (node (ref "X2") (pin "02") (pinfunction "2_02") (pintype "passive"))
      (node (ref "X2") (pin "04") (pinfunction "4_04") (pintype "passive"))
      (node (ref "X2") (pin "06") (pinfunction "6_06") (pintype "passive"))
      (node (ref "X2") (pin "08") (pinfunction "8_08") (pintype "passive"))
    )
    (net (code "8") (name "+VBAT") (class "Default")
      (node (ref "R1") (pin "1") (pinfunction "1_1") (pintype "passive"))
      (node (ref "R38") (pin "1") (pinfunction "1_1") (pintype "passive"))
      (node (ref "R44") (pin "1") (pinfunction "1_1") (pintype "passive"))
      (node (ref "R78") (pin "1") (pinfunction "1_1") (pintype "passive"))
      (node (ref "R9") (pin "1") (pinfunction "1_1") (pintype "passive"))
      (node (ref "TP4") (pin "TP") (pinfunction "TP_TP") (pintype "input"))
      (node (ref "X1") (pin "30") (pinfunction "30_30") (pintype "passive"))
    )
    (net (code "9") (name "/+2V8_LDO") (class "Default")
      (node (ref "C47") (pin "1") (pinfunction "1_1") (pintype "passive"))
      (node (ref "L14") (pin "1") (pinfunction "1_1") (pintype "passive"))
      (node (ref "X3") (pin "21") (pinfunction "21_21") (pintype "bidirectional"))
    )
    (net (code "10") (name "/CAM1_RGB_~{PWDN_1V8}") (class "Default")
      (node (ref "IC12") (pin "3") (pinfunction "I/O2_3") (pintype "passive"))
      (node (ref "X1") (pin "08") (pinfunction "8_08") (pintype "passive"))
      (node (ref "X3") (pin "26") (pinfunction "26_26") (pintype "bidirectional"))
    )
    (net (code "11") (name "/CAM3_TOF_~{PWDN}_1V8") (class "Default")
      (node (ref "IC18") (pin "6") (pinfunction "I/O4_6") (pintype "passive"))
      (node (ref "X2") (pin "16") (pinfunction "16_16") (pintype "passive"))
      (node (ref "X5") (pin "30") (pinfunction "30_30") (pintype "passive"))
    )
    (net (code "12") (name "/FET_DRV_~{EN}") (class "Default")
      (node (ref "IC1") (pin "4") (pinfunction "IN-_4") (pintype "input"))
      (node (ref "IC10") (pin "4") (pinfunction "IN-_4") (pintype "input"))
      (node (ref "IC13") (pin "4") (pinfunction "IN-_4") (pintype "input"))
      (node (ref "IC2") (pin "4") (pinfunction "IN-_4") (pintype "input"))
      (node (ref "IC8") (pin "4") (pinfunction "IN-_4") (pintype "input"))
      (node (ref "T8") (pin "3") (pinfunction "D_3") (pintype "passive"))
    )
    (net (code "13") (name "/SAFETY_SHDN_RST") (class "Default")
      (node (ref "R37") (pin "1") (pinfunction "1_1") (pintype "passive"))
      (node (ref "TP13") (pin "TP") (pinfunction "TP_TP") (pintype "input"))
    )
    (net (code "14") (name "/VCC_IO") (class "Default")
      (node (ref "C52") (pin "1") (pinfunction "1_1") (pintype "passive"))
      (node (ref "X4") (pin "4") (pinfunction "4_4") (pintype "passive"))
    )
    (net (code "15") (name "/VIN_A") (class "Default")
      (node (ref "C53") (pin "1") (pinfunction "1_1") (pintype "passive"))
      (node (ref "L9") (pin "2") (pinfunction "2_2") (pintype "passive"))
      (node (ref "X4") (pin "3") (pinfunction "3_3") (pintype "passive"))
    )
    (net (code "16") (name "/~{SAFETY_SHDN}") (class "Default")
      (node (ref "C15") (pin "2") (pinfunction "2_2") (pintype "passive"))
      (node (ref "IC9") (pin "15") (pinfunction "~{CLR}_15") (pintype "input"))
      (node (ref "R24") (pin "2") (pinfunction "2_2") (pintype "passive"))
      (node (ref "R31") (pin "1") (pinfunction "1_1") (pintype "passive"))
      (node (ref "TP11") (pin "TP") (pinfunction "TP_TP") (pintype "input"))
    )
    (net (code "17") (name "CAM1_RGB_CLK_N") (class "Default")
      (node (ref "X1") (pin "05") (pinfunction "5_05") (pintype "passive"))
      (node (ref "X3") (pin "5") (pinfunction "5_5") (pintype "bidirectional"))
    )
    (net (code "18") (name "CAM1_RGB_CLK_P") (class "Default")
      (node (ref "X1") (pin "03") (pinfunction "3_03") (pintype "passive"))
      (node (ref "X3") (pin "4") (pinfunction "4_4") (pintype "bidirectional"))
    )
    (net (code "19") (name "CAM1_RGB_D0_N") (class "Default")
      (node (ref "X1") (pin "11") (pinfunction "11_11") (pintype "passive"))
      (node (ref "X3") (pin "8") (pinfunction "8_8") (pintype "bidirectional"))
    )
    (net (code "20") (name "CAM1_RGB_D0_P") (class "Default")
      (node (ref "X1") (pin "09") (pinfunction "9_09") (pintype "passive"))
      (node (ref "X3") (pin "7") (pinfunction "7_7") (pintype "bidirectional"))
    )
    (net (code "21") (name "CAM1_RGB_D1_N") (class "Default")
      (node (ref "X1") (pin "17") (pinfunction "17_17") (pintype "passive"))
      (node (ref "X3") (pin "11") (pinfunction "11_11") (pintype "bidirectional"))
    )
    (net (code "22") (name "CAM1_RGB_D1_P") (class "Default")
      (node (ref "X1") (pin "15") (pinfunction "15_15") (pintype "passive"))
      (node (ref "X3") (pin "10") (pinfunction "10_10") (pintype "bidirectional"))
    )
    (net (code "23") (name "CAM1_RGB_I2C_SCL_1V8") (class "Default")
      (node (ref "IC12") (pin "4") (pinfunction "I/O3_4") (pintype "passive"))
      (node (ref "X1") (pin "12") (pinfunction "12_12") (pintype "passive"))
      (node (ref "X3") (pin "2") (pinfunction "2_2") (pintype "bidirectional"))
    )
    (net (code "24") (name "CAM1_RGB_I2C_SDA_1V8") (class "Default")
      (node (ref "IC12") (pin "6") (pinfunction "I/O4_6") (pintype "passive"))
      (node (ref "X1") (pin "10") (pinfunction "10_10") (pintype "passive"))
      (node (ref "X3") (pin "1") (pinfunction "1_1") (pintype "bidirectional"))
    )
    (net (code "25") (name "CAM1_RGB_MCLK_1V8") (class "Default")
      (node (ref "IC12") (pin "1") (pinfunction "I/O1_1") (pintype "passive"))
      (node (ref "X1") (pin "04") (pinfunction "4_04") (pintype "passive"))
      (node (ref "X3") (pin "24") (pinfunction "24_24") (pintype "bidirectional"))
    )
    (net (code "26") (name "CAM3_TOF_CLK_N") (class "Default")
      (node (ref "X2") (pin "36") (pinfunction "36_36") (pintype "passive"))
      (node (ref "X5") (pin "23") (pinfunction "23_23") (pintype "passive"))
    )
    (net (code "27") (name "CAM3_TOF_CLK_P") (class "Default")
      (node (ref "X2") (pin "38") (pinfunction "38_38") (pintype "passive"))
      (node (ref "X5") (pin "21") (pinfunction "21_21") (pintype "passive"))
    )
    (net (code "28") (name "CAM3_TOF_D0_N") (class "Default")
      (node (ref "X2") (pin "27") (pinfunction "27_27") (pintype "passive"))
      (node (ref "X5") (pin "17") (pinfunction "17_17") (pintype "passive"))
    )
    (net (code "29") (name "CAM3_TOF_D0_P") (class "Default")
      (node (ref "X2") (pin "29") (pinfunction "29_29") (pintype "passive"))
      (node (ref "X5") (pin "15") (pinfunction "15_15") (pintype "passive"))
    )
    (net (code "30") (name "CAM3_TOF_D1_N") (class "Default")
      (node (ref "X2") (pin "30") (pinfunction "30_30") (pintype "passive"))
      (node (ref "X5") (pin "29") (pinfunction "29_29") (pintype "passive"))
    )
    (net (code "31") (name "CAM3_TOF_D1_P") (class "Default")
      (node (ref "X2") (pin "32") (pinfunction "32_32") (pintype "passive"))
      (node (ref "X5") (pin "27") (pinfunction "27_27") (pintype "passive"))
    )
    (net (code "32") (name "CAM3_TOF_I2C_SCL_1V8") (class "Default")
      (node (ref "IC18") (pin "1") (pinfunction "I/O1_1") (pintype "passive"))
      (node (ref "X2") (pin "22") (pinfunction "22_22") (pintype "passive"))
      (node (ref "X5") (pin "24") (pinfunction "24_24") (pintype "passive"))
    )
    (net (code "33") (name "CAM3_TOF_I2C_SDA_1V8") (class "Default")
      (node (ref "IC18") (pin "3") (pinfunction "I/O2_3") (pintype "passive"))
      (node (ref "X2") (pin "20") (pinfunction "20_20") (pintype "passive"))
      (node (ref "X5") (pin "26") (pinfunction "26_26") (pintype "passive"))
    )
    (net (code "34") (name "CAM3_TOF_MCLK_1V8") (class "Default")
      (node (ref "IC18") (pin "4") (pinfunction "I/O3_4") (pintype "passive"))
      (node (ref "R47") (pin "1") (pinfunction "1_1") (pintype "passive"))
      (node (ref "X2") (pin "33") (pinfunction "33_33") (pintype "passive"))
    )
    (net (code "35") (name "FU_I2C_TEMP_SCL_3V3") (class "Default")
      (node (ref "IC14") (pin "4") (pinfunction "I/O3_4") (pintype "passive"))
      (node (ref "R32") (pin "2") (pinfunction "2_2") (pintype "passive"))
      (node (ref "R39") (pin "2") (pinfunction "2_2") (pintype "passive"))
      (node (ref "R82") (pin "2") (pinfunction "2_2") (pintype "passive"))
      (node (ref "TP22") (pin "TP") (pinfunction "TP_TP") (pintype "input"))
      (node (ref "X1") (pin "29") (pinfunction "29_29") (pintype "passive"))
    )
    (net (code "36") (name "FU_I2C_TEMP_SDA_3V3") (class "Default")
      (node (ref "IC14") (pin "3") (pinfunction "I/O2_3") (pintype "passive"))
      (node (ref "R30") (pin "2") (pinfunction "2_2") (pintype "passive"))
      (node (ref "R33") (pin "2") (pinfunction "2_2") (pintype "passive"))
      (node (ref "R81") (pin "2") (pinfunction "2_2") (pintype "passive"))
      (node (ref "TP23") (pin "TP") (pinfunction "TP_TP") (pintype "input"))
      (node (ref "X1") (pin "31") (pinfunction "31_31") (pintype "passive"))
    )
    (net (code "37") (name "FU_PVCC_EN_3V3") (class "Default")
      (node (ref "IC14") (pin "6") (pinfunction "I/O4_6") (pintype "passive"))
      (node (ref "R55") (pin "2") (pinfunction "2_2") (pintype "passive"))
      (node (ref "R60") (pin "1") (pinfunction "1_1") (pintype "passive"))
      (node (ref "R62") (pin "1") (pinfunction "1_1") (pintype "passive"))
      (node (ref "T8") (pin "1") (pinfunction "G_1") (pintype "passive"))
      (node (ref "TP10") (pin "TP") (pinfunction "TP_TP") (pintype "input"))
      (node (ref "X1") (pin "27") (pinfunction "27_27") (pintype "passive"))
    )
    (net (code "38") (name "FU_TAMPER_SWITCH") (class "Default")
      (node (ref "SW1") (pin "3") (pinfunction "NO_3") (pintype "passive"))
      (node (ref "SW1") (pin "4") (pinfunction "NO_4") (pintype "passive"))
      (node (ref "X1") (pin "34") (pinfunction "34_34") (pintype "passive"))
    )
    (net (code "39") (name "GND") (class "Default")
      (node (ref "C1") (pin "2") (pinfunction "2_2") (pintype "passive"))
      (node (ref "C10") (pin "2") (pinfunction "2_2") (pintype "passive"))
      (node (ref "C100") (pin "2") (pinfunction "2_2") (pintype "passive"))
      (node (ref "C101") (pin "2") (pinfunction "2_2") (pintype "passive"))
      (node (ref "C102") (pin "2") (pinfunction "2_2") (pintype "passive"))
      (node (ref "C103") (pin "2") (pinfunction "2_2") (pintype "passive"))
      (node (ref "C104") (pin "2") (pinfunction "2_2") (pintype "passive"))
      (node (ref "C105") (pin "2") (pinfunction "2_2") (pintype "passive"))
      (node (ref "C106") (pin "2") (pinfunction "2_2") (pintype "passive"))
      (node (ref "C107") (pin "2") (pinfunction "2_2") (pintype "passive"))
      (node (ref "C108") (pin "2") (pinfunction "2_2") (pintype "passive"))
      (node (ref "C109") (pin "2") (pinfunction "2_2") (pintype "passive"))
      (node (ref "C110") (pin "2") (pinfunction "2_2") (pintype "passive"))
      (node (ref "C111") (pin "2") (pinfunction "2_2") (pintype "passive"))
      (node (ref "C112") (pin "2") (pinfunction "2_2") (pintype "passive"))
      (node (ref "C113") (pin "2") (pinfunction "2_2") (pintype "passive"))
      (node (ref "C114") (pin "2") (pinfunction "2_2") (pintype "passive"))
      (node (ref "C115") (pin "2") (pinfunction "2_2") (pintype "passive"))
      (node (ref "C116") (pin "2") (pinfunction "2_2") (pintype "passive"))
      (node (ref "C117") (pin "2") (pinfunction "2_2") (pintype "passive"))
      (node (ref "C118") (pin "2") (pinfunction "2_2") (pintype "passive"))
      (node (ref "C119") (pin "2") (pinfunction "2_2") (pintype "passive"))
      (node (ref "C12") (pin "2") (pinfunction "2_2") (pintype "passive"))
      (node (ref "C120") (pin "2") (pinfunction "2_2") (pintype "passive"))
      (node (ref "C121") (pin "2") (pinfunction "2_2") (pintype "passive"))
      (node (ref "C122") (pin "2") (pinfunction "2_2") (pintype "passive"))
      (node (ref "C123") (pin "2") (pinfunction "2_2") (pintype "passive"))
      (node (ref "C124") (pin "2") (pinfunction "2_2") (pintype "passive"))
      (node (ref "C125") (pin "2") (pinfunction "2_2") (pintype "passive"))
      (node (ref "C126") (pin "2") (pinfunction "2_2") (pintype "passive"))
      (node (ref "C127") (pin "2") (pinfunction "2_2") (pintype "passive"))
      (node (ref "C128") (pin "2") (pinfunction "2_2") (pintype "passive"))
      (node (ref "C129") (pin "2") (pinfunction "2_2") (pintype "passive"))
      (node (ref "C13") (pin "2") (pinfunction "2_2") (pintype "passive"))
      (node (ref "C130") (pin "2") (pinfunction "2_2") (pintype "passive"))
      (node (ref "C131") (pin "2") (pinfunction "2_2") (pintype "passive"))
      (node (ref "C132") (pin "2") (pinfunction "2_2") (pintype "passive"))
      (node (ref "C133") (pin "2") (pinfunction "2_2") (pintype "passive"))
      (node (ref "C134") (pin "2") (pinfunction "2_2") (pintype "passive"))
      (node (ref "C135") (pin "2") (pinfunction "2_2") (pintype "passive"))
      (node (ref "C136") (pin "2") (pinfunction "2_2") (pintype "passive"))
      (node (ref "C137") (pin "2") (pinfunction "2_2") (pintype "passive"))
      (node (ref "C138") (pin "2") (pinfunction "2_2") (pintype "passive"))
      (node (ref "C139") (pin "2") (pinfunction "2_2") (pintype "passive"))
      (node (ref "C14") (pin "2") (pinfunction "2_2") (pintype "passive"))
      (node (ref "C140") (pin "2") (pinfunction "2_2") (pintype "passive"))
      (node (ref "C141") (pin "2") (pinfunction "2_2") (pintype "passive"))
      (node (ref "C142") (pin "2") (pinfunction "2_2") (pintype "passive"))
      (node (ref "C143") (pin "2") (pinfunction "2_2") (pintype "passive"))
      (node (ref "C144") (pin "2") (pinfunction "2_2") (pintype "passive"))
      (node (ref "C145") (pin "2") (pinfunction "2_2") (pintype "passive"))
      (node (ref "C146") (pin "2") (pinfunction "2_2") (pintype "passive"))
      (node (ref "C147") (pin "2") (pinfunction "2_2") (pintype "passive"))
      (node (ref "C148") (pin "2") (pinfunction "2_2") (pintype "passive"))
      (node (ref "C149") (pin "2") (pinfunction "2_2") (pintype "passive"))
      (node (ref "C150") (pin "2") (pinfunction "2_2") (pintype "passive"))
      (node (ref "C151") (pin "2") (pinfunction "2_2") (pintype "passive"))
      (node (ref "C152") (pin "2") (pinfunction "2_2") (pintype "passive"))
      (node (ref "C153") (pin "2") (pinfunction "2_2") (pintype "passive"))
      (node (ref "C154") (pin "2") (pinfunction "2_2") (pintype "passive"))
      (node (ref "C155") (pin "2") (pinfunction "2_2") (pintype "passive"))
      (node (ref "C156") (pin "2") (pinfunction "2_2") (pintype "passive"))
      (node (ref "C157") (pin "2") (pinfunction "2_2") (pintype "passive"))
      (node (ref "C158") (pin "2") (pinfunction "2_2") (pintype "passive"))
      (node (ref "C159") (pin "2") (pinfunction "2_2") (pintype "passive"))
      (node (ref "C16") (pin "2") (pinfunction "2_2") (pintype "passive"))
      (node (ref "C162") (pin "2") (pinfunction "2_2") (pintype "passive"))
      (node (ref "C164") (pin "2") (pinfunction "2_2") (pintype "passive"))
      (node (ref "C165") (pin "2") (pinfunction "2_2") (pintype "passive"))
      (node (ref "C166") (pin "2") (pinfunction "2_2") (pintype "passive"))
      (node (ref "C167") (pin "2") (pinfunction "2_2") (pintype "passive"))
      (node (ref "C168") (pin "2") (pinfunction "2_2") (pintype "passive"))
      (node (ref "C169") (pin "2") (pinfunction "2_2") (pintype "passive"))
      (node (ref "C17") (pin "2") (pinfunction "2_2") (pintype "passive"))
      (node (ref "C170") (pin "2") (pinfunction "2_2") (pintype "passive"))
      (node (ref "C171") (pin "2") (pinfunction "2_2") (pintype "passive"))
      (node (ref "C172") (pin "2") (pinfunction "2_2") (pintype "passive"))
      (node (ref "C173") (pin "2") (pinfunction "2_2") (pintype "passive"))
      (node (ref "C174") (pin "2") (pinfunction "2_2") (pintype "passive"))
      (node (ref "C175") (pin "2") (pinfunction "2_2") (pintype "passive"))
      (node (ref "C176") (pin "2") (pinfunction "2_2") (pintype "passive"))
      (node (ref "C177") (pin "2") (pinfunction "2_2") (pintype "passive"))
      (node (ref "C178") (pin "2") (pinfunction "2_2") (pintype "passive"))
      (node (ref "C179") (pin "2") (pinfunction "2_2") (pintype "passive"))
      (node (ref "C18") (pin "2") (pinfunction "2_2") (pintype "passive"))
      (node (ref "C180") (pin "2") (pinfunction "2_2") (pintype "passive"))
      (node (ref "C181") (pin "2") (pinfunction "2_2") (pintype "passive"))
      (node (ref "C182") (pin "2") (pinfunction "2_2") (pintype "passive"))
      (node (ref "C183") (pin "2") (pinfunction "2_2") (pintype "passive"))
      (node (ref "C184") (pin "2") (pinfunction "2_2") (pintype "passive"))
      (node (ref "C185") (pin "2") (pinfunction "2_2") (pintype "passive"))
      (node (ref "C186") (pin "2") (pinfunction "2_2") (pintype "passive"))
      (node (ref "C187") (pin "2") (pinfunction "2_2") (pintype "passive"))
      (node (ref "C188") (pin "2") (pinfunction "2_2") (pintype "passive"))
      (node (ref "C189") (pin "2") (pinfunction "2_2") (pintype "passive"))
      (node (ref "C19") (pin "2") (pinfunction "2_2") (pintype "passive"))
      (node (ref "C190") (pin "2") (pinfunction "2_2") (pintype "passive"))
      (node (ref "C191") (pin "2") (pinfunction "2_2") (pintype "passive"))
      (node (ref "C192") (pin "2") (pinfunction "2_2") (pintype "passive"))
      (node (ref "C193") (pin "2") (pinfunction "2_2") (pintype "passive"))
      (node (ref "C194") (pin "2") (pinfunction "2_2") (pintype "passive"))
      (node (ref "C195") (pin "2") (pinfunction "2_2") (pintype "passive"))
      (node (ref "C196") (pin "2") (pinfunction "2_2") (pintype "passive"))
      (node (ref "C197") (pin "2") (pinfunction "2_2") (pintype "passive"))
      (node (ref "C198") (pin "2") (pinfunction "2_2") (pintype "passive"))
      (node (ref "C199") (pin "2") (pinfunction "2_2") (pintype "passive"))
      (node (ref "C2") (pin "2") (pinfunction "2_2") (pintype "passive"))
      (node (ref "C20") (pin "2") (pinfunction "2_2") (pintype "passive"))
      (node (ref "C200") (pin "2") (pinfunction "2_2") (pintype "passive"))
      (node (ref "C201") (pin "2") (pinfunction "2_2") (pintype "passive"))
      (node (ref "C202") (pin "2") (pinfunction "2_2") (pintype "passive"))
      (node (ref "C203") (pin "2") (pinfunction "2_2") (pintype "passive"))
      (node (ref "C204") (pin "2") (pinfunction "2_2") (pintype "passive"))
      (node (ref "C205") (pin "2") (pinfunction "2_2") (pintype "passive"))
      (node (ref "C206") (pin "2") (pinfunction "2_2") (pintype "passive"))
      (node (ref "C207") (pin "2") (pinfunction "2_2") (pintype "passive"))
      (node (ref "C208") (pin "2") (pinfunction "2_2") (pintype "passive"))
      (node (ref "C209") (pin "2") (pinfunction "2_2") (pintype "passive"))
      (node (ref "C21") (pin "2") (pinfunction "2_2") (pintype "passive"))
      (node (ref "C210") (pin "2") (pinfunction "2_2") (pintype "passive"))
      (node (ref "C211") (pin "2") (pinfunction "2_2") (pintype "passive"))
      (node (ref "C212") (pin "2") (pinfunction "2_2") (pintype "passive"))
      (node (ref "C213") (pin "2") (pinfunction "2_2") (pintype "passive"))
      (node (ref "C214") (pin "2") (pinfunction "2_2") (pintype "passive"))
      (node (ref "C215") (pin "2") (pinfunction "2_2") (pintype "passive"))
      (node (ref "C216") (pin "2") (pinfunction "2_2") (pintype "passive"))
      (node (ref "C217") (pin "2") (pinfunction "2_2") (pintype "passive"))
      (node (ref "C218") (pin "2") (pinfunction "2_2") (pintype "passive"))
      (node (ref "C219") (pin "2") (pinfunction "2_2") (pintype "passive"))
      (node (ref "C22") (pin "2") (pinfunction "2_2") (pintype "passive"))
      (node (ref "C220") (pin "2") (pinfunction "2_2") (pintype "passive"))
      (node (ref "C221") (pin "2") (pinfunction "2_2") (pintype "passive"))
      (node (ref "C222") (pin "2") (pinfunction "2_2") (pintype "passive"))
      (node (ref "C223") (pin "2") (pinfunction "2_2") (pintype "passive"))
      (node (ref "C224") (pin "2") (pinfunction "2_2") (pintype "passive"))
      (node (ref "C225") (pin "2") (pinfunction "2_2") (pintype "passive"))
      (node (ref "C226") (pin "2") (pinfunction "2_2") (pintype "passive"))
      (node (ref "C227") (pin "2") (pinfunction "2_2") (pintype "passive"))
      (node (ref "C228") (pin "2") (pinfunction "2_2") (pintype "passive"))
      (node (ref "C229") (pin "2") (pinfunction "2_2") (pintype "passive"))
      (node (ref "C23") (pin "2") (pinfunction "2_2") (pintype "passive"))
      (node (ref "C230") (pin "2") (pinfunction "2_2") (pintype "passive"))
      (node (ref "C231") (pin "2") (pinfunction "2_2") (pintype "passive"))
      (node (ref "C232") (pin "2") (pinfunction "2_2") (pintype "passive"))
      (node (ref "C233") (pin "2") (pinfunction "2_2") (pintype "passive"))
      (node (ref "C234") (pin "2") (pinfunction "2_2") (pintype "passive"))
      (node (ref "C235") (pin "2") (pinfunction "2_2") (pintype "passive"))
      (node (ref "C236") (pin "2") (pinfunction "2_2") (pintype "passive"))
      (node (ref "C237") (pin "2") (pinfunction "2_2") (pintype "passive"))
      (node (ref "C238") (pin "2") (pinfunction "2_2") (pintype "passive"))
      (node (ref "C239") (pin "2") (pinfunction "2_2") (pintype "passive"))
      (node (ref "C24") (pin "2") (pinfunction "2_2") (pintype "passive"))
      (node (ref "C240") (pin "2") (pinfunction "2_2") (pintype "passive"))
      (node (ref "C241") (pin "2") (pinfunction "2_2") (pintype "passive"))
      (node (ref "C242") (pin "2") (pinfunction "2_2") (pintype "passive"))
      (node (ref "C243") (pin "2") (pinfunction "2_2") (pintype "passive"))
      (node (ref "C244") (pin "2") (pinfunction "2_2") (pintype "passive"))
      (node (ref "C245") (pin "2") (pinfunction "2_2") (pintype "passive"))
      (node (ref "C246") (pin "2") (pinfunction "2_2") (pintype "passive"))
      (node (ref "C247") (pin "2") (pinfunction "2_2") (pintype "passive"))
      (node (ref "C248") (pin "2") (pinfunction "2_2") (pintype "passive"))
      (node (ref "C249") (pin "2") (pinfunction "2_2") (pintype "passive"))
      (node (ref "C25") (pin "2") (pinfunction "2_2") (pintype "passive"))
      (node (ref "C250") (pin "2") (pinfunction "2_2") (pintype "passive"))
      (node (ref "C251") (pin "2") (pinfunction "2_2") (pintype "passive"))
      (node (ref "C252") (pin "2") (pinfunction "2_2") (pintype "passive"))
      (node (ref "C253") (pin "2") (pinfunction "2_2") (pintype "passive"))
      (node (ref "C254") (pin "2") (pinfunction "2_2") (pintype "passive"))
      (node (ref "C255") (pin "2") (pinfunction "2_2") (pintype "passive"))
      (node (ref "C256") (pin "2") (pinfunction "2_2") (pintype "passive"))
      (node (ref "C257") (pin "2") (pinfunction "2_2") (pintype "passive"))
      (node (ref "C258") (pin "2") (pinfunction "2_2") (pintype "passive"))
      (node (ref "C259") (pin "2") (pinfunction "2_2") (pintype "passive"))
      (node (ref "C26") (pin "2") (pinfunction "2_2") (pintype "passive"))
      (node (ref "C260") (pin "2") (pinfunction "2_2") (pintype "passive"))
      (node (ref "C261") (pin "2") (pinfunction "2_2") (pintype "passive"))
      (node (ref "C262") (pin "2") (pinfunction "2_2") (pintype "passive"))
      (node (ref "C263") (pin "2") (pinfunction "2_2") (pintype "passive"))
      (node (ref "C264") (pin "2") (pinfunction "2_2") (pintype "passive"))
      (node (ref "C265") (pin "2") (pinfunction "2_2") (pintype "passive"))
      (node (ref "C266") (pin "2") (pinfunction "2_2") (pintype "passive"))
      (node (ref "C27") (pin "2") (pinfunction "2_2") (pintype "passive"))
      (node (ref "C270") (pin "2") (pinfunction "2_2") (pintype "passive"))
      (node (ref "C272") (pin "2") (pinfunction "2_2") (pintype "passive"))
      (node (ref "C28") (pin "2") (pinfunction "2_2") (pintype "passive"))
      (node (ref "C280") (pin "2") (pinfunction "2_2") (pintype "passive"))
      (node (ref "C281") (pin "2") (pinfunction "2_2") (pintype "passive"))
      (node (ref "C282") (pin "2") (pinfunction "2_2") (pintype "passive"))
      (node (ref "C283") (pin "2") (pinfunction "2_2") (pintype "passive"))
      (node (ref "C284") (pin "2") (pinfunction "2_2") (pintype "passive"))
      (node (ref "C285") (pin "2") (pinfunction "2_2") (pintype "passive"))
      (node (ref "C286") (pin "2") (pinfunction "2_2") (pintype "passive"))
      (node (ref "C287") (pin "2") (pinfunction "2_2") (pintype "passive"))
      (node (ref "C288") (pin "2") (pinfunction "2_2") (pintype "passive"))
      (node (ref "C289") (pin "2") (pinfunction "2_2") (pintype "passive"))
      (node (ref "C290") (pin "2") (pinfunction "2_2") (pintype "passive"))
      (node (ref "C291") (pin "2") (pinfunction "2_2") (pintype "passive"))
      (node (ref "C292") (pin "2") (pinfunction "2_2") (pintype "passive"))
      (node (ref "C293") (pin "2") (pinfunction "2_2") (pintype "passive"))
      (node (ref "C294") (pin "2") (pinfunction "2_2") (pintype "passive"))
      (node (ref "C295") (pin "2") (pinfunction "2_2") (pintype "passive"))
      (node (ref "C296") (pin "2") (pinfunction "2_2") (pintype "passive"))
      (node (ref "C297") (pin "2") (pinfunction "2_2") (pintype "passive"))
      (node (ref "C298") (pin "2") (pinfunction "2_2") (pintype "passive"))
      (node (ref "C299") (pin "2") (pinfunction "2_2") (pintype "passive"))
      (node (ref "C3") (pin "2") (pinfunction "2_2") (pintype "passive"))
      (node (ref "C30") (pin "2") (pinfunction "2_2") (pintype "passive"))
      (node (ref "C300") (pin "2") (pinfunction "2_2") (pintype "passive"))
      (node (ref "C301") (pin "2") (pinfunction "2_2") (pintype "passive"))
      (node (ref "C302") (pin "2") (pinfunction "2_2") (pintype "passive"))
      (node (ref "C303") (pin "2") (pinfunction "2_2") (pintype "passive"))
      (node (ref "C304") (pin "2") (pinfunction "2_2") (pintype "passive"))
      (node (ref "C305") (pin "2") (pinfunction "2_2") (pintype "passive"))
      (node (ref "C306") (pin "2") (pinfunction "2_2") (pintype "passive"))
      (node (ref "C307") (pin "2") (pinfunction "2_2") (pintype "passive"))
      (node (ref "C308") (pin "2") (pinfunction "2_2") (pintype "passive"))
      (node (ref "C309") (pin "2") (pinfunction "2_2") (pintype "passive"))
      (node (ref "C310") (pin "2") (pinfunction "2_2") (pintype "passive"))
      (node (ref "C311") (pin "2") (pinfunction "2_2") (pintype "passive"))
      (node (ref "C312") (pin "2") (pinfunction "2_2") (pintype "passive"))
      (node (ref "C313") (pin "2") (pinfunction "2_2") (pintype "passive"))
      (node (ref "C314") (pin "2") (pinfunction "2_2") (pintype "passive"))
      (node (ref "C315") (pin "2") (pinfunction "2_2") (pintype "passive"))
      (node (ref "C316") (pin "2") (pinfunction "2_2") (pintype "passive"))
      (node (ref "C317") (pin "2") (pinfunction "2_2") (pintype "passive"))
      (node (ref "C318") (pin "2") (pinfunction "2_2") (pintype "passive"))
      (node (ref "C319") (pin "2") (pinfunction "2_2") (pintype "passive"))
      (node (ref "C32") (pin "2") (pinfunction "2_2") (pintype "passive"))
      (node (ref "C320") (pin "2") (pinfunction "2_2") (pintype "passive"))
      (node (ref "C321") (pin "2") (pinfunction "2_2") (pintype "passive"))
      (node (ref "C322") (pin "2") (pinfunction "2_2") (pintype "passive"))
      (node (ref "C323") (pin "2") (pinfunction "2_2") (pintype "passive"))
      (node (ref "C324") (pin "2") (pinfunction "2_2") (pintype "passive"))
      (node (ref "C325") (pin "2") (pinfunction "2_2") (pintype "passive"))
      (node (ref "C326") (pin "2") (pinfunction "2_2") (pintype "passive"))
      (node (ref "C327") (pin "2") (pinfunction "2_2") (pintype "passive"))
      (node (ref "C328") (pin "2") (pinfunction "2_2") (pintype "passive"))
      (node (ref "C329") (pin "2") (pinfunction "2_2") (pintype "passive"))
      (node (ref "C33") (pin "2") (pinfunction "2_2") (pintype "passive"))
      (node (ref "C330") (pin "2") (pinfunction "2_2") (pintype "passive"))
      (node (ref "C331") (pin "2") (pinfunction "2_2") (pintype "passive"))
      (node (ref "C332") (pin "2") (pinfunction "2_2") (pintype "passive"))
      (node (ref "C34") (pin "2") (pinfunction "2_2") (pintype "passive"))
      (node (ref "C37") (pin "2") (pinfunction "2_2") (pintype "passive"))
      (node (ref "C38") (pin "2") (pinfunction "2_2") (pintype "passive"))
      (node (ref "C39") (pin "2") (pinfunction "2_2") (pintype "passive"))
      (node (ref "C4") (pin "2") (pinfunction "2_2") (pintype "passive"))
      (node (ref "C40") (pin "2") (pinfunction "2_2") (pintype "passive"))
      (node (ref "C41") (pin "2") (pinfunction "2_2") (pintype "passive"))
      (node (ref "C42") (pin "2") (pinfunction "2_2") (pintype "passive"))
      (node (ref "C43") (pin "2") (pinfunction "2_2") (pintype "passive"))
      (node (ref "C44") (pin "2") (pinfunction "2_2") (pintype "passive"))
      (node (ref "C45") (pin "2") (pinfunction "2_2") (pintype "passive"))
      (node (ref "C46") (pin "2") (pinfunction "2_2") (pintype "passive"))
      (node (ref "C47") (pin "2") (pinfunction "2_2") (pintype "passive"))
      (node (ref "C48") (pin "2") (pinfunction "2_2") (pintype "passive"))
      (node (ref "C49") (pin "2") (pinfunction "2_2") (pintype "passive"))
      (node (ref "C5") (pin "2") (pinfunction "2_2") (pintype "passive"))
      (node (ref "C50") (pin "2") (pinfunction "2_2") (pintype "passive"))
      (node (ref "C51") (pin "2") (pinfunction "2_2") (pintype "passive"))
      (node (ref "C52") (pin "2") (pinfunction "2_2") (pintype "passive"))
      (node (ref "C53") (pin "2") (pinfunction "2_2") (pintype "passive"))
      (node (ref "C54") (pin "2") (pinfunction "2_2") (pintype "passive"))
      (node (ref "C55") (pin "2") (pinfunction "2_2") (pintype "passive"))
      (node (ref "C56") (pin "2") (pinfunction "2_2") (pintype "passive"))
      (node (ref "C57") (pin "2") (pinfunction "2_2") (pintype "passive"))
      (node (ref "C58") (pin "2") (pinfunction "2_2") (pintype "passive"))
      (node (ref "C59") (pin "2") (pinfunction "2_2") (pintype "passive"))
      (node (ref "C6") (pin "2") (pinfunction "2_2") (pintype "passive"))
      (node (ref "C60") (pin "2") (pinfunction "2_2") (pintype "passive"))
      (node (ref "C61") (pin "2") (pinfunction "2_2") (pintype "passive"))
      (node (ref "C7") (pin "2") (pinfunction "2_2") (pintype "passive"))
      (node (ref "C78") (pin "2") (pinfunction "2_2") (pintype "passive"))
      (node (ref "C8") (pin "2") (pinfunction "2_2") (pintype "passive"))
      (node (ref "C9") (pin "2") (pinfunction "2_2") (pintype "passive"))
      (node (ref "D100") (pin "5") (pinfunction "P$1_5") (pintype "passive"))
      (node (ref "D101") (pin "5") (pinfunction "P$1_5") (pintype "passive"))
      (node (ref "D102") (pin "5") (pinfunction "P$1_5") (pintype "passive"))
      (node (ref "D103") (pin "5") (pinfunction "P$1_5") (pintype "passive"))
      (node (ref "D104") (pin "5") (pinfunction "P$1_5") (pintype "passive"))
      (node (ref "D105") (pin "5") (pinfunction "P$1_5") (pintype "passive"))
      (node (ref "D106") (pin "5") (pinfunction "P$1_5") (pintype "passive"))
      (node (ref "D107") (pin "5") (pinfunction "P$1_5") (pintype "passive"))
      (node (ref "D108") (pin "5") (pinfunction "P$1_5") (pintype "passive"))
      (node (ref "D109") (pin "5") (pinfunction "P$1_5") (pintype "passive"))
      (node (ref "D110") (pin "5") (pinfunction "P$1_5") (pintype "passive"))
      (node (ref "D111") (pin "5") (pinfunction "P$1_5") (pintype "passive"))
      (node (ref "D112") (pin "5") (pinfunction "P$1_5") (pintype "passive"))
      (node (ref "D200") (pin "NC") (pinfunction "P$1_NC") (pintype "passive"))
      (node (ref "D201") (pin "NC") (pinfunction "P$1_NC") (pintype "passive"))
      (node (ref "D202") (pin "NC") (pinfunction "P$1_NC") (pintype "passive"))
      (node (ref "D203") (pin "NC") (pinfunction "P$1_NC") (pintype "passive"))
      (node (ref "D204") (pin "NC") (pinfunction "P$1_NC") (pintype "passive"))
      (node (ref "D205") (pin "NC") (pinfunction "P$1_NC") (pintype "passive"))
      (node (ref "D206") (pin "NC") (pinfunction "P$1_NC") (pintype "passive"))
      (node (ref "D207") (pin "NC") (pinfunction "P$1_NC") (pintype "passive"))
      (node (ref "D208") (pin "NC") (pinfunction "P$1_NC") (pintype "passive"))
      (node (ref "D209") (pin "NC") (pinfunction "P$1_NC") (pintype "passive"))
      (node (ref "D210") (pin "NC") (pinfunction "P$1_NC") (pintype "passive"))
      (node (ref "D211") (pin "NC") (pinfunction "P$1_NC") (pintype "passive"))
      (node (ref "D212") (pin "NC") (pinfunction "P$1_NC") (pintype "passive"))
      (node (ref "D213") (pin "NC") (pinfunction "P$1_NC") (pintype "passive"))
      (node (ref "D214") (pin "NC") (pinfunction "P$1_NC") (pintype "passive"))
      (node (ref "D215") (pin "NC") (pinfunction "P$1_NC") (pintype "passive"))
      (node (ref "D250") (pin "NC") (pinfunction "P$1_NC") (pintype "passive"))
      (node (ref "D251") (pin "NC") (pinfunction "P$1_NC") (pintype "passive"))
      (node (ref "D252") (pin "NC") (pinfunction "P$1_NC") (pintype "passive"))
      (node (ref "D253") (pin "NC") (pinfunction "P$1_NC") (pintype "passive"))
      (node (ref "D254") (pin "NC") (pinfunction "P$1_NC") (pintype "passive"))
      (node (ref "D255") (pin "NC") (pinfunction "P$1_NC") (pintype "passive"))
      (node (ref "D256") (pin "NC") (pinfunction "P$1_NC") (pintype "passive"))
      (node (ref "D257") (pin "NC") (pinfunction "P$1_NC") (pintype "passive"))
      (node (ref "D258") (pin "NC") (pinfunction "P$1_NC") (pintype "passive"))
      (node (ref "D259") (pin "NC") (pinfunction "P$1_NC") (pintype "passive"))
      (node (ref "D260") (pin "NC") (pinfunction "P$1_NC") (pintype "passive"))
      (node (ref "D261") (pin "NC") (pinfunction "P$1_NC") (pintype "passive"))
      (node (ref "D262") (pin "NC") (pinfunction "P$1_NC") (pintype "passive"))
      (node (ref "D263") (pin "NC") (pinfunction "P$1_NC") (pintype "passive"))
      (node (ref "D264") (pin "NC") (pinfunction "P$1_NC") (pintype "passive"))
      (node (ref "D265") (pin "NC") (pinfunction "P$1_NC") (pintype "passive"))
      (node (ref "D300") (pin "NC") (pinfunction "P$1_NC") (pintype "passive"))
      (node (ref "D301") (pin "NC") (pinfunction "P$1_NC") (pintype "passive"))
      (node (ref "D302") (pin "NC") (pinfunction "P$1_NC") (pintype "passive"))
      (node (ref "D303") (pin "NC") (pinfunction "P$1_NC") (pintype "passive"))
      (node (ref "D304") (pin "NC") (pinfunction "P$1_NC") (pintype "passive"))
      (node (ref "D305") (pin "NC") (pinfunction "P$1_NC") (pintype "passive"))
      (node (ref "D306") (pin "NC") (pinfunction "P$1_NC") (pintype "passive"))
      (node (ref "D307") (pin "NC") (pinfunction "P$1_NC") (pintype "passive"))
      (node (ref "D308") (pin "NC") (pinfunction "P$1_NC") (pintype "passive"))
      (node (ref "D309") (pin "NC") (pinfunction "P$1_NC") (pintype "passive"))
      (node (ref "D310") (pin "NC") (pinfunction "P$1_NC") (pintype "passive"))
      (node (ref "D311") (pin "NC") (pinfunction "P$1_NC") (pintype "passive"))
      (node (ref "D312") (pin "NC") (pinfunction "P$1_NC") (pintype "passive"))
      (node (ref "D313") (pin "NC") (pinfunction "P$1_NC") (pintype "passive"))
      (node (ref "D314") (pin "NC") (pinfunction "P$1_NC") (pintype "passive"))
      (node (ref "D315") (pin "NC") (pinfunction "P$1_NC") (pintype "passive"))
      (node (ref "D350") (pin "NC") (pinfunction "P$1_NC") (pintype "passive"))
      (node (ref "D351") (pin "NC") (pinfunction "P$1_NC") (pintype "passive"))
      (node (ref "D352") (pin "NC") (pinfunction "P$1_NC") (pintype "passive"))
      (node (ref "D353") (pin "NC") (pinfunction "P$1_NC") (pintype "passive"))
      (node (ref "D354") (pin "NC") (pinfunction "P$1_NC") (pintype "passive"))
      (node (ref "D355") (pin "NC") (pinfunction "P$1_NC") (pintype "passive"))
      (node (ref "D356") (pin "NC") (pinfunction "P$1_NC") (pintype "passive"))
      (node (ref "D357") (pin "NC") (pinfunction "P$1_NC") (pintype "passive"))
      (node (ref "D358") (pin "NC") (pinfunction "P$1_NC") (pintype "passive"))
      (node (ref "D359") (pin "NC") (pinfunction "P$1_NC") (pintype "passive"))
      (node (ref "D360") (pin "NC") (pinfunction "P$1_NC") (pintype "passive"))
      (node (ref "D361") (pin "NC") (pinfunction "P$1_NC") (pintype "passive"))
      (node (ref "D362") (pin "NC") (pinfunction "P$1_NC") (pintype "passive"))
      (node (ref "D363") (pin "NC") (pinfunction "P$1_NC") (pintype "passive"))
      (node (ref "D364") (pin "NC") (pinfunction "P$1_NC") (pintype "passive"))
      (node (ref "D365") (pin "NC") (pinfunction "P$1_NC") (pintype "passive"))
      (node (ref "IC1") (pin "2") (pinfunction "GND_2") (pintype "input"))
      (node (ref "IC10") (pin "2") (pinfunction "GND_2") (pintype "input"))
      (node (ref "IC100") (pin "4") (pinfunction "VSS_4") (pintype "input"))
      (node (ref "IC101") (pin "4") (pinfunction "VSS_4") (pintype "input"))
      (node (ref "IC102") (pin "4") (pinfunction "VSS_4") (pintype "input"))
      (node (ref "IC103") (pin "4") (pinfunction "VSS_4") (pintype "input"))
      (node (ref "IC104") (pin "4") (pinfunction "VSS_4") (pintype "input"))
      (node (ref "IC105") (pin "4") (pinfunction "VSS_4") (pintype "input"))
      (node (ref "IC106") (pin "4") (pinfunction "VSS_4") (pintype "input"))
      (node (ref "IC107") (pin "4") (pinfunction "VSS_4") (pintype "input"))
      (node (ref "IC108") (pin "4") (pinfunction "VSS_4") (pintype "input"))
      (node (ref "IC109") (pin "4") (pinfunction "VSS_4") (pintype "input"))
      (node (ref "IC110") (pin "4") (pinfunction "VSS_4") (pintype "input"))
      (node (ref "IC111") (pin "4") (pinfunction "VSS_4") (pintype "input"))
      (node (ref "IC112") (pin "4") (pinfunction "VSS_4") (pintype "input"))
      (node (ref "IC113") (pin "4") (pinfunction "VSS_4") (pintype "input"))
      (node (ref "IC114") (pin "4") (pinfunction "VSS_4") (pintype "input"))
      (node (ref "IC115") (pin "4") (pinfunction "VSS_4") (pintype "input"))
      (node (ref "IC116") (pin "4") (pinfunction "VSS_4") (pintype "input"))
      (node (ref "IC117") (pin "4") (pinfunction "VSS_4") (pintype "input"))
      (node (ref "IC118") (pin "4") (pinfunction "VSS_4") (pintype "input"))
      (node (ref "IC119") (pin "4") (pinfunction "VSS_4") (pintype "input"))
      (node (ref "IC12") (pin "2") (pinfunction "GND_2") (pintype "input"))
      (node (ref "IC120") (pin "4") (pinfunction "VSS_4") (pintype "input"))
      (node (ref "IC121") (pin "4") (pinfunction "VSS_4") (pintype "input"))
      (node (ref "IC122") (pin "4") (pinfunction "VSS_4") (pintype "input"))
      (node (ref "IC123") (pin "4") (pinfunction "VSS_4") (pintype "input"))
      (node (ref "IC124") (pin "4") (pinfunction "VSS_4") (pintype "input"))
      (node (ref "IC125") (pin "4") (pinfunction "VSS_4") (pintype "input"))
      (node (ref "IC126") (pin "4") (pinfunction "VSS_4") (pintype "input"))
      (node (ref "IC127") (pin "4") (pinfunction "VSS_4") (pintype "input"))
      (node (ref "IC128") (pin "4") (pinfunction "VSS_4") (pintype "input"))
      (node (ref "IC129") (pin "4") (pinfunction "VSS_4") (pintype "input"))
      (node (ref "IC13") (pin "2") (pinfunction "GND_2") (pintype "input"))
      (node (ref "IC130") (pin "4") (pinfunction "VSS_4") (pintype "input"))
      (node (ref "IC131") (pin "4") (pinfunction "VSS_4") (pintype "input"))
      (node (ref "IC132") (pin "4") (pinfunction "VSS_4") (pintype "input"))
      (node (ref "IC133") (pin "4") (pinfunction "VSS_4") (pintype "input"))
      (node (ref "IC134") (pin "4") (pinfunction "VSS_4") (pintype "input"))
      (node (ref "IC135") (pin "4") (pinfunction "VSS_4") (pintype "input"))
      (node (ref "IC136") (pin "4") (pinfunction "VSS_4") (pintype "input"))
      (node (ref "IC137") (pin "4") (pinfunction "VSS_4") (pintype "input"))
      (node (ref "IC138") (pin "4") (pinfunction "VSS_4") (pintype "input"))
      (node (ref "IC139") (pin "4") (pinfunction "VSS_4") (pintype "input"))
      (node (ref "IC14") (pin "2") (pinfunction "GND_2") (pintype "input"))
      (node (ref "IC140") (pin "4") (pinfunction "VSS_4") (pintype "input"))
      (node (ref "IC141") (pin "4") (pinfunction "VSS_4") (pintype "input"))
      (node (ref "IC142") (pin "4") (pinfunction "VSS_4") (pintype "input"))
      (node (ref "IC143") (pin "4") (pinfunction "VSS_4") (pintype "input"))
      (node (ref "IC144") (pin "4") (pinfunction "VSS_4") (pintype "input"))
      (node (ref "IC145") (pin "4") (pinfunction "VSS_4") (pintype "input"))
      (node (ref "IC146") (pin "4") (pinfunction "VSS_4") (pintype "input"))
      (node (ref "IC147") (pin "4") (pinfunction "VSS_4") (pintype "input"))
      (node (ref "IC148") (pin "4") (pinfunction "VSS_4") (pintype "input"))
      (node (ref "IC149") (pin "4") (pinfunction "VSS_4") (pintype "input"))
      (node (ref "IC15") (pin "4") (pinfunction "GND_4") (pintype "input"))
      (node (ref "IC15") (pin "5") (pinfunction "A2_5") (pintype "input"))
      (node (ref "IC15") (pin "6") (pinfunction "A1_6") (pintype "input"))
      (node (ref "IC15") (pin "7") (pinfunction "A0_7") (pintype "input"))
      (node (ref "IC150") (pin "4") (pinfunction "VSS_4") (pintype "input"))
      (node (ref "IC151") (pin "4") (pinfunction "VSS_4") (pintype "input"))
      (node (ref "IC152") (pin "4") (pinfunction "VSS_4") (pintype "input"))
      (node (ref "IC153") (pin "4") (pinfunction "VSS_4") (pintype "input"))
      (node (ref "IC154") (pin "4") (pinfunction "VSS_4") (pintype "input"))
      (node (ref "IC155") (pin "4") (pinfunction "VSS_4") (pintype "input"))
      (node (ref "IC156") (pin "4") (pinfunction "VSS_4") (pintype "input"))
      (node (ref "IC157") (pin "4") (pinfunction "VSS_4") (pintype "input"))
      (node (ref "IC158") (pin "4") (pinfunction "VSS_4") (pintype "input"))
      (node (ref "IC159") (pin "4") (pinfunction "VSS_4") (pintype "input"))
      (node (ref "IC16") (pin "2") (pinfunction "GND_2") (pintype "input"))
      (node (ref "IC160") (pin "4") (pinfunction "VSS_4") (pintype "input"))
      (node (ref "IC161") (pin "4") (pinfunction "VSS_4") (pintype "input"))
      (node (ref "IC162") (pin "4") (pinfunction "VSS_4") (pintype "input"))
      (node (ref "IC163") (pin "4") (pinfunction "VSS_4") (pintype "input"))
      (node (ref "IC164") (pin "4") (pinfunction "VSS_4") (pintype "input"))
      (node (ref "IC165") (pin "4") (pinfunction "VSS_4") (pintype "input"))
      (node (ref "IC166") (pin "4") (pinfunction "VSS_4") (pintype "input"))
      (node (ref "IC167") (pin "4") (pinfunction "VSS_4") (pintype "input"))
      (node (ref "IC168") (pin "4") (pinfunction "VSS_4") (pintype "input"))
      (node (ref "IC169") (pin "4") (pinfunction "VSS_4") (pintype "input"))
      (node (ref "IC17") (pin "2") (pinfunction "GND_2") (pintype "input"))
      (node (ref "IC170") (pin "4") (pinfunction "VSS_4") (pintype "input"))
      (node (ref "IC171") (pin "4") (pinfunction "VSS_4") (pintype "input"))
      (node (ref "IC172") (pin "4") (pinfunction "VSS_4") (pintype "input"))
      (node (ref "IC173") (pin "4") (pinfunction "VSS_4") (pintype "input"))
      (node (ref "IC174") (pin "4") (pinfunction "VSS_4") (pintype "input"))
      (node (ref "IC175") (pin "4") (pinfunction "VSS_4") (pintype "input"))
      (node (ref "IC176") (pin "4") (pinfunction "VSS_4") (pintype "input"))
      (node (ref "IC177") (pin "4") (pinfunction "VSS_4") (pintype "input"))
      (node (ref "IC178") (pin "4") (pinfunction "VSS_4") (pintype "input"))
      (node (ref "IC179") (pin "4") (pinfunction "VSS_4") (pintype "input"))
      (node (ref "IC18") (pin "2") (pinfunction "GND_2") (pintype "input"))
      (node (ref "IC180") (pin "4") (pinfunction "VSS_4") (pintype "input"))
      (node (ref "IC181") (pin "4") (pinfunction "VSS_4") (pintype "input"))
      (node (ref "IC182") (pin "4") (pinfunction "VSS_4") (pintype "input"))
      (node (ref "IC183") (pin "4") (pinfunction "VSS_4") (pintype "input"))
      (node (ref "IC184") (pin "4") (pinfunction "VSS_4") (pintype "input"))
      (node (ref "IC185") (pin "4") (pinfunction "VSS_4") (pintype "input"))
      (node (ref "IC186") (pin "4") (pinfunction "VSS_4") (pintype "input"))
      (node (ref "IC187") (pin "4") (pinfunction "VSS_4") (pintype "input"))
      (node (ref "IC188") (pin "4") (pinfunction "VSS_4") (pintype "input"))
      (node (ref "IC189") (pin "4") (pinfunction "VSS_4") (pintype "input"))
      (node (ref "IC19") (pin "2") (pinfunction "GND_2") (pintype "input"))
      (node (ref "IC190") (pin "4") (pinfunction "VSS_4") (pintype "input"))
      (node (ref "IC191") (pin "4") (pinfunction "VSS_4") (pintype "input"))
      (node (ref "IC192") (pin "4") (pinfunction "VSS_4") (pintype "input"))
      (node (ref "IC193") (pin "4") (pinfunction "VSS_4") (pintype "input"))
      (node (ref "IC194") (pin "4") (pinfunction "VSS_4") (pintype "input"))
      (node (ref "IC195") (pin "4") (pinfunction "VSS_4") (pintype "input"))
      (node (ref "IC196") (pin "4") (pinfunction "VSS_4") (pintype "input"))
      (node (ref "IC197") (pin "4") (pinfunction "VSS_4") (pintype "input"))
      (node (ref "IC198") (pin "4") (pinfunction "VSS_4") (pintype "input"))
      (node (ref "IC199") (pin "4") (pinfunction "VSS_4") (pintype "input"))
      (node (ref "IC2") (pin "2") (pinfunction "GND_2") (pintype "input"))
      (node (ref "IC20") (pin "2") (pinfunction "GND_2") (pintype "input"))
      (node (ref "IC200") (pin "4") (pinfunction "VSS_4") (pintype "input"))
      (node (ref "IC201") (pin "4") (pinfunction "VSS_4") (pintype "input"))
      (node (ref "IC202") (pin "4") (pinfunction "VSS_4") (pintype "input"))
      (node (ref "IC203") (pin "4") (pinfunction "VSS_4") (pintype "input"))
      (node (ref "IC204") (pin "4") (pinfunction "VSS_4") (pintype "input"))
      (node (ref "IC205") (pin "4") (pinfunction "VSS_4") (pintype "input"))
      (node (ref "IC206") (pin "4") (pinfunction "VSS_4") (pintype "input"))
      (node (ref "IC207") (pin "4") (pinfunction "VSS_4") (pintype "input"))
      (node (ref "IC208") (pin "4") (pinfunction "VSS_4") (pintype "input"))
      (node (ref "IC209") (pin "4") (pinfunction "VSS_4") (pintype "input"))
      (node (ref "IC210") (pin "4") (pinfunction "VSS_4") (pintype "input"))
      (node (ref "IC211") (pin "4") (pinfunction "VSS_4") (pintype "input"))
      (node (ref "IC212") (pin "4") (pinfunction "VSS_4") (pintype "input"))
      (node (ref "IC213") (pin "4") (pinfunction "VSS_4") (pintype "input"))
      (node (ref "IC214") (pin "4") (pinfunction "VSS_4") (pintype "input"))
      (node (ref "IC215") (pin "4") (pinfunction "VSS_4") (pintype "input"))
      (node (ref "IC216") (pin "4") (pinfunction "VSS_4") (pintype "input"))
      (node (ref "IC217") (pin "4") (pinfunction "VSS_4") (pintype "input"))
      (node (ref "IC218") (pin "4") (pinfunction "VSS_4") (pintype "input"))
      (node (ref "IC219") (pin "4") (pinfunction "VSS_4") (pintype "input"))
      (node (ref "IC220") (pin "4") (pinfunction "VSS_4") (pintype "input"))
      (node (ref "IC221") (pin "4") (pinfunction "VSS_4") (pintype "input"))
      (node (ref "IC222") (pin "4") (pinfunction "VSS_4") (pintype "input"))
      (node (ref "IC223") (pin "4") (pinfunction "VSS_4") (pintype "input"))
      (node (ref "IC224") (pin "4") (pinfunction "VSS_4") (pintype "input"))
      (node (ref "IC225") (pin "4") (pinfunction "VSS_4") (pintype "input"))
      (node (ref "IC226") (pin "4") (pinfunction "VSS_4") (pintype "input"))
      (node (ref "IC227") (pin "4") (pinfunction "VSS_4") (pintype "input"))
      (node (ref "IC228") (pin "4") (pinfunction "VSS_4") (pintype "input"))
      (node (ref "IC229") (pin "4") (pinfunction "VSS_4") (pintype "input"))
      (node (ref "IC230") (pin "4") (pinfunction "VSS_4") (pintype "input"))
      (node (ref "IC231") (pin "4") (pinfunction "VSS_4") (pintype "input"))
      (node (ref "IC232") (pin "4") (pinfunction "VSS_4") (pintype "input"))
      (node (ref "IC233") (pin "4") (pinfunction "VSS_4") (pintype "input"))
      (node (ref "IC234") (pin "4") (pinfunction "VSS_4") (pintype "input"))
      (node (ref "IC235") (pin "4") (pinfunction "VSS_4") (pintype "input"))
      (node (ref "IC236") (pin "4") (pinfunction "VSS_4") (pintype "input"))
      (node (ref "IC237") (pin "4") (pinfunction "VSS_4") (pintype "input"))
      (node (ref "IC238") (pin "4") (pinfunction "VSS_4") (pintype "input"))
      (node (ref "IC239") (pin "4") (pinfunction "VSS_4") (pintype "input"))
      (node (ref "IC24") (pin "2") (pinfunction "GND_2") (pintype "input"))
      (node (ref "IC24") (pin "4") (pinfunction "ADD0_4") (pintype "input"))
      (node (ref "IC240") (pin "4") (pinfunction "VSS_4") (pintype "input"))
      (node (ref "IC241") (pin "4") (pinfunction "VSS_4") (pintype "input"))
      (node (ref "IC242") (pin "4") (pinfunction "VSS_4") (pintype "input"))
      (node (ref "IC243") (pin "4") (pinfunction "VSS_4") (pintype "input"))
      (node (ref "IC244") (pin "4") (pinfunction "VSS_4") (pintype "input"))
      (node (ref "IC245") (pin "4") (pinfunction "VSS_4") (pintype "input"))
      (node (ref "IC246") (pin "4") (pinfunction "VSS_4") (pintype "input"))
      (node (ref "IC247") (pin "4") (pinfunction "VSS_4") (pintype "input"))
      (node (ref "IC248") (pin "4") (pinfunction "VSS_4") (pintype "input"))
      (node (ref "IC249") (pin "4") (pinfunction "VSS_4") (pintype "input"))
      (node (ref "IC25") (pin "3") (pinfunction "GND_3") (pintype "input"))
      (node (ref "IC25") (pin "PAD") (pinfunction "GND_PAD") (pintype "input"))
      (node (ref "IC250") (pin "4") (pinfunction "VSS_4") (pintype "input"))
      (node (ref "IC251") (pin "4") (pinfunction "VSS_4") (pintype "input"))
      (node (ref "IC252") (pin "4") (pinfunction "VSS_4") (pintype "input"))
      (node (ref "IC253") (pin "4") (pinfunction "VSS_4") (pintype "input"))
      (node (ref "IC254") (pin "4") (pinfunction "VSS_4") (pintype "input"))
      (node (ref "IC255") (pin "4") (pinfunction "VSS_4") (pintype "input"))
      (node (ref "IC256") (pin "4") (pinfunction "VSS_4") (pintype "input"))
      (node (ref "IC257") (pin "4") (pinfunction "VSS_4") (pintype "input"))
      (node (ref "IC258") (pin "4") (pinfunction "VSS_4") (pintype "input"))
      (node (ref "IC259") (pin "4") (pinfunction "VSS_4") (pintype "input"))
      (node (ref "IC260") (pin "4") (pinfunction "VSS_4") (pintype "input"))
      (node (ref "IC261") (pin "4") (pinfunction "VSS_4") (pintype "input"))
      (node (ref "IC262") (pin "4") (pinfunction "VSS_4") (pintype "input"))
      (node (ref "IC263") (pin "4") (pinfunction "VSS_4") (pintype "input"))
      (node (ref "IC264") (pin "4") (pinfunction "VSS_4") (pintype "input"))
      (node (ref "IC265") (pin "4") (pinfunction "VSS_4") (pintype "input"))
      (node (ref "IC266") (pin "4") (pinfunction "VSS_4") (pintype "input"))
      (node (ref "IC267") (pin "4") (pinfunction "VSS_4") (pintype "input"))
      (node (ref "IC268") (pin "4") (pinfunction "VSS_4") (pintype "input"))
      (node (ref "IC269") (pin "4") (pinfunction "VSS_4") (pintype "input"))
      (node (ref "IC270") (pin "4") (pinfunction "VSS_4") (pintype "input"))
      (node (ref "IC271") (pin "4") (pinfunction "VSS_4") (pintype "input"))
      (node (ref "IC272") (pin "4") (pinfunction "VSS_4") (pintype "input"))
      (node (ref "IC273") (pin "4") (pinfunction "VSS_4") (pintype "input"))
      (node (ref "IC274") (pin "4") (pinfunction "VSS_4") (pintype "input"))
      (node (ref "IC275") (pin "4") (pinfunction "VSS_4") (pintype "input"))
      (node (ref "IC276") (pin "4") (pinfunction "VSS_4") (pintype "input"))
      (node (ref "IC277") (pin "4") (pinfunction "VSS_4") (pintype "input"))
      (node (ref "IC278") (pin "4") (pinfunction "VSS_4") (pintype "input"))
      (node (ref "IC279") (pin "4") (pinfunction "VSS_4") (pintype "input"))
      (node (ref "IC280") (pin "4") (pinfunction "VSS_4") (pintype "input"))
      (node (ref "IC281") (pin "4") (pinfunction "VSS_4") (pintype "input"))
      (node (ref "IC282") (pin "4") (pinfunction "VSS_4") (pintype "input"))
      (node (ref "IC283") (pin "4") (pinfunction "VSS_4") (pintype "input"))
      (node (ref "IC284") (pin "4") (pinfunction "VSS_4") (pintype "input"))
      (node (ref "IC285") (pin "4") (pinfunction "VSS_4") (pintype "input"))
      (node (ref "IC286") (pin "4") (pinfunction "VSS_4") (pintype "input"))
      (node (ref "IC287") (pin "4") (pinfunction "VSS_4") (pintype "input"))
      (node (ref "IC288") (pin "4") (pinfunction "VSS_4") (pintype "input"))
      (node (ref "IC289") (pin "4") (pinfunction "VSS_4") (pintype "input"))
      (node (ref "IC290") (pin "4") (pinfunction "VSS_4") (pintype "input"))
      (node (ref "IC291") (pin "4") (pinfunction "VSS_4") (pintype "input"))
      (node (ref "IC292") (pin "4") (pinfunction "VSS_4") (pintype "input"))
      (node (ref "IC293") (pin "4") (pinfunction "VSS_4") (pintype "input"))
      (node (ref "IC294") (pin "4") (pinfunction "VSS_4") (pintype "input"))
      (node (ref "IC295") (pin "4") (pinfunction "VSS_4") (pintype "input"))
      (node (ref "IC296") (pin "4") (pinfunction "VSS_4") (pintype "input"))
      (node (ref "IC297") (pin "4") (pinfunction "VSS_4") (pintype "input"))
      (node (ref "IC298") (pin "4") (pinfunction "VSS_4") (pintype "input"))
      (node (ref "IC299") (pin "4") (pinfunction "VSS_4") (pintype "input"))
      (node (ref "IC3") (pin "4") (pinfunction "GND_4") (pintype "input"))
      (node (ref "IC3") (pin "PAD") (pinfunction "GND_PAD") (pintype "input"))
      (node (ref "IC300") (pin "4") (pinfunction "VSS_4") (pintype "input"))
      (node (ref "IC301") (pin "4") (pinfunction "VSS_4") (pintype "input"))
      (node (ref "IC302") (pin "4") (pinfunction "VSS_4") (pintype "input"))
      (node (ref "IC303") (pin "4") (pinfunction "VSS_4") (pintype "input"))
      (node (ref "IC304") (pin "4") (pinfunction "VSS_4") (pintype "input"))
      (node (ref "IC305") (pin "4") (pinfunction "VSS_4") (pintype "input"))
      (node (ref "IC306") (pin "4") (pinfunction "VSS_4") (pintype "input"))
      (node (ref "IC307") (pin "4") (pinfunction "VSS_4") (pintype "input"))
      (node (ref "IC308") (pin "4") (pinfunction "VSS_4") (pintype "input"))
      (node (ref "IC309") (pin "4") (pinfunction "VSS_4") (pintype "input"))
      (node (ref "IC31") (pin "2") (pinfunction "GND_2") (pintype "power_in"))
      (node (ref "IC31") (pin "4") (pinfunction "GND_4") (pintype "power_in"))
      (node (ref "IC310") (pin "4") (pinfunction "VSS_4") (pintype "input"))
      (node (ref "IC311") (pin "4") (pinfunction "VSS_4") (pintype "input"))
      (node (ref "IC312") (pin "4") (pinfunction "VSS_4") (pintype "input"))
      (node (ref "IC313") (pin "4") (pinfunction "VSS_4") (pintype "input"))
      (node (ref "IC314") (pin "4") (pinfunction "VSS_4") (pintype "input"))
      (node (ref "IC315") (pin "4") (pinfunction "VSS_4") (pintype "input"))
      (node (ref "IC316") (pin "4") (pinfunction "VSS_4") (pintype "input"))
      (node (ref "IC317") (pin "4") (pinfunction "VSS_4") (pintype "input"))
      (node (ref "IC318") (pin "4") (pinfunction "VSS_4") (pintype "input"))
      (node (ref "IC319") (pin "4") (pinfunction "VSS_4") (pintype "input"))
      (node (ref "IC320") (pin "4") (pinfunction "VSS_4") (pintype "input"))
      (node (ref "IC321") (pin "4") (pinfunction "VSS_4") (pintype "input"))
      (node (ref "IC322") (pin "4") (pinfunction "VSS_4") (pintype "input"))
      (node (ref "IC323") (pin "4") (pinfunction "VSS_4") (pintype "input"))
      (node (ref "IC324") (pin "4") (pinfunction "VSS_4") (pintype "input"))
      (node (ref "IC325") (pin "4") (pinfunction "VSS_4") (pintype "input"))
      (node (ref "IC326") (pin "4") (pinfunction "VSS_4") (pintype "input"))
      (node (ref "IC327") (pin "4") (pinfunction "VSS_4") (pintype "input"))
      (node (ref "IC328") (pin "4") (pinfunction "VSS_4") (pintype "input"))
      (node (ref "IC329") (pin "4") (pinfunction "VSS_4") (pintype "input"))
      (node (ref "IC330") (pin "4") (pinfunction "VSS_4") (pintype "input"))
      (node (ref "IC331") (pin "4") (pinfunction "VSS_4") (pintype "input"))
      (node (ref "IC332") (pin "4") (pinfunction "VSS_4") (pintype "input"))
      (node (ref "IC4") (pin "4") (pinfunction "GND_4") (pintype "input"))
      (node (ref "IC4") (pin "6") (pinfunction "-IN_6") (pintype "input"))
      (node (ref "IC4") (pin "PAD") (pinfunction "GND_PAD") (pintype "input"))
      (node (ref "IC5") (pin "4") (pinfunction "GND_4") (pintype "input"))
      (node (ref "IC5") (pin "6") (pinfunction "-IN_6") (pintype "input"))
      (node (ref "IC5") (pin "PAD") (pinfunction "GND_PAD") (pintype "input"))
      (node (ref "IC7") (pin "12") (pinfunction "GND_12") (pintype "input"))
      (node (ref "IC7") (pin "2") (pinfunction "AVSSVCSEL_2") (pintype "input"))
      (node (ref "IC7") (pin "3") (pinfunction "GND_3") (pintype "input"))
      (node (ref "IC7") (pin "4") (pinfunction "GND_4") (pintype "input"))
      (node (ref "IC7") (pin "6") (pinfunction "GND_6") (pintype "input"))
      (node (ref "IC8") (pin "2") (pinfunction "GND_2") (pintype "input"))
      (node (ref "IC9") (pin "1") (pinfunction "CLK_1") (pintype "input"))
      (node (ref "IC9") (pin "10") (pinfunction "~{PRE}_10") (pintype "input"))
      (node (ref "IC9") (pin "11") (pinfunction "J_11") (pintype "input"))
      (node (ref "IC9") (pin "12") (pinfunction "K_12") (pintype "input"))
      (node (ref "IC9") (pin "13") (pinfunction "CLK_13") (pintype "input"))
      (node (ref "IC9") (pin "14") (pinfunction "~{CLR}_14") (pintype "input"))
      (node (ref "IC9") (pin "2") (pinfunction "K_2") (pintype "input"))
      (node (ref "IC9") (pin "3") (pinfunction "J_3") (pintype "input"))
      (node (ref "IC9") (pin "8") (pinfunction "GND_8") (pintype "input"))
      (node (ref "R18") (pin "1") (pinfunction "1_1") (pintype "passive"))
      (node (ref "R3") (pin "1") (pinfunction "1_1") (pintype "passive"))
      (node (ref "R4") (pin "1") (pinfunction "1_1") (pintype "passive"))
      (node (ref "R49") (pin "1") (pinfunction "1_1") (pintype "passive"))
      (node (ref "R5") (pin "1") (pinfunction "1_1") (pintype "passive"))
      (node (ref "R6") (pin "1") (pinfunction "1_1") (pintype "passive"))
      (node (ref "R70") (pin "1") (pinfunction "1_1") (pintype "passive"))
      (node (ref "SW1") (pin "1") (pinfunction "1A_1") (pintype "passive"))
      (node (ref "SW1") (pin "2") (pinfunction "1A_2") (pintype "passive"))
      (node (ref "T10") (pin "2") (pinfunction "S_2") (pintype "passive"))
      (node (ref "T2") (pin "2") (pinfunction "S_2") (pintype "passive"))
      (node (ref "T3") (pin "2") (pinfunction "S_2") (pintype "passive"))
      (node (ref "T6") (pin "2") (pinfunction "S_2") (pintype "passive"))
      (node (ref "T7") (pin "2") (pinfunction "S_2") (pintype "passive"))
      (node (ref "T8") (pin "2") (pinfunction "S_2") (pintype "passive"))
      (node (ref "TP1") (pin "TP") (pinfunction "TP_TP") (pintype "input"))
      (node (ref "X1") (pin "01") (pinfunction "1_01") (pintype "passive"))
      (node (ref "X1") (pin "02") (pinfunction "2_02") (pintype "passive"))
      (node (ref "X1") (pin "06") (pinfunction "6_06") (pintype "passive"))
      (node (ref "X1") (pin "07") (pinfunction "7_07") (pintype "passive"))
      (node (ref "X1") (pin "13") (pinfunction "13_13") (pintype "passive"))
      (node (ref "X1") (pin "19") (pinfunction "19_19") (pintype "passive"))
      (node (ref "X1") (pin "21") (pinfunction "21_21") (pintype "passive"))
      (node (ref "X1") (pin "26") (pinfunction "26_26") (pintype "passive"))
      (node (ref "X1") (pin "28") (pinfunction "28_28") (pintype "passive"))
      (node (ref "X1") (pin "32") (pinfunction "32_32") (pintype "passive"))
      (node (ref "X1") (pin "33") (pinfunction "33_33") (pintype "passive"))
      (node (ref "X1") (pin "39") (pinfunction "39_39") (pintype "passive"))
      (node (ref "X1") (pin "40") (pinfunction "40_40") (pintype "passive"))
      (node (ref "X2") (pin "01") (pinfunction "1_01") (pintype "passive"))
      (node (ref "X2") (pin "03") (pinfunction "3_03") (pintype "passive"))
      (node (ref "X2") (pin "05") (pinfunction "5_05") (pintype "passive"))
      (node (ref "X2") (pin "07") (pinfunction "7_07") (pintype "passive"))
      (node (ref "X2") (pin "09") (pinfunction "9_09") (pintype "passive"))
      (node (ref "X2") (pin "10") (pinfunction "10_10") (pintype "passive"))
      (node (ref "X2") (pin "11") (pinfunction "11_11") (pintype "passive"))
      (node (ref "X2") (pin "18") (pinfunction "18_18") (pintype "passive"))
      (node (ref "X2") (pin "24") (pinfunction "24_24") (pintype "passive"))
      (node (ref "X2") (pin "25") (pinfunction "25_25") (pintype "passive"))
      (node (ref "X2") (pin "28") (pinfunction "28_28") (pintype "passive"))
      (node (ref "X2") (pin "31") (pinfunction "31_31") (pintype "passive"))
      (node (ref "X2") (pin "34") (pinfunction "34_34") (pintype "passive"))
      (node (ref "X2") (pin "35") (pinfunction "35_35") (pintype "passive"))
      (node (ref "X2") (pin "37") (pinfunction "37_37") (pintype "passive"))
      (node (ref "X2") (pin "39") (pinfunction "39_39") (pintype "passive"))
      (node (ref "X2") (pin "40") (pinfunction "40_40") (pintype "passive"))
      (node (ref "X3") (pin "12") (pinfunction "12_12") (pintype "bidirectional"))
      (node (ref "X3") (pin "15") (pinfunction "15_15") (pintype "bidirectional"))
      (node (ref "X3") (pin "16") (pinfunction "16_16") (pintype "bidirectional"))
      (node (ref "X3") (pin "22") (pinfunction "22_22") (pintype "bidirectional"))
      (node (ref "X3") (pin "23") (pinfunction "23_23") (pintype "bidirectional"))
      (node (ref "X3") (pin "25") (pinfunction "25_25") (pintype "bidirectional"))
      (node (ref "X3") (pin "3") (pinfunction "3_3") (pintype "bidirectional"))
      (node (ref "X3") (pin "6") (pinfunction "6_6") (pintype "bidirectional"))
      (node (ref "X3") (pin "9") (pinfunction "9_9") (pintype "bidirectional"))
      (node (ref "X4") (pin "1") (pinfunction "1_1") (pintype "passive"))
      (node (ref "X4") (pin "11") (pinfunction "11_11") (pintype "passive"))
      (node (ref "X4") (pin "12") (pinfunction "12_12") (pintype "passive"))
      (node (ref "X4") (pin "2") (pinfunction "2_2") (pintype "passive"))
      (node (ref "X4") (pin "Z1") (pinfunction "Z1_Z1") (pintype "passive"))
      (node (ref "X4") (pin "Z2") (pinfunction "Z2_Z2") (pintype "passive"))
      (node (ref "X5") (pin "13") (pinfunction "13_13") (pintype "passive"))
      (node (ref "X5") (pin "16") (pinfunction "16_16") (pintype "passive"))
      (node (ref "X5") (pin "19") (pinfunction "19_19") (pintype "passive"))
      (node (ref "X5") (pin "22") (pinfunction "22_22") (pintype "passive"))
      (node (ref "X5") (pin "25") (pinfunction "25_25") (pintype "passive"))
      (node (ref "X5") (pin "28") (pinfunction "28_28") (pintype "passive"))
      (node (ref "X5") (pin "5") (pinfunction "5_5") (pintype "passive"))
      (node (ref "X5") (pin "9") (pinfunction "9_9") (pintype "passive"))
      (node (ref "X5") (pin "S1") (pinfunction "S_S1") (pintype "passive"))
      (node (ref "X5") (pin "S2") (pinfunction "S_S2") (pintype "passive"))
      (node (ref "X5") (pin "S3") (pinfunction "S_S3") (pintype "passive"))
      (node (ref "X5") (pin "S4") (pinfunction "S_S4") (pintype "passive"))
    )
    (net (code "40") (name "HEAT_CAM_ARESET_N_2V8") (class "Default")
      (node (ref "IC20") (pin "4") (pinfunction "I/O3_4") (pintype "passive"))
      (node (ref "X2") (pin "23") (pinfunction "23_23") (pintype "passive"))
      (node (ref "X4") (pin "5") (pinfunction "5_5") (pintype "passive"))
    )
    (net (code "41") (name "HEAT_CAM_FPA_EN_2V8") (class "Default")
      (node (ref "IC19") (pin "6") (pinfunction "I/O4_6") (pintype "passive"))
      (node (ref "X2") (pin "13") (pinfunction "13_13") (pintype "passive"))
      (node (ref "X4") (pin "10") (pinfunction "10_10") (pintype "passive"))
    )
    (net (code "42") (name "HEAT_CAM_MISO_2V8") (class "Default")
      (node (ref "IC19") (pin "1") (pinfunction "I/O1_1") (pintype "passive"))
      (node (ref "R87") (pin "2") (pinfunction "2_2") (pintype "passive"))
      (node (ref "X2") (pin "19") (pinfunction "19_19") (pintype "passive"))
    )
    (net (code "43") (name "HEAT_CAM_MOSI_2V8") (class "Default")
      (node (ref "IC19") (pin "3") (pinfunction "I/O2_3") (pintype "passive"))
      (node (ref "X2") (pin "17") (pinfunction "17_17") (pintype "passive"))
      (node (ref "X4") (pin "8") (pinfunction "8_8") (pintype "passive"))
    )
    (net (code "44") (name "HEAT_CAM_SCLK_2V8") (class "Default")
      (node (ref "IC19") (pin "4") (pinfunction "I/O3_4") (pintype "passive"))
      (node (ref "X2") (pin "15") (pinfunction "15_15") (pintype "passive"))
      (node (ref "X4") (pin "9") (pinfunction "9_9") (pintype "passive"))
    )
    (net (code "45") (name "HEAT_CAM_SCT_NSS_2V8") (class "Default")
      (node (ref "IC20") (pin "6") (pinfunction "I/O4_6") (pintype "passive"))
      (node (ref "X2") (pin "21") (pinfunction "21_21") (pintype "passive"))
      (node (ref "X4") (pin "6") (pinfunction "6_6") (pintype "passive"))
    )
    (net (code "46") (name "Net-(C78-Pad1)") (class "Default")
      (node (ref "C78") (pin "1") (pinfunction "1_1") (pintype "passive"))
      (node (ref "R16") (pin "1") (pinfunction "1_1") (pintype "passive"))
      (node (ref "X5") (pin "10") (pinfunction "10_10") (pintype "passive"))
      (node (ref "X5") (pin "12") (pinfunction "12_12") (pintype "passive"))
      (node (ref "X5") (pin "14") (pinfunction "14_14") (pintype "passive"))
    )
    (net (code "47") (name "Net-(D1-PadC)") (class "Default")
      (node (ref "D1") (pin "C") (pinfunction "C_C") (pintype "passive"))
      (node (ref "R62") (pin "2") (pinfunction "2_2") (pintype "passive"))
    )
    (net (code "48") (name "Net-(D2-PadC)") (class "Default")
      (node (ref "D2") (pin "C") (pinfunction "C_C") (pintype "passive"))
      (node (ref "R67") (pin "2") (pinfunction "2_2") (pintype "passive"))
    )
    (net (code "49") (name "Net-(D100A-A-Pad2)") (class "Default")
      (node (ref "D100") (pin "2") (pinfunction "A_2") (pintype "passive"))
      (node (ref "D100") (pin "3") (pinfunction "A_3") (pintype "passive"))
      (node (ref "D112") (pin "1") (pinfunction "C_1") (pintype "passive"))
      (node (ref "D112") (pin "4") (pinfunction "C_4") (pintype "passive"))
    )
    (net (code "50") (name "Net-(D100A-C-Pad1)") (class "Default")
      (node (ref "D100") (pin "1") (pinfunction "C_1") (pintype "passive"))
      (node (ref "D100") (pin "4") (pinfunction "C_4") (pintype "passive"))
      (node (ref "D101") (pin "2") (pinfunction "A_2") (pintype "passive"))
      (node (ref "D101") (pin "3") (pinfunction "A_3") (pintype "passive"))
    )
    (net (code "51") (name "Net-(D101A-C-Pad1)") (class "Default")
      (node (ref "D101") (pin "1") (pinfunction "C_1") (pintype "passive"))
      (node (ref "D101") (pin "4") (pinfunction "C_4") (pintype "passive"))
      (node (ref "D102") (pin "2") (pinfunction "A_2") (pintype "passive"))
      (node (ref "D102") (pin "3") (pinfunction "A_3") (pintype "passive"))
    )
    (net (code "52") (name "Net-(D102A-C-Pad1)") (class "Default")
      (node (ref "D102") (pin "1") (pinfunction "C_1") (pintype "passive"))
      (node (ref "D102") (pin "4") (pinfunction "C_4") (pintype "passive"))
      (node (ref "D103") (pin "2") (pinfunction "A_2") (pintype "passive"))
      (node (ref "D103") (pin "3") (pinfunction "A_3") (pintype "passive"))
    )
    (net (code "53") (name "Net-(D103A-C-Pad1)") (class "Default")
      (node (ref "D103") (pin "1") (pinfunction "C_1") (pintype "passive"))
      (node (ref "D103") (pin "4") (pinfunction "C_4") (pintype "passive"))
      (node (ref "D104") (pin "2") (pinfunction "A_2") (pintype "passive"))
      (node (ref "D104") (pin "3") (pinfunction "A_3") (pintype "passive"))
    )
    (net (code "54") (name "Net-(D104A-C-Pad1)") (class "Default")
      (node (ref "D104") (pin "1") (pinfunction "C_1") (pintype "passive"))
      (node (ref "D104") (pin "4") (pinfunction "C_4") (pintype "passive"))
      (node (ref "D105") (pin "2") (pinfunction "A_2") (pintype "passive"))
      (node (ref "D105") (pin "3") (pinfunction "A_3") (pintype "passive"))
    )
    (net (code "55") (name "Net-(D106A-A-Pad2)") (class "Default")
      (node (ref "D106") (pin "2") (pinfunction "A_2") (pintype "passive"))
      (node (ref "D106") (pin "3") (pinfunction "A_3") (pintype "passive"))
      (node (ref "R7") (pin "1") (pinfunction "1_1") (pintype "passive"))
      (node (ref "R83") (pin "1") (pinfunction "1_1") (pintype "passive"))
      (node (ref "R84") (pin "1") (pinfunction "1_1") (pintype "passive"))
    )
    (net (code "56") (name "Net-(D106A-C-Pad1)") (class "Default")
      (node (ref "D106") (pin "1") (pinfunction "C_1") (pintype "passive"))
      (node (ref "D106") (pin "4") (pinfunction "C_4") (pintype "passive"))
      (node (ref "D107") (pin "2") (pinfunction "A_2") (pintype "passive"))
      (node (ref "D107") (pin "3") (pinfunction "A_3") (pintype "passive"))
    )
    (net (code "57") (name "Net-(D107A-C-Pad1)") (class "Default")
      (node (ref "D107") (pin "1") (pinfunction "C_1") (pintype "passive"))
      (node (ref "D107") (pin "4") (pinfunction "C_4") (pintype "passive"))
      (node (ref "D108") (pin "2") (pinfunction "A_2") (pintype "passive"))
      (node (ref "D108") (pin "3") (pinfunction "A_3") (pintype "passive"))
    )
    (net (code "58") (name "Net-(D108A-C-Pad1)") (class "Default")
      (node (ref "D108") (pin "1") (pinfunction "C_1") (pintype "passive"))
      (node (ref "D108") (pin "4") (pinfunction "C_4") (pintype "passive"))
      (node (ref "D109") (pin "2") (pinfunction "A_2") (pintype "passive"))
      (node (ref "D109") (pin "3") (pinfunction "A_3") (pintype "passive"))
    )
    (net (code "59") (name "Net-(D109A-C-Pad1)") (class "Default")
      (node (ref "D109") (pin "1") (pinfunction "C_1") (pintype "passive"))
      (node (ref "D109") (pin "4") (pinfunction "C_4") (pintype "passive"))
      (node (ref "D110") (pin "2") (pinfunction "A_2") (pintype "passive"))
      (node (ref "D110") (pin "3") (pinfunction "A_3") (pintype "passive"))
    )
    (net (code "60") (name "Net-(D110A-C-Pad1)") (class "Default")
      (node (ref "D110") (pin "1") (pinfunction "C_1") (pintype "passive"))
      (node (ref "D110") (pin "4") (pinfunction "C_4") (pintype "passive"))
      (node (ref "D111") (pin "2") (pinfunction "A_2") (pintype "passive"))
      (node (ref "D111") (pin "3") (pinfunction "A_3") (pintype "passive"))
    )
    (net (code "61") (name "Net-(D111A-C-Pad1)") (class "Default")
      (node (ref "D111") (pin "1") (pinfunction "C_1") (pintype "passive"))
      (node (ref "D111") (pin "4") (pinfunction "C_4") (pintype "passive"))
      (node (ref "D112") (pin "2") (pinfunction "A_2") (pintype "passive"))
      (node (ref "D112") (pin "3") (pinfunction "A_3") (pintype "passive"))
    )
    (net (code "62") (name "Net-(D200-PadA)") (class "Default")
      (node (ref "D200") (pin "A") (pinfunction "A_A") (pintype "passive"))
      (node (ref "D201") (pin "C") (pinfunction "C_C") (pintype "passive"))
    )
    (net (code "63") (name "Net-(D201-PadA)") (class "Default")
      (node (ref "D201") (pin "A") (pinfunction "A_A") (pintype "passive"))
      (node (ref "D202") (pin "C") (pinfunction "C_C") (pintype "passive"))
    )
    (net (code "64") (name "Net-(D202-PadA)") (class "Default")
      (node (ref "D202") (pin "A") (pinfunction "A_A") (pintype "passive"))
      (node (ref "D203") (pin "C") (pinfunction "C_C") (pintype "passive"))
    )
    (net (code "65") (name "Net-(D203-PadA)") (class "Default")
      (node (ref "D203") (pin "A") (pinfunction "A_A") (pintype "passive"))
      (node (ref "D204") (pin "C") (pinfunction "C_C") (pintype "passive"))
    )
    (net (code "66") (name "Net-(D204-PadA)") (class "Default")
      (node (ref "D204") (pin "A") (pinfunction "A_A") (pintype "passive"))
      (node (ref "D205") (pin "C") (pinfunction "C_C") (pintype "passive"))
    )
    (net (code "67") (name "Net-(D205-PadA)") (class "Default")
      (node (ref "D205") (pin "A") (pinfunction "A_A") (pintype "passive"))
      (node (ref "D206") (pin "C") (pinfunction "C_C") (pintype "passive"))
    )
    (net (code "68") (name "Net-(D206-PadA)") (class "Default")
      (node (ref "D206") (pin "A") (pinfunction "A_A") (pintype "passive"))
      (node (ref "D215") (pin "C") (pinfunction "C_C") (pintype "passive"))
    )
    (net (code "69") (name "Net-(D207-PadA)") (class "Default")
      (node (ref "D207") (pin "A") (pinfunction "A_A") (pintype "passive"))
      (node (ref "D208") (pin "C") (pinfunction "C_C") (pintype "passive"))
    )
    (net (code "70") (name "Net-(D208-PadA)") (class "Default")
      (node (ref "D208") (pin "A") (pinfunction "A_A") (pintype "passive"))
      (node (ref "D209") (pin "C") (pinfunction "C_C") (pintype "passive"))
    )
    (net (code "71") (name "Net-(D209-PadA)") (class "Default")
      (node (ref "D209") (pin "A") (pinfunction "A_A") (pintype "passive"))
      (node (ref "D210") (pin "C") (pinfunction "C_C") (pintype "passive"))
    )
    (net (code "72") (name "Net-(D210-PadA)") (class "Default")
      (node (ref "D210") (pin "A") (pinfunction "A_A") (pintype "passive"))
      (node (ref "D211") (pin "C") (pinfunction "C_C") (pintype "passive"))
    )
    (net (code "73") (name "Net-(D211-PadA)") (class "Default")
      (node (ref "D211") (pin "A") (pinfunction "A_A") (pintype "passive"))
      (node (ref "D212") (pin "C") (pinfunction "C_C") (pintype "passive"))
    )
    (net (code "74") (name "Net-(D212-PadA)") (class "Default")
      (node (ref "D212") (pin "A") (pinfunction "A_A") (pintype "passive"))
      (node (ref "D213") (pin "C") (pinfunction "C_C") (pintype "passive"))
    )
    (net (code "75") (name "Net-(D213-PadA)") (class "Default")
      (node (ref "D213") (pin "A") (pinfunction "A_A") (pintype "passive"))
      (node (ref "D214") (pin "C") (pinfunction "C_C") (pintype "passive"))
    )
    (net (code "76") (name "Net-(D214-PadA)") (class "Default")
      (node (ref "D214") (pin "A") (pinfunction "A_A") (pintype "passive"))
      (node (ref "R34") (pin "1") (pinfunction "1_1") (pintype "passive"))
      (node (ref "R35") (pin "1") (pinfunction "1_1") (pintype "passive"))
    )
    (net (code "77") (name "Net-(D215-PadA)") (class "Default")
      (node (ref "D215") (pin "A") (pinfunction "A_A") (pintype "passive"))
      (node (ref "R20") (pin "1") (pinfunction "1_1") (pintype "passive"))
      (node (ref "R22") (pin "1") (pinfunction "1_1") (pintype "passive"))
    )
    (net (code "78") (name "Net-(D250-PadA)") (class "Default")
      (node (ref "D250") (pin "A") (pinfunction "A_A") (pintype "passive"))
      (node (ref "D251") (pin "C") (pinfunction "C_C") (pintype "passive"))
    )
    (net (code "79") (name "Net-(D251-PadA)") (class "Default")
      (node (ref "D251") (pin "A") (pinfunction "A_A") (pintype "passive"))
      (node (ref "D252") (pin "C") (pinfunction "C_C") (pintype "passive"))
    )
    (net (code "80") (name "Net-(D252-PadA)") (class "Default")
      (node (ref "D252") (pin "A") (pinfunction "A_A") (pintype "passive"))
      (node (ref "D253") (pin "C") (pinfunction "C_C") (pintype "passive"))
    )
    (net (code "81") (name "Net-(D253-PadA)") (class "Default")
      (node (ref "D253") (pin "A") (pinfunction "A_A") (pintype "passive"))
      (node (ref "D254") (pin "C") (pinfunction "C_C") (pintype "passive"))
    )
    (net (code "82") (name "Net-(D254-PadA)") (class "Default")
      (node (ref "D254") (pin "A") (pinfunction "A_A") (pintype "passive"))
      (node (ref "D255") (pin "C") (pinfunction "C_C") (pintype "passive"))
    )
    (net (code "83") (name "Net-(D255-PadA)") (class "Default")
      (node (ref "D255") (pin "A") (pinfunction "A_A") (pintype "passive"))
      (node (ref "D256") (pin "C") (pinfunction "C_C") (pintype "passive"))
    )
    (net (code "84") (name "Net-(D256-PadA)") (class "Default")
      (node (ref "D256") (pin "A") (pinfunction "A_A") (pintype "passive"))
      (node (ref "D265") (pin "C") (pinfunction "C_C") (pintype "passive"))
    )
    (net (code "85") (name "Net-(D257-PadA)") (class "Default")
      (node (ref "D257") (pin "A") (pinfunction "A_A") (pintype "passive"))
      (node (ref "D258") (pin "C") (pinfunction "C_C") (pintype "passive"))
    )
    (net (code "86") (name "Net-(D258-PadA)") (class "Default")
      (node (ref "D258") (pin "A") (pinfunction "A_A") (pintype "passive"))
      (node (ref "D259") (pin "C") (pinfunction "C_C") (pintype "passive"))
    )
    (net (code "87") (name "Net-(D259-PadA)") (class "Default")
      (node (ref "D259") (pin "A") (pinfunction "A_A") (pintype "passive"))
      (node (ref "D260") (pin "C") (pinfunction "C_C") (pintype "passive"))
    )
    (net (code "88") (name "Net-(D260-PadA)") (class "Default")
      (node (ref "D260") (pin "A") (pinfunction "A_A") (pintype "passive"))
      (node (ref "D261") (pin "C") (pinfunction "C_C") (pintype "passive"))
    )
    (net (code "89") (name "Net-(D261-PadA)") (class "Default")
      (node (ref "D261") (pin "A") (pinfunction "A_A") (pintype "passive"))
      (node (ref "D262") (pin "C") (pinfunction "C_C") (pintype "passive"))
    )
    (net (code "90") (name "Net-(D262-PadA)") (class "Default")
      (node (ref "D262") (pin "A") (pinfunction "A_A") (pintype "passive"))
      (node (ref "D263") (pin "C") (pinfunction "C_C") (pintype "passive"))
    )
    (net (code "91") (name "Net-(D263-PadA)") (class "Default")
      (node (ref "D263") (pin "A") (pinfunction "A_A") (pintype "passive"))
      (node (ref "D264") (pin "C") (pinfunction "C_C") (pintype "passive"))
    )
    (net (code "92") (name "Net-(D264-PadA)") (class "Default")
      (node (ref "D264") (pin "A") (pinfunction "A_A") (pintype "passive"))
      (node (ref "R73") (pin "1") (pinfunction "1_1") (pintype "passive"))
      (node (ref "R75") (pin "1") (pinfunction "1_1") (pintype "passive"))
    )
    (net (code "93") (name "Net-(D265-PadA)") (class "Default")
      (node (ref "D265") (pin "A") (pinfunction "A_A") (pintype "passive"))
      (node (ref "R52") (pin "1") (pinfunction "1_1") (pintype "passive"))
      (node (ref "R57") (pin "1") (pinfunction "1_1") (pintype "passive"))
    )
    (net (code "94") (name "Net-(D300-PadA)") (class "Default")
      (node (ref "D300") (pin "A") (pinfunction "A_A") (pintype "passive"))
      (node (ref "D301") (pin "C") (pinfunction "C_C") (pintype "passive"))
    )
    (net (code "95") (name "Net-(D300-PadC)") (class "Default")
      (node (ref "D300") (pin "C") (pinfunction "C_C") (pintype "passive"))
      (node (ref "D307") (pin "A") (pinfunction "A_A") (pintype "passive"))
    )
    (net (code "96") (name "Net-(D301-PadA)") (class "Default")
      (node (ref "D301") (pin "A") (pinfunction "A_A") (pintype "passive"))
      (node (ref "D302") (pin "C") (pinfunction "C_C") (pintype "passive"))
    )
    (net (code "97") (name "Net-(D302-PadA)") (class "Default")
      (node (ref "D302") (pin "A") (pinfunction "A_A") (pintype "passive"))
      (node (ref "D303") (pin "C") (pinfunction "C_C") (pintype "passive"))
    )
    (net (code "98") (name "Net-(D303-PadA)") (class "Default")
      (node (ref "D303") (pin "A") (pinfunction "A_A") (pintype "passive"))
      (node (ref "D304") (pin "C") (pinfunction "C_C") (pintype "passive"))
    )
    (net (code "99") (name "Net-(D304-PadA)") (class "Default")
      (node (ref "D304") (pin "A") (pinfunction "A_A") (pintype "passive"))
      (node (ref "D305") (pin "C") (pinfunction "C_C") (pintype "passive"))
    )
    (net (code "100") (name "Net-(D305-PadA)") (class "Default")
      (node (ref "D305") (pin "A") (pinfunction "A_A") (pintype "passive"))
      (node (ref "R15") (pin "1") (pinfunction "1_1") (pintype "passive"))
      (node (ref "R8") (pin "1") (pinfunction "1_1") (pintype "passive"))
    )
    (net (code "101") (name "Net-(D306-PadA)") (class "Default")
      (node (ref "D306") (pin "A") (pinfunction "A_A") (pintype "passive"))
      (node (ref "D307") (pin "C") (pinfunction "C_C") (pintype "passive"))
    )
    (net (code "102") (name "Net-(D308-PadA)") (class "Default")
      (node (ref "D308") (pin "A") (pinfunction "A_A") (pintype "passive"))
      (node (ref "D309") (pin "C") (pinfunction "C_C") (pintype "passive"))
    )
    (net (code "103") (name "Net-(D309-PadA)") (class "Default")
      (node (ref "D309") (pin "A") (pinfunction "A_A") (pintype "passive"))
      (node (ref "D310") (pin "C") (pinfunction "C_C") (pintype "passive"))
    )
    (net (code "104") (name "Net-(D310-PadA)") (class "Default")
      (node (ref "D310") (pin "A") (pinfunction "A_A") (pintype "passive"))
      (node (ref "D311") (pin "C") (pinfunction "C_C") (pintype "passive"))
    )
    (net (code "105") (name "Net-(D311-PadA)") (class "Default")
      (node (ref "D311") (pin "A") (pinfunction "A_A") (pintype "passive"))
      (node (ref "D312") (pin "C") (pinfunction "C_C") (pintype "passive"))
    )
    (net (code "106") (name "Net-(D312-PadA)") (class "Default")
      (node (ref "D312") (pin "A") (pinfunction "A_A") (pintype "passive"))
      (node (ref "D313") (pin "C") (pinfunction "C_C") (pintype "passive"))
    )
    (net (code "107") (name "Net-(D313-PadA)") (class "Default")
      (node (ref "D313") (pin "A") (pinfunction "A_A") (pintype "passive"))
      (node (ref "D314") (pin "C") (pinfunction "C_C") (pintype "passive"))
    )
    (net (code "108") (name "Net-(D314-PadA)") (class "Default")
      (node (ref "D314") (pin "A") (pinfunction "A_A") (pintype "passive"))
      (node (ref "D315") (pin "C") (pinfunction "C_C") (pintype "passive"))
    )
    (net (code "109") (name "Net-(D315-PadA)") (class "Default")
      (node (ref "D315") (pin "A") (pinfunction "A_A") (pintype "passive"))
      (node (ref "R25") (pin "1") (pinfunction "1_1") (pintype "passive"))
      (node (ref "R29") (pin "1") (pinfunction "1_1") (pintype "passive"))
    )
    (net (code "110") (name "Net-(D350-PadA)") (class "Default")
      (node (ref "D350") (pin "A") (pinfunction "A_A") (pintype "passive"))
      (node (ref "D351") (pin "C") (pinfunction "C_C") (pintype "passive"))
    )
    (net (code "111") (name "Net-(D350-PadC)") (class "Default")
      (node (ref "D350") (pin "C") (pinfunction "C_C") (pintype "passive"))
      (node (ref "D357") (pin "A") (pinfunction "A_A") (pintype "passive"))
    )
    (net (code "112") (name "Net-(D351-PadA)") (class "Default")
      (node (ref "D351") (pin "A") (pinfunction "A_A") (pintype "passive"))
      (node (ref "D352") (pin "C") (pinfunction "C_C") (pintype "passive"))
    )
    (net (code "113") (name "Net-(D352-PadA)") (class "Default")
      (node (ref "D352") (pin "A") (pinfunction "A_A") (pintype "passive"))
      (node (ref "D353") (pin "C") (pinfunction "C_C") (pintype "passive"))
    )
    (net (code "114") (name "Net-(D353-PadA)") (class "Default")
      (node (ref "D353") (pin "A") (pinfunction "A_A") (pintype "passive"))
      (node (ref "D354") (pin "C") (pinfunction "C_C") (pintype "passive"))
    )
    (net (code "115") (name "Net-(D354-PadA)") (class "Default")
      (node (ref "D354") (pin "A") (pinfunction "A_A") (pintype "passive"))
      (node (ref "D355") (pin "C") (pinfunction "C_C") (pintype "passive"))
    )
    (net (code "116") (name "Net-(D355-PadA)") (class "Default")
      (node (ref "D355") (pin "A") (pinfunction "A_A") (pintype "passive"))
      (node (ref "R43") (pin "1") (pinfunction "1_1") (pintype "passive"))
      (node (ref "R46") (pin "1") (pinfunction "1_1") (pintype "passive"))
    )
    (net (code "117") (name "Net-(D356-PadA)") (class "Default")
      (node (ref "D356") (pin "A") (pinfunction "A_A") (pintype "passive"))
      (node (ref "D357") (pin "C") (pinfunction "C_C") (pintype "passive"))
    )
    (net (code "118") (name "Net-(D358-PadA)") (class "Default")
      (node (ref "D358") (pin "A") (pinfunction "A_A") (pintype "passive"))
      (node (ref "D359") (pin "C") (pinfunction "C_C") (pintype "passive"))
    )
    (net (code "119") (name "Net-(D359-PadA)") (class "Default")
      (node (ref "D359") (pin "A") (pinfunction "A_A") (pintype "passive"))
      (node (ref "D360") (pin "C") (pinfunction "C_C") (pintype "passive"))
    )
    (net (code "120") (name "Net-(D360-PadA)") (class "Default")
      (node (ref "D360") (pin "A") (pinfunction "A_A") (pintype "passive"))
      (node (ref "D361") (pin "C") (pinfunction "C_C") (pintype "passive"))
    )
    (net (code "121") (name "Net-(D361-PadA)") (class "Default")
      (node (ref "D361") (pin "A") (pinfunction "A_A") (pintype "passive"))
      (node (ref "D362") (pin "C") (pinfunction "C_C") (pintype "passive"))
    )
    (net (code "122") (name "Net-(D362-PadA)") (class "Default")
      (node (ref "D362") (pin "A") (pinfunction "A_A") (pintype "passive"))
      (node (ref "D363") (pin "C") (pinfunction "C_C") (pintype "passive"))
    )
    (net (code "123") (name "Net-(D363-PadA)") (class "Default")
      (node (ref "D363") (pin "A") (pinfunction "A_A") (pintype "passive"))
      (node (ref "D364") (pin "C") (pinfunction "C_C") (pintype "passive"))
    )
    (net (code "124") (name "Net-(D364-PadA)") (class "Default")
      (node (ref "D364") (pin "A") (pinfunction "A_A") (pintype "passive"))
      (node (ref "D365") (pin "C") (pinfunction "C_C") (pintype "passive"))
    )
    (net (code "125") (name "Net-(D365-PadA)") (class "Default")
      (node (ref "D365") (pin "A") (pinfunction "A_A") (pintype "passive"))
      (node (ref "R66") (pin "1") (pinfunction "1_1") (pintype "passive"))
      (node (ref "R69") (pin "1") (pinfunction "1_1") (pintype "passive"))
    )
    (net (code "126") (name "Net-(IC1-OUT)") (class "Default")
      (node (ref "IC1") (pin "5") (pinfunction "OUT_5") (pintype "output"))
      (node (ref "R21") (pin "1") (pinfunction "1_1") (pintype "passive"))
    )
    (net (code "127") (name "Net-(IC1-VDD)") (class "Default")
      (node (ref "C3") (pin "1") (pinfunction "1_1") (pintype "passive"))
      (node (ref "IC1") (pin "1") (pinfunction "VDD_1") (pintype "input"))
      (node (ref "R1") (pin "2") (pinfunction "2_2") (pintype "passive"))
    )
    (net (code "128") (name "Net-(IC2-OUT)") (class "Default")
      (node (ref "IC2") (pin "5") (pinfunction "OUT_5") (pintype "output"))
      (node (ref "R23") (pin "1") (pinfunction "1_1") (pintype "passive"))
    )
    (net (code "129") (name "Net-(IC2-VDD)") (class "Default")
      (node (ref "C5") (pin "1") (pinfunction "1_1") (pintype "passive"))
      (node (ref "IC2") (pin "1") (pinfunction "VDD_1") (pintype "input"))
      (node (ref "R9") (pin "2") (pinfunction "2_2") (pintype "passive"))
    )
    (net (code "130") (name "Net-(IC3A-+IN)") (class "Default")
      (node (ref "C11") (pin "2") (pinfunction "2_2") (pintype "passive"))
      (node (ref "IC3") (pin "3") (pinfunction "+IN_3") (pintype "input"))
      (node (ref "IC3") (pin "5") (pinfunction "+IN_5") (pintype "input"))
      (node (ref "IC4") (pin "3") (pinfunction "+IN_3") (pintype "input"))
      (node (ref "IC4") (pin "5") (pinfunction "+IN_5") (pintype "input"))
      (node (ref "IC5") (pin "3") (pinfunction "+IN_3") (pintype "input"))
      (node (ref "IC5") (pin "5") (pinfunction "+IN_5") (pintype "input"))
      (node (ref "R17") (pin "1") (pinfunction "1_1") (pintype "passive"))
      (node (ref "R18") (pin "2") (pinfunction "2_2") (pintype "passive"))
    )
    (net (code "131") (name "Net-(IC3A--IN)") (class "Default")
      (node (ref "C6") (pin "1") (pinfunction "1_1") (pintype "passive"))
      (node (ref "IC3") (pin "2") (pinfunction "-IN_2") (pintype "input"))
      (node (ref "R10") (pin "2") (pinfunction "2_2") (pintype "passive"))
    )
    (net (code "132") (name "Net-(IC3A-OUT)") (class "Default")
      (node (ref "IC3") (pin "1") (pinfunction "OUT_1") (pintype "output"))
      (node (ref "IC3") (pin "7") (pinfunction "OUT_7") (pintype "output"))
      (node (ref "IC4") (pin "1") (pinfunction "OUT_1") (pintype "output"))
      (node (ref "IC5") (pin "1") (pinfunction "OUT_1") (pintype "output"))
      (node (ref "IC5") (pin "7") (pinfunction "OUT_7") (pintype "output"))
      (node (ref "R24") (pin "1") (pinfunction "1_1") (pintype "passive"))
    )
    (net (code "133") (name "Net-(IC3B--IN)") (class "Default")
      (node (ref "C7") (pin "1") (pinfunction "1_1") (pintype "passive"))
      (node (ref "IC3") (pin "6") (pinfunction "-IN_6") (pintype "input"))
      (node (ref "R11") (pin "2") (pinfunction "2_2") (pintype "passive"))
    )
    (net (code "134") (name "Net-(IC3C-VCC)") (class "Default")
      (node (ref "C17") (pin "1") (pinfunction "1_1") (pintype "passive"))
      (node (ref "IC3") (pin "8") (pinfunction "VCC_8") (pintype "input"))
      (node (ref "R26") (pin "1") (pinfunction "1_1") (pintype "passive"))
    )
    (net (code "135") (name "Net-(IC4A--IN)") (class "Default")
      (node (ref "C8") (pin "1") (pinfunction "1_1") (pintype "passive"))
      (node (ref "IC4") (pin "2") (pinfunction "-IN_2") (pintype "input"))
      (node (ref "R12") (pin "2") (pinfunction "2_2") (pintype "passive"))
    )
    (net (code "136") (name "Net-(IC4C-VCC)") (class "Default")
      (node (ref "C18") (pin "1") (pinfunction "1_1") (pintype "passive"))
      (node (ref "IC4") (pin "8") (pinfunction "VCC_8") (pintype "input"))
      (node (ref "R27") (pin "1") (pinfunction "1_1") (pintype "passive"))
    )
    (net (code "137") (name "Net-(IC5A--IN)") (class "Default")
      (node (ref "C9") (pin "1") (pinfunction "1_1") (pintype "passive"))
      (node (ref "IC5") (pin "2") (pinfunction "-IN_2") (pintype "input"))
      (node (ref "R13") (pin "2") (pinfunction "2_2") (pintype "passive"))
    )
    (net (code "138") (name "Net-(IC5C-VCC)") (class "Default")
      (node (ref "C19") (pin "1") (pinfunction "1_1") (pintype "passive"))
      (node (ref "IC5") (pin "8") (pinfunction "VCC_8") (pintype "input"))
      (node (ref "R28") (pin "1") (pinfunction "1_1") (pintype "passive"))
    )
    (net (code "139") (name "Net-(IC7-AVDD)") (class "Default")
      (node (ref "C57") (pin "1") (pinfunction "1_1") (pintype "passive"))
      (node (ref "C58") (pin "1") (pinfunction "1_1") (pintype "passive"))
      (node (ref "IC7") (pin "1") (pinfunction "AVDDVCSEL_1") (pintype "input"))
      (node (ref "IC7") (pin "11") (pinfunction "AVDD_11") (pintype "input"))
      (node (ref "R19") (pin "2") (pinfunction "2_2") (pintype "passive"))
      (node (ref "R2") (pin "2") (pinfunction "2_2") (pintype "passive"))
    )
    (net (code "140") (name "Net-(IC7-SCL)") (class "Default")
      (node (ref "IC7") (pin "10") (pinfunction "SCL_10") (pintype "input"))
      (node (ref "R32") (pin "1") (pinfunction "1_1") (pintype "passive"))
    )
    (net (code "141") (name "Net-(IC7-SDA)") (class "Default")
      (node (ref "IC7") (pin "9") (pinfunction "SDA_9") (pintype "open_collector"))
      (node (ref "R30") (pin "1") (pinfunction "1_1") (pintype "passive"))
    )
    (net (code "142") (name "Net-(IC7-XSHUT)") (class "Default")
      (node (ref "IC7") (pin "5") (pinfunction "XSHUT_5") (pintype "input"))
      (node (ref "R2") (pin "1") (pinfunction "1_1") (pintype "passive"))
    )
    (net (code "143") (name "Net-(IC8-OUT)") (class "Default")
      (node (ref "IC8") (pin "5") (pinfunction "OUT_5") (pintype "output"))
      (node (ref "R54") (pin "1") (pinfunction "1_1") (pintype "passive"))
      (node (ref "TP5") (pin "TP") (pinfunction "TP_TP") (pintype "input"))
    )
    (net (code "144") (name "Net-(IC8-VDD)") (class "Default")
      (node (ref "C24") (pin "1") (pinfunction "1_1") (pintype "passive"))
      (node (ref "IC8") (pin "1") (pinfunction "VDD_1") (pintype "input"))
      (node (ref "R38") (pin "2") (pinfunction "2_2") (pintype "passive"))
    )
    (net (code "145") (name "Net-(IC9A-Q)") (class "Default")
      (node (ref "IC9") (pin "5") (pinfunction "Q_5") (pintype "output"))
      (node (ref "R55") (pin "1") (pinfunction "1_1") (pintype "passive"))
    )
    (net (code "146") (name "Net-(IC9A-~{PRE})") (class "Default")
      (node (ref "C23") (pin "1") (pinfunction "1_1") (pintype "passive"))
      (node (ref "IC9") (pin "4") (pinfunction "~{PRE}_4") (pintype "input"))
      (node (ref "R37") (pin "2") (pinfunction "2_2") (pintype "passive"))
      (node (ref "R40") (pin "1") (pinfunction "1_1") (pintype "passive"))
    )
    (net (code "147") (name "Net-(IC9A-~{Q})") (class "Default")
      (node (ref "IC9") (pin "6") (pinfunction "~{Q}_6") (pintype "output"))
      (node (ref "R56") (pin "1") (pinfunction "1_1") (pintype "passive"))
    )
    (net (code "148") (name "Net-(IC9C-VCC)") (class "Default")
      (node (ref "C34") (pin "1") (pinfunction "1_1") (pintype "passive"))
      (node (ref "IC9") (pin "16") (pinfunction "VCC_16") (pintype "input"))
      (node (ref "R76") (pin "1") (pinfunction "1_1") (pintype "passive"))
    )
    (net (code "149") (name "Net-(IC10-OUT)") (class "Default")
      (node (ref "IC10") (pin "5") (pinfunction "OUT_5") (pintype "output"))
      (node (ref "R59") (pin "1") (pinfunction "1_1") (pintype "passive"))
    )
    (net (code "150") (name "Net-(IC10-VDD)") (class "Default")
      (node (ref "C26") (pin "1") (pinfunction "1_1") (pintype "passive"))
      (node (ref "IC10") (pin "1") (pinfunction "VDD_1") (pintype "input"))
      (node (ref "R44") (pin "2") (pinfunction "2_2") (pintype "passive"))
    )
    (net (code "151") (name "Net-(IC13-OUT)") (class "Default")
      (node (ref "IC13") (pin "5") (pinfunction "OUT_5") (pintype "output"))
      (node (ref "R80") (pin "1") (pinfunction "1_1") (pintype "passive"))
      (node (ref "TP18") (pin "TP") (pinfunction "TP_TP") (pintype "input"))
    )
    (net (code "152") (name "Net-(IC13-VDD)") (class "Default")
      (node (ref "C38") (pin "1") (pinfunction "1_1") (pintype "passive"))
      (node (ref "IC13") (pin "1") (pinfunction "VDD_1") (pintype "input"))
      (node (ref "R78") (pin "2") (pinfunction "2_2") (pintype "passive"))
    )
    (net (code "153") (name "Net-(IC15-SCL)") (class "Default")
      (node (ref "IC15") (pin "2") (pinfunction "SCL_2") (pintype "input"))
      (node (ref "IC24") (pin "1") (pinfunction "SCL_1") (pintype "input"))
      (node (ref "R82") (pin "1") (pinfunction "1_1") (pintype "passive"))
    )
    (net (code "154") (name "Net-(IC15-SDA)") (class "Default")
      (node (ref "IC15") (pin "1") (pinfunction "SDA_1") (pintype "open_collector"))
      (node (ref "IC24") (pin "6") (pinfunction "SDA_6") (pintype "open_collector"))
      (node (ref "R81") (pin "1") (pinfunction "1_1") (pintype "passive"))
    )
    (net (code "155") (name "Net-(IC15-VCC)") (class "Default")
      (node (ref "C40") (pin "1") (pinfunction "1_1") (pintype "passive"))
      (node (ref "IC15") (pin "8") (pinfunction "VCC_8") (pintype "input"))
      (node (ref "IC24") (pin "5") (pinfunction "V+_5") (pintype "input"))
      (node (ref "R79") (pin "1") (pinfunction "1_1") (pintype "passive"))
    )
    (net (code "156") (name "Net-(IC25-DNC1)") (class "Default")
      (node (ref "IC25") (pin "4") (pinfunction "DNC1_4") (pintype "output"))
      (node (ref "R70") (pin "2") (pinfunction "2_2") (pintype "passive"))
    )
    (net (code "157") (name "Net-(IC25-SCL)") (class "Default")
      (node (ref "IC25") (pin "5") (pinfunction "SCL_5") (pintype "bidirectional"))
      (node (ref "R39") (pin "1") (pinfunction "1_1") (pintype "passive"))
    )
    (net (code "158") (name "Net-(IC25-SDA)") (class "Default")
      (node (ref "IC25") (pin "6") (pinfunction "SDA_6") (pintype "bidirectional"))
      (node (ref "R33") (pin "1") (pinfunction "1_1") (pintype "passive"))
    )
    (net (code "159") (name "Net-(IC25-TEST)") (class "Default")
      (node (ref "IC25") (pin "1") (pinfunction "TEST_1") (pintype "input"))
      (node (ref "R49") (pin "2") (pinfunction "2_2") (pintype "passive"))
      (node (ref "R71") (pin "1") (pinfunction "1_1") (pintype "passive"))
    )
    (net (code "160") (name "Net-(IC25-VCC)") (class "Default")
      (node (ref "C59") (pin "1") (pinfunction "1_1") (pintype "passive"))
      (node (ref "IC25") (pin "2") (pinfunction "VCC_2") (pintype "input"))
      (node (ref "R71") (pin "2") (pinfunction "2_2") (pintype "passive"))
      (node (ref "R72") (pin "2") (pinfunction "2_2") (pintype "passive"))
    )
    (net (code "161") (name "Net-(IC31-EN)") (class "Default")
      (node (ref "C60") (pin "1") (pinfunction "1_1") (pintype "passive"))
      (node (ref "IC31") (pin "1") (pinfunction "IN_1") (pintype "input"))
      (node (ref "IC31") (pin "3") (pinfunction "EN_3") (pintype "input"))
      (node (ref "L11") (pin "1") (pinfunction "1_1") (pintype "passive"))
    )
    (net (code "162") (name "Net-(IC31-OUT)") (class "Default")
      (node (ref "C61") (pin "1") (pinfunction "1_1") (pintype "passive"))
      (node (ref "IC31") (pin "5") (pinfunction "OUT_5") (pintype "passive"))
      (node (ref "L14") (pin "2") (pinfunction "2_2") (pintype "passive"))
    )
    (net (code "163") (name "Net-(IC100-DOUT)") (class "Default")
      (node (ref "IC100") (pin "3") (pinfunction "DOUT_3") (pintype "output"))
      (node (ref "IC101") (pin "1") (pinfunction "DIN_1") (pintype "input"))
    )
    (net (code "164") (name "Net-(IC101-DOUT)") (class "Default")
      (node (ref "IC101") (pin "3") (pinfunction "DOUT_3") (pintype "output"))
      (node (ref "IC102") (pin "1") (pinfunction "DIN_1") (pintype "input"))
    )
    (net (code "165") (name "Net-(IC102-DOUT)") (class "Default")
      (node (ref "IC102") (pin "3") (pinfunction "DOUT_3") (pintype "output"))
      (node (ref "IC103") (pin "1") (pinfunction "DIN_1") (pintype "input"))
    )
    (net (code "166") (name "Net-(IC103-DOUT)") (class "Default")
      (node (ref "IC103") (pin "3") (pinfunction "DOUT_3") (pintype "output"))
      (node (ref "IC104") (pin "1") (pinfunction "DIN_1") (pintype "input"))
    )
    (net (code "167") (name "Net-(IC105-DOUT)") (class "Default")
      (node (ref "IC105") (pin "3") (pinfunction "DOUT_3") (pintype "output"))
      (node (ref "IC106") (pin "1") (pinfunction "DIN_1") (pintype "input"))
    )
    (net (code "168") (name "Net-(IC106-DOUT)") (class "Default")
      (node (ref "IC106") (pin "3") (pinfunction "DOUT_3") (pintype "output"))
      (node (ref "IC107") (pin "1") (pinfunction "DIN_1") (pintype "input"))
    )
    (net (code "169") (name "Net-(IC107-DOUT)") (class "Default")
      (node (ref "IC107") (pin "3") (pinfunction "DOUT_3") (pintype "output"))
      (node (ref "IC108") (pin "1") (pinfunction "DIN_1") (pintype "input"))
    )
    (net (code "170") (name "Net-(IC108-DOUT)") (class "Default")
      (node (ref "IC108") (pin "3") (pinfunction "DOUT_3") (pintype "output"))
      (node (ref "IC109") (pin "1") (pinfunction "DIN_1") (pintype "input"))
    )
    (net (code "171") (name "Net-(IC110-DOUT)") (class "Default")
      (node (ref "IC110") (pin "3") (pinfunction "DOUT_3") (pintype "output"))
      (node (ref "IC111") (pin "1") (pinfunction "DIN_1") (pintype "input"))
    )
    (net (code "172") (name "Net-(IC111-DOUT)") (class "Default")
      (node (ref "IC111") (pin "3") (pinfunction "DOUT_3") (pintype "output"))
      (node (ref "IC112") (pin "1") (pinfunction "DIN_1") (pintype "input"))
    )
    (net (code "173") (name "Net-(IC112-DOUT)") (class "Default")
      (node (ref "IC112") (pin "3") (pinfunction "DOUT_3") (pintype "output"))
      (node (ref "IC113") (pin "1") (pinfunction "DIN_1") (pintype "input"))
    )
    (net (code "174") (name "Net-(IC113-DOUT)") (class "Default")
      (node (ref "IC113") (pin "3") (pinfunction "DOUT_3") (pintype "output"))
      (node (ref "IC114") (pin "1") (pinfunction "DIN_1") (pintype "input"))
    )
    (net (code "175") (name "Net-(IC115-DOUT)") (class "Default")
      (node (ref "IC115") (pin "3") (pinfunction "DOUT_3") (pintype "output"))
      (node (ref "IC116") (pin "1") (pinfunction "DIN_1") (pintype "input"))
    )
    (net (code "176") (name "Net-(IC116-DOUT)") (class "Default")
      (node (ref "IC116") (pin "3") (pinfunction "DOUT_3") (pintype "output"))
      (node (ref "IC117") (pin "1") (pinfunction "DIN_1") (pintype "input"))
    )
    (net (code "177") (name "Net-(IC117-DOUT)") (class "Default")
      (node (ref "IC117") (pin "3") (pinfunction "DOUT_3") (pintype "output"))
      (node (ref "IC118") (pin "1") (pinfunction "DIN_1") (pintype "input"))
    )
    (net (code "178") (name "Net-(IC118-DOUT)") (class "Default")
      (node (ref "IC118") (pin "3") (pinfunction "DOUT_3") (pintype "output"))
      (node (ref "IC119") (pin "1") (pinfunction "DIN_1") (pintype "input"))
    )
    (net (code "179") (name "Net-(IC120-DOUT)") (class "Default")
      (node (ref "IC120") (pin "3") (pinfunction "DOUT_3") (pintype "output"))
      (node (ref "IC121") (pin "1") (pinfunction "DIN_1") (pintype "input"))
    )
    (net (code "180") (name "Net-(IC121-DOUT)") (class "Default")
      (node (ref "IC121") (pin "3") (pinfunction "DOUT_3") (pintype "output"))
      (node (ref "IC122") (pin "1") (pinfunction "DIN_1") (pintype "input"))
    )
    (net (code "181") (name "Net-(IC122-DOUT)") (class "Default")
      (node (ref "IC122") (pin "3") (pinfunction "DOUT_3") (pintype "output"))
      (node (ref "IC123") (pin "1") (pinfunction "DIN_1") (pintype "input"))
    )
    (net (code "182") (name "Net-(IC123-DOUT)") (class "Default")
      (node (ref "IC123") (pin "3") (pinfunction "DOUT_3") (pintype "output"))
      (node (ref "IC124") (pin "1") (pinfunction "DIN_1") (pintype "input"))
    )
    (net (code "183") (name "Net-(IC125-DOUT)") (class "Default")
      (node (ref "IC125") (pin "3") (pinfunction "DOUT_3") (pintype "output"))
      (node (ref "IC126") (pin "1") (pinfunction "DIN_1") (pintype "input"))
    )
    (net (code "184") (name "Net-(IC126-DOUT)") (class "Default")
      (node (ref "IC126") (pin "3") (pinfunction "DOUT_3") (pintype "output"))
      (node (ref "IC127") (pin "1") (pinfunction "DIN_1") (pintype "input"))
    )
    (net (code "185") (name "Net-(IC127-DOUT)") (class "Default")
      (node (ref "IC127") (pin "3") (pinfunction "DOUT_3") (pintype "output"))
      (node (ref "IC128") (pin "1") (pinfunction "DIN_1") (pintype "input"))
    )
    (net (code "186") (name "Net-(IC128-DOUT)") (class "Default")
      (node (ref "IC128") (pin "3") (pinfunction "DOUT_3") (pintype "output"))
      (node (ref "IC129") (pin "1") (pinfunction "DIN_1") (pintype "input"))
    )
    (net (code "187") (name "Net-(IC130-DOUT)") (class "Default")
      (node (ref "IC130") (pin "3") (pinfunction "DOUT_3") (pintype "output"))
      (node (ref "IC131") (pin "1") (pinfunction "DIN_1") (pintype "input"))
    )
    (net (code "188") (name "Net-(IC131-DOUT)") (class "Default")
      (node (ref "IC131") (pin "3") (pinfunction "DOUT_3") (pintype "output"))
      (node (ref "IC132") (pin "1") (pinfunction "DIN_1") (pintype "input"))
    )
    (net (code "189") (name "Net-(IC132-DOUT)") (class "Default")
      (node (ref "IC132") (pin "3") (pinfunction "DOUT_3") (pintype "output"))
      (node (ref "IC133") (pin "1") (pinfunction "DIN_1") (pintype "input"))
    )
    (net (code "190") (name "Net-(IC133-DOUT)") (class "Default")
      (node (ref "IC133") (pin "3") (pinfunction "DOUT_3") (pintype "output"))
      (node (ref "IC134") (pin "1") (pinfunction "DIN_1") (pintype "input"))
    )
    (net (code "191") (name "Net-(IC135-DOUT)") (class "Default")
      (node (ref "IC135") (pin "3") (pinfunction "DOUT_3") (pintype "output"))
      (node (ref "IC136") (pin "1") (pinfunction "DIN_1") (pintype "input"))
    )
    (net (code "192") (name "Net-(IC136-DOUT)") (class "Default")
      (node (ref "IC136") (pin "3") (pinfunction "DOUT_3") (pintype "output"))
      (node (ref "IC137") (pin "1") (pinfunction "DIN_1") (pintype "input"))
    )
    (net (code "193") (name "Net-(IC137-DOUT)") (class "Default")
      (node (ref "IC137") (pin "3") (pinfunction "DOUT_3") (pintype "output"))
      (node (ref "IC138") (pin "1") (pinfunction "DIN_1") (pintype "input"))
    )
    (net (code "194") (name "Net-(IC138-DOUT)") (class "Default")
      (node (ref "IC138") (pin "3") (pinfunction "DOUT_3") (pintype "output"))
      (node (ref "IC139") (pin "1") (pinfunction "DIN_1") (pintype "input"))
    )
    (net (code "195") (name "Net-(IC140-DOUT)") (class "Default")
      (node (ref "IC140") (pin "3") (pinfunction "DOUT_3") (pintype "output"))
      (node (ref "IC141") (pin "1") (pinfunction "DIN_1") (pintype "input"))
    )
    (net (code "196") (name "Net-(IC141-DOUT)") (class "Default")
      (node (ref "IC141") (pin "3") (pinfunction "DOUT_3") (pintype "output"))
      (node (ref "IC142") (pin "1") (pinfunction "DIN_1") (pintype "input"))
    )
    (net (code "197") (name "Net-(IC142-DOUT)") (class "Default")
      (node (ref "IC142") (pin "3") (pinfunction "DOUT_3") (pintype "output"))
      (node (ref "IC143") (pin "1") (pinfunction "DIN_1") (pintype "input"))
    )
    (net (code "198") (name "Net-(IC143-DOUT)") (class "Default")
      (node (ref "IC143") (pin "3") (pinfunction "DOUT_3") (pintype "output"))
      (node (ref "IC144") (pin "1") (pinfunction "DIN_1") (pintype "input"))
    )
    (net (code "199") (name "Net-(IC145-DOUT)") (class "Default")
      (node (ref "IC145") (pin "3") (pinfunction "DOUT_3") (pintype "output"))
      (node (ref "IC146") (pin "1") (pinfunction "DIN_1") (pintype "input"))
    )
    (net (code "200") (name "Net-(IC146-DOUT)") (class "Default")
      (node (ref "IC146") (pin "3") (pinfunction "DOUT_3") (pintype "output"))
      (node (ref "IC147") (pin "1") (pinfunction "DIN_1") (pintype "input"))
    )
    (net (code "201") (name "Net-(IC147-DOUT)") (class "Default")
      (node (ref "IC147") (pin "3") (pinfunction "DOUT_3") (pintype "output"))
      (node (ref "IC148") (pin "1") (pinfunction "DIN_1") (pintype "input"))
    )
    (net (code "202") (name "Net-(IC148-DOUT)") (class "Default")
      (node (ref "IC148") (pin "3") (pinfunction "DOUT_3") (pintype "output"))
      (node (ref "IC149") (pin "1") (pinfunction "DIN_1") (pintype "input"))
    )
    (net (code "203") (name "Net-(IC150-DOUT)") (class "Default")
      (node (ref "IC150") (pin "3") (pinfunction "DOUT_3") (pintype "output"))
      (node (ref "IC151") (pin "1") (pinfunction "DIN_1") (pintype "input"))
    )
    (net (code "204") (name "Net-(IC151-DOUT)") (class "Default")
      (node (ref "IC151") (pin "3") (pinfunction "DOUT_3") (pintype "output"))
      (node (ref "IC152") (pin "1") (pinfunction "DIN_1") (pintype "input"))
    )
    (net (code "205") (name "Net-(IC152-DOUT)") (class "Default")
      (node (ref "IC152") (pin "3") (pinfunction "DOUT_3") (pintype "output"))
      (node (ref "IC153") (pin "1") (pinfunction "DIN_1") (pintype "input"))
    )
    (net (code "206") (name "Net-(IC153-DOUT)") (class "Default")
      (node (ref "IC153") (pin "3") (pinfunction "DOUT_3") (pintype "output"))
      (node (ref "IC154") (pin "1") (pinfunction "DIN_1") (pintype "input"))
    )
    (net (code "207") (name "Net-(IC156-DOUT)") (class "Default")
      (node (ref "IC156") (pin "3") (pinfunction "DOUT_3") (pintype "output"))
      (node (ref "IC157") (pin "1") (pinfunction "DIN_1") (pintype "input"))
    )
    (net (code "208") (name "Net-(IC157-DOUT)") (class "Default")
      (node (ref "IC157") (pin "3") (pinfunction "DOUT_3") (pintype "output"))
      (node (ref "IC158") (pin "1") (pinfunction "DIN_1") (pintype "input"))
    )
    (net (code "209") (name "Net-(IC158-DOUT)") (class "Default")
      (node (ref "IC158") (pin "3") (pinfunction "DOUT_3") (pintype "output"))
      (node (ref "IC159") (pin "1") (pinfunction "DIN_1") (pintype "input"))
    )
    (net (code "210") (name "Net-(IC159-DOUT)") (class "Default")
      (node (ref "IC159") (pin "3") (pinfunction "DOUT_3") (pintype "output"))
      (node (ref "IC160") (pin "1") (pinfunction "DIN_1") (pintype "input"))
    )
    (net (code "211") (name "Net-(IC161-DOUT)") (class "Default")
      (node (ref "IC161") (pin "3") (pinfunction "DOUT_3") (pintype "output"))
      (node (ref "IC162") (pin "1") (pinfunction "DIN_1") (pintype "input"))
    )
    (net (code "212") (name "Net-(IC162-DOUT)") (class "Default")
      (node (ref "IC162") (pin "3") (pinfunction "DOUT_3") (pintype "output"))
      (node (ref "IC163") (pin "1") (pinfunction "DIN_1") (pintype "input"))
    )
    (net (code "213") (name "Net-(IC163-DOUT)") (class "Default")
      (node (ref "IC163") (pin "3") (pinfunction "DOUT_3") (pintype "output"))
      (node (ref "IC164") (pin "1") (pinfunction "DIN_1") (pintype "input"))
    )
    (net (code "214") (name "Net-(IC164-DOUT)") (class "Default")
      (node (ref "IC164") (pin "3") (pinfunction "DOUT_3") (pintype "output"))
      (node (ref "IC165") (pin "1") (pinfunction "DIN_1") (pintype "input"))
    )
    (net (code "215") (name "Net-(IC166-DOUT)") (class "Default")
      (node (ref "IC166") (pin "3") (pinfunction "DOUT_3") (pintype "output"))
      (node (ref "IC167") (pin "1") (pinfunction "DIN_1") (pintype "input"))
    )
    (net (code "216") (name "Net-(IC167-DOUT)") (class "Default")
      (node (ref "IC167") (pin "3") (pinfunction "DOUT_3") (pintype "output"))
      (node (ref "IC168") (pin "1") (pinfunction "DIN_1") (pintype "input"))
    )
    (net (code "217") (name "Net-(IC168-DOUT)") (class "Default")
      (node (ref "IC168") (pin "3") (pinfunction "DOUT_3") (pintype "output"))
      (node (ref "IC169") (pin "1") (pinfunction "DIN_1") (pintype "input"))
    )
    (net (code "218") (name "Net-(IC169-DOUT)") (class "Default")
      (node (ref "IC169") (pin "3") (pinfunction "DOUT_3") (pintype "output"))
      (node (ref "IC170") (pin "1") (pinfunction "DIN_1") (pintype "input"))
    )
    (net (code "219") (name "Net-(IC171-DOUT)") (class "Default")
      (node (ref "IC171") (pin "3") (pinfunction "DOUT_3") (pintype "output"))
      (node (ref "IC172") (pin "1") (pinfunction "DIN_1") (pintype "input"))
    )
    (net (code "220") (name "Net-(IC172-DOUT)") (class "Default")
      (node (ref "IC172") (pin "3") (pinfunction "DOUT_3") (pintype "output"))
      (node (ref "IC173") (pin "1") (pinfunction "DIN_1") (pintype "input"))
    )
    (net (code "221") (name "Net-(IC173-DOUT)") (class "Default")
      (node (ref "IC173") (pin "3") (pinfunction "DOUT_3") (pintype "output"))
      (node (ref "IC174") (pin "1") (pinfunction "DIN_1") (pintype "input"))
    )
    (net (code "222") (name "Net-(IC174-DOUT)") (class "Default")
      (node (ref "IC174") (pin "3") (pinfunction "DOUT_3") (pintype "output"))
      (node (ref "IC175") (pin "1") (pinfunction "DIN_1") (pintype "input"))
    )
    (net (code "223") (name "Net-(IC176-DOUT)") (class "Default")
      (node (ref "IC176") (pin "3") (pinfunction "DOUT_3") (pintype "output"))
      (node (ref "IC177") (pin "1") (pinfunction "DIN_1") (pintype "input"))
    )
    (net (code "224") (name "Net-(IC177-DOUT)") (class "Default")
      (node (ref "IC177") (pin "3") (pinfunction "DOUT_3") (pintype "output"))
      (node (ref "IC178") (pin "1") (pinfunction "DIN_1") (pintype "input"))
    )
    (net (code "225") (name "Net-(IC178-DOUT)") (class "Default")
      (node (ref "IC178") (pin "3") (pinfunction "DOUT_3") (pintype "output"))
      (node (ref "IC179") (pin "1") (pinfunction "DIN_1") (pintype "input"))
    )
    (net (code "226") (name "Net-(IC179-DOUT)") (class "Default")
      (node (ref "IC179") (pin "3") (pinfunction "DOUT_3") (pintype "output"))
      (node (ref "IC180") (pin "1") (pinfunction "DIN_1") (pintype "input"))
    )
    (net (code "227") (name "Net-(IC181-DOUT)") (class "Default")
      (node (ref "IC181") (pin "3") (pinfunction "DOUT_3") (pintype "output"))
      (node (ref "IC182") (pin "1") (pinfunction "DIN_1") (pintype "input"))
    )
    (net (code "228") (name "Net-(IC182-DOUT)") (class "Default")
      (node (ref "IC182") (pin "3") (pinfunction "DOUT_3") (pintype "output"))
      (node (ref "IC183") (pin "1") (pinfunction "DIN_1") (pintype "input"))
    )
    (net (code "229") (name "Net-(IC183-DOUT)") (class "Default")
      (node (ref "IC183") (pin "3") (pinfunction "DOUT_3") (pintype "output"))
      (node (ref "IC184") (pin "1") (pinfunction "DIN_1") (pintype "input"))
    )
    (net (code "230") (name "Net-(IC184-DOUT)") (class "Default")
      (node (ref "IC184") (pin "3") (pinfunction "DOUT_3") (pintype "output"))
      (node (ref "IC185") (pin "1") (pinfunction "DIN_1") (pintype "input"))
    )
    (net (code "231") (name "Net-(IC186-DOUT)") (class "Default")
      (node (ref "IC186") (pin "3") (pinfunction "DOUT_3") (pintype "output"))
      (node (ref "IC187") (pin "1") (pinfunction "DIN_1") (pintype "input"))
    )
    (net (code "232") (name "Net-(IC187-DOUT)") (class "Default")
      (node (ref "IC187") (pin "3") (pinfunction "DOUT_3") (pintype "output"))
      (node (ref "IC188") (pin "1") (pinfunction "DIN_1") (pintype "input"))
    )
    (net (code "233") (name "Net-(IC188-DOUT)") (class "Default")
      (node (ref "IC188") (pin "3") (pinfunction "DOUT_3") (pintype "output"))
      (node (ref "IC189") (pin "1") (pinfunction "DIN_1") (pintype "input"))
    )
    (net (code "234") (name "Net-(IC189-DOUT)") (class "Default")
      (node (ref "IC189") (pin "3") (pinfunction "DOUT_3") (pintype "output"))
      (node (ref "IC190") (pin "1") (pinfunction "DIN_1") (pintype "input"))
    )
    (net (code "235") (name "Net-(IC191-DOUT)") (class "Default")
      (node (ref "IC191") (pin "3") (pinfunction "DOUT_3") (pintype "output"))
      (node (ref "IC192") (pin "1") (pinfunction "DIN_1") (pintype "input"))
    )
    (net (code "236") (name "Net-(IC192-DOUT)") (class "Default")
      (node (ref "IC192") (pin "3") (pinfunction "DOUT_3") (pintype "output"))
      (node (ref "IC193") (pin "1") (pinfunction "DIN_1") (pintype "input"))
    )
    (net (code "237") (name "Net-(IC193-DOUT)") (class "Default")
      (node (ref "IC193") (pin "3") (pinfunction "DOUT_3") (pintype "output"))
      (node (ref "IC194") (pin "1") (pinfunction "DIN_1") (pintype "input"))
    )
    (net (code "238") (name "Net-(IC194-DOUT)") (class "Default")
      (node (ref "IC194") (pin "3") (pinfunction "DOUT_3") (pintype "output"))
      (node (ref "IC195") (pin "1") (pinfunction "DIN_1") (pintype "input"))
    )
    (net (code "239") (name "Net-(IC196-DOUT)") (class "Default")
      (node (ref "IC196") (pin "3") (pinfunction "DOUT_3") (pintype "output"))
      (node (ref "IC197") (pin "1") (pinfunction "DIN_1") (pintype "input"))
    )
    (net (code "240") (name "Net-(IC197-DOUT)") (class "Default")
      (node (ref "IC197") (pin "3") (pinfunction "DOUT_3") (pintype "output"))
      (node (ref "IC198") (pin "1") (pinfunction "DIN_1") (pintype "input"))
    )
    (net (code "241") (name "Net-(IC198-DOUT)") (class "Default")
      (node (ref "IC198") (pin "3") (pinfunction "DOUT_3") (pintype "output"))
      (node (ref "IC199") (pin "1") (pinfunction "DIN_1") (pintype "input"))
    )
    (net (code "242") (name "Net-(IC199-DOUT)") (class "Default")
      (node (ref "IC199") (pin "3") (pinfunction "DOUT_3") (pintype "output"))
      (node (ref "IC200") (pin "1") (pinfunction "DIN_1") (pintype "input"))
    )
    (net (code "243") (name "Net-(IC201-DOUT)") (class "Default")
      (node (ref "IC201") (pin "3") (pinfunction "DOUT_3") (pintype "output"))
      (node (ref "IC202") (pin "1") (pinfunction "DIN_1") (pintype "input"))
    )
    (net (code "244") (name "Net-(IC202-DOUT)") (class "Default")
      (node (ref "IC202") (pin "3") (pinfunction "DOUT_3") (pintype "output"))
      (node (ref "IC203") (pin "1") (pinfunction "DIN_1") (pintype "input"))
    )
    (net (code "245") (name "Net-(IC203-DOUT)") (class "Default")
      (node (ref "IC203") (pin "3") (pinfunction "DOUT_3") (pintype "output"))
      (node (ref "IC204") (pin "1") (pinfunction "DIN_1") (pintype "input"))
    )
    (net (code "246") (name "Net-(IC204-DOUT)") (class "Default")
      (node (ref "IC204") (pin "3") (pinfunction "DOUT_3") (pintype "output"))
      (node (ref "IC205") (pin "1") (pinfunction "DIN_1") (pintype "input"))
    )
    (net (code "247") (name "Net-(IC206-DOUT)") (class "Default")
      (node (ref "IC206") (pin "3") (pinfunction "DOUT_3") (pintype "output"))
      (node (ref "IC207") (pin "1") (pinfunction "DIN_1") (pintype "input"))
    )
    (net (code "248") (name "Net-(IC207-DOUT)") (class "Default")
      (node (ref "IC207") (pin "3") (pinfunction "DOUT_3") (pintype "output"))
      (node (ref "IC208") (pin "1") (pinfunction "DIN_1") (pintype "input"))
    )
    (net (code "249") (name "Net-(IC208-DOUT)") (class "Default")
      (node (ref "IC208") (pin "3") (pinfunction "DOUT_3") (pintype "output"))
      (node (ref "IC209") (pin "1") (pinfunction "DIN_1") (pintype "input"))
    )
    (net (code "250") (name "Net-(IC209-DOUT)") (class "Default")
      (node (ref "IC209") (pin "3") (pinfunction "DOUT_3") (pintype "output"))
      (node (ref "IC210") (pin "1") (pinfunction "DIN_1") (pintype "input"))
    )
    (net (code "251") (name "Net-(IC212-DOUT)") (class "Default")
      (node (ref "IC212") (pin "3") (pinfunction "DOUT_3") (pintype "output"))
      (node (ref "IC213") (pin "1") (pinfunction "DIN_1") (pintype "input"))
    )
    (net (code "252") (name "Net-(IC213-DOUT)") (class "Default")
      (node (ref "IC213") (pin "3") (pinfunction "DOUT_3") (pintype "output"))
      (node (ref "IC214") (pin "1") (pinfunction "DIN_1") (pintype "input"))
    )
    (net (code "253") (name "Net-(IC214-DOUT)") (class "Default")
      (node (ref "IC214") (pin "3") (pinfunction "DOUT_3") (pintype "output"))
      (node (ref "IC215") (pin "1") (pinfunction "DIN_1") (pintype "input"))
    )
    (net (code "254") (name "Net-(IC215-DOUT)") (class "Default")
      (node (ref "IC215") (pin "3") (pinfunction "DOUT_3") (pintype "output"))
      (node (ref "IC216") (pin "1") (pinfunction "DIN_1") (pintype "input"))
    )
    (net (code "255") (name "Net-(IC217-DOUT)") (class "Default")
      (node (ref "IC217") (pin "3") (pinfunction "DOUT_3") (pintype "output"))
      (node (ref "IC218") (pin "1") (pinfunction "DIN_1") (pintype "input"))
    )
    (net (code "256") (name "Net-(IC218-DOUT)") (class "Default")
      (node (ref "IC218") (pin "3") (pinfunction "DOUT_3") (pintype "output"))
      (node (ref "IC219") (pin "1") (pinfunction "DIN_1") (pintype "input"))
    )
    (net (code "257") (name "Net-(IC219-DOUT)") (class "Default")
      (node (ref "IC219") (pin "3") (pinfunction "DOUT_3") (pintype "output"))
      (node (ref "IC220") (pin "1") (pinfunction "DIN_1") (pintype "input"))
    )
    (net (code "258") (name "Net-(IC220-DOUT)") (class "Default")
      (node (ref "IC220") (pin "3") (pinfunction "DOUT_3") (pintype "output"))
      (node (ref "IC221") (pin "1") (pinfunction "DIN_1") (pintype "input"))
    )
    (net (code "259") (name "Net-(IC222-DOUT)") (class "Default")
      (node (ref "IC222") (pin "3") (pinfunction "DOUT_3") (pintype "output"))
      (node (ref "IC223") (pin "1") (pinfunction "DIN_1") (pintype "input"))
    )
    (net (code "260") (name "Net-(IC223-DOUT)") (class "Default")
      (node (ref "IC223") (pin "3") (pinfunction "DOUT_3") (pintype "output"))
      (node (ref "IC224") (pin "1") (pinfunction "DIN_1") (pintype "input"))
    )
    (net (code "261") (name "Net-(IC224-DOUT)") (class "Default")
      (node (ref "IC224") (pin "3") (pinfunction "DOUT_3") (pintype "output"))
      (node (ref "IC225") (pin "1") (pinfunction "DIN_1") (pintype "input"))
    )
    (net (code "262") (name "Net-(IC225-DOUT)") (class "Default")
      (node (ref "IC225") (pin "3") (pinfunction "DOUT_3") (pintype "output"))
      (node (ref "IC226") (pin "1") (pinfunction "DIN_1") (pintype "input"))
    )
    (net (code "263") (name "Net-(IC227-DOUT)") (class "Default")
      (node (ref "IC227") (pin "3") (pinfunction "DOUT_3") (pintype "output"))
      (node (ref "IC228") (pin "1") (pinfunction "DIN_1") (pintype "input"))
    )
    (net (code "264") (name "Net-(IC228-DOUT)") (class "Default")
      (node (ref "IC228") (pin "3") (pinfunction "DOUT_3") (pintype "output"))
      (node (ref "IC229") (pin "1") (pinfunction "DIN_1") (pintype "input"))
    )
    (net (code "265") (name "Net-(IC229-DOUT)") (class "Default")
      (node (ref "IC229") (pin "3") (pinfunction "DOUT_3") (pintype "output"))
      (node (ref "IC230") (pin "1") (pinfunction "DIN_1") (pintype "input"))
    )
    (net (code "266") (name "Net-(IC230-DOUT)") (class "Default")
      (node (ref "IC230") (pin "3") (pinfunction "DOUT_3") (pintype "output"))
      (node (ref "IC231") (pin "1") (pinfunction "DIN_1") (pintype "input"))
    )
    (net (code "267") (name "Net-(IC232-DOUT)") (class "Default")
      (node (ref "IC232") (pin "3") (pinfunction "DOUT_3") (pintype "output"))
      (node (ref "IC233") (pin "1") (pinfunction "DIN_1") (pintype "input"))
    )
    (net (code "268") (name "Net-(IC233-DOUT)") (class "Default")
      (node (ref "IC233") (pin "3") (pinfunction "DOUT_3") (pintype "output"))
      (node (ref "IC234") (pin "1") (pinfunction "DIN_1") (pintype "input"))
    )
    (net (code "269") (name "Net-(IC234-DOUT)") (class "Default")
      (node (ref "IC234") (pin "3") (pinfunction "DOUT_3") (pintype "output"))
      (node (ref "IC235") (pin "1") (pinfunction "DIN_1") (pintype "input"))
    )
    (net (code "270") (name "Net-(IC235-DOUT)") (class "Default")
      (node (ref "IC235") (pin "3") (pinfunction "DOUT_3") (pintype "output"))
      (node (ref "IC236") (pin "1") (pinfunction "DIN_1") (pintype "input"))
    )
    (net (code "271") (name "Net-(IC237-DOUT)") (class "Default")
      (node (ref "IC237") (pin "3") (pinfunction "DOUT_3") (pintype "output"))
      (node (ref "IC238") (pin "1") (pinfunction "DIN_1") (pintype "input"))
    )
    (net (code "272") (name "Net-(IC238-DOUT)") (class "Default")
      (node (ref "IC238") (pin "3") (pinfunction "DOUT_3") (pintype "output"))
      (node (ref "IC239") (pin "1") (pinfunction "DIN_1") (pintype "input"))
    )
    (net (code "273") (name "Net-(IC239-DOUT)") (class "Default")
      (node (ref "IC239") (pin "3") (pinfunction "DOUT_3") (pintype "output"))
      (node (ref "IC240") (pin "1") (pinfunction "DIN_1") (pintype "input"))
    )
    (net (code "274") (name "Net-(IC240-DOUT)") (class "Default")
      (node (ref "IC240") (pin "3") (pinfunction "DOUT_3") (pintype "output"))
      (node (ref "IC241") (pin "1") (pinfunction "DIN_1") (pintype "input"))
    )
    (net (code "275") (name "Net-(IC242-DOUT)") (class "Default")
      (node (ref "IC242") (pin "3") (pinfunction "DOUT_3") (pintype "output"))
      (node (ref "IC243") (pin "1") (pinfunction "DIN_1") (pintype "input"))
    )
    (net (code "276") (name "Net-(IC243-DOUT)") (class "Default")
      (node (ref "IC243") (pin "3") (pinfunction "DOUT_3") (pintype "output"))
      (node (ref "IC244") (pin "1") (pinfunction "DIN_1") (pintype "input"))
    )
    (net (code "277") (name "Net-(IC244-DOUT)") (class "Default")
      (node (ref "IC244") (pin "3") (pinfunction "DOUT_3") (pintype "output"))
      (node (ref "IC245") (pin "1") (pinfunction "DIN_1") (pintype "input"))
    )
    (net (code "278") (name "Net-(IC245-DOUT)") (class "Default")
      (node (ref "IC245") (pin "3") (pinfunction "DOUT_3") (pintype "output"))
      (node (ref "IC246") (pin "1") (pinfunction "DIN_1") (pintype "input"))
    )
    (net (code "279") (name "Net-(IC247-DOUT)") (class "Default")
      (node (ref "IC247") (pin "3") (pinfunction "DOUT_3") (pintype "output"))
      (node (ref "IC248") (pin "1") (pinfunction "DIN_1") (pintype "input"))
    )
    (net (code "280") (name "Net-(IC248-DOUT)") (class "Default")
      (node (ref "IC248") (pin "3") (pinfunction "DOUT_3") (pintype "output"))
      (node (ref "IC249") (pin "1") (pinfunction "DIN_1") (pintype "input"))
    )
    (net (code "281") (name "Net-(IC249-DOUT)") (class "Default")
      (node (ref "IC249") (pin "3") (pinfunction "DOUT_3") (pintype "output"))
      (node (ref "IC250") (pin "1") (pinfunction "DIN_1") (pintype "input"))
    )
    (net (code "282") (name "Net-(IC250-DOUT)") (class "Default")
      (node (ref "IC250") (pin "3") (pinfunction "DOUT_3") (pintype "output"))
      (node (ref "IC251") (pin "1") (pinfunction "DIN_1") (pintype "input"))
    )
    (net (code "283") (name "Net-(IC252-DOUT)") (class "Default")
      (node (ref "IC252") (pin "3") (pinfunction "DOUT_3") (pintype "output"))
      (node (ref "IC253") (pin "1") (pinfunction "DIN_1") (pintype "input"))
    )
    (net (code "284") (name "Net-(IC253-DOUT)") (class "Default")
      (node (ref "IC253") (pin "3") (pinfunction "DOUT_3") (pintype "output"))
      (node (ref "IC254") (pin "1") (pinfunction "DIN_1") (pintype "input"))
    )
    (net (code "285") (name "Net-(IC254-DOUT)") (class "Default")
      (node (ref "IC254") (pin "3") (pinfunction "DOUT_3") (pintype "output"))
      (node (ref "IC255") (pin "1") (pinfunction "DIN_1") (pintype "input"))
    )
    (net (code "286") (name "Net-(IC255-DOUT)") (class "Default")
      (node (ref "IC255") (pin "3") (pinfunction "DOUT_3") (pintype "output"))
      (node (ref "IC256") (pin "1") (pinfunction "DIN_1") (pintype "input"))
    )
    (net (code "287") (name "Net-(IC257-DOUT)") (class "Default")
      (node (ref "IC257") (pin "3") (pinfunction "DOUT_3") (pintype "output"))
      (node (ref "IC258") (pin "1") (pinfunction "DIN_1") (pintype "input"))
    )
    (net (code "288") (name "Net-(IC258-DOUT)") (class "Default")
      (node (ref "IC258") (pin "3") (pinfunction "DOUT_3") (pintype "output"))
      (node (ref "IC259") (pin "1") (pinfunction "DIN_1") (pintype "input"))
    )
    (net (code "289") (name "Net-(IC259-DOUT)") (class "Default")
      (node (ref "IC259") (pin "3") (pinfunction "DOUT_3") (pintype "output"))
      (node (ref "IC260") (pin "1") (pinfunction "DIN_1") (pintype "input"))
    )
    (net (code "290") (name "Net-(IC260-DOUT)") (class "Default")
      (node (ref "IC260") (pin "3") (pinfunction "DOUT_3") (pintype "output"))
      (node (ref "IC261") (pin "1") (pinfunction "DIN_1") (pintype "input"))
    )
    (net (code "291") (name "Net-(IC262-DOUT)") (class "Default")
      (node (ref "IC262") (pin "3") (pinfunction "DOUT_3") (pintype "output"))
      (node (ref "IC263") (pin "1") (pinfunction "DIN_1") (pintype "input"))
    )
    (net (code "292") (name "Net-(IC263-DOUT)") (class "Default")
      (node (ref "IC263") (pin "3") (pinfunction "DOUT_3") (pintype "output"))
      (node (ref "IC264") (pin "1") (pinfunction "DIN_1") (pintype "input"))
    )
    (net (code "293") (name "Net-(IC264-DOUT)") (class "Default")
      (node (ref "IC264") (pin "3") (pinfunction "DOUT_3") (pintype "output"))
      (node (ref "IC265") (pin "1") (pinfunction "DIN_1") (pintype "input"))
    )
    (net (code "294") (name "Net-(IC265-DOUT)") (class "Default")
      (node (ref "IC265") (pin "3") (pinfunction "DOUT_3") (pintype "output"))
      (node (ref "IC266") (pin "1") (pinfunction "DIN_1") (pintype "input"))
    )
    (net (code "295") (name "Net-(IC268-DOUT)") (class "Default")
      (node (ref "IC268") (pin "3") (pinfunction "DOUT_3") (pintype "output"))
      (node (ref "IC269") (pin "1") (pinfunction "DIN_1") (pintype "input"))
    )
    (net (code "296") (name "Net-(IC269-DOUT)") (class "Default")
      (node (ref "IC269") (pin "3") (pinfunction "DOUT_3") (pintype "output"))
      (node (ref "IC270") (pin "1") (pinfunction "DIN_1") (pintype "input"))
    )
    (net (code "297") (name "Net-(IC270-DOUT)") (class "Default")
      (node (ref "IC270") (pin "3") (pinfunction "DOUT_3") (pintype "output"))
      (node (ref "IC271") (pin "1") (pinfunction "DIN_1") (pintype "input"))
    )
    (net (code "298") (name "Net-(IC271-DOUT)") (class "Default")
      (node (ref "IC271") (pin "3") (pinfunction "DOUT_3") (pintype "output"))
      (node (ref "IC272") (pin "1") (pinfunction "DIN_1") (pintype "input"))
    )
    (net (code "299") (name "Net-(IC273-DOUT)") (class "Default")
      (node (ref "IC273") (pin "3") (pinfunction "DOUT_3") (pintype "output"))
      (node (ref "IC274") (pin "1") (pinfunction "DIN_1") (pintype "input"))
    )
    (net (code "300") (name "Net-(IC274-DOUT)") (class "Default")
      (node (ref "IC274") (pin "3") (pinfunction "DOUT_3") (pintype "output"))
      (node (ref "IC275") (pin "1") (pinfunction "DIN_1") (pintype "input"))
    )
    (net (code "301") (name "Net-(IC275-DOUT)") (class "Default")
      (node (ref "IC275") (pin "3") (pinfunction "DOUT_3") (pintype "output"))
      (node (ref "IC276") (pin "1") (pinfunction "DIN_1") (pintype "input"))
    )
    (net (code "302") (name "Net-(IC276-DOUT)") (class "Default")
      (node (ref "IC276") (pin "3") (pinfunction "DOUT_3") (pintype "output"))
      (node (ref "IC277") (pin "1") (pinfunction "DIN_1") (pintype "input"))
    )
    (net (code "303") (name "Net-(IC278-DOUT)") (class "Default")
      (node (ref "IC278") (pin "3") (pinfunction "DOUT_3") (pintype "output"))
      (node (ref "IC279") (pin "1") (pinfunction "DIN_1") (pintype "input"))
    )
    (net (code "304") (name "Net-(IC279-DOUT)") (class "Default")
      (node (ref "IC279") (pin "3") (pinfunction "DOUT_3") (pintype "output"))
      (node (ref "IC280") (pin "1") (pinfunction "DIN_1") (pintype "input"))
    )
    (net (code "305") (name "Net-(IC280-DOUT)") (class "Default")
      (node (ref "IC280") (pin "3") (pinfunction "DOUT_3") (pintype "output"))
      (node (ref "IC281") (pin "1") (pinfunction "DIN_1") (pintype "input"))
    )
    (net (code "306") (name "Net-(IC281-DOUT)") (class "Default")
      (node (ref "IC281") (pin "3") (pinfunction "DOUT_3") (pintype "output"))
      (node (ref "IC282") (pin "1") (pinfunction "DIN_1") (pintype "input"))
    )
    (net (code "307") (name "Net-(IC283-DOUT)") (class "Default")
      (node (ref "IC283") (pin "3") (pinfunction "DOUT_3") (pintype "output"))
      (node (ref "IC284") (pin "1") (pinfunction "DIN_1") (pintype "input"))
    )
    (net (code "308") (name "Net-(IC284-DOUT)") (class "Default")
      (node (ref "IC284") (pin "3") (pinfunction "DOUT_3") (pintype "output"))
      (node (ref "IC285") (pin "1") (pinfunction "DIN_1") (pintype "input"))
    )
    (net (code "309") (name "Net-(IC285-DOUT)") (class "Default")
      (node (ref "IC285") (pin "3") (pinfunction "DOUT_3") (pintype "output"))
      (node (ref "IC286") (pin "1") (pinfunction "DIN_1") (pintype "input"))
    )
    (net (code "310") (name "Net-(IC286-DOUT)") (class "Default")
      (node (ref "IC286") (pin "3") (pinfunction "DOUT_3") (pintype "output"))
      (node (ref "IC287") (pin "1") (pinfunction "DIN_1") (pintype "input"))
    )
    (net (code "311") (name "Net-(IC288-DOUT)") (class "Default")
      (node (ref "IC288") (pin "3") (pinfunction "DOUT_3") (pintype "output"))
      (node (ref "IC289") (pin "1") (pinfunction "DIN_1") (pintype "input"))
    )
    (net (code "312") (name "Net-(IC289-DOUT)") (class "Default")
      (node (ref "IC289") (pin "3") (pinfunction "DOUT_3") (pintype "output"))
      (node (ref "IC290") (pin "1") (pinfunction "DIN_1") (pintype "input"))
    )
    (net (code "313") (name "Net-(IC290-DOUT)") (class "Default")
      (node (ref "IC290") (pin "3") (pinfunction "DOUT_3") (pintype "output"))
      (node (ref "IC291") (pin "1") (pinfunction "DIN_1") (pintype "input"))
    )
    (net (code "314") (name "Net-(IC291-DOUT)") (class "Default")
      (node (ref "IC291") (pin "3") (pinfunction "DOUT_3") (pintype "output"))
      (node (ref "IC292") (pin "1") (pinfunction "DIN_1") (pintype "input"))
    )
    (net (code "315") (name "Net-(IC293-DOUT)") (class "Default")
      (node (ref "IC293") (pin "3") (pinfunction "DOUT_3") (pintype "output"))
      (node (ref "IC294") (pin "1") (pinfunction "DIN_1") (pintype "input"))
    )
    (net (code "316") (name "Net-(IC294-DOUT)") (class "Default")
      (node (ref "IC294") (pin "3") (pinfunction "DOUT_3") (pintype "output"))
      (node (ref "IC295") (pin "1") (pinfunction "DIN_1") (pintype "input"))
    )
    (net (code "317") (name "Net-(IC295-DOUT)") (class "Default")
      (node (ref "IC295") (pin "3") (pinfunction "DOUT_3") (pintype "output"))
      (node (ref "IC296") (pin "1") (pinfunction "DIN_1") (pintype "input"))
    )
    (net (code "318") (name "Net-(IC296-DOUT)") (class "Default")
      (node (ref "IC296") (pin "3") (pinfunction "DOUT_3") (pintype "output"))
      (node (ref "IC297") (pin "1") (pinfunction "DIN_1") (pintype "input"))
    )
    (net (code "319") (name "Net-(IC298-DOUT)") (class "Default")
      (node (ref "IC298") (pin "3") (pinfunction "DOUT_3") (pintype "output"))
      (node (ref "IC299") (pin "1") (pinfunction "DIN_1") (pintype "input"))
    )
    (net (code "320") (name "Net-(IC299-DOUT)") (class "Default")
      (node (ref "IC299") (pin "3") (pinfunction "DOUT_3") (pintype "output"))
      (node (ref "IC300") (pin "1") (pinfunction "DIN_1") (pintype "input"))
    )
    (net (code "321") (name "Net-(IC300-DOUT)") (class "Default")
      (node (ref "IC300") (pin "3") (pinfunction "DOUT_3") (pintype "output"))
      (node (ref "IC301") (pin "1") (pinfunction "DIN_1") (pintype "input"))
    )
    (net (code "322") (name "Net-(IC301-DOUT)") (class "Default")
      (node (ref "IC301") (pin "3") (pinfunction "DOUT_3") (pintype "output"))
      (node (ref "IC302") (pin "1") (pinfunction "DIN_1") (pintype "input"))
    )
    (net (code "323") (name "Net-(IC303-DOUT)") (class "Default")
      (node (ref "IC303") (pin "3") (pinfunction "DOUT_3") (pintype "output"))
      (node (ref "IC304") (pin "1") (pinfunction "DIN_1") (pintype "input"))
    )
    (net (code "324") (name "Net-(IC304-DOUT)") (class "Default")
      (node (ref "IC304") (pin "3") (pinfunction "DOUT_3") (pintype "output"))
      (node (ref "IC305") (pin "1") (pinfunction "DIN_1") (pintype "input"))
    )
    (net (code "325") (name "Net-(IC305-DOUT)") (class "Default")
      (node (ref "IC305") (pin "3") (pinfunction "DOUT_3") (pintype "output"))
      (node (ref "IC306") (pin "1") (pinfunction "DIN_1") (pintype "input"))
    )
    (net (code "326") (name "Net-(IC306-DOUT)") (class "Default")
      (node (ref "IC306") (pin "3") (pinfunction "DOUT_3") (pintype "output"))
      (node (ref "IC307") (pin "1") (pinfunction "DIN_1") (pintype "input"))
    )
    (net (code "327") (name "Net-(IC308-DOUT)") (class "Default")
      (node (ref "IC308") (pin "3") (pinfunction "DOUT_3") (pintype "output"))
      (node (ref "IC309") (pin "1") (pinfunction "DIN_1") (pintype "input"))
    )
    (net (code "328") (name "Net-(IC309-DOUT)") (class "Default")
      (node (ref "IC309") (pin "3") (pinfunction "DOUT_3") (pintype "output"))
      (node (ref "IC310") (pin "1") (pinfunction "DIN_1") (pintype "input"))
    )
    (net (code "329") (name "Net-(IC310-DOUT)") (class "Default")
      (node (ref "IC310") (pin "3") (pinfunction "DOUT_3") (pintype "output"))
      (node (ref "IC311") (pin "1") (pinfunction "DIN_1") (pintype "input"))
    )
    (net (code "330") (name "Net-(IC311-DOUT)") (class "Default")
      (node (ref "IC311") (pin "3") (pinfunction "DOUT_3") (pintype "output"))
      (node (ref "IC312") (pin "1") (pinfunction "DIN_1") (pintype "input"))
    )
    (net (code "331") (name "Net-(IC313-DOUT)") (class "Default")
      (node (ref "IC313") (pin "3") (pinfunction "DOUT_3") (pintype "output"))
      (node (ref "IC314") (pin "1") (pinfunction "DIN_1") (pintype "input"))
    )
    (net (code "332") (name "Net-(IC314-DOUT)") (class "Default")
      (node (ref "IC314") (pin "3") (pinfunction "DOUT_3") (pintype "output"))
      (node (ref "IC315") (pin "1") (pinfunction "DIN_1") (pintype "input"))
    )
    (net (code "333") (name "Net-(IC315-DOUT)") (class "Default")
      (node (ref "IC315") (pin "3") (pinfunction "DOUT_3") (pintype "output"))
      (node (ref "IC316") (pin "1") (pinfunction "DIN_1") (pintype "input"))
    )
    (net (code "334") (name "Net-(IC316-DOUT)") (class "Default")
      (node (ref "IC316") (pin "3") (pinfunction "DOUT_3") (pintype "output"))
      (node (ref "IC317") (pin "1") (pinfunction "DIN_1") (pintype "input"))
    )
    (net (code "335") (name "Net-(IC318-DOUT)") (class "Default")
      (node (ref "IC318") (pin "3") (pinfunction "DOUT_3") (pintype "output"))
      (node (ref "IC319") (pin "1") (pinfunction "DIN_1") (pintype "input"))
    )
    (net (code "336") (name "Net-(IC319-DOUT)") (class "Default")
      (node (ref "IC319") (pin "3") (pinfunction "DOUT_3") (pintype "output"))
      (node (ref "IC320") (pin "1") (pinfunction "DIN_1") (pintype "input"))
    )
    (net (code "337") (name "Net-(IC320-DOUT)") (class "Default")
      (node (ref "IC320") (pin "3") (pinfunction "DOUT_3") (pintype "output"))
      (node (ref "IC321") (pin "1") (pinfunction "DIN_1") (pintype "input"))
    )
    (net (code "338") (name "Net-(IC321-DOUT)") (class "Default")
      (node (ref "IC321") (pin "3") (pinfunction "DOUT_3") (pintype "output"))
      (node (ref "IC322") (pin "1") (pinfunction "DIN_1") (pintype "input"))
    )
    (net (code "339") (name "Net-(IC324-DOUT)") (class "Default")
      (node (ref "IC324") (pin "3") (pinfunction "DOUT_3") (pintype "output"))
      (node (ref "IC325") (pin "1") (pinfunction "DIN_1") (pintype "input"))
    )
    (net (code "340") (name "Net-(IC325-DOUT)") (class "Default")
      (node (ref "IC325") (pin "3") (pinfunction "DOUT_3") (pintype "output"))
      (node (ref "IC326") (pin "1") (pinfunction "DIN_1") (pintype "input"))
    )
    (net (code "341") (name "Net-(IC326-DOUT)") (class "Default")
      (node (ref "IC326") (pin "3") (pinfunction "DOUT_3") (pintype "output"))
      (node (ref "IC327") (pin "1") (pinfunction "DIN_1") (pintype "input"))
    )
    (net (code "342") (name "Net-(IC327-DOUT)") (class "Default")
      (node (ref "IC327") (pin "3") (pinfunction "DOUT_3") (pintype "output"))
      (node (ref "IC328") (pin "1") (pinfunction "DIN_1") (pintype "input"))
    )
    (net (code "343") (name "Net-(IC329-DOUT)") (class "Default")
      (node (ref "IC329") (pin "3") (pinfunction "DOUT_3") (pintype "output"))
      (node (ref "IC330") (pin "1") (pinfunction "DIN_1") (pintype "input"))
    )
    (net (code "344") (name "Net-(IC330-DOUT)") (class "Default")
      (node (ref "IC330") (pin "3") (pinfunction "DOUT_3") (pintype "output"))
      (node (ref "IC331") (pin "1") (pinfunction "DIN_1") (pintype "input"))
    )
    (net (code "345") (name "Net-(IC331-DOUT)") (class "Default")
      (node (ref "IC331") (pin "3") (pinfunction "DOUT_3") (pintype "output"))
      (node (ref "IC332") (pin "1") (pinfunction "DIN_1") (pintype "input"))
    )
    (net (code "346") (name "Net-(R47-Pad2)") (class "Default")
      (node (ref "R47") (pin "2") (pinfunction "2_2") (pintype "passive"))
      (node (ref "X5") (pin "11") (pinfunction "11_11") (pintype "passive"))
    )
    (net (code "347") (name "Net-(R87-Pad1)") (class "Default")
      (node (ref "R87") (pin "1") (pinfunction "1_1") (pintype "passive"))
      (node (ref "X4") (pin "7") (pinfunction "7_7") (pintype "passive"))
    )
    (net (code "348") (name "Net-(T2-D)") (class "Default")
      (node (ref "D306") (pin "C") (pinfunction "C_C") (pintype "passive"))
      (node (ref "D308") (pin "C") (pinfunction "C_C") (pintype "passive"))
      (node (ref "T2") (pin "3") (pinfunction "D_3") (pintype "passive"))
    )
    (net (code "349") (name "Net-(T2-G)") (class "Default")
      (node (ref "R21") (pin "2") (pinfunction "2_2") (pintype "passive"))
      (node (ref "T2") (pin "1") (pinfunction "G_1") (pintype "passive"))
      (node (ref "TP15") (pin "TP") (pinfunction "TP_TP") (pintype "input"))
    )
    (net (code "350") (name "Net-(T3-D)") (class "Default")
      (node (ref "D200") (pin "C") (pinfunction "C_C") (pintype "passive"))
      (node (ref "D207") (pin "C") (pinfunction "C_C") (pintype "passive"))
      (node (ref "T3") (pin "3") (pinfunction "D_3") (pintype "passive"))
    )
    (net (code "351") (name "Net-(T3-G)") (class "Default")
      (node (ref "R23") (pin "2") (pinfunction "2_2") (pintype "passive"))
      (node (ref "T3") (pin "1") (pinfunction "G_1") (pintype "passive"))
      (node (ref "TP6") (pin "TP") (pinfunction "TP_TP") (pintype "input"))
    )
    (net (code "352") (name "Net-(T6-D)") (class "Default")
      (node (ref "D356") (pin "C") (pinfunction "C_C") (pintype "passive"))
      (node (ref "D358") (pin "C") (pinfunction "C_C") (pintype "passive"))
      (node (ref "T6") (pin "3") (pinfunction "D_3") (pintype "passive"))
    )
    (net (code "353") (name "Net-(T6-G)") (class "Default")
      (node (ref "R54") (pin "2") (pinfunction "2_2") (pintype "passive"))
      (node (ref "T6") (pin "1") (pinfunction "G_1") (pintype "passive"))
    )
    (net (code "354") (name "Net-(T7-D)") (class "Default")
      (node (ref "D250") (pin "C") (pinfunction "C_C") (pintype "passive"))
      (node (ref "D257") (pin "C") (pinfunction "C_C") (pintype "passive"))
      (node (ref "T7") (pin "3") (pinfunction "D_3") (pintype "passive"))
    )
    (net (code "355") (name "Net-(T7-G)") (class "Default")
      (node (ref "R59") (pin "2") (pinfunction "2_2") (pintype "passive"))
      (node (ref "T7") (pin "1") (pinfunction "G_1") (pintype "passive"))
      (node (ref "TP16") (pin "TP") (pinfunction "TP_TP") (pintype "input"))
    )
    (net (code "356") (name "Net-(T10-D)") (class "Default")
      (node (ref "D105") (pin "1") (pinfunction "C_1") (pintype "passive"))
      (node (ref "D105") (pin "4") (pinfunction "C_4") (pintype "passive"))
      (node (ref "T10") (pin "3") (pinfunction "D_3") (pintype "passive"))
    )
    (net (code "357") (name "Net-(T10-G)") (class "Default")
      (node (ref "R80") (pin "2") (pinfunction "2_2") (pintype "passive"))
      (node (ref "T10") (pin "1") (pinfunction "G_1") (pintype "passive"))
    )
    (net (code "358") (name "PVCC_DISABLE") (class "Default")
      (node (ref "R56") (pin "2") (pinfunction "2_2") (pintype "passive"))
      (node (ref "R64") (pin "1") (pinfunction "1_1") (pintype "passive"))
      (node (ref "R67") (pin "1") (pinfunction "1_1") (pintype "passive"))
      (node (ref "TP12") (pin "TP") (pinfunction "TP_TP") (pintype "input"))
    )
    (net (code "359") (name "RBG_DOUT_END") (class "Default")
      (node (ref "IC323") (pin "3") (pinfunction "DOUT_3") (pintype "output"))
      (node (ref "TP9") (pin "TP") (pinfunction "TP_TP") (pintype "input"))
    )
    (net (code "360") (name "RGB_DOUT_4") (class "Default")
      (node (ref "IC104") (pin "3") (pinfunction "DOUT_3") (pintype "output"))
      (node (ref "IC105") (pin "1") (pinfunction "DIN_1") (pintype "input"))
    )
    (net (code "361") (name "RGB_DOUT_9") (class "Default")
      (node (ref "IC109") (pin "3") (pinfunction "DOUT_3") (pintype "output"))
      (node (ref "IC110") (pin "1") (pinfunction "DIN_1") (pintype "input"))
    )
    (net (code "362") (name "RGB_DOUT_14") (class "Default")
      (node (ref "IC114") (pin "3") (pinfunction "DOUT_3") (pintype "output"))
      (node (ref "IC115") (pin "1") (pinfunction "DIN_1") (pintype "input"))
    )
    (net (code "363") (name "RGB_DOUT_19") (class "Default")
      (node (ref "IC119") (pin "3") (pinfunction "DOUT_3") (pintype "output"))
      (node (ref "IC120") (pin "1") (pinfunction "DIN_1") (pintype "input"))
    )
    (net (code "364") (name "RGB_DOUT_24") (class "Default")
      (node (ref "IC124") (pin "3") (pinfunction "DOUT_3") (pintype "output"))
      (node (ref "IC125") (pin "1") (pinfunction "DIN_1") (pintype "input"))
    )
    (net (code "365") (name "RGB_DOUT_29") (class "Default")
      (node (ref "IC129") (pin "3") (pinfunction "DOUT_3") (pintype "output"))
      (node (ref "IC130") (pin "1") (pinfunction "DIN_1") (pintype "input"))
    )
    (net (code "366") (name "RGB_DOUT_34") (class "Default")
      (node (ref "IC134") (pin "3") (pinfunction "DOUT_3") (pintype "output"))
      (node (ref "IC135") (pin "1") (pinfunction "DIN_1") (pintype "input"))
    )
    (net (code "367") (name "RGB_DOUT_39") (class "Default")
      (node (ref "IC139") (pin "3") (pinfunction "DOUT_3") (pintype "output"))
      (node (ref "IC140") (pin "1") (pinfunction "DIN_1") (pintype "input"))
    )
    (net (code "368") (name "RGB_DOUT_44") (class "Default")
      (node (ref "IC144") (pin "3") (pinfunction "DOUT_3") (pintype "output"))
      (node (ref "IC145") (pin "1") (pinfunction "DIN_1") (pintype "input"))
    )
    (net (code "369") (name "RGB_DOUT_49") (class "Default")
      (node (ref "IC149") (pin "3") (pinfunction "DOUT_3") (pintype "output"))
      (node (ref "IC150") (pin "1") (pinfunction "DIN_1") (pintype "input"))
    )
    (net (code "370") (name "RGB_DOUT_54") (class "Default")
      (node (ref "IC154") (pin "3") (pinfunction "DOUT_3") (pintype "output"))
      (node (ref "IC155") (pin "1") (pinfunction "DIN_1") (pintype "input"))
    )
    (net (code "371") (name "RGB_DOUT_55") (class "Default")
      (node (ref "IC155") (pin "3") (pinfunction "DOUT_3") (pintype "output"))
      (node (ref "IC156") (pin "1") (pinfunction "DIN_1") (pintype "input"))
    )
    (net (code "372") (name "RGB_DOUT_60") (class "Default")
      (node (ref "IC160") (pin "3") (pinfunction "DOUT_3") (pintype "output"))
      (node (ref "IC161") (pin "1") (pinfunction "DIN_1") (pintype "input"))
    )
    (net (code "373") (name "RGB_DOUT_65") (class "Default")
      (node (ref "IC165") (pin "3") (pinfunction "DOUT_3") (pintype "output"))
      (node (ref "IC166") (pin "1") (pinfunction "DIN_1") (pintype "input"))
    )
    (net (code "374") (name "RGB_DOUT_70") (class "Default")
      (node (ref "IC170") (pin "3") (pinfunction "DOUT_3") (pintype "output"))
      (node (ref "IC171") (pin "1") (pinfunction "DIN_1") (pintype "input"))
    )
    (net (code "375") (name "RGB_DOUT_75") (class "Default")
      (node (ref "IC175") (pin "3") (pinfunction "DOUT_3") (pintype "output"))
      (node (ref "IC176") (pin "1") (pinfunction "DIN_1") (pintype "input"))
    )
    (net (code "376") (name "RGB_DOUT_80") (class "Default")
      (node (ref "IC180") (pin "3") (pinfunction "DOUT_3") (pintype "output"))
      (node (ref "IC181") (pin "1") (pinfunction "DIN_1") (pintype "input"))
    )
    (net (code "377") (name "RGB_DOUT_85") (class "Default")
      (node (ref "IC185") (pin "3") (pinfunction "DOUT_3") (pintype "output"))
      (node (ref "IC186") (pin "1") (pinfunction "DIN_1") (pintype "input"))
    )
    (net (code "378") (name "RGB_DOUT_90") (class "Default")
      (node (ref "IC190") (pin "3") (pinfunction "DOUT_3") (pintype "output"))
      (node (ref "IC191") (pin "1") (pinfunction "DIN_1") (pintype "input"))
    )
    (net (code "379") (name "RGB_DOUT_95") (class "Default")
      (node (ref "IC195") (pin "3") (pinfunction "DOUT_3") (pintype "output"))
      (node (ref "IC196") (pin "1") (pinfunction "DIN_1") (pintype "input"))
    )
    (net (code "380") (name "RGB_DOUT_100") (class "Default")
      (node (ref "IC200") (pin "3") (pinfunction "DOUT_3") (pintype "output"))
      (node (ref "IC201") (pin "1") (pinfunction "DIN_1") (pintype "input"))
    )
    (net (code "381") (name "RGB_DOUT_105") (class "Default")
      (node (ref "IC205") (pin "3") (pinfunction "DOUT_3") (pintype "output"))
      (node (ref "IC206") (pin "1") (pinfunction "DIN_1") (pintype "input"))
    )
    (net (code "382") (name "RGB_DOUT_110") (class "Default")
      (node (ref "IC210") (pin "3") (pinfunction "DOUT_3") (pintype "output"))
      (node (ref "IC211") (pin "1") (pinfunction "DIN_1") (pintype "input"))
    )
    (net (code "383") (name "RGB_DOUT_111") (class "Default")
      (node (ref "IC211") (pin "3") (pinfunction "DOUT_3") (pintype "output"))
      (node (ref "IC212") (pin "1") (pinfunction "DIN_1") (pintype "input"))
    )
    (net (code "384") (name "RGB_DOUT_116") (class "Default")
      (node (ref "IC216") (pin "3") (pinfunction "DOUT_3") (pintype "output"))
      (node (ref "IC217") (pin "1") (pinfunction "DIN_1") (pintype "input"))
    )
    (net (code "385") (name "RGB_DOUT_121") (class "Default")
      (node (ref "IC221") (pin "3") (pinfunction "DOUT_3") (pintype "output"))
      (node (ref "IC222") (pin "1") (pinfunction "DIN_1") (pintype "input"))
    )
    (net (code "386") (name "RGB_DOUT_126") (class "Default")
      (node (ref "IC226") (pin "3") (pinfunction "DOUT_3") (pintype "output"))
      (node (ref "IC227") (pin "1") (pinfunction "DIN_1") (pintype "input"))
    )
    (net (code "387") (name "RGB_DOUT_131") (class "Default")
      (node (ref "IC231") (pin "3") (pinfunction "DOUT_3") (pintype "output"))
      (node (ref "IC232") (pin "1") (pinfunction "DIN_1") (pintype "input"))
    )
    (net (code "388") (name "RGB_DOUT_136") (class "Default")
      (node (ref "IC236") (pin "3") (pinfunction "DOUT_3") (pintype "output"))
      (node (ref "IC237") (pin "1") (pinfunction "DIN_1") (pintype "input"))
    )
    (net (code "389") (name "RGB_DOUT_141") (class "Default")
      (node (ref "IC241") (pin "3") (pinfunction "DOUT_3") (pintype "output"))
      (node (ref "IC242") (pin "1") (pinfunction "DIN_1") (pintype "input"))
    )
    (net (code "390") (name "RGB_DOUT_146") (class "Default")
      (node (ref "IC246") (pin "3") (pinfunction "DOUT_3") (pintype "output"))
      (node (ref "IC247") (pin "1") (pinfunction "DIN_1") (pintype "input"))
    )
    (net (code "391") (name "RGB_DOUT_151") (class "Default")
      (node (ref "IC251") (pin "3") (pinfunction "DOUT_3") (pintype "output"))
      (node (ref "IC252") (pin "1") (pinfunction "DIN_1") (pintype "input"))
    )
    (net (code "392") (name "RGB_DOUT_156") (class "Default")
      (node (ref "IC256") (pin "3") (pinfunction "DOUT_3") (pintype "output"))
      (node (ref "IC257") (pin "1") (pinfunction "DIN_1") (pintype "input"))
    )
    (net (code "393") (name "RGB_DOUT_161") (class "Default")
      (node (ref "IC261") (pin "3") (pinfunction "DOUT_3") (pintype "output"))
      (node (ref "IC262") (pin "1") (pinfunction "DIN_1") (pintype "input"))
    )
    (net (code "394") (name "RGB_DOUT_166") (class "Default")
      (node (ref "IC266") (pin "3") (pinfunction "DOUT_3") (pintype "output"))
      (node (ref "IC267") (pin "1") (pinfunction "DIN_1") (pintype "input"))
    )
    (net (code "395") (name "RGB_DOUT_167") (class "Default")
      (node (ref "IC267") (pin "3") (pinfunction "DOUT_3") (pintype "output"))
      (node (ref "IC268") (pin "1") (pinfunction "DIN_1") (pintype "input"))
    )
    (net (code "396") (name "RGB_DOUT_172") (class "Default")
      (node (ref "IC272") (pin "3") (pinfunction "DOUT_3") (pintype "output"))
      (node (ref "IC273") (pin "1") (pinfunction "DIN_1") (pintype "input"))
    )
    (net (code "397") (name "RGB_DOUT_177") (class "Default")
      (node (ref "IC277") (pin "3") (pinfunction "DOUT_3") (pintype "output"))
      (node (ref "IC278") (pin "1") (pinfunction "DIN_1") (pintype "input"))
    )
    (net (code "398") (name "RGB_DOUT_182") (class "Default")
      (node (ref "IC282") (pin "3") (pinfunction "DOUT_3") (pintype "output"))
      (node (ref "IC283") (pin "1") (pinfunction "DIN_1") (pintype "input"))
    )
    (net (code "399") (name "RGB_DOUT_187") (class "Default")
      (node (ref "IC287") (pin "3") (pinfunction "DOUT_3") (pintype "output"))
      (node (ref "IC288") (pin "1") (pinfunction "DIN_1") (pintype "input"))
    )
    (net (code "400") (name "RGB_DOUT_192") (class "Default")
      (node (ref "IC292") (pin "3") (pinfunction "DOUT_3") (pintype "output"))
      (node (ref "IC293") (pin "1") (pinfunction "DIN_1") (pintype "input"))
    )
    (net (code "401") (name "RGB_DOUT_197") (class "Default")
      (node (ref "IC297") (pin "3") (pinfunction "DOUT_3") (pintype "output"))
      (node (ref "IC298") (pin "1") (pinfunction "DIN_1") (pintype "input"))
    )
    (net (code "402") (name "RGB_DOUT_202") (class "Default")
      (node (ref "IC302") (pin "3") (pinfunction "DOUT_3") (pintype "output"))
      (node (ref "IC303") (pin "1") (pinfunction "DIN_1") (pintype "input"))
    )
    (net (code "403") (name "RGB_DOUT_207") (class "Default")
      (node (ref "IC307") (pin "3") (pinfunction "DOUT_3") (pintype "output"))
      (node (ref "IC308") (pin "1") (pinfunction "DIN_1") (pintype "input"))
    )
    (net (code "404") (name "RGB_DOUT_212") (class "Default")
      (node (ref "IC312") (pin "3") (pinfunction "DOUT_3") (pintype "output"))
      (node (ref "IC313") (pin "1") (pinfunction "DIN_1") (pintype "input"))
    )
    (net (code "405") (name "RGB_DOUT_217") (class "Default")
      (node (ref "IC317") (pin "3") (pinfunction "DOUT_3") (pintype "output"))
      (node (ref "IC318") (pin "1") (pinfunction "DIN_1") (pintype "input"))
    )
    (net (code "406") (name "RGB_DOUT_222") (class "Default")
      (node (ref "IC322") (pin "3") (pinfunction "DOUT_3") (pintype "output"))
      (node (ref "IC323") (pin "1") (pinfunction "DIN_1") (pintype "input"))
    )
    (net (code "407") (name "RGB_DOUT_228") (class "Default")
      (node (ref "IC328") (pin "3") (pinfunction "DOUT_3") (pintype "output"))
      (node (ref "IC329") (pin "1") (pinfunction "DIN_1") (pintype "input"))
    )
    (net (code "408") (name "RGB_DOUT_232") (class "Default")
      (node (ref "IC100") (pin "1") (pinfunction "DIN_1") (pintype "input"))
      (node (ref "IC332") (pin "3") (pinfunction "DOUT_3") (pintype "output"))
    )
    (net (code "409") (name "RGB_LED_UC->FU_5V") (class "Default")
      (node (ref "C10") (pin "1") (pinfunction "1_1") (pintype "passive"))
      (node (ref "IC17") (pin "4") (pinfunction "I/O3_4") (pintype "passive"))
      (node (ref "IC324") (pin "1") (pinfunction "DIN_1") (pintype "input"))
      (node (ref "TP8") (pin "TP") (pinfunction "TP_TP") (pintype "input"))
      (node (ref "X1") (pin "24") (pinfunction "24_24") (pintype "passive"))
    )
    (net (code "410") (name "UC_CAM3_TOF_TRIGGER_TO_SENSOR_1V8") (class "Default")
      (node (ref "IC16") (pin "1") (pinfunction "I/O1_1") (pintype "passive"))
      (node (ref "X2") (pin "26") (pinfunction "26_26") (pintype "passive"))
      (node (ref "X5") (pin "18") (pinfunction "18_18") (pintype "passive"))
    )
    (net (code "411") (name "UC_FU_740NM_3V3") (class "Default")
      (node (ref "IC13") (pin "3") (pinfunction "IN+_3") (pintype "input"))
      (node (ref "IC14") (pin "1") (pinfunction "I/O1_1") (pintype "passive"))
      (node (ref "TP19") (pin "TP") (pinfunction "TP_TP") (pintype "input"))
      (node (ref "X1") (pin "35") (pinfunction "35_35") (pintype "passive"))
    )
    (net (code "412") (name "UC_FU_850NM_LEFT_3V3") (class "Default")
      (node (ref "IC17") (pin "3") (pinfunction "I/O2_3") (pintype "passive"))
      (node (ref "IC2") (pin "3") (pinfunction "IN+_3") (pintype "input"))
      (node (ref "R12") (pin "1") (pinfunction "1_1") (pintype "passive"))
      (node (ref "R5") (pin "2") (pinfunction "2_2") (pintype "passive"))
      (node (ref "TP20") (pin "TP") (pinfunction "TP_TP") (pintype "input"))
      (node (ref "X1") (pin "37") (pinfunction "37_37") (pintype "passive"))
    )
    (net (code "413") (name "UC_FU_850NM_RIGHT_3V3") (class "Default")
      (node (ref "IC10") (pin "3") (pinfunction "IN+_3") (pintype "input"))
      (node (ref "IC20") (pin "3") (pinfunction "I/O2_3") (pintype "passive"))
      (node (ref "R13") (pin "1") (pinfunction "1_1") (pintype "passive"))
      (node (ref "R6") (pin "2") (pinfunction "2_2") (pintype "passive"))
      (node (ref "TP21") (pin "TP") (pinfunction "TP_TP") (pintype "input"))
      (node (ref "X2") (pin "12") (pinfunction "12_12") (pintype "passive"))
    )
    (net (code "414") (name "UC_FU_940NM_LEFT_3V3") (class "Default")
      (node (ref "IC1") (pin "3") (pinfunction "IN+_3") (pintype "input"))
      (node (ref "IC17") (pin "1") (pinfunction "I/O1_1") (pintype "passive"))
      (node (ref "R10") (pin "1") (pinfunction "1_1") (pintype "passive"))
      (node (ref "R3") (pin "2") (pinfunction "2_2") (pintype "passive"))
      (node (ref "TP14") (pin "TP") (pinfunction "TP_TP") (pintype "input"))
      (node (ref "X1") (pin "38") (pinfunction "38_38") (pintype "passive"))
    )
    (net (code "415") (name "UC_FU_940NM_RIGHT_3V3") (class "Default")
      (node (ref "IC20") (pin "1") (pinfunction "I/O1_1") (pintype "passive"))
      (node (ref "IC8") (pin "3") (pinfunction "IN+_3") (pintype "input"))
      (node (ref "R11") (pin "1") (pinfunction "1_1") (pintype "passive"))
      (node (ref "R4") (pin "2") (pinfunction "2_2") (pintype "passive"))
      (node (ref "TP17") (pin "TP") (pinfunction "TP_TP") (pintype "input"))
      (node (ref "X2") (pin "14") (pinfunction "14_14") (pintype "passive"))
    )
    (net (code "416") (name "unconnected-(IC4B-OUT-Pad7)") (class "Default")
      (node (ref "IC4") (pin "7") (pinfunction "OUT_7") (pintype "output"))
    )
    (net (code "417") (name "unconnected-(IC7-DNC-Pad8)") (class "Default")
      (node (ref "IC7") (pin "8") (pinfunction "DNC_8") (pintype "output"))
    )
    (net (code "418") (name "unconnected-(IC7-GPIO1-Pad7)") (class "Default")
      (node (ref "IC7") (pin "7") (pinfunction "GPIO1_7") (pintype "open_collector"))
    )
    (net (code "419") (name "unconnected-(IC9B-Q-Pad9)") (class "Default")
      (node (ref "IC9") (pin "9") (pinfunction "Q_9") (pintype "output"))
    )
    (net (code "420") (name "unconnected-(IC9B-~{Q}-Pad7)") (class "Default")
      (node (ref "IC9") (pin "7") (pinfunction "~{Q}_7") (pintype "output"))
    )
    (net (code "421") (name "unconnected-(IC15-ALERT-Pad3)") (class "Default")
      (node (ref "IC15") (pin "3") (pinfunction "ALERT_3") (pintype "open_collector"))
    )
    (net (code "422") (name "unconnected-(IC16-I{slash}O2-Pad3)") (class "Default")
      (node (ref "IC16") (pin "3") (pinfunction "I/O2_3") (pintype "passive"))
    )
    (net (code "423") (name "unconnected-(IC16-I{slash}O3-Pad4)") (class "Default")
      (node (ref "IC16") (pin "4") (pinfunction "I/O3_4") (pintype "passive"))
    )
    (net (code "424") (name "unconnected-(IC16-I{slash}O4-Pad6)") (class "Default")
      (node (ref "IC16") (pin "6") (pinfunction "I/O4_6") (pintype "passive"))
    )
    (net (code "425") (name "unconnected-(IC17-I{slash}O4-Pad6)") (class "Default")
      (node (ref "IC17") (pin "6") (pinfunction "I/O4_6") (pintype "passive"))
    )
    (net (code "426") (name "unconnected-(IC24-ALERT-Pad3)") (class "Default")
      (node (ref "IC24") (pin "3") (pinfunction "ALERT_3") (pintype "open_collector"))
    )
    (net (code "427") (name "unconnected-(IC25-DNC2-Pad7)") (class "Default")
      (node (ref "IC25") (pin "7") (pinfunction "DNC2_7") (pintype "output"))
    )
    (net (code "428") (name "unconnected-(IC25-DNC3-Pad8)") (class "Default")
      (node (ref "IC25") (pin "8") (pinfunction "DNC3_8") (pintype "output"))
    )
    (net (code "429") (name "unconnected-(X1-Pad36)") (class "Default")
      (node (ref "X1") (pin "36") (pinfunction "36_36") (pintype "passive"))
    )
    (net (code "430") (name "unconnected-(X3-Pad13)") (class "Default")
      (node (ref "X3") (pin "13") (pinfunction "13_13") (pintype "bidirectional"))
    )
    (net (code "431") (name "unconnected-(X3-Pad14)") (class "Default")
      (node (ref "X3") (pin "14") (pinfunction "14_14") (pintype "bidirectional"))
    )
    (net (code "432") (name "unconnected-(X3-Pad17)") (class "Default")
      (node (ref "X3") (pin "17") (pinfunction "17_17") (pintype "bidirectional"))
    )
    (net (code "433") (name "unconnected-(X3-Pad18)") (class "Default")
      (node (ref "X3") (pin "18") (pinfunction "18_18") (pintype "bidirectional"))
    )
    (net (code "434") (name "unconnected-(X3-Pad19)") (class "Default")
      (node (ref "X3") (pin "19") (pinfunction "19_19") (pintype "bidirectional"))
    )
    (net (code "435") (name "unconnected-(X3-Pad20)") (class "Default")
      (node (ref "X3") (pin "20") (pinfunction "20_20") (pintype "bidirectional"))
    )
    (net (code "436") (name "unconnected-(X3-Pad29)") (class "Default")
      (node (ref "X3") (pin "29") (pinfunction "29_29") (pintype "bidirectional"))
    )
    (net (code "437") (name "unconnected-(X3-Pad30)") (class "Default")
      (node (ref "X3") (pin "30") (pinfunction "30_30") (pintype "bidirectional"))
    )
    (net (code "438") (name "unconnected-(X5-Pad7)") (class "Default")
      (node (ref "X5") (pin "7") (pinfunction "7_7") (pintype "passive"))
    )
    (net (code "439") (name "unconnected-(X5-Pad20)") (class "Default")
      (node (ref "X5") (pin "20") (pinfunction "20_20") (pintype "passive"))
    )
  )
)
